# Led_Driver.net
KiCad netlist of a schematic drawn in EAGLE
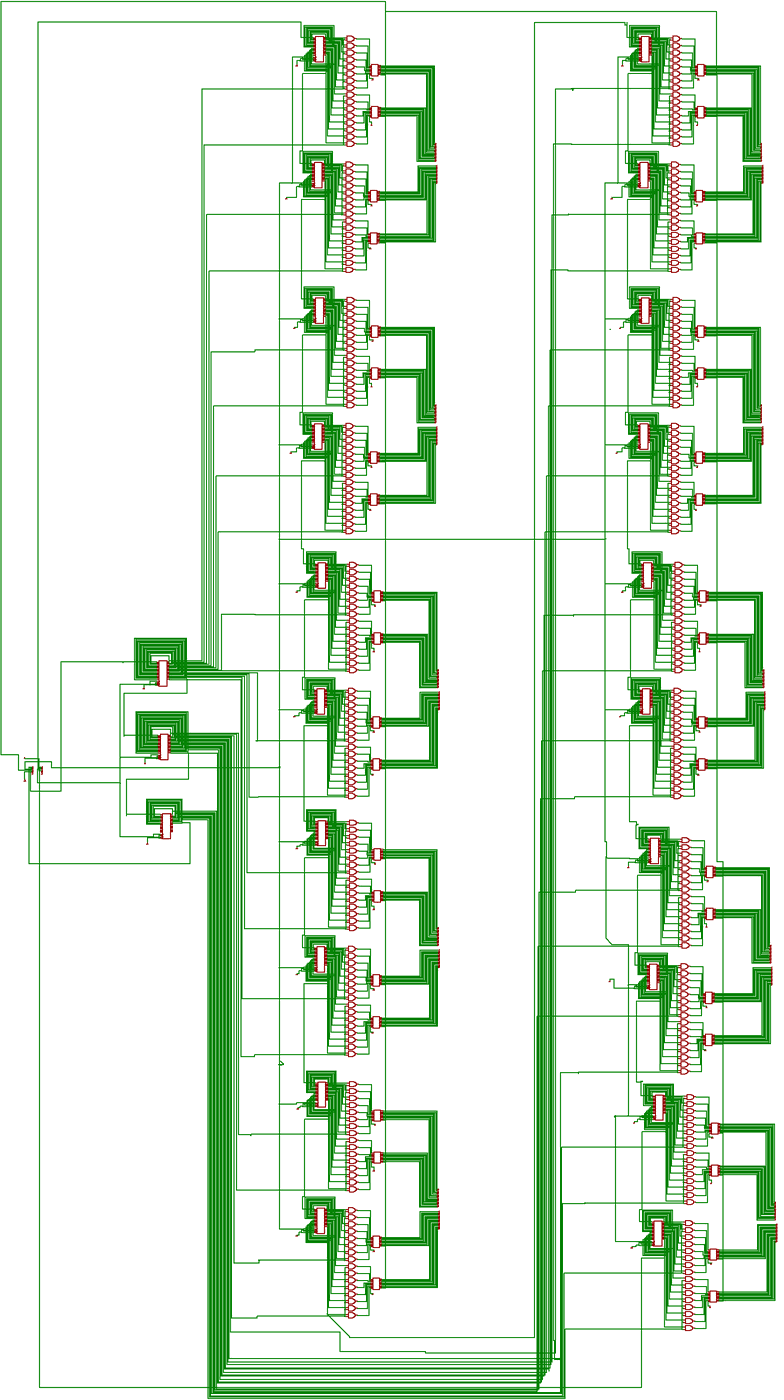
[diagram p0: schematic, sheet 1, overview]
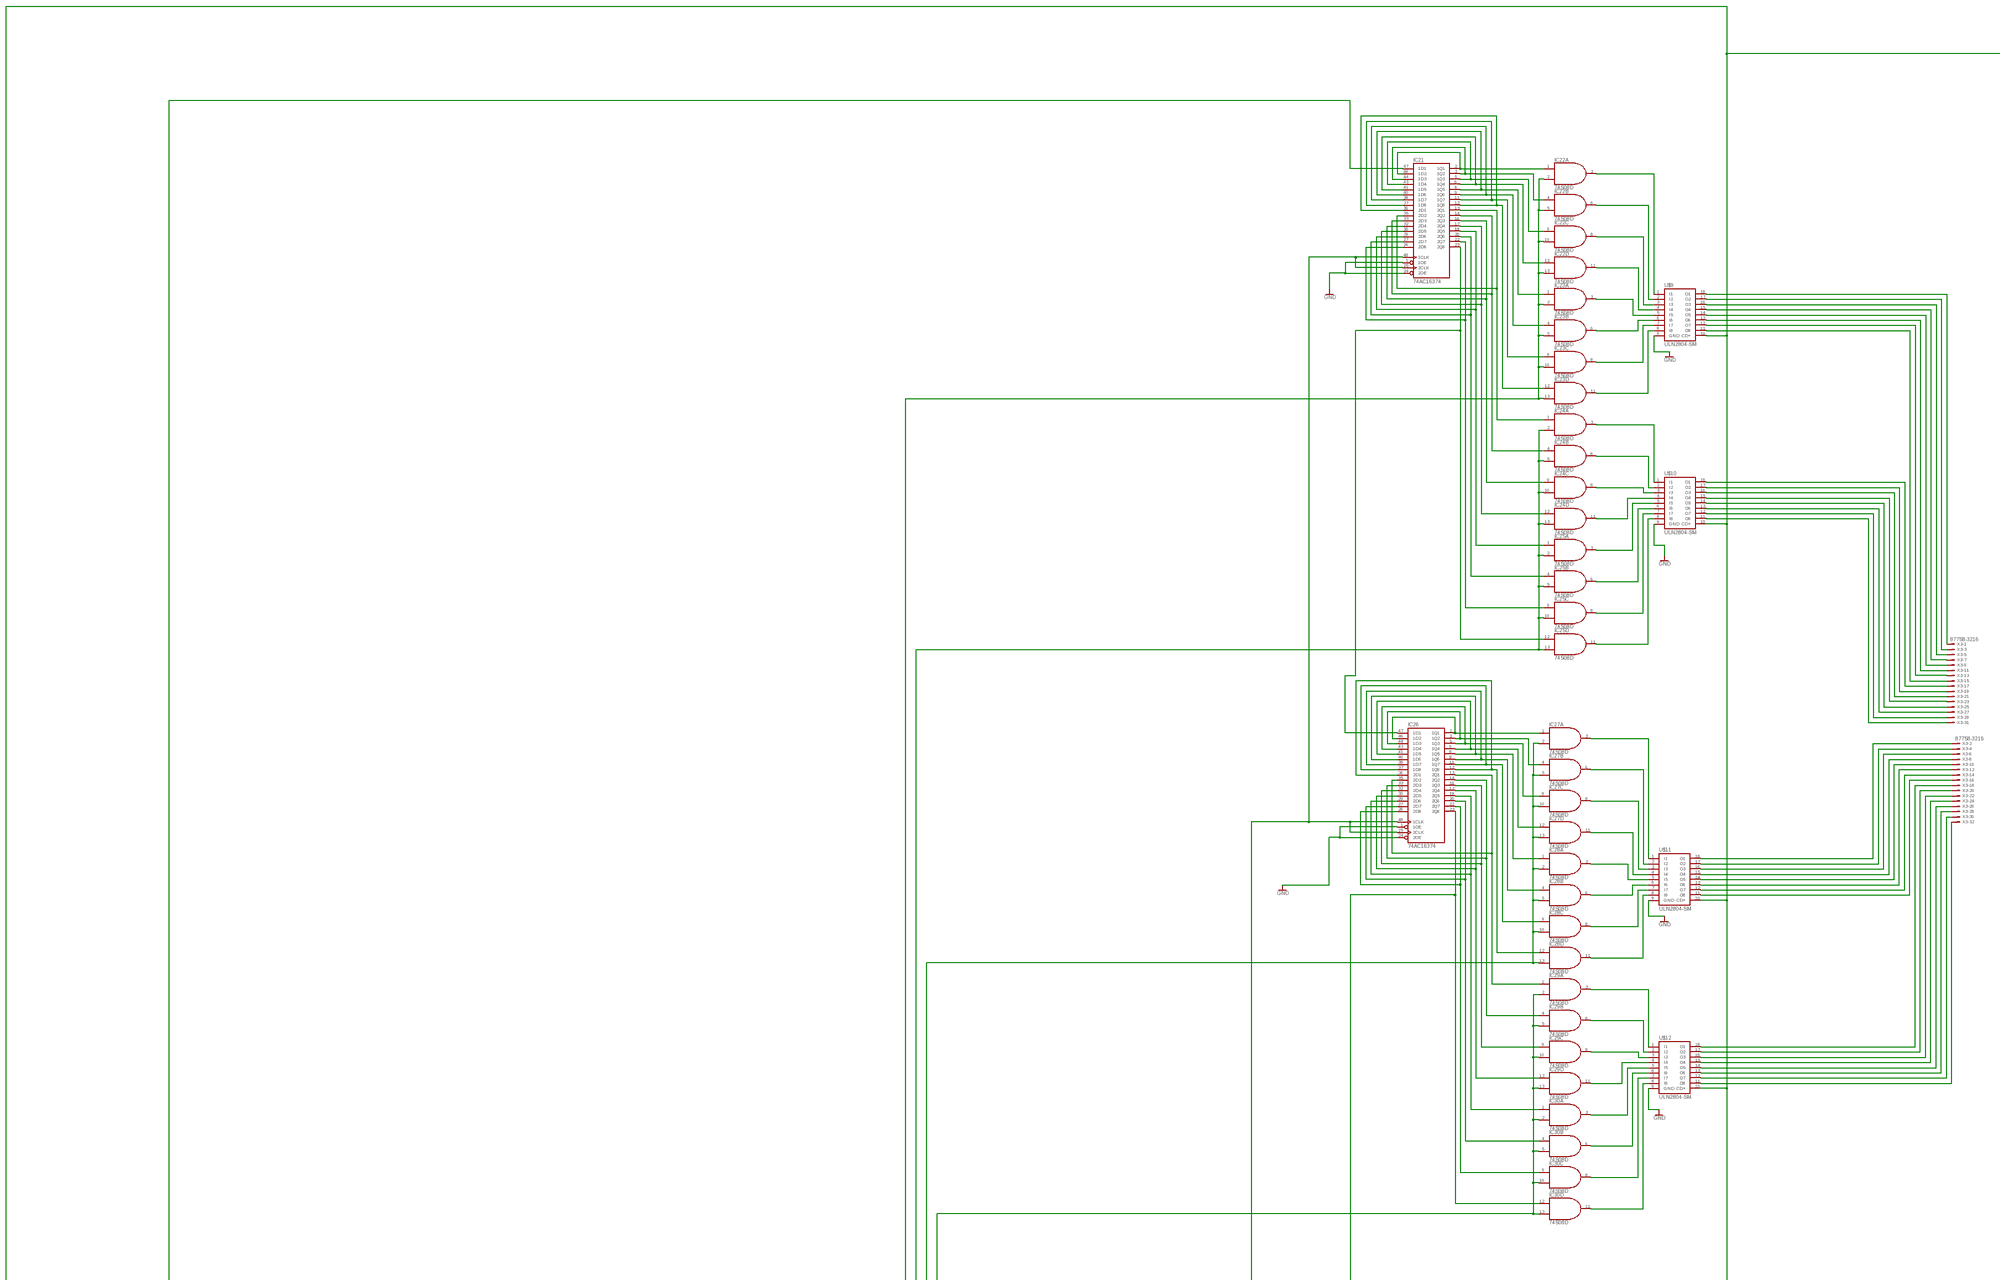
[diagram p1: schematic, sheet 1, part 1 of 8]
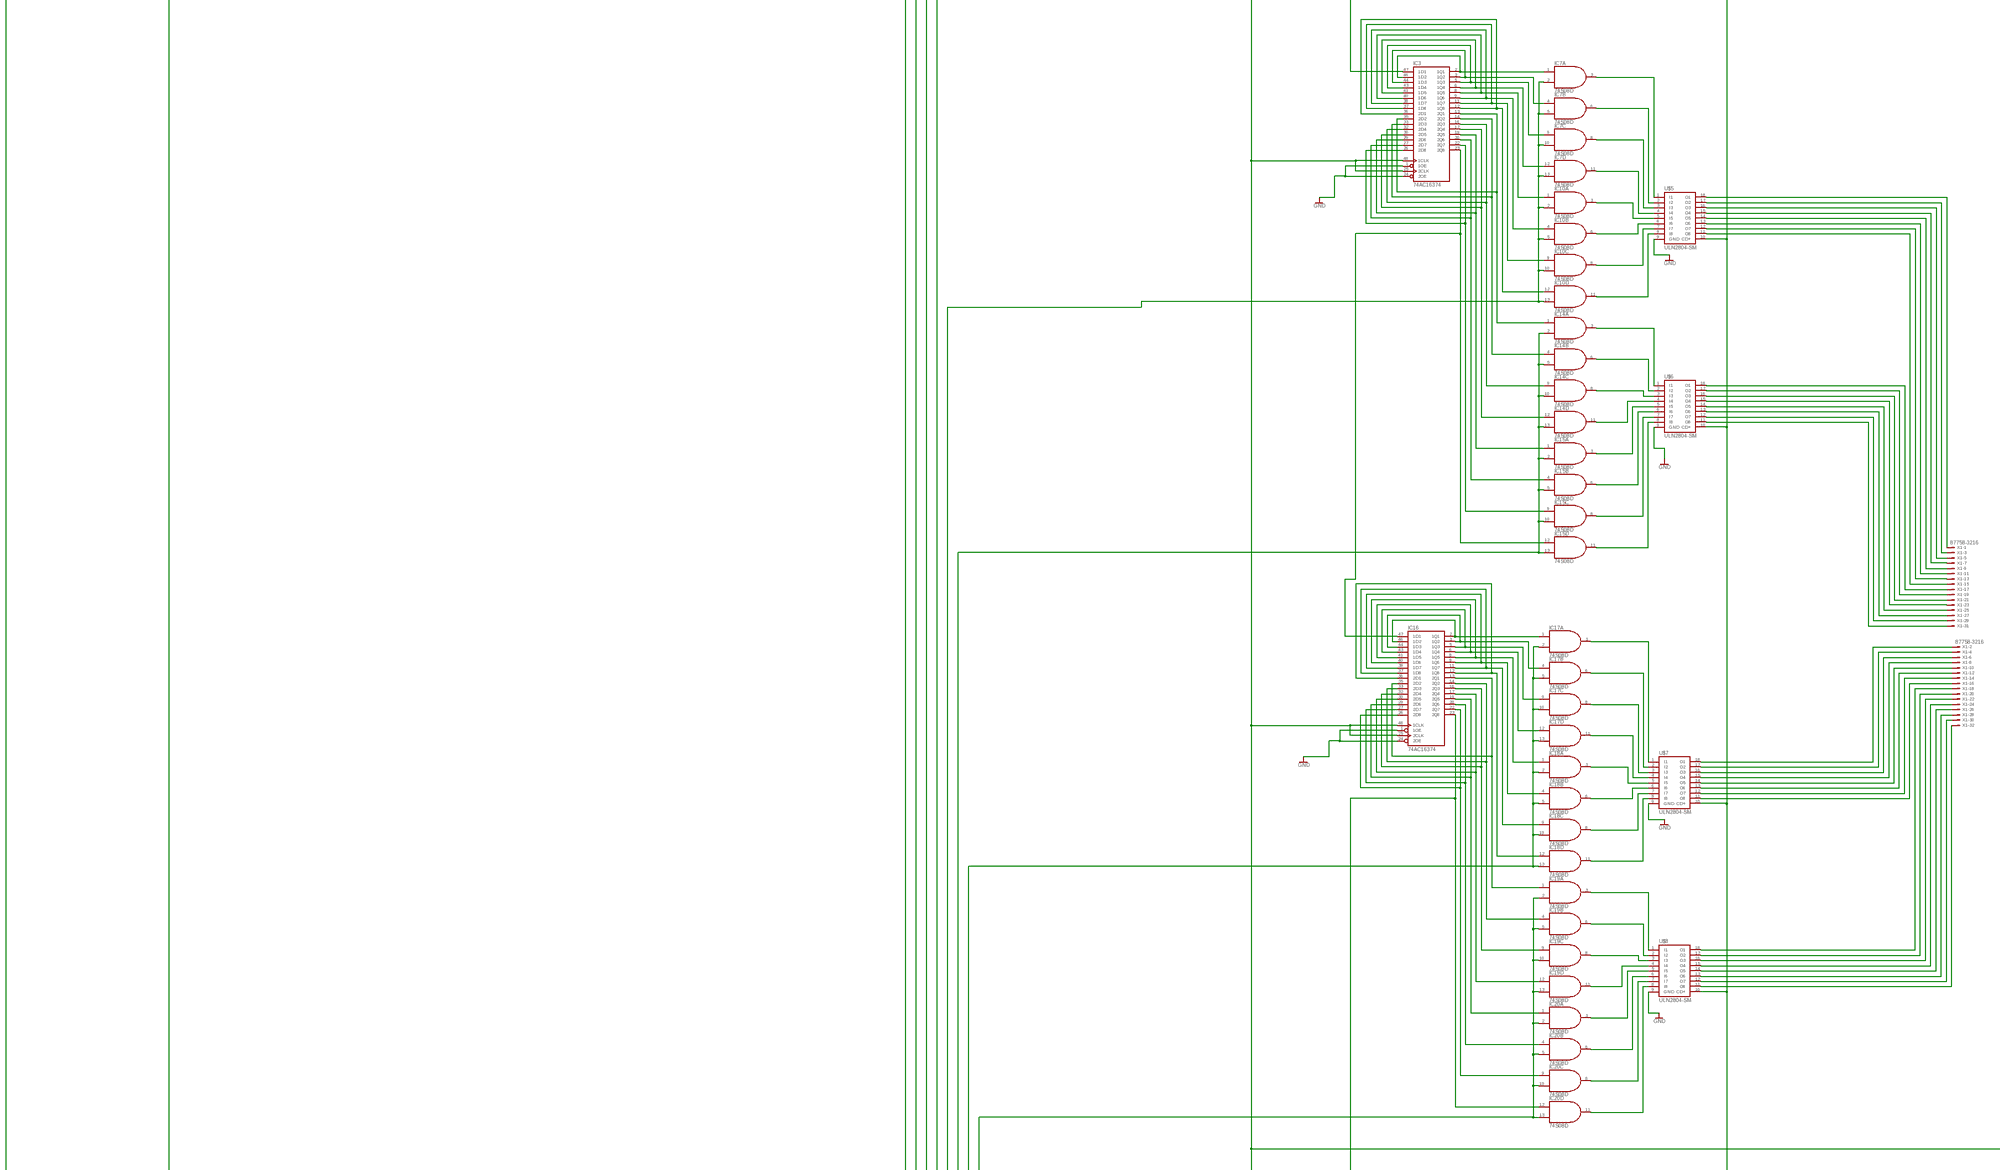
[diagram p2: schematic, sheet 1, part 2 of 8]
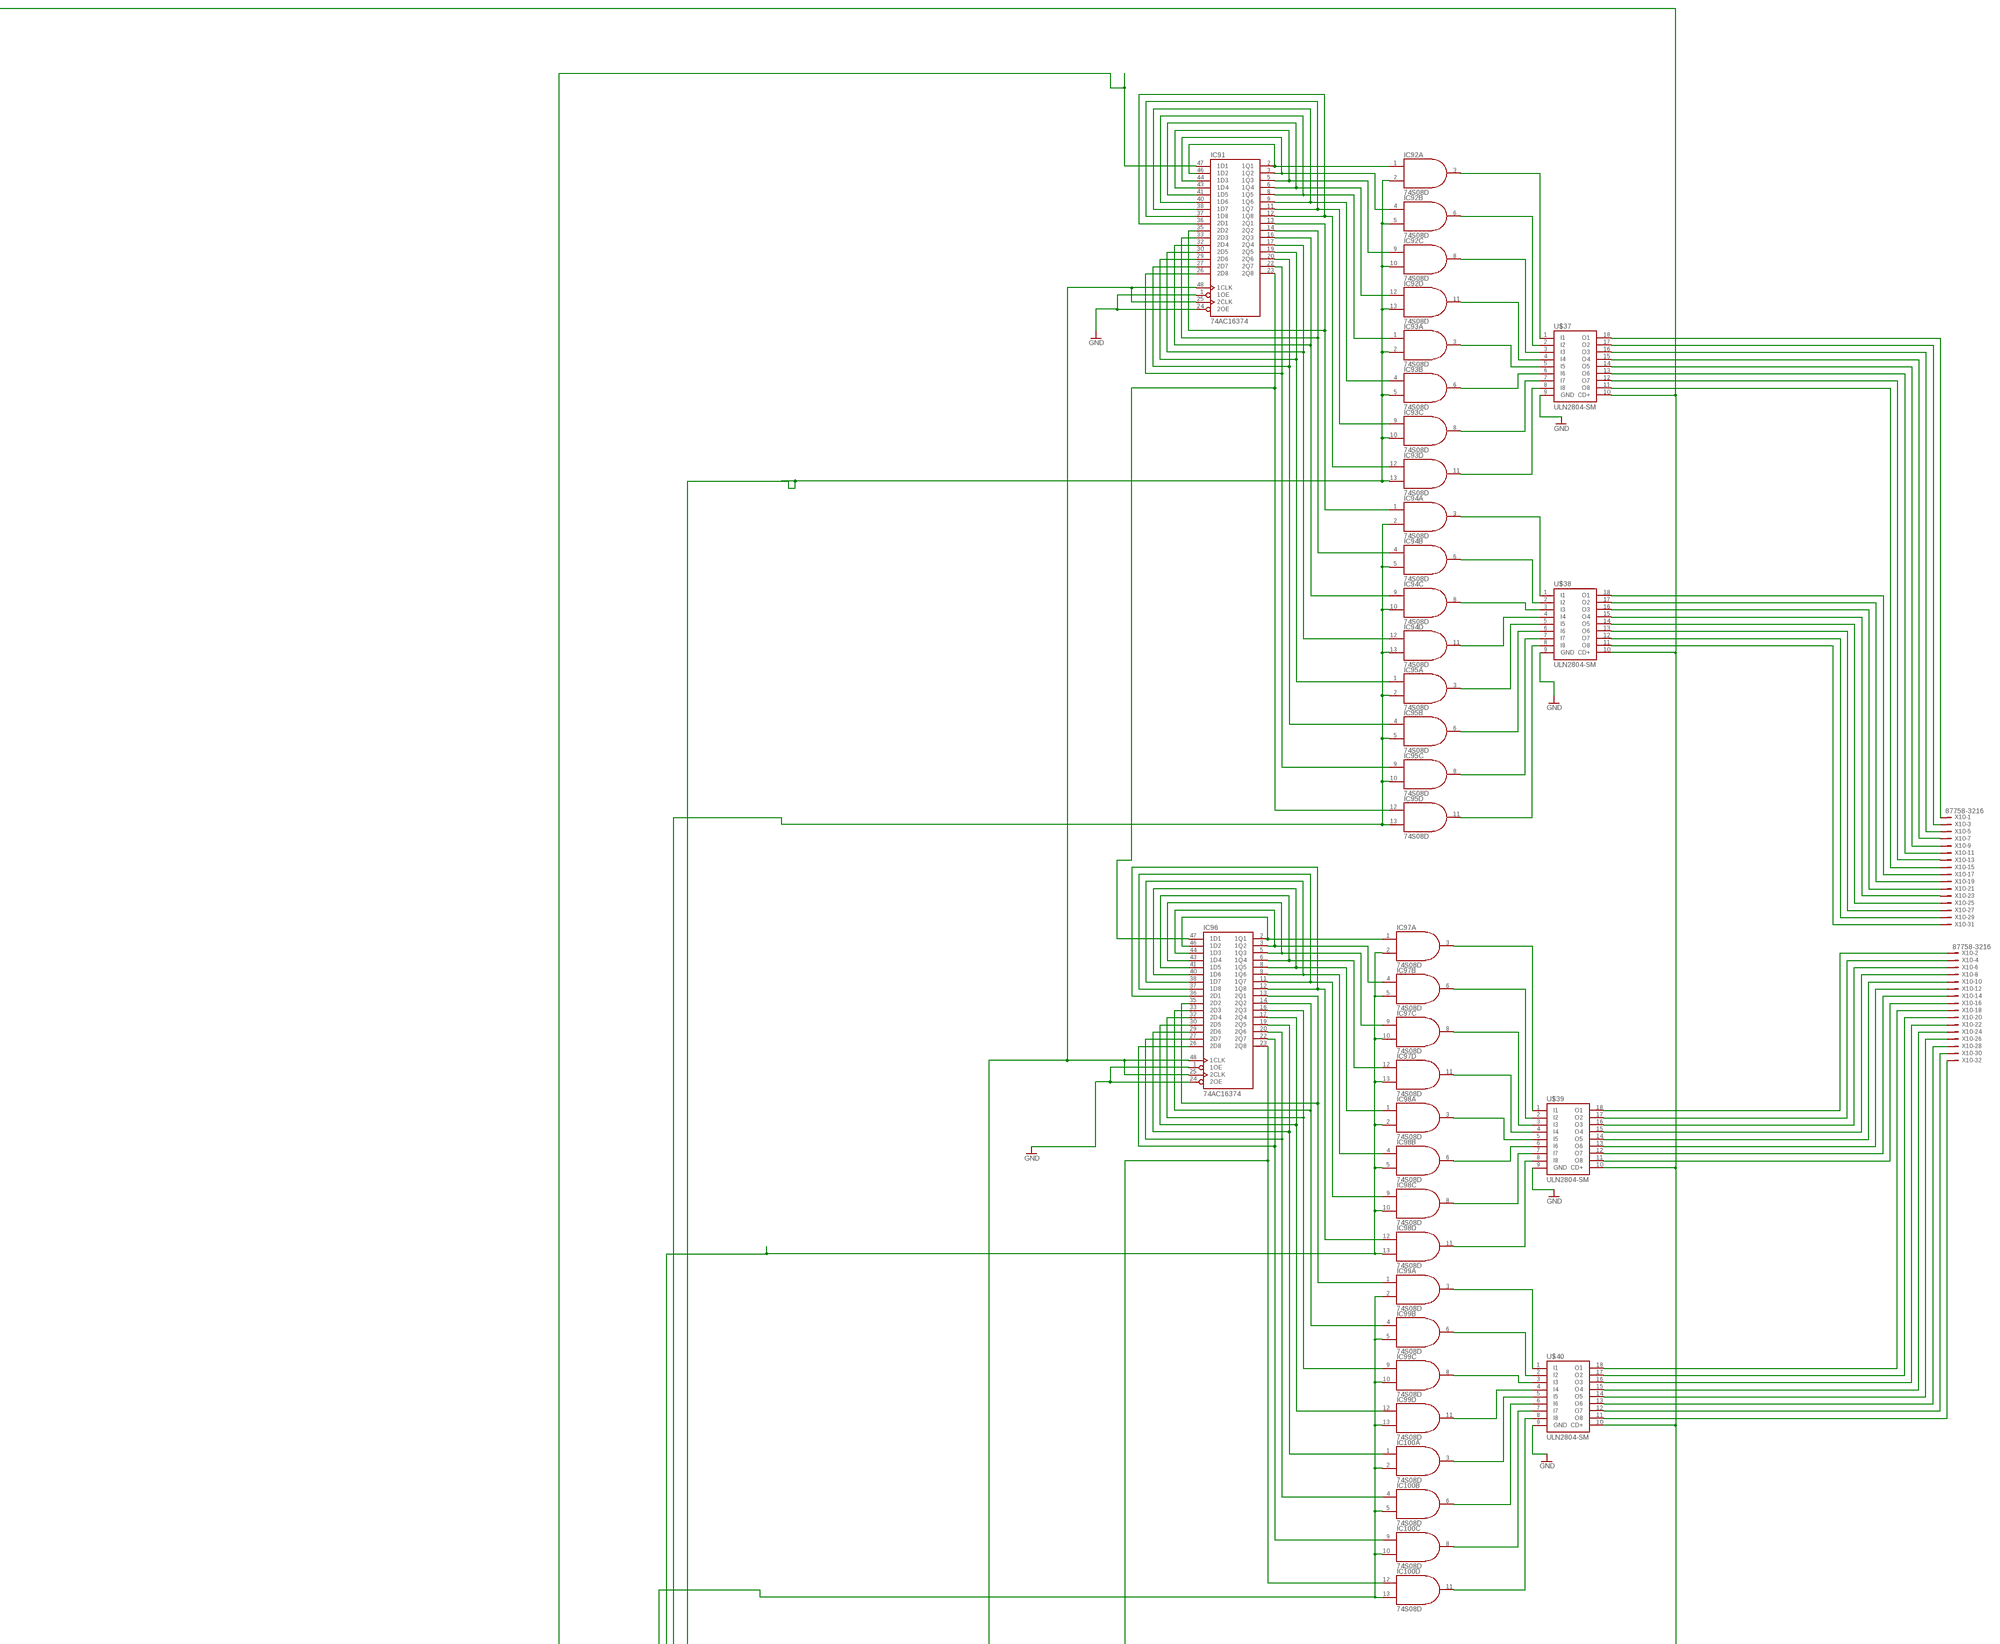
[diagram p3: schematic, sheet 1, part 3 of 8]
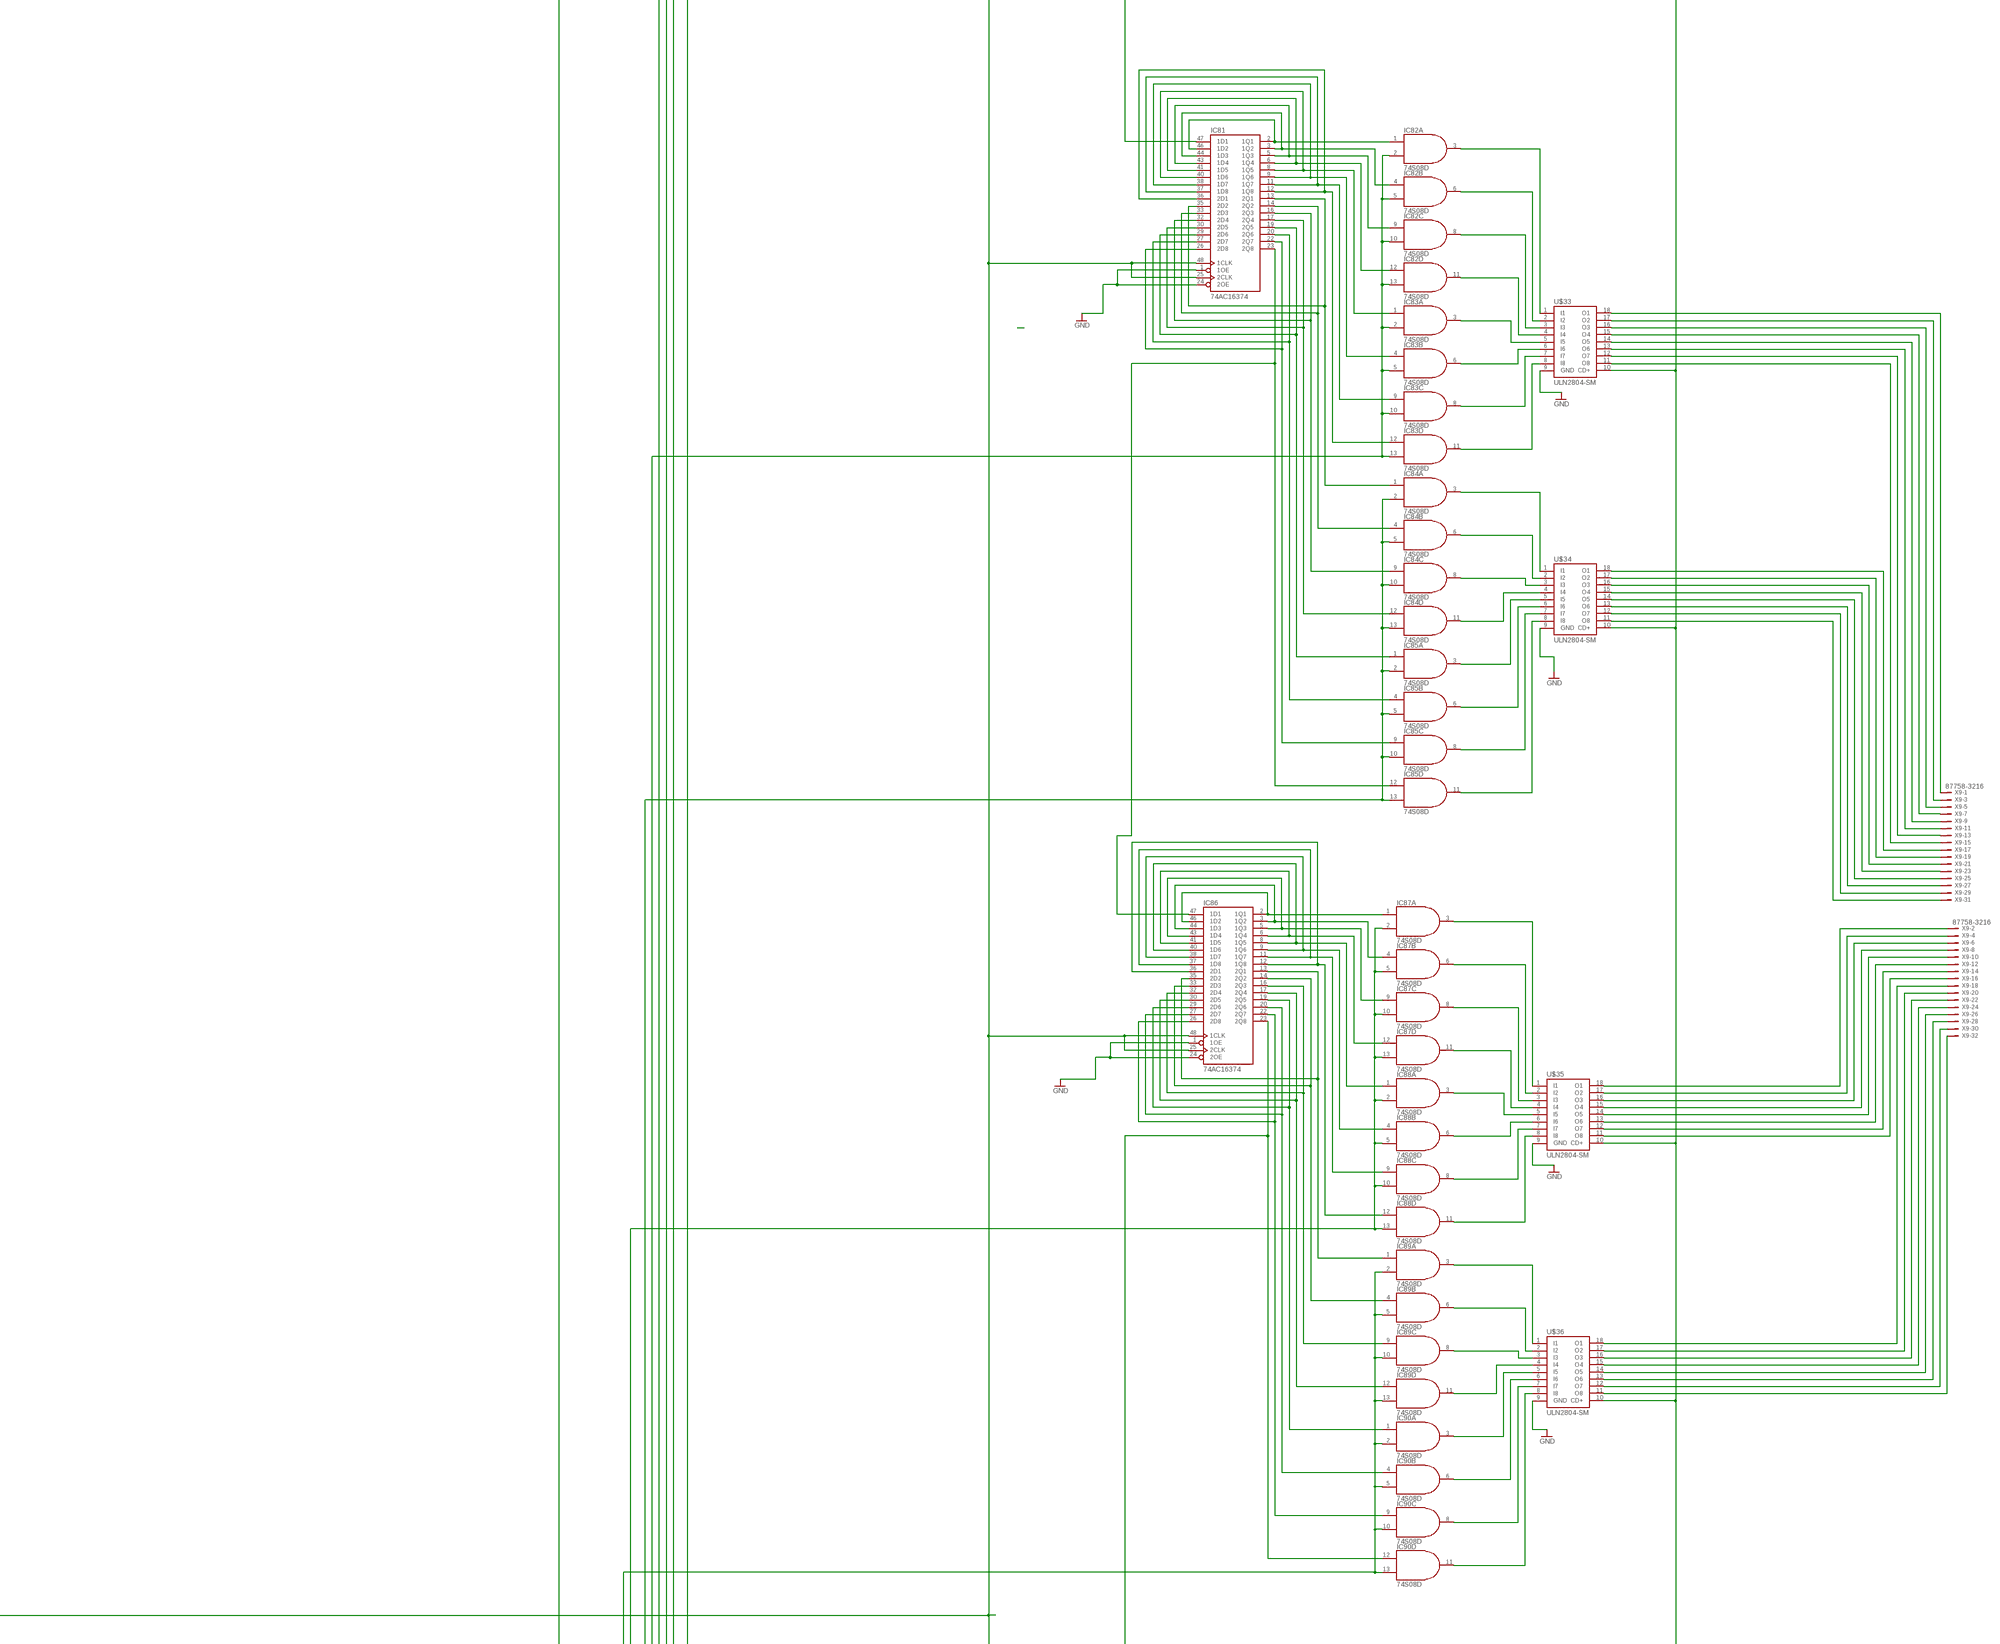
[diagram p4: schematic, sheet 1, part 4 of 8]
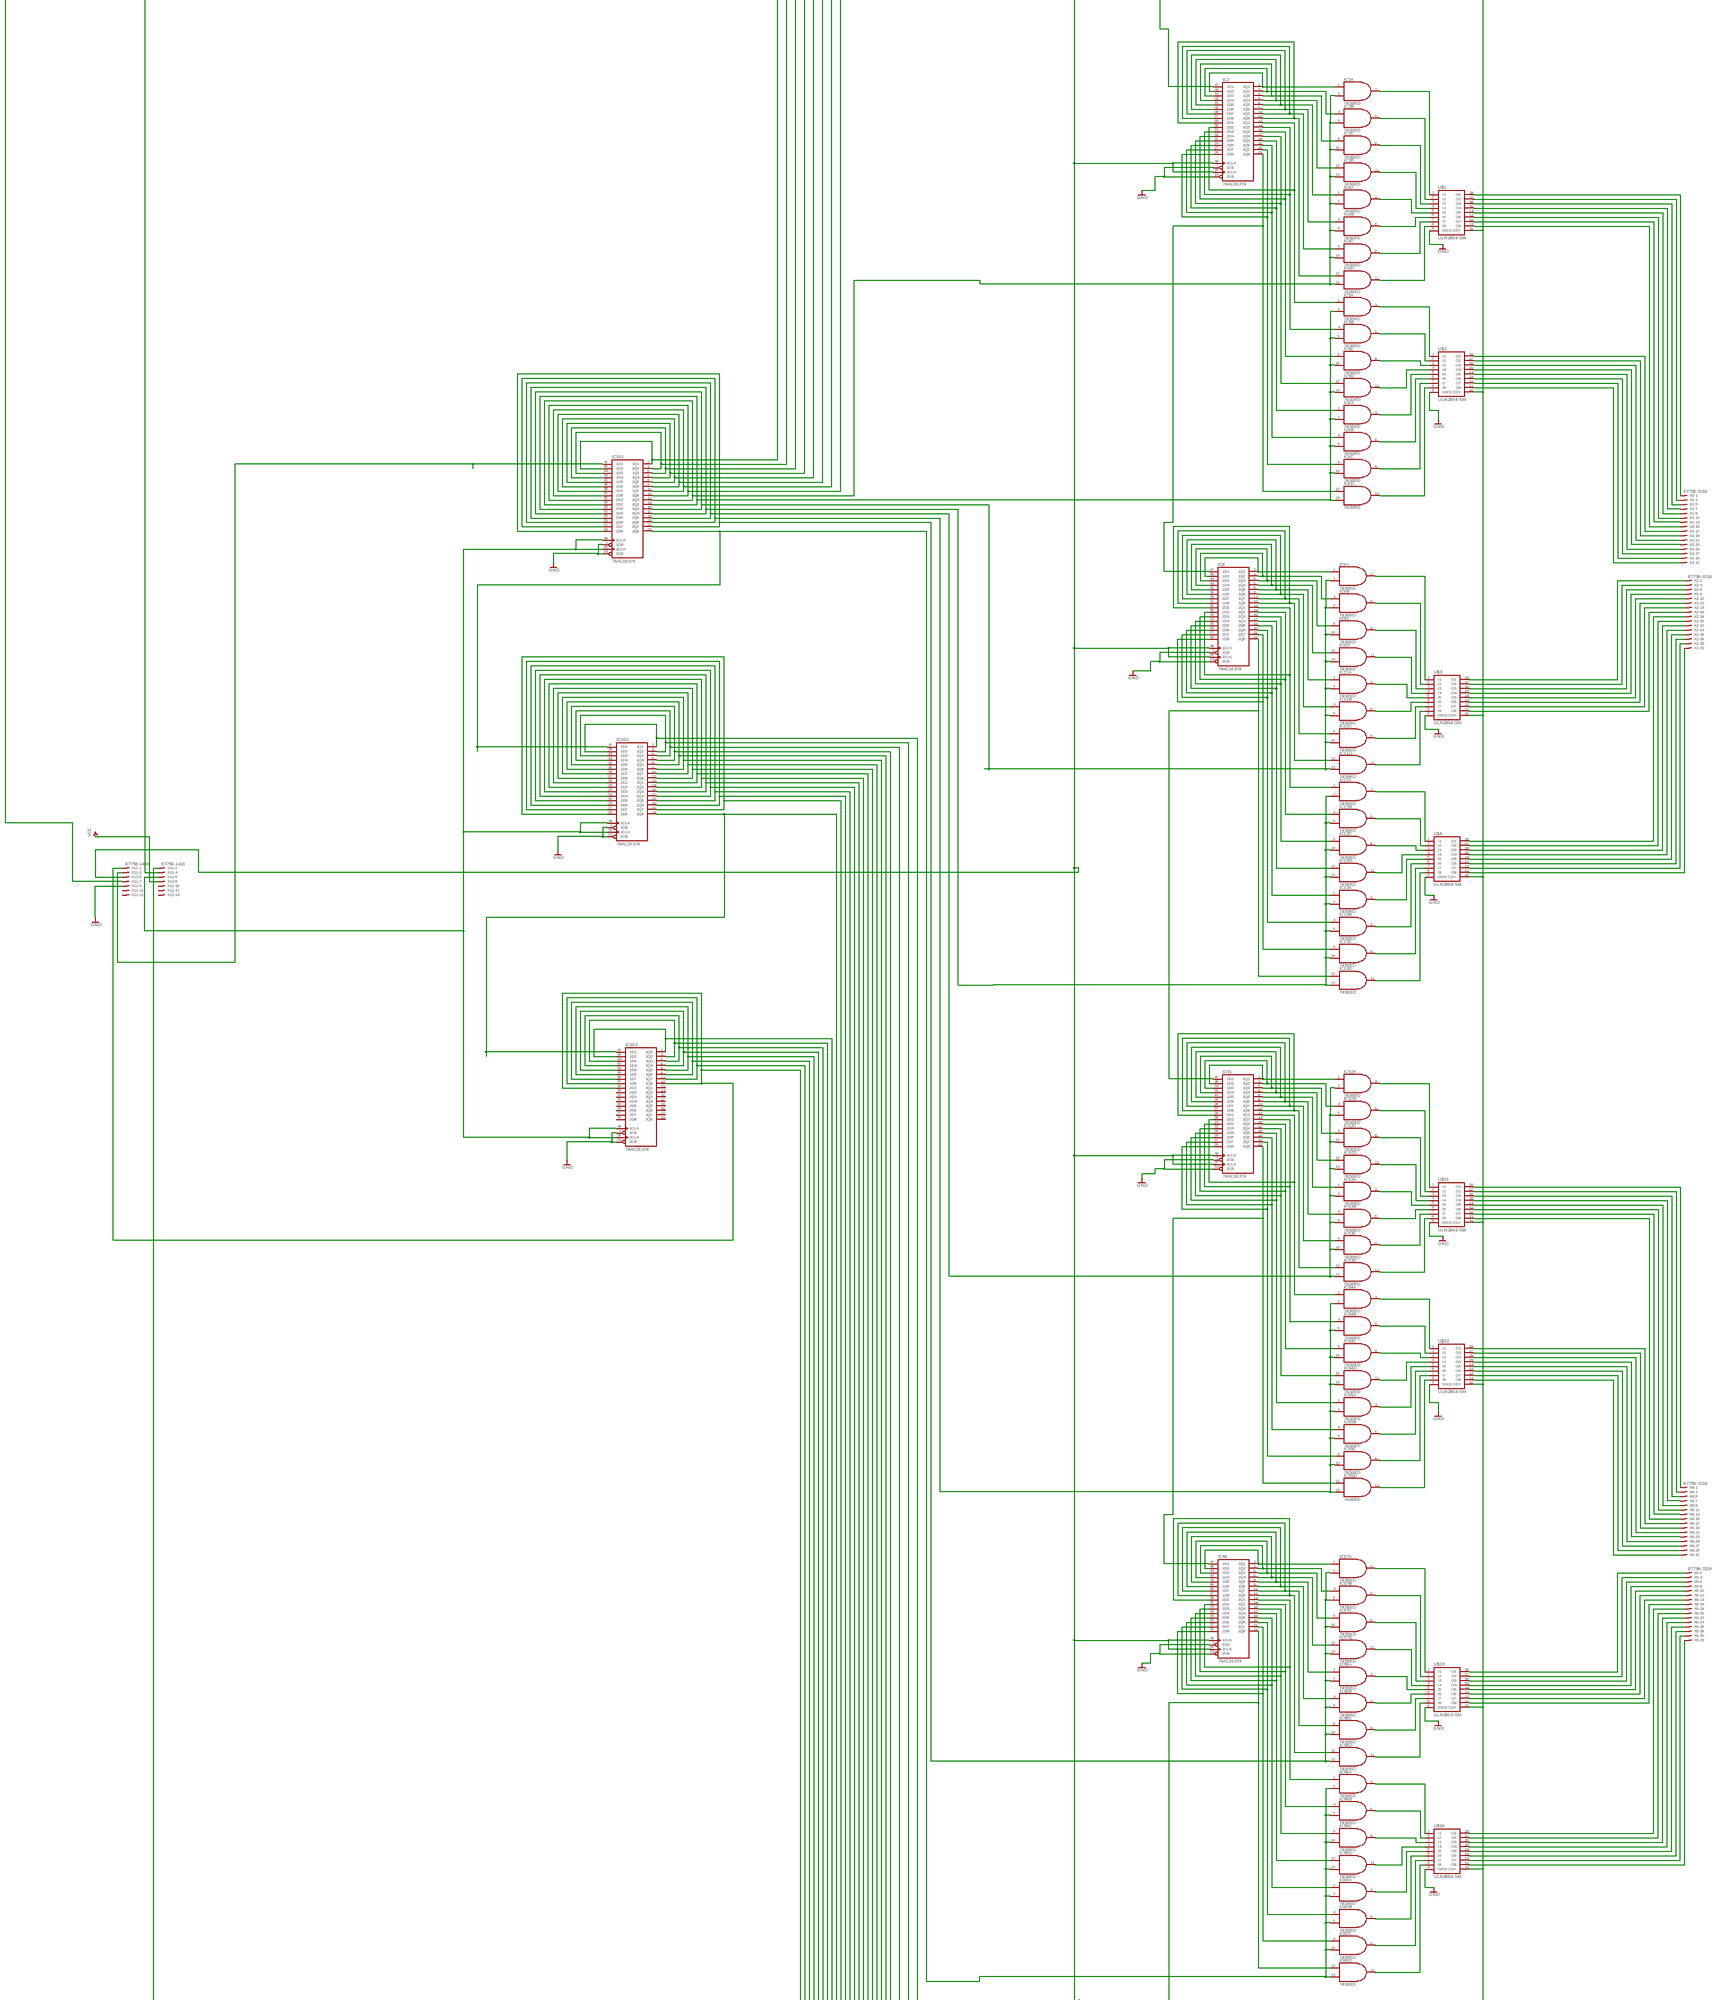
[diagram p5: schematic, sheet 1, part 5 of 8]
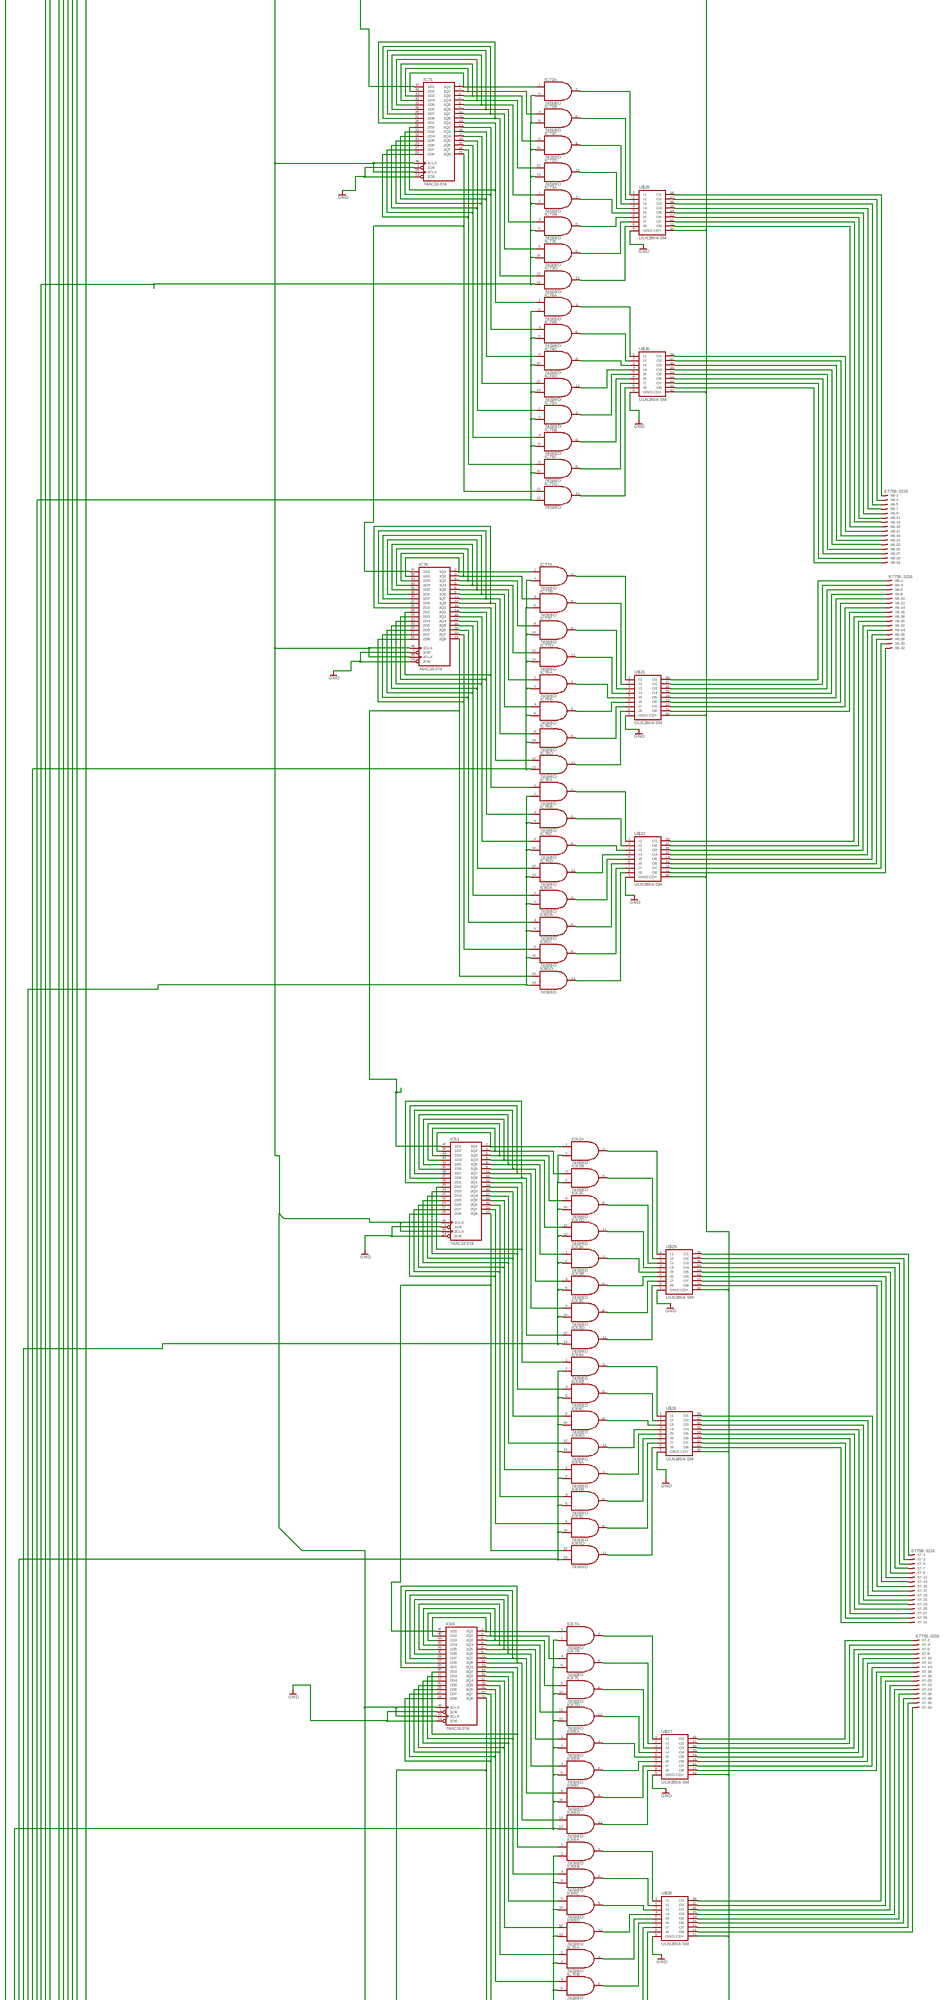
[diagram p6: schematic, sheet 1, part 6 of 8]
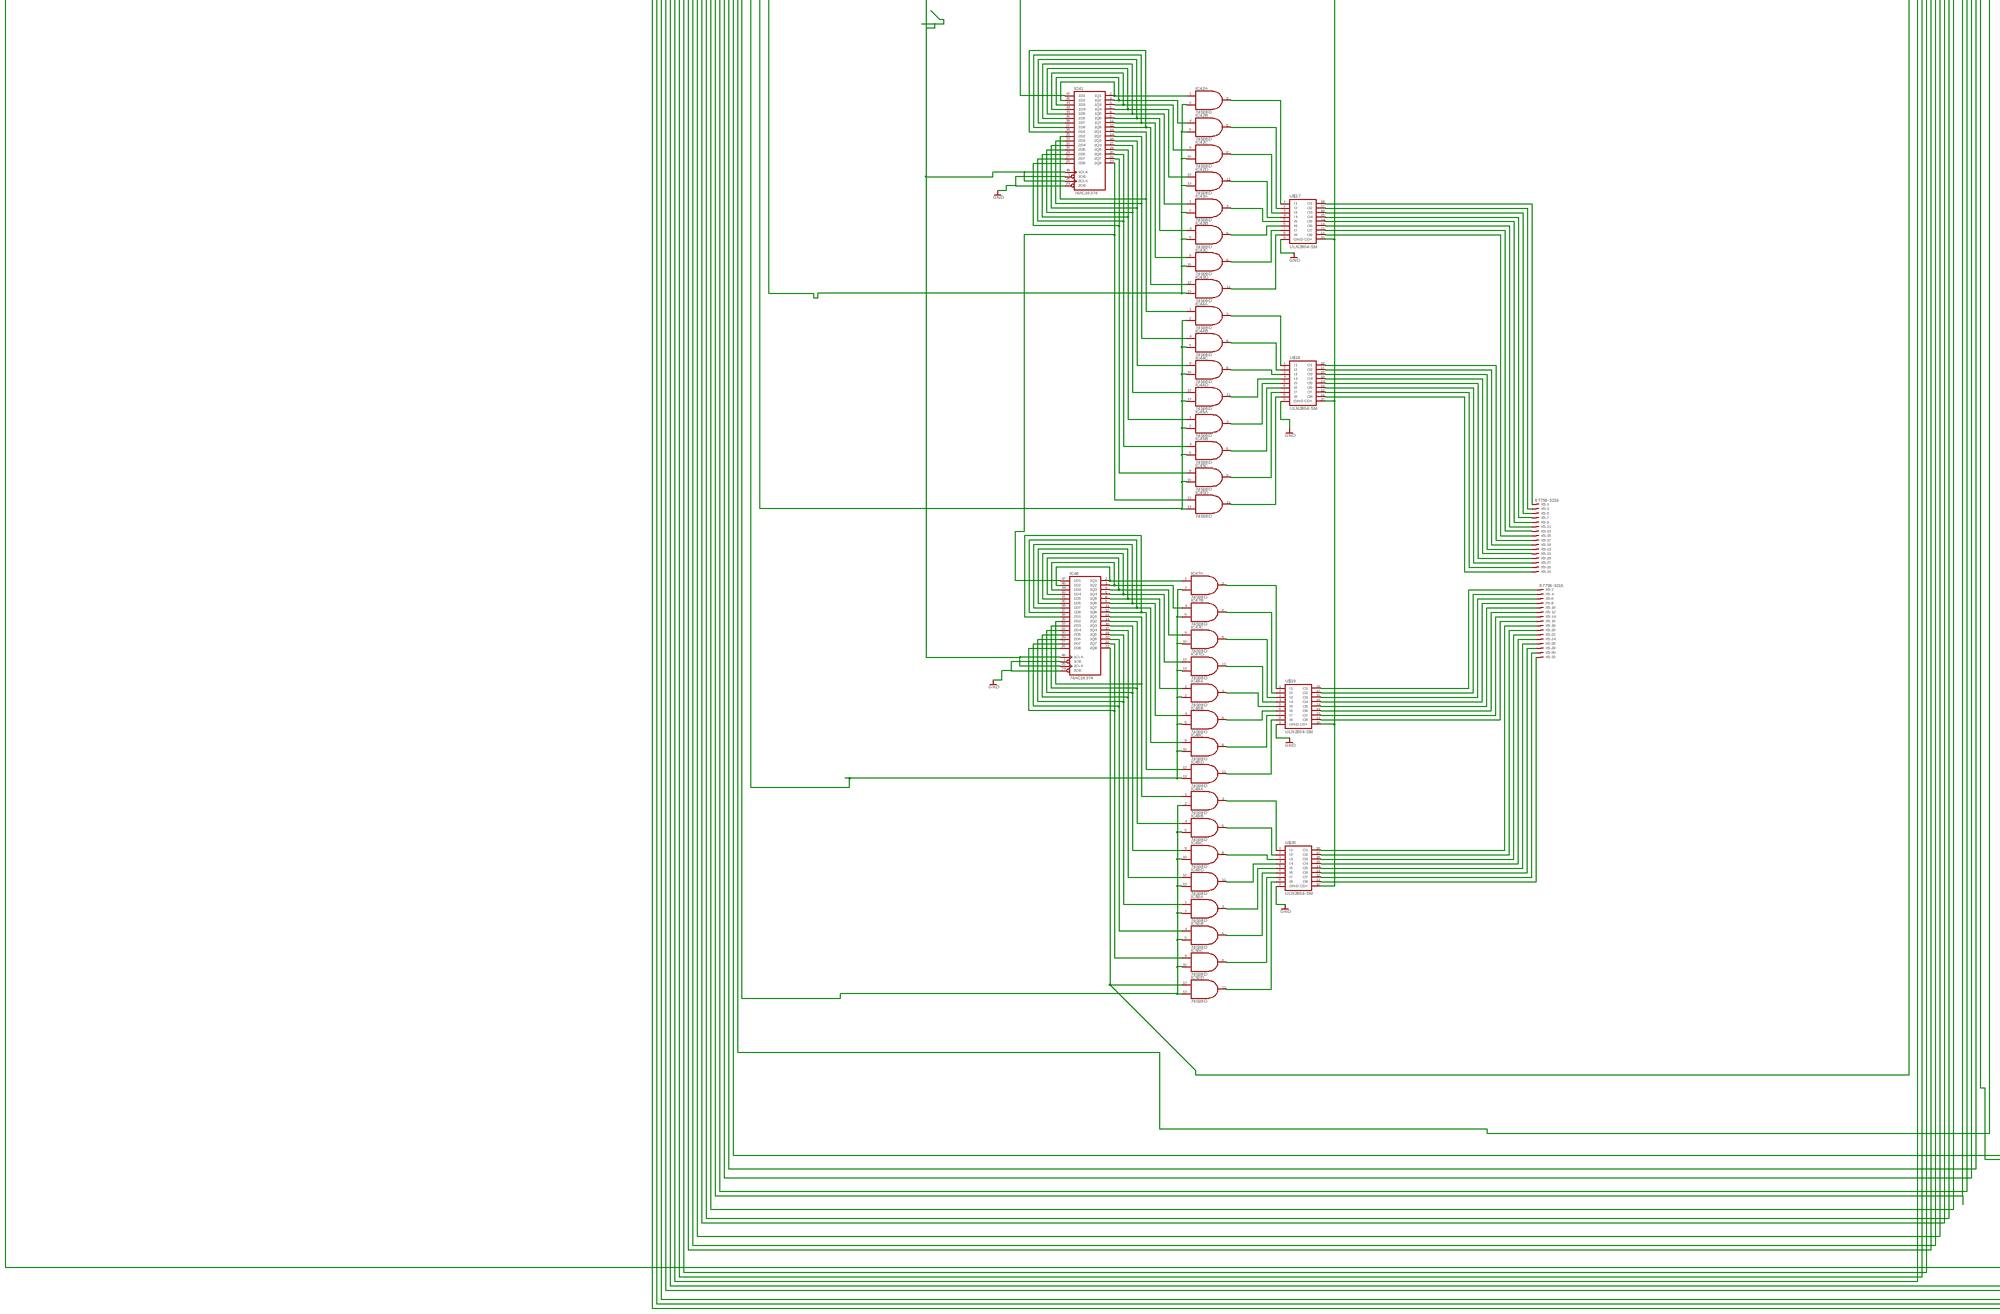
[diagram p7: schematic, sheet 1, part 7 of 8]
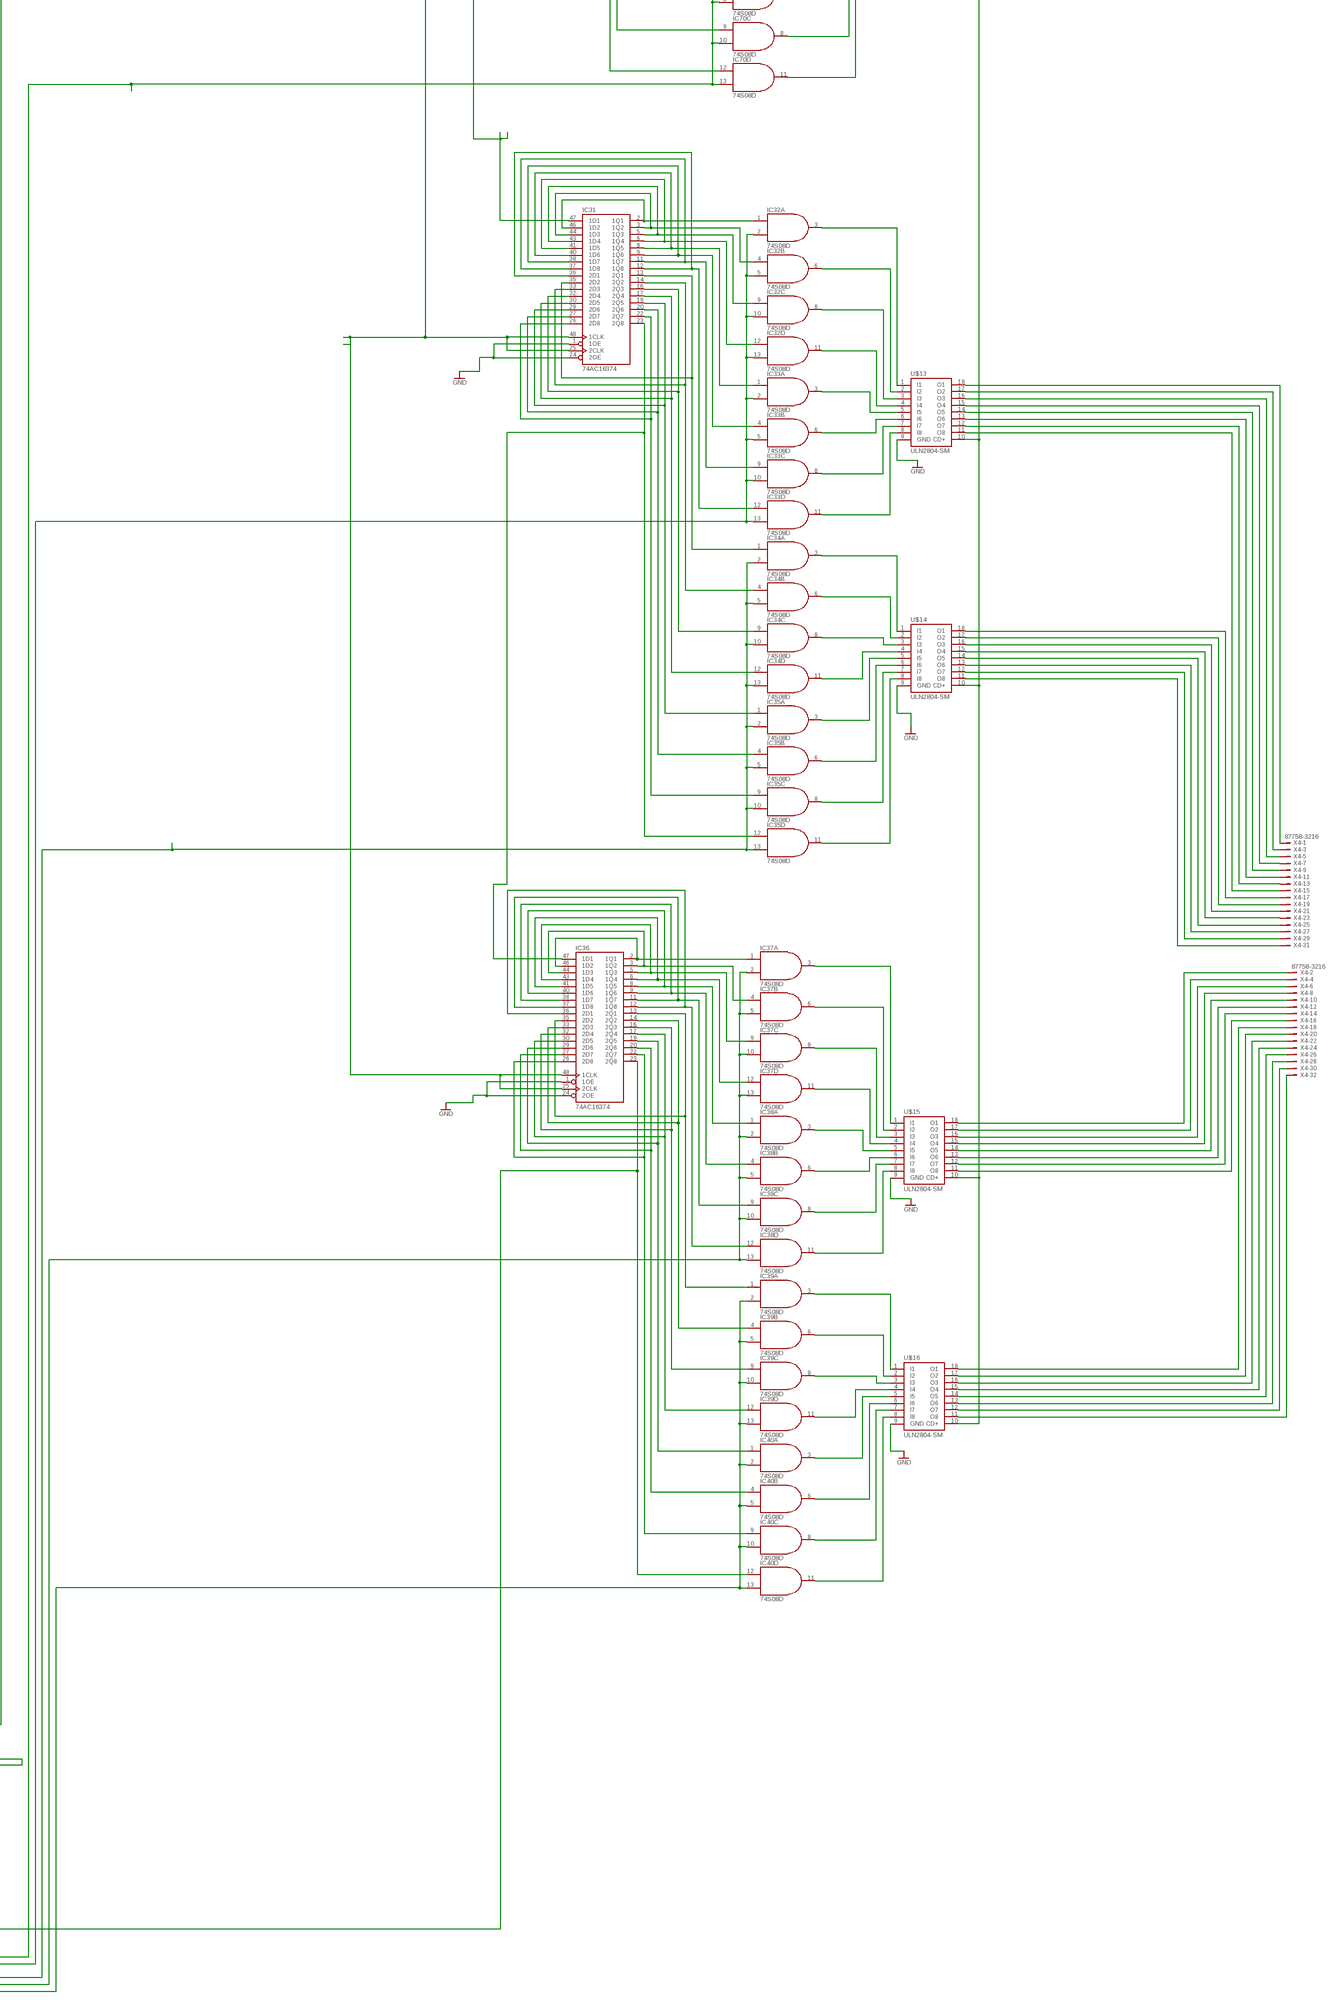
[diagram p8: schematic, sheet 1, part 8 of 8]

(export (version "E")
  (design (tool "Eeschema 10.0.6"))
  (components
    (comp (ref "IC1")
      (value "74AC16374")
      (footprint "eagle-import:SSOP48DL")
      (libsource (lib "eagle-import") (part "74AC16374"))
    )
    (comp (ref "IC2")
      (value "74S08D")
      (footprint "eagle-import:SO14")
      (libsource (lib "eagle-import") (part "7408DS"))
    )
    (comp (ref "IC3")
      (value "74AC16374")
      (footprint "eagle-import:SSOP48DL")
      (libsource (lib "eagle-import") (part "74AC16374"))
    )
    (comp (ref "IC4")
      (value "74S08D")
      (footprint "eagle-import:SO14")
      (libsource (lib "eagle-import") (part "7408DS"))
    )
    (comp (ref "IC5")
      (value "74S08D")
      (footprint "eagle-import:SO14")
      (libsource (lib "eagle-import") (part "7408DS"))
    )
    (comp (ref "IC6")
      (value "74S08D")
      (footprint "eagle-import:SO14")
      (libsource (lib "eagle-import") (part "7408DS"))
    )
    (comp (ref "IC7")
      (value "74S08D")
      (footprint "eagle-import:SO14")
      (libsource (lib "eagle-import") (part "7408DS"))
    )
    (comp (ref "IC8")
      (value "74AC16374")
      (footprint "eagle-import:SSOP48DL")
      (libsource (lib "eagle-import") (part "74AC16374"))
    )
    (comp (ref "IC9")
      (value "74S08D")
      (footprint "eagle-import:SO14")
      (libsource (lib "eagle-import") (part "7408DS"))
    )
    (comp (ref "IC10")
      (value "74S08D")
      (footprint "eagle-import:SO14")
      (libsource (lib "eagle-import") (part "7408DS"))
    )
    (comp (ref "IC11")
      (value "74S08D")
      (footprint "eagle-import:SO14")
      (libsource (lib "eagle-import") (part "7408DS"))
    )
    (comp (ref "IC12")
      (value "74S08D")
      (footprint "eagle-import:SO14")
      (libsource (lib "eagle-import") (part "7408DS"))
    )
    (comp (ref "IC13")
      (value "74S08D")
      (footprint "eagle-import:SO14")
      (libsource (lib "eagle-import") (part "7408DS"))
    )
    (comp (ref "IC14")
      (value "74S08D")
      (footprint "eagle-import:SO14")
      (libsource (lib "eagle-import") (part "7408DS"))
    )
    (comp (ref "IC15")
      (value "74S08D")
      (footprint "eagle-import:SO14")
      (libsource (lib "eagle-import") (part "7408DS"))
    )
    (comp (ref "IC16")
      (value "74AC16374")
      (footprint "eagle-import:SSOP48DL")
      (libsource (lib "eagle-import") (part "74AC16374"))
    )
    (comp (ref "IC17")
      (value "74S08D")
      (footprint "eagle-import:SO14")
      (libsource (lib "eagle-import") (part "7408DS"))
    )
    (comp (ref "IC18")
      (value "74S08D")
      (footprint "eagle-import:SO14")
      (libsource (lib "eagle-import") (part "7408DS"))
    )
    (comp (ref "IC19")
      (value "74S08D")
      (footprint "eagle-import:SO14")
      (libsource (lib "eagle-import") (part "7408DS"))
    )
    (comp (ref "IC20")
      (value "74S08D")
      (footprint "eagle-import:SO14")
      (libsource (lib "eagle-import") (part "7408DS"))
    )
    (comp (ref "IC21")
      (value "74AC16374")
      (footprint "eagle-import:SSOP48DL")
      (libsource (lib "eagle-import") (part "74AC16374"))
    )
    (comp (ref "IC22")
      (value "74S08D")
      (footprint "eagle-import:SO14")
      (libsource (lib "eagle-import") (part "7408DS"))
    )
    (comp (ref "IC23")
      (value "74S08D")
      (footprint "eagle-import:SO14")
      (libsource (lib "eagle-import") (part "7408DS"))
    )
    (comp (ref "IC24")
      (value "74S08D")
      (footprint "eagle-import:SO14")
      (libsource (lib "eagle-import") (part "7408DS"))
    )
    (comp (ref "IC25")
      (value "74S08D")
      (footprint "eagle-import:SO14")
      (libsource (lib "eagle-import") (part "7408DS"))
    )
    (comp (ref "IC26")
      (value "74AC16374")
      (footprint "eagle-import:SSOP48DL")
      (libsource (lib "eagle-import") (part "74AC16374"))
    )
    (comp (ref "IC27")
      (value "74S08D")
      (footprint "eagle-import:SO14")
      (libsource (lib "eagle-import") (part "7408DS"))
    )
    (comp (ref "IC28")
      (value "74S08D")
      (footprint "eagle-import:SO14")
      (libsource (lib "eagle-import") (part "7408DS"))
    )
    (comp (ref "IC29")
      (value "74S08D")
      (footprint "eagle-import:SO14")
      (libsource (lib "eagle-import") (part "7408DS"))
    )
    (comp (ref "IC30")
      (value "74S08D")
      (footprint "eagle-import:SO14")
      (libsource (lib "eagle-import") (part "7408DS"))
    )
    (comp (ref "IC31")
      (value "74AC16374")
      (footprint "eagle-import:SSOP48DL")
      (libsource (lib "eagle-import") (part "74AC16374"))
    )
    (comp (ref "IC32")
      (value "74S08D")
      (footprint "eagle-import:SO14")
      (libsource (lib "eagle-import") (part "7408DS"))
    )
    (comp (ref "IC33")
      (value "74S08D")
      (footprint "eagle-import:SO14")
      (libsource (lib "eagle-import") (part "7408DS"))
    )
    (comp (ref "IC34")
      (value "74S08D")
      (footprint "eagle-import:SO14")
      (libsource (lib "eagle-import") (part "7408DS"))
    )
    (comp (ref "IC35")
      (value "74S08D")
      (footprint "eagle-import:SO14")
      (libsource (lib "eagle-import") (part "7408DS"))
    )
    (comp (ref "IC36")
      (value "74AC16374")
      (footprint "eagle-import:SSOP48DL")
      (libsource (lib "eagle-import") (part "74AC16374"))
    )
    (comp (ref "IC37")
      (value "74S08D")
      (footprint "eagle-import:SO14")
      (libsource (lib "eagle-import") (part "7408DS"))
    )
    (comp (ref "IC38")
      (value "74S08D")
      (footprint "eagle-import:SO14")
      (libsource (lib "eagle-import") (part "7408DS"))
    )
    (comp (ref "IC39")
      (value "74S08D")
      (footprint "eagle-import:SO14")
      (libsource (lib "eagle-import") (part "7408DS"))
    )
    (comp (ref "IC40")
      (value "74S08D")
      (footprint "eagle-import:SO14")
      (libsource (lib "eagle-import") (part "7408DS"))
    )
    (comp (ref "IC41")
      (value "74AC16374")
      (footprint "eagle-import:SSOP48DL")
      (libsource (lib "eagle-import") (part "74AC16374"))
    )
    (comp (ref "IC42")
      (value "74S08D")
      (footprint "eagle-import:SO14")
      (libsource (lib "eagle-import") (part "7408DS"))
    )
    (comp (ref "IC43")
      (value "74S08D")
      (footprint "eagle-import:SO14")
      (libsource (lib "eagle-import") (part "7408DS"))
    )
    (comp (ref "IC44")
      (value "74S08D")
      (footprint "eagle-import:SO14")
      (libsource (lib "eagle-import") (part "7408DS"))
    )
    (comp (ref "IC45")
      (value "74S08D")
      (footprint "eagle-import:SO14")
      (libsource (lib "eagle-import") (part "7408DS"))
    )
    (comp (ref "IC46")
      (value "74AC16374")
      (footprint "eagle-import:SSOP48DL")
      (libsource (lib "eagle-import") (part "74AC16374"))
    )
    (comp (ref "IC47")
      (value "74S08D")
      (footprint "eagle-import:SO14")
      (libsource (lib "eagle-import") (part "7408DS"))
    )
    (comp (ref "IC48")
      (value "74S08D")
      (footprint "eagle-import:SO14")
      (libsource (lib "eagle-import") (part "7408DS"))
    )
    (comp (ref "IC49")
      (value "74S08D")
      (footprint "eagle-import:SO14")
      (libsource (lib "eagle-import") (part "7408DS"))
    )
    (comp (ref "IC50")
      (value "74S08D")
      (footprint "eagle-import:SO14")
      (libsource (lib "eagle-import") (part "7408DS"))
    )
    (comp (ref "IC51")
      (value "74AC16374")
      (footprint "eagle-import:SSOP48DL")
      (libsource (lib "eagle-import") (part "74AC16374"))
    )
    (comp (ref "IC52")
      (value "74S08D")
      (footprint "eagle-import:SO14")
      (libsource (lib "eagle-import") (part "7408DS"))
    )
    (comp (ref "IC53")
      (value "74S08D")
      (footprint "eagle-import:SO14")
      (libsource (lib "eagle-import") (part "7408DS"))
    )
    (comp (ref "IC54")
      (value "74S08D")
      (footprint "eagle-import:SO14")
      (libsource (lib "eagle-import") (part "7408DS"))
    )
    (comp (ref "IC55")
      (value "74S08D")
      (footprint "eagle-import:SO14")
      (libsource (lib "eagle-import") (part "7408DS"))
    )
    (comp (ref "IC56")
      (value "74AC16374")
      (footprint "eagle-import:SSOP48DL")
      (libsource (lib "eagle-import") (part "74AC16374"))
    )
    (comp (ref "IC57")
      (value "74S08D")
      (footprint "eagle-import:SO14")
      (libsource (lib "eagle-import") (part "7408DS"))
    )
    (comp (ref "IC58")
      (value "74S08D")
      (footprint "eagle-import:SO14")
      (libsource (lib "eagle-import") (part "7408DS"))
    )
    (comp (ref "IC59")
      (value "74S08D")
      (footprint "eagle-import:SO14")
      (libsource (lib "eagle-import") (part "7408DS"))
    )
    (comp (ref "IC60")
      (value "74S08D")
      (footprint "eagle-import:SO14")
      (libsource (lib "eagle-import") (part "7408DS"))
    )
    (comp (ref "IC61")
      (value "74AC16374")
      (footprint "eagle-import:SSOP48DL")
      (libsource (lib "eagle-import") (part "74AC16374"))
    )
    (comp (ref "IC62")
      (value "74S08D")
      (footprint "eagle-import:SO14")
      (libsource (lib "eagle-import") (part "7408DS"))
    )
    (comp (ref "IC63")
      (value "74S08D")
      (footprint "eagle-import:SO14")
      (libsource (lib "eagle-import") (part "7408DS"))
    )
    (comp (ref "IC64")
      (value "74S08D")
      (footprint "eagle-import:SO14")
      (libsource (lib "eagle-import") (part "7408DS"))
    )
    (comp (ref "IC65")
      (value "74S08D")
      (footprint "eagle-import:SO14")
      (libsource (lib "eagle-import") (part "7408DS"))
    )
    (comp (ref "IC66")
      (value "74AC16374")
      (footprint "eagle-import:SSOP48DL")
      (libsource (lib "eagle-import") (part "74AC16374"))
    )
    (comp (ref "IC67")
      (value "74S08D")
      (footprint "eagle-import:SO14")
      (libsource (lib "eagle-import") (part "7408DS"))
    )
    (comp (ref "IC68")
      (value "74S08D")
      (footprint "eagle-import:SO14")
      (libsource (lib "eagle-import") (part "7408DS"))
    )
    (comp (ref "IC69")
      (value "74S08D")
      (footprint "eagle-import:SO14")
      (libsource (lib "eagle-import") (part "7408DS"))
    )
    (comp (ref "IC70")
      (value "74S08D")
      (footprint "eagle-import:SO14")
      (libsource (lib "eagle-import") (part "7408DS"))
    )
    (comp (ref "IC71")
      (value "74AC16374")
      (footprint "eagle-import:SSOP48DL")
      (libsource (lib "eagle-import") (part "74AC16374"))
    )
    (comp (ref "IC72")
      (value "74S08D")
      (footprint "eagle-import:SO14")
      (libsource (lib "eagle-import") (part "7408DS"))
    )
    (comp (ref "IC73")
      (value "74S08D")
      (footprint "eagle-import:SO14")
      (libsource (lib "eagle-import") (part "7408DS"))
    )
    (comp (ref "IC74")
      (value "74S08D")
      (footprint "eagle-import:SO14")
      (libsource (lib "eagle-import") (part "7408DS"))
    )
    (comp (ref "IC75")
      (value "74S08D")
      (footprint "eagle-import:SO14")
      (libsource (lib "eagle-import") (part "7408DS"))
    )
    (comp (ref "IC76")
      (value "74AC16374")
      (footprint "eagle-import:SSOP48DL")
      (libsource (lib "eagle-import") (part "74AC16374"))
    )
    (comp (ref "IC77")
      (value "74S08D")
      (footprint "eagle-import:SO14")
      (libsource (lib "eagle-import") (part "7408DS"))
    )
    (comp (ref "IC78")
      (value "74S08D")
      (footprint "eagle-import:SO14")
      (libsource (lib "eagle-import") (part "7408DS"))
    )
    (comp (ref "IC79")
      (value "74S08D")
      (footprint "eagle-import:SO14")
      (libsource (lib "eagle-import") (part "7408DS"))
    )
    (comp (ref "IC80")
      (value "74S08D")
      (footprint "eagle-import:SO14")
      (libsource (lib "eagle-import") (part "7408DS"))
    )
    (comp (ref "IC81")
      (value "74AC16374")
      (footprint "eagle-import:SSOP48DL")
      (libsource (lib "eagle-import") (part "74AC16374"))
    )
    (comp (ref "IC82")
      (value "74S08D")
      (footprint "eagle-import:SO14")
      (libsource (lib "eagle-import") (part "7408DS"))
    )
    (comp (ref "IC83")
      (value "74S08D")
      (footprint "eagle-import:SO14")
      (libsource (lib "eagle-import") (part "7408DS"))
    )
    (comp (ref "IC84")
      (value "74S08D")
      (footprint "eagle-import:SO14")
      (libsource (lib "eagle-import") (part "7408DS"))
    )
    (comp (ref "IC85")
      (value "74S08D")
      (footprint "eagle-import:SO14")
      (libsource (lib "eagle-import") (part "7408DS"))
    )
    (comp (ref "IC86")
      (value "74AC16374")
      (footprint "eagle-import:SSOP48DL")
      (libsource (lib "eagle-import") (part "74AC16374"))
    )
    (comp (ref "IC87")
      (value "74S08D")
      (footprint "eagle-import:SO14")
      (libsource (lib "eagle-import") (part "7408DS"))
    )
    (comp (ref "IC88")
      (value "74S08D")
      (footprint "eagle-import:SO14")
      (libsource (lib "eagle-import") (part "7408DS"))
    )
    (comp (ref "IC89")
      (value "74S08D")
      (footprint "eagle-import:SO14")
      (libsource (lib "eagle-import") (part "7408DS"))
    )
    (comp (ref "IC90")
      (value "74S08D")
      (footprint "eagle-import:SO14")
      (libsource (lib "eagle-import") (part "7408DS"))
    )
    (comp (ref "IC91")
      (value "74AC16374")
      (footprint "eagle-import:SSOP48DL")
      (libsource (lib "eagle-import") (part "74AC16374"))
    )
    (comp (ref "IC92")
      (value "74S08D")
      (footprint "eagle-import:SO14")
      (libsource (lib "eagle-import") (part "7408DS"))
    )
    (comp (ref "IC93")
      (value "74S08D")
      (footprint "eagle-import:SO14")
      (libsource (lib "eagle-import") (part "7408DS"))
    )
    (comp (ref "IC94")
      (value "74S08D")
      (footprint "eagle-import:SO14")
      (libsource (lib "eagle-import") (part "7408DS"))
    )
    (comp (ref "IC95")
      (value "74S08D")
      (footprint "eagle-import:SO14")
      (libsource (lib "eagle-import") (part "7408DS"))
    )
    (comp (ref "IC96")
      (value "74AC16374")
      (footprint "eagle-import:SSOP48DL")
      (libsource (lib "eagle-import") (part "74AC16374"))
    )
    (comp (ref "IC97")
      (value "74S08D")
      (footprint "eagle-import:SO14")
      (libsource (lib "eagle-import") (part "7408DS"))
    )
    (comp (ref "IC98")
      (value "74S08D")
      (footprint "eagle-import:SO14")
      (libsource (lib "eagle-import") (part "7408DS"))
    )
    (comp (ref "IC99")
      (value "74S08D")
      (footprint "eagle-import:SO14")
      (libsource (lib "eagle-import") (part "7408DS"))
    )
    (comp (ref "IC100")
      (value "74S08D")
      (footprint "eagle-import:SO14")
      (libsource (lib "eagle-import") (part "7408DS"))
    )
    (comp (ref "IC101")
      (value "74AC16374")
      (footprint "eagle-import:SSOP48DL")
      (libsource (lib "eagle-import") (part "74AC16374"))
    )
    (comp (ref "IC102")
      (value "74AC16374")
      (footprint "eagle-import:SSOP48DL")
      (libsource (lib "eagle-import") (part "74AC16374"))
    )
    (comp (ref "IC103")
      (value "74AC16374")
      (footprint "eagle-import:SSOP48DL")
      (libsource (lib "eagle-import") (part "74AC16374"))
    )
    (comp (ref "U$1")
      (value "ULN2804-SM")
      (footprint "eagle-import:SOP-18")
      (libsource (lib "eagle-import") (part "ULN2804-SM"))
    )
    (comp (ref "U$2")
      (value "ULN2804-SM")
      (footprint "eagle-import:SOP-18")
      (libsource (lib "eagle-import") (part "ULN2804-SM"))
    )
    (comp (ref "U$3")
      (value "ULN2804-SM")
      (footprint "eagle-import:SOP-18")
      (libsource (lib "eagle-import") (part "ULN2804-SM"))
    )
    (comp (ref "U$4")
      (value "ULN2804-SM")
      (footprint "eagle-import:SOP-18")
      (libsource (lib "eagle-import") (part "ULN2804-SM"))
    )
    (comp (ref "U$5")
      (value "ULN2804-SM")
      (footprint "eagle-import:SOP-18")
      (libsource (lib "eagle-import") (part "ULN2804-SM"))
    )
    (comp (ref "U$6")
      (value "ULN2804-SM")
      (footprint "eagle-import:SOP-18")
      (libsource (lib "eagle-import") (part "ULN2804-SM"))
    )
    (comp (ref "U$7")
      (value "ULN2804-SM")
      (footprint "eagle-import:SOP-18")
      (libsource (lib "eagle-import") (part "ULN2804-SM"))
    )
    (comp (ref "U$8")
      (value "ULN2804-SM")
      (footprint "eagle-import:SOP-18")
      (libsource (lib "eagle-import") (part "ULN2804-SM"))
    )
    (comp (ref "U$9")
      (value "ULN2804-SM")
      (footprint "eagle-import:SOP-18")
      (libsource (lib "eagle-import") (part "ULN2804-SM"))
    )
    (comp (ref "U$10")
      (value "ULN2804-SM")
      (footprint "eagle-import:SOP-18")
      (libsource (lib "eagle-import") (part "ULN2804-SM"))
    )
    (comp (ref "U$11")
      (value "ULN2804-SM")
      (footprint "eagle-import:SOP-18")
      (libsource (lib "eagle-import") (part "ULN2804-SM"))
    )
    (comp (ref "U$12")
      (value "ULN2804-SM")
      (footprint "eagle-import:SOP-18")
      (libsource (lib "eagle-import") (part "ULN2804-SM"))
    )
    (comp (ref "U$13")
      (value "ULN2804-SM")
      (footprint "eagle-import:SOP-18")
      (libsource (lib "eagle-import") (part "ULN2804-SM"))
    )
    (comp (ref "U$14")
      (value "ULN2804-SM")
      (footprint "eagle-import:SOP-18")
      (libsource (lib "eagle-import") (part "ULN2804-SM"))
    )
    (comp (ref "U$15")
      (value "ULN2804-SM")
      (footprint "eagle-import:SOP-18")
      (libsource (lib "eagle-import") (part "ULN2804-SM"))
    )
    (comp (ref "U$16")
      (value "ULN2804-SM")
      (footprint "eagle-import:SOP-18")
      (libsource (lib "eagle-import") (part "ULN2804-SM"))
    )
    (comp (ref "U$17")
      (value "ULN2804-SM")
      (footprint "eagle-import:SOP-18")
      (libsource (lib "eagle-import") (part "ULN2804-SM"))
    )
    (comp (ref "U$18")
      (value "ULN2804-SM")
      (footprint "eagle-import:SOP-18")
      (libsource (lib "eagle-import") (part "ULN2804-SM"))
    )
    (comp (ref "U$19")
      (value "ULN2804-SM")
      (footprint "eagle-import:SOP-18")
      (libsource (lib "eagle-import") (part "ULN2804-SM"))
    )
    (comp (ref "U$20")
      (value "ULN2804-SM")
      (footprint "eagle-import:SOP-18")
      (libsource (lib "eagle-import") (part "ULN2804-SM"))
    )
    (comp (ref "U$21")
      (value "ULN2804-SM")
      (footprint "eagle-import:SOP-18")
      (libsource (lib "eagle-import") (part "ULN2804-SM"))
    )
    (comp (ref "U$22")
      (value "ULN2804-SM")
      (footprint "eagle-import:SOP-18")
      (libsource (lib "eagle-import") (part "ULN2804-SM"))
    )
    (comp (ref "U$23")
      (value "ULN2804-SM")
      (footprint "eagle-import:SOP-18")
      (libsource (lib "eagle-import") (part "ULN2804-SM"))
    )
    (comp (ref "U$24")
      (value "ULN2804-SM")
      (footprint "eagle-import:SOP-18")
      (libsource (lib "eagle-import") (part "ULN2804-SM"))
    )
    (comp (ref "U$25")
      (value "ULN2804-SM")
      (footprint "eagle-import:SOP-18")
      (libsource (lib "eagle-import") (part "ULN2804-SM"))
    )
    (comp (ref "U$26")
      (value "ULN2804-SM")
      (footprint "eagle-import:SOP-18")
      (libsource (lib "eagle-import") (part "ULN2804-SM"))
    )
    (comp (ref "U$27")
      (value "ULN2804-SM")
      (footprint "eagle-import:SOP-18")
      (libsource (lib "eagle-import") (part "ULN2804-SM"))
    )
    (comp (ref "U$28")
      (value "ULN2804-SM")
      (footprint "eagle-import:SOP-18")
      (libsource (lib "eagle-import") (part "ULN2804-SM"))
    )
    (comp (ref "U$29")
      (value "ULN2804-SM")
      (footprint "eagle-import:SOP-18")
      (libsource (lib "eagle-import") (part "ULN2804-SM"))
    )
    (comp (ref "U$30")
      (value "ULN2804-SM")
      (footprint "eagle-import:SOP-18")
      (libsource (lib "eagle-import") (part "ULN2804-SM"))
    )
    (comp (ref "U$31")
      (value "ULN2804-SM")
      (footprint "eagle-import:SOP-18")
      (libsource (lib "eagle-import") (part "ULN2804-SM"))
    )
    (comp (ref "U$32")
      (value "ULN2804-SM")
      (footprint "eagle-import:SOP-18")
      (libsource (lib "eagle-import") (part "ULN2804-SM"))
    )
    (comp (ref "U$33")
      (value "ULN2804-SM")
      (footprint "eagle-import:SOP-18")
      (libsource (lib "eagle-import") (part "ULN2804-SM"))
    )
    (comp (ref "U$34")
      (value "ULN2804-SM")
      (footprint "eagle-import:SOP-18")
      (libsource (lib "eagle-import") (part "ULN2804-SM"))
    )
    (comp (ref "U$35")
      (value "ULN2804-SM")
      (footprint "eagle-import:SOP-18")
      (libsource (lib "eagle-import") (part "ULN2804-SM"))
    )
    (comp (ref "U$36")
      (value "ULN2804-SM")
      (footprint "eagle-import:SOP-18")
      (libsource (lib "eagle-import") (part "ULN2804-SM"))
    )
    (comp (ref "U$37")
      (value "ULN2804-SM")
      (footprint "eagle-import:SOP-18")
      (libsource (lib "eagle-import") (part "ULN2804-SM"))
    )
    (comp (ref "U$38")
      (value "ULN2804-SM")
      (footprint "eagle-import:SOP-18")
      (libsource (lib "eagle-import") (part "ULN2804-SM"))
    )
    (comp (ref "U$39")
      (value "ULN2804-SM")
      (footprint "eagle-import:SOP-18")
      (libsource (lib "eagle-import") (part "ULN2804-SM"))
    )
    (comp (ref "U$40")
      (value "ULN2804-SM")
      (footprint "eagle-import:SOP-18")
      (libsource (lib "eagle-import") (part "ULN2804-SM"))
    )
    (comp (ref "X1")
      (value "87758-3216")
      (footprint "eagle-import:87758-3216")
      (libsource (lib "eagle-import") (part "87758-3216"))
    )
    (comp (ref "X2")
      (value "87758-3216")
      (footprint "eagle-import:87758-3216")
      (libsource (lib "eagle-import") (part "87758-3216"))
    )
    (comp (ref "X3")
      (value "87758-3216")
      (footprint "eagle-import:87758-3216")
      (libsource (lib "eagle-import") (part "87758-3216"))
    )
    (comp (ref "X4")
      (value "87758-3216")
      (footprint "eagle-import:87758-3216")
      (libsource (lib "eagle-import") (part "87758-3216"))
    )
    (comp (ref "X5")
      (value "87758-3216")
      (footprint "eagle-import:87758-3216")
      (libsource (lib "eagle-import") (part "87758-3216"))
    )
    (comp (ref "X6")
      (value "87758-3216")
      (footprint "eagle-import:87758-3216")
      (libsource (lib "eagle-import") (part "87758-3216"))
    )
    (comp (ref "X7")
      (value "87758-3216")
      (footprint "eagle-import:87758-3216")
      (libsource (lib "eagle-import") (part "87758-3216"))
    )
    (comp (ref "X8")
      (value "87758-3216")
      (footprint "eagle-import:87758-3216")
      (libsource (lib "eagle-import") (part "87758-3216"))
    )
    (comp (ref "X9")
      (value "87758-3216")
      (footprint "eagle-import:87758-3216")
      (libsource (lib "eagle-import") (part "87758-3216"))
    )
    (comp (ref "X10")
      (value "87758-3216")
      (footprint "eagle-import:87758-3216")
      (libsource (lib "eagle-import") (part "87758-3216"))
    )
    (comp (ref "X11")
      (value "87758-1416")
      (footprint "eagle-import:87758-1416")
      (fields (field (name "MF") "MOLEX"))
      (libsource (lib "eagle-import") (part "87758-1416"))
    )
  )
  (nets
    (net (code "1") (name "GND") (class "Default")
      (node (ref "IC1") (pin "1") (pinfunction "1OE_1") (pintype "input"))
      (node (ref "IC1") (pin "24") (pinfunction "2OE_24") (pintype "input"))
      (node (ref "IC101") (pin "1") (pinfunction "1OE_1") (pintype "input"))
      (node (ref "IC101") (pin "24") (pinfunction "2OE_24") (pintype "input"))
      (node (ref "IC102") (pin "1") (pinfunction "1OE_1") (pintype "input"))
      (node (ref "IC102") (pin "24") (pinfunction "2OE_24") (pintype "input"))
      (node (ref "IC103") (pin "1") (pinfunction "1OE_1") (pintype "input"))
      (node (ref "IC103") (pin "24") (pinfunction "2OE_24") (pintype "input"))
      (node (ref "IC16") (pin "1") (pinfunction "1OE_1") (pintype "input"))
      (node (ref "IC16") (pin "24") (pinfunction "2OE_24") (pintype "input"))
      (node (ref "IC21") (pin "1") (pinfunction "1OE_1") (pintype "input"))
      (node (ref "IC21") (pin "24") (pinfunction "2OE_24") (pintype "input"))
      (node (ref "IC26") (pin "1") (pinfunction "1OE_1") (pintype "input"))
      (node (ref "IC26") (pin "24") (pinfunction "2OE_24") (pintype "input"))
      (node (ref "IC3") (pin "1") (pinfunction "1OE_1") (pintype "input"))
      (node (ref "IC3") (pin "24") (pinfunction "2OE_24") (pintype "input"))
      (node (ref "IC31") (pin "1") (pinfunction "1OE_1") (pintype "input"))
      (node (ref "IC31") (pin "24") (pinfunction "2OE_24") (pintype "input"))
      (node (ref "IC36") (pin "1") (pinfunction "1OE_1") (pintype "input"))
      (node (ref "IC36") (pin "24") (pinfunction "2OE_24") (pintype "input"))
      (node (ref "IC41") (pin "1") (pinfunction "1OE_1") (pintype "input"))
      (node (ref "IC41") (pin "24") (pinfunction "2OE_24") (pintype "input"))
      (node (ref "IC46") (pin "1") (pinfunction "1OE_1") (pintype "input"))
      (node (ref "IC46") (pin "24") (pinfunction "2OE_24") (pintype "input"))
      (node (ref "IC51") (pin "1") (pinfunction "1OE_1") (pintype "input"))
      (node (ref "IC51") (pin "24") (pinfunction "2OE_24") (pintype "input"))
      (node (ref "IC56") (pin "1") (pinfunction "1OE_1") (pintype "input"))
      (node (ref "IC56") (pin "24") (pinfunction "2OE_24") (pintype "input"))
      (node (ref "IC61") (pin "1") (pinfunction "1OE_1") (pintype "input"))
      (node (ref "IC61") (pin "24") (pinfunction "2OE_24") (pintype "input"))
      (node (ref "IC66") (pin "1") (pinfunction "1OE_1") (pintype "input"))
      (node (ref "IC66") (pin "24") (pinfunction "2OE_24") (pintype "input"))
      (node (ref "IC71") (pin "1") (pinfunction "1OE_1") (pintype "input"))
      (node (ref "IC71") (pin "24") (pinfunction "2OE_24") (pintype "input"))
      (node (ref "IC76") (pin "1") (pinfunction "1OE_1") (pintype "input"))
      (node (ref "IC76") (pin "24") (pinfunction "2OE_24") (pintype "input"))
      (node (ref "IC8") (pin "1") (pinfunction "1OE_1") (pintype "input"))
      (node (ref "IC8") (pin "24") (pinfunction "2OE_24") (pintype "input"))
      (node (ref "IC81") (pin "1") (pinfunction "1OE_1") (pintype "input"))
      (node (ref "IC81") (pin "24") (pinfunction "2OE_24") (pintype "input"))
      (node (ref "IC86") (pin "1") (pinfunction "1OE_1") (pintype "input"))
      (node (ref "IC86") (pin "24") (pinfunction "2OE_24") (pintype "input"))
      (node (ref "IC91") (pin "1") (pinfunction "1OE_1") (pintype "input"))
      (node (ref "IC91") (pin "24") (pinfunction "2OE_24") (pintype "input"))
      (node (ref "IC96") (pin "1") (pinfunction "1OE_1") (pintype "input"))
      (node (ref "IC96") (pin "24") (pinfunction "2OE_24") (pintype "input"))
      (node (ref "U$1") (pin "9") (pinfunction "GND_9") (pintype "power_in"))
      (node (ref "U$10") (pin "9") (pinfunction "GND_9") (pintype "power_in"))
      (node (ref "U$11") (pin "9") (pinfunction "GND_9") (pintype "power_in"))
      (node (ref "U$12") (pin "9") (pinfunction "GND_9") (pintype "power_in"))
      (node (ref "U$13") (pin "9") (pinfunction "GND_9") (pintype "power_in"))
      (node (ref "U$14") (pin "9") (pinfunction "GND_9") (pintype "power_in"))
      (node (ref "U$15") (pin "9") (pinfunction "GND_9") (pintype "power_in"))
      (node (ref "U$16") (pin "9") (pinfunction "GND_9") (pintype "power_in"))
      (node (ref "U$17") (pin "9") (pinfunction "GND_9") (pintype "power_in"))
      (node (ref "U$18") (pin "9") (pinfunction "GND_9") (pintype "power_in"))
      (node (ref "U$19") (pin "9") (pinfunction "GND_9") (pintype "power_in"))
      (node (ref "U$2") (pin "9") (pinfunction "GND_9") (pintype "power_in"))
      (node (ref "U$20") (pin "9") (pinfunction "GND_9") (pintype "power_in"))
      (node (ref "U$21") (pin "9") (pinfunction "GND_9") (pintype "power_in"))
      (node (ref "U$22") (pin "9") (pinfunction "GND_9") (pintype "power_in"))
      (node (ref "U$23") (pin "9") (pinfunction "GND_9") (pintype "power_in"))
      (node (ref "U$24") (pin "9") (pinfunction "GND_9") (pintype "power_in"))
      (node (ref "U$25") (pin "9") (pinfunction "GND_9") (pintype "power_in"))
      (node (ref "U$26") (pin "9") (pinfunction "GND_9") (pintype "power_in"))
      (node (ref "U$27") (pin "9") (pinfunction "GND_9") (pintype "power_in"))
      (node (ref "U$28") (pin "9") (pinfunction "GND_9") (pintype "power_in"))
      (node (ref "U$29") (pin "9") (pinfunction "GND_9") (pintype "power_in"))
      (node (ref "U$3") (pin "9") (pinfunction "GND_9") (pintype "power_in"))
      (node (ref "U$30") (pin "9") (pinfunction "GND_9") (pintype "power_in"))
      (node (ref "U$31") (pin "9") (pinfunction "GND_9") (pintype "power_in"))
      (node (ref "U$32") (pin "9") (pinfunction "GND_9") (pintype "power_in"))
      (node (ref "U$33") (pin "9") (pinfunction "GND_9") (pintype "power_in"))
      (node (ref "U$34") (pin "9") (pinfunction "GND_9") (pintype "power_in"))
      (node (ref "U$35") (pin "9") (pinfunction "GND_9") (pintype "power_in"))
      (node (ref "U$36") (pin "9") (pinfunction "GND_9") (pintype "power_in"))
      (node (ref "U$37") (pin "9") (pinfunction "GND_9") (pintype "power_in"))
      (node (ref "U$38") (pin "9") (pinfunction "GND_9") (pintype "power_in"))
      (node (ref "U$39") (pin "9") (pinfunction "GND_9") (pintype "power_in"))
      (node (ref "U$4") (pin "9") (pinfunction "GND_9") (pintype "power_in"))
      (node (ref "U$40") (pin "9") (pinfunction "GND_9") (pintype "power_in"))
      (node (ref "U$5") (pin "9") (pinfunction "GND_9") (pintype "power_in"))
      (node (ref "U$6") (pin "9") (pinfunction "GND_9") (pintype "power_in"))
      (node (ref "U$7") (pin "9") (pinfunction "GND_9") (pintype "power_in"))
      (node (ref "U$8") (pin "9") (pinfunction "GND_9") (pintype "power_in"))
      (node (ref "U$9") (pin "9") (pinfunction "GND_9") (pintype "power_in"))
      (node (ref "X11") (pin "9") (pinfunction "S_9") (pintype "passive"))
    )
    (net (code "2") (name "Net-(IC1A-1D2)") (class "Default")
      (node (ref "IC1") (pin "2") (pinfunction "1Q1_2") (pintype "tri_state"))
      (node (ref "IC1") (pin "46") (pinfunction "1D2_46") (pintype "input"))
      (node (ref "IC2") (pin "1") (pinfunction "I0_1") (pintype "input"))
    )
    (net (code "3") (name "Net-(IC1A-1D3)") (class "Default")
      (node (ref "IC1") (pin "3") (pinfunction "1Q2_3") (pintype "tri_state"))
      (node (ref "IC1") (pin "44") (pinfunction "1D3_44") (pintype "input"))
      (node (ref "IC2") (pin "4") (pinfunction "I0_4") (pintype "input"))
    )
    (net (code "4") (name "Net-(IC1A-1D4)") (class "Default")
      (node (ref "IC1") (pin "43") (pinfunction "1D4_43") (pintype "input"))
      (node (ref "IC1") (pin "5") (pinfunction "1Q3_5") (pintype "tri_state"))
      (node (ref "IC2") (pin "9") (pinfunction "I0_9") (pintype "input"))
    )
    (net (code "5") (name "Net-(IC1A-1D5)") (class "Default")
      (node (ref "IC1") (pin "41") (pinfunction "1D5_41") (pintype "input"))
      (node (ref "IC1") (pin "6") (pinfunction "1Q4_6") (pintype "tri_state"))
      (node (ref "IC2") (pin "12") (pinfunction "I0_12") (pintype "input"))
    )
    (net (code "6") (name "Net-(IC1A-1D6)") (class "Default")
      (node (ref "IC1") (pin "40") (pinfunction "1D6_40") (pintype "input"))
      (node (ref "IC1") (pin "8") (pinfunction "1Q5_8") (pintype "tri_state"))
      (node (ref "IC4") (pin "1") (pinfunction "I0_1") (pintype "input"))
    )
    (net (code "7") (name "Net-(IC1A-1D7)") (class "Default")
      (node (ref "IC1") (pin "38") (pinfunction "1D7_38") (pintype "input"))
      (node (ref "IC1") (pin "9") (pinfunction "1Q6_9") (pintype "tri_state"))
      (node (ref "IC4") (pin "4") (pinfunction "I0_4") (pintype "input"))
    )
    (net (code "8") (name "Net-(IC1A-1D8)") (class "Default")
      (node (ref "IC1") (pin "11") (pinfunction "1Q7_11") (pintype "tri_state"))
      (node (ref "IC1") (pin "37") (pinfunction "1D8_37") (pintype "input"))
      (node (ref "IC4") (pin "9") (pinfunction "I0_9") (pintype "input"))
    )
    (net (code "9") (name "Net-(IC1A-1Q8)") (class "Default")
      (node (ref "IC1") (pin "12") (pinfunction "1Q8_12") (pintype "tri_state"))
      (node (ref "IC1") (pin "36") (pinfunction "2D1_36") (pintype "input"))
      (node (ref "IC4") (pin "12") (pinfunction "I0_12") (pintype "input"))
    )
    (net (code "10") (name "Net-(IC1A-2D2)") (class "Default")
      (node (ref "IC1") (pin "13") (pinfunction "2Q1_13") (pintype "tri_state"))
      (node (ref "IC1") (pin "35") (pinfunction "2D2_35") (pintype "input"))
      (node (ref "IC5") (pin "1") (pinfunction "I0_1") (pintype "input"))
    )
    (net (code "11") (name "Net-(IC1A-2D3)") (class "Default")
      (node (ref "IC1") (pin "14") (pinfunction "2Q2_14") (pintype "tri_state"))
      (node (ref "IC1") (pin "33") (pinfunction "2D3_33") (pintype "input"))
      (node (ref "IC5") (pin "4") (pinfunction "I0_4") (pintype "input"))
    )
    (net (code "12") (name "Net-(IC1A-2D4)") (class "Default")
      (node (ref "IC1") (pin "16") (pinfunction "2Q3_16") (pintype "tri_state"))
      (node (ref "IC1") (pin "32") (pinfunction "2D4_32") (pintype "input"))
      (node (ref "IC5") (pin "9") (pinfunction "I0_9") (pintype "input"))
    )
    (net (code "13") (name "Net-(IC1A-2D5)") (class "Default")
      (node (ref "IC1") (pin "17") (pinfunction "2Q4_17") (pintype "tri_state"))
      (node (ref "IC1") (pin "30") (pinfunction "2D5_30") (pintype "input"))
      (node (ref "IC5") (pin "12") (pinfunction "I0_12") (pintype "input"))
    )
    (net (code "14") (name "Net-(IC1A-2D6)") (class "Default")
      (node (ref "IC1") (pin "19") (pinfunction "2Q5_19") (pintype "tri_state"))
      (node (ref "IC1") (pin "29") (pinfunction "2D6_29") (pintype "input"))
      (node (ref "IC6") (pin "1") (pinfunction "I0_1") (pintype "input"))
    )
    (net (code "15") (name "Net-(IC1A-2D7)") (class "Default")
      (node (ref "IC1") (pin "20") (pinfunction "2Q6_20") (pintype "tri_state"))
      (node (ref "IC1") (pin "27") (pinfunction "2D7_27") (pintype "input"))
      (node (ref "IC6") (pin "4") (pinfunction "I0_4") (pintype "input"))
    )
    (net (code "16") (name "Net-(IC1A-2D8)") (class "Default")
      (node (ref "IC1") (pin "22") (pinfunction "2Q7_22") (pintype "tri_state"))
      (node (ref "IC1") (pin "26") (pinfunction "2D8_26") (pintype "input"))
      (node (ref "IC6") (pin "9") (pinfunction "I0_9") (pintype "input"))
    )
    (net (code "17") (name "Net-(IC1A-2Q8)") (class "Default")
      (node (ref "IC1") (pin "23") (pinfunction "2Q8_23") (pintype "tri_state"))
      (node (ref "IC6") (pin "12") (pinfunction "I0_12") (pintype "input"))
      (node (ref "IC8") (pin "47") (pinfunction "1D1_47") (pintype "input"))
    )
    (net (code "18") (name "Net-(IC2A-O)") (class "Default")
      (node (ref "IC2") (pin "3") (pinfunction "O_3") (pintype "output"))
      (node (ref "U$1") (pin "1") (pinfunction "I1_1") (pintype "input"))
    )
    (net (code "19") (name "Net-(IC2B-O)") (class "Default")
      (node (ref "IC2") (pin "6") (pinfunction "O_6") (pintype "output"))
      (node (ref "U$1") (pin "2") (pinfunction "I2_2") (pintype "input"))
    )
    (net (code "20") (name "Net-(IC2C-O)") (class "Default")
      (node (ref "IC2") (pin "8") (pinfunction "O_8") (pintype "output"))
      (node (ref "U$1") (pin "3") (pinfunction "I3_3") (pintype "input"))
    )
    (net (code "21") (name "Net-(IC2D-O)") (class "Default")
      (node (ref "IC2") (pin "11") (pinfunction "O_11") (pintype "output"))
      (node (ref "U$1") (pin "4") (pinfunction "I4_4") (pintype "input"))
    )
    (net (code "22") (name "Net-(IC3A-1D2)") (class "Default")
      (node (ref "IC3") (pin "2") (pinfunction "1Q1_2") (pintype "tri_state"))
      (node (ref "IC3") (pin "46") (pinfunction "1D2_46") (pintype "input"))
      (node (ref "IC7") (pin "1") (pinfunction "I0_1") (pintype "input"))
    )
    (net (code "23") (name "Net-(IC3A-1D3)") (class "Default")
      (node (ref "IC3") (pin "3") (pinfunction "1Q2_3") (pintype "tri_state"))
      (node (ref "IC3") (pin "44") (pinfunction "1D3_44") (pintype "input"))
      (node (ref "IC7") (pin "4") (pinfunction "I0_4") (pintype "input"))
    )
    (net (code "24") (name "Net-(IC3A-1D4)") (class "Default")
      (node (ref "IC3") (pin "43") (pinfunction "1D4_43") (pintype "input"))
      (node (ref "IC3") (pin "5") (pinfunction "1Q3_5") (pintype "tri_state"))
      (node (ref "IC7") (pin "9") (pinfunction "I0_9") (pintype "input"))
    )
    (net (code "25") (name "Net-(IC3A-1D5)") (class "Default")
      (node (ref "IC3") (pin "41") (pinfunction "1D5_41") (pintype "input"))
      (node (ref "IC3") (pin "6") (pinfunction "1Q4_6") (pintype "tri_state"))
      (node (ref "IC7") (pin "12") (pinfunction "I0_12") (pintype "input"))
    )
    (net (code "26") (name "Net-(IC4A-O)") (class "Default")
      (node (ref "IC4") (pin "3") (pinfunction "O_3") (pintype "output"))
      (node (ref "U$1") (pin "5") (pinfunction "I5_5") (pintype "input"))
    )
    (net (code "27") (name "Net-(IC4B-O)") (class "Default")
      (node (ref "IC4") (pin "6") (pinfunction "O_6") (pintype "output"))
      (node (ref "U$1") (pin "6") (pinfunction "I6_6") (pintype "input"))
    )
    (net (code "28") (name "Net-(IC4C-O)") (class "Default")
      (node (ref "IC4") (pin "8") (pinfunction "O_8") (pintype "output"))
      (node (ref "U$1") (pin "7") (pinfunction "I7_7") (pintype "input"))
    )
    (net (code "29") (name "Net-(IC4D-O)") (class "Default")
      (node (ref "IC4") (pin "11") (pinfunction "O_11") (pintype "output"))
      (node (ref "U$1") (pin "8") (pinfunction "I8_8") (pintype "input"))
    )
    (net (code "30") (name "Net-(IC5A-O)") (class "Default")
      (node (ref "IC5") (pin "3") (pinfunction "O_3") (pintype "output"))
      (node (ref "U$2") (pin "1") (pinfunction "I1_1") (pintype "input"))
    )
    (net (code "31") (name "Net-(IC5B-O)") (class "Default")
      (node (ref "IC5") (pin "6") (pinfunction "O_6") (pintype "output"))
      (node (ref "U$2") (pin "2") (pinfunction "I2_2") (pintype "input"))
    )
    (net (code "32") (name "Net-(IC5C-O)") (class "Default")
      (node (ref "IC5") (pin "8") (pinfunction "O_8") (pintype "output"))
      (node (ref "U$2") (pin "3") (pinfunction "I3_3") (pintype "input"))
    )
    (net (code "33") (name "Net-(IC5D-O)") (class "Default")
      (node (ref "IC5") (pin "11") (pinfunction "O_11") (pintype "output"))
      (node (ref "U$2") (pin "4") (pinfunction "I4_4") (pintype "input"))
    )
    (net (code "34") (name "Net-(IC6A-O)") (class "Default")
      (node (ref "IC6") (pin "3") (pinfunction "O_3") (pintype "output"))
      (node (ref "U$2") (pin "5") (pinfunction "I5_5") (pintype "input"))
    )
    (net (code "35") (name "Net-(IC6B-O)") (class "Default")
      (node (ref "IC6") (pin "6") (pinfunction "O_6") (pintype "output"))
      (node (ref "U$2") (pin "6") (pinfunction "I6_6") (pintype "input"))
    )
    (net (code "36") (name "Net-(IC6C-O)") (class "Default")
      (node (ref "IC6") (pin "8") (pinfunction "O_8") (pintype "output"))
      (node (ref "U$2") (pin "7") (pinfunction "I7_7") (pintype "input"))
    )
    (net (code "37") (name "Net-(IC6D-O)") (class "Default")
      (node (ref "IC6") (pin "11") (pinfunction "O_11") (pintype "output"))
      (node (ref "U$2") (pin "8") (pinfunction "I8_8") (pintype "input"))
    )
    (net (code "38") (name "Net-(IC7A-O)") (class "Default")
      (node (ref "IC7") (pin "3") (pinfunction "O_3") (pintype "output"))
      (node (ref "U$5") (pin "1") (pinfunction "I1_1") (pintype "input"))
    )
    (net (code "39") (name "Net-(IC7B-O)") (class "Default")
      (node (ref "IC7") (pin "6") (pinfunction "O_6") (pintype "output"))
      (node (ref "U$5") (pin "2") (pinfunction "I2_2") (pintype "input"))
    )
    (net (code "40") (name "Net-(IC7C-O)") (class "Default")
      (node (ref "IC7") (pin "8") (pinfunction "O_8") (pintype "output"))
      (node (ref "U$5") (pin "3") (pinfunction "I3_3") (pintype "input"))
    )
    (net (code "41") (name "Net-(IC7D-O)") (class "Default")
      (node (ref "IC7") (pin "11") (pinfunction "O_11") (pintype "output"))
      (node (ref "U$5") (pin "4") (pinfunction "I4_4") (pintype "input"))
    )
    (net (code "42") (name "Net-(IC8A-1D2)") (class "Default")
      (node (ref "IC8") (pin "2") (pinfunction "1Q1_2") (pintype "tri_state"))
      (node (ref "IC8") (pin "46") (pinfunction "1D2_46") (pintype "input"))
      (node (ref "IC9") (pin "1") (pinfunction "I0_1") (pintype "input"))
    )
    (net (code "43") (name "Net-(IC8A-1D3)") (class "Default")
      (node (ref "IC8") (pin "3") (pinfunction "1Q2_3") (pintype "tri_state"))
      (node (ref "IC8") (pin "44") (pinfunction "1D3_44") (pintype "input"))
      (node (ref "IC9") (pin "4") (pinfunction "I0_4") (pintype "input"))
    )
    (net (code "44") (name "Net-(IC8A-1D4)") (class "Default")
      (node (ref "IC8") (pin "43") (pinfunction "1D4_43") (pintype "input"))
      (node (ref "IC8") (pin "5") (pinfunction "1Q3_5") (pintype "tri_state"))
      (node (ref "IC9") (pin "9") (pinfunction "I0_9") (pintype "input"))
    )
    (net (code "45") (name "Net-(IC8A-1D5)") (class "Default")
      (node (ref "IC8") (pin "41") (pinfunction "1D5_41") (pintype "input"))
      (node (ref "IC8") (pin "6") (pinfunction "1Q4_6") (pintype "tri_state"))
      (node (ref "IC9") (pin "12") (pinfunction "I0_12") (pintype "input"))
    )
    (net (code "46") (name "Net-(IC9A-O)") (class "Default")
      (node (ref "IC9") (pin "3") (pinfunction "O_3") (pintype "output"))
      (node (ref "U$3") (pin "1") (pinfunction "I1_1") (pintype "input"))
    )
    (net (code "47") (name "Net-(IC9B-O)") (class "Default")
      (node (ref "IC9") (pin "6") (pinfunction "O_6") (pintype "output"))
      (node (ref "U$3") (pin "2") (pinfunction "I2_2") (pintype "input"))
    )
    (net (code "48") (name "Net-(IC9C-O)") (class "Default")
      (node (ref "IC9") (pin "8") (pinfunction "O_8") (pintype "output"))
      (node (ref "U$3") (pin "3") (pinfunction "I3_3") (pintype "input"))
    )
    (net (code "49") (name "Net-(IC9D-O)") (class "Default")
      (node (ref "IC9") (pin "11") (pinfunction "O_11") (pintype "output"))
      (node (ref "U$3") (pin "4") (pinfunction "I4_4") (pintype "input"))
    )
    (net (code "50") (name "Net-(IC10A-I0)") (class "Default")
      (node (ref "IC10") (pin "1") (pinfunction "I0_1") (pintype "input"))
      (node (ref "IC3") (pin "40") (pinfunction "1D6_40") (pintype "input"))
      (node (ref "IC3") (pin "8") (pinfunction "1Q5_8") (pintype "tri_state"))
    )
    (net (code "51") (name "Net-(IC10A-O)") (class "Default")
      (node (ref "IC10") (pin "3") (pinfunction "O_3") (pintype "output"))
      (node (ref "U$5") (pin "5") (pinfunction "I5_5") (pintype "input"))
    )
    (net (code "52") (name "Net-(IC10B-I0)") (class "Default")
      (node (ref "IC10") (pin "4") (pinfunction "I0_4") (pintype "input"))
      (node (ref "IC3") (pin "38") (pinfunction "1D7_38") (pintype "input"))
      (node (ref "IC3") (pin "9") (pinfunction "1Q6_9") (pintype "tri_state"))
    )
    (net (code "53") (name "Net-(IC10B-O)") (class "Default")
      (node (ref "IC10") (pin "6") (pinfunction "O_6") (pintype "output"))
      (node (ref "U$5") (pin "6") (pinfunction "I6_6") (pintype "input"))
    )
    (net (code "54") (name "Net-(IC10C-I0)") (class "Default")
      (node (ref "IC10") (pin "9") (pinfunction "I0_9") (pintype "input"))
      (node (ref "IC3") (pin "11") (pinfunction "1Q7_11") (pintype "tri_state"))
      (node (ref "IC3") (pin "37") (pinfunction "1D8_37") (pintype "input"))
    )
    (net (code "55") (name "Net-(IC10C-O)") (class "Default")
      (node (ref "IC10") (pin "8") (pinfunction "O_8") (pintype "output"))
      (node (ref "U$5") (pin "7") (pinfunction "I7_7") (pintype "input"))
    )
    (net (code "56") (name "Net-(IC10D-I0)") (class "Default")
      (node (ref "IC10") (pin "12") (pinfunction "I0_12") (pintype "input"))
      (node (ref "IC3") (pin "12") (pinfunction "1Q8_12") (pintype "tri_state"))
      (node (ref "IC3") (pin "36") (pinfunction "2D1_36") (pintype "input"))
    )
    (net (code "57") (name "Net-(IC10D-O)") (class "Default")
      (node (ref "IC10") (pin "11") (pinfunction "O_11") (pintype "output"))
      (node (ref "U$5") (pin "8") (pinfunction "I8_8") (pintype "input"))
    )
    (net (code "58") (name "Net-(IC11A-I0)") (class "Default")
      (node (ref "IC11") (pin "1") (pinfunction "I0_1") (pintype "input"))
      (node (ref "IC8") (pin "40") (pinfunction "1D6_40") (pintype "input"))
      (node (ref "IC8") (pin "8") (pinfunction "1Q5_8") (pintype "tri_state"))
    )
    (net (code "59") (name "Net-(IC11A-O)") (class "Default")
      (node (ref "IC11") (pin "3") (pinfunction "O_3") (pintype "output"))
      (node (ref "U$3") (pin "5") (pinfunction "I5_5") (pintype "input"))
    )
    (net (code "60") (name "Net-(IC11B-I0)") (class "Default")
      (node (ref "IC11") (pin "4") (pinfunction "I0_4") (pintype "input"))
      (node (ref "IC8") (pin "38") (pinfunction "1D7_38") (pintype "input"))
      (node (ref "IC8") (pin "9") (pinfunction "1Q6_9") (pintype "tri_state"))
    )
    (net (code "61") (name "Net-(IC11B-O)") (class "Default")
      (node (ref "IC11") (pin "6") (pinfunction "O_6") (pintype "output"))
      (node (ref "U$3") (pin "6") (pinfunction "I6_6") (pintype "input"))
    )
    (net (code "62") (name "Net-(IC11C-I0)") (class "Default")
      (node (ref "IC11") (pin "9") (pinfunction "I0_9") (pintype "input"))
      (node (ref "IC8") (pin "11") (pinfunction "1Q7_11") (pintype "tri_state"))
      (node (ref "IC8") (pin "37") (pinfunction "1D8_37") (pintype "input"))
    )
    (net (code "63") (name "Net-(IC11C-O)") (class "Default")
      (node (ref "IC11") (pin "8") (pinfunction "O_8") (pintype "output"))
      (node (ref "U$3") (pin "7") (pinfunction "I7_7") (pintype "input"))
    )
    (net (code "64") (name "Net-(IC11D-I0)") (class "Default")
      (node (ref "IC11") (pin "12") (pinfunction "I0_12") (pintype "input"))
      (node (ref "IC8") (pin "12") (pinfunction "1Q8_12") (pintype "tri_state"))
      (node (ref "IC8") (pin "36") (pinfunction "2D1_36") (pintype "input"))
    )
    (net (code "65") (name "Net-(IC11D-O)") (class "Default")
      (node (ref "IC11") (pin "11") (pinfunction "O_11") (pintype "output"))
      (node (ref "U$3") (pin "8") (pinfunction "I8_8") (pintype "input"))
    )
    (net (code "66") (name "Net-(IC12A-I0)") (class "Default")
      (node (ref "IC12") (pin "1") (pinfunction "I0_1") (pintype "input"))
      (node (ref "IC8") (pin "13") (pinfunction "2Q1_13") (pintype "tri_state"))
      (node (ref "IC8") (pin "35") (pinfunction "2D2_35") (pintype "input"))
    )
    (net (code "67") (name "Net-(IC12A-O)") (class "Default")
      (node (ref "IC12") (pin "3") (pinfunction "O_3") (pintype "output"))
      (node (ref "U$4") (pin "1") (pinfunction "I1_1") (pintype "input"))
    )
    (net (code "68") (name "Net-(IC12B-I0)") (class "Default")
      (node (ref "IC12") (pin "4") (pinfunction "I0_4") (pintype "input"))
      (node (ref "IC8") (pin "14") (pinfunction "2Q2_14") (pintype "tri_state"))
      (node (ref "IC8") (pin "33") (pinfunction "2D3_33") (pintype "input"))
    )
    (net (code "69") (name "Net-(IC12B-O)") (class "Default")
      (node (ref "IC12") (pin "6") (pinfunction "O_6") (pintype "output"))
      (node (ref "U$4") (pin "2") (pinfunction "I2_2") (pintype "input"))
    )
    (net (code "70") (name "Net-(IC12C-I0)") (class "Default")
      (node (ref "IC12") (pin "9") (pinfunction "I0_9") (pintype "input"))
      (node (ref "IC8") (pin "16") (pinfunction "2Q3_16") (pintype "tri_state"))
      (node (ref "IC8") (pin "32") (pinfunction "2D4_32") (pintype "input"))
    )
    (net (code "71") (name "Net-(IC12C-O)") (class "Default")
      (node (ref "IC12") (pin "8") (pinfunction "O_8") (pintype "output"))
      (node (ref "U$4") (pin "3") (pinfunction "I3_3") (pintype "input"))
    )
    (net (code "72") (name "Net-(IC12D-I0)") (class "Default")
      (node (ref "IC12") (pin "12") (pinfunction "I0_12") (pintype "input"))
      (node (ref "IC8") (pin "17") (pinfunction "2Q4_17") (pintype "tri_state"))
      (node (ref "IC8") (pin "30") (pinfunction "2D5_30") (pintype "input"))
    )
    (net (code "73") (name "Net-(IC12D-O)") (class "Default")
      (node (ref "IC12") (pin "11") (pinfunction "O_11") (pintype "output"))
      (node (ref "U$4") (pin "4") (pinfunction "I4_4") (pintype "input"))
    )
    (net (code "74") (name "Net-(IC13A-I0)") (class "Default")
      (node (ref "IC13") (pin "1") (pinfunction "I0_1") (pintype "input"))
      (node (ref "IC8") (pin "19") (pinfunction "2Q5_19") (pintype "tri_state"))
      (node (ref "IC8") (pin "29") (pinfunction "2D6_29") (pintype "input"))
    )
    (net (code "75") (name "Net-(IC13A-O)") (class "Default")
      (node (ref "IC13") (pin "3") (pinfunction "O_3") (pintype "output"))
      (node (ref "U$4") (pin "5") (pinfunction "I5_5") (pintype "input"))
    )
    (net (code "76") (name "Net-(IC13B-I0)") (class "Default")
      (node (ref "IC13") (pin "4") (pinfunction "I0_4") (pintype "input"))
      (node (ref "IC8") (pin "20") (pinfunction "2Q6_20") (pintype "tri_state"))
      (node (ref "IC8") (pin "27") (pinfunction "2D7_27") (pintype "input"))
    )
    (net (code "77") (name "Net-(IC13B-O)") (class "Default")
      (node (ref "IC13") (pin "6") (pinfunction "O_6") (pintype "output"))
      (node (ref "U$4") (pin "6") (pinfunction "I6_6") (pintype "input"))
    )
    (net (code "78") (name "Net-(IC13C-I0)") (class "Default")
      (node (ref "IC13") (pin "9") (pinfunction "I0_9") (pintype "input"))
      (node (ref "IC8") (pin "22") (pinfunction "2Q7_22") (pintype "tri_state"))
      (node (ref "IC8") (pin "26") (pinfunction "2D8_26") (pintype "input"))
    )
    (net (code "79") (name "Net-(IC13C-O)") (class "Default")
      (node (ref "IC13") (pin "8") (pinfunction "O_8") (pintype "output"))
      (node (ref "U$4") (pin "7") (pinfunction "I7_7") (pintype "input"))
    )
    (net (code "80") (name "Net-(IC13D-I0)") (class "Default")
      (node (ref "IC13") (pin "12") (pinfunction "I0_12") (pintype "input"))
      (node (ref "IC51") (pin "47") (pinfunction "1D1_47") (pintype "input"))
      (node (ref "IC8") (pin "23") (pinfunction "2Q8_23") (pintype "tri_state"))
    )
    (net (code "81") (name "Net-(IC13D-O)") (class "Default")
      (node (ref "IC13") (pin "11") (pinfunction "O_11") (pintype "output"))
      (node (ref "U$4") (pin "8") (pinfunction "I8_8") (pintype "input"))
    )
    (net (code "82") (name "Net-(IC14A-I0)") (class "Default")
      (node (ref "IC14") (pin "1") (pinfunction "I0_1") (pintype "input"))
      (node (ref "IC3") (pin "13") (pinfunction "2Q1_13") (pintype "tri_state"))
      (node (ref "IC3") (pin "35") (pinfunction "2D2_35") (pintype "input"))
    )
    (net (code "83") (name "Net-(IC14A-O)") (class "Default")
      (node (ref "IC14") (pin "3") (pinfunction "O_3") (pintype "output"))
      (node (ref "U$6") (pin "1") (pinfunction "I1_1") (pintype "input"))
    )
    (net (code "84") (name "Net-(IC14B-I0)") (class "Default")
      (node (ref "IC14") (pin "4") (pinfunction "I0_4") (pintype "input"))
      (node (ref "IC3") (pin "14") (pinfunction "2Q2_14") (pintype "tri_state"))
      (node (ref "IC3") (pin "33") (pinfunction "2D3_33") (pintype "input"))
    )
    (net (code "85") (name "Net-(IC14B-O)") (class "Default")
      (node (ref "IC14") (pin "6") (pinfunction "O_6") (pintype "output"))
      (node (ref "U$6") (pin "2") (pinfunction "I2_2") (pintype "input"))
    )
    (net (code "86") (name "Net-(IC14C-I0)") (class "Default")
      (node (ref "IC14") (pin "9") (pinfunction "I0_9") (pintype "input"))
      (node (ref "IC3") (pin "16") (pinfunction "2Q3_16") (pintype "tri_state"))
      (node (ref "IC3") (pin "32") (pinfunction "2D4_32") (pintype "input"))
    )
    (net (code "87") (name "Net-(IC14C-O)") (class "Default")
      (node (ref "IC14") (pin "8") (pinfunction "O_8") (pintype "output"))
      (node (ref "U$6") (pin "3") (pinfunction "I3_3") (pintype "input"))
    )
    (net (code "88") (name "Net-(IC14D-I0)") (class "Default")
      (node (ref "IC14") (pin "12") (pinfunction "I0_12") (pintype "input"))
      (node (ref "IC3") (pin "17") (pinfunction "2Q4_17") (pintype "tri_state"))
      (node (ref "IC3") (pin "30") (pinfunction "2D5_30") (pintype "input"))
    )
    (net (code "89") (name "Net-(IC14D-O)") (class "Default")
      (node (ref "IC14") (pin "11") (pinfunction "O_11") (pintype "output"))
      (node (ref "U$6") (pin "4") (pinfunction "I4_4") (pintype "input"))
    )
    (net (code "90") (name "Net-(IC15A-I0)") (class "Default")
      (node (ref "IC15") (pin "1") (pinfunction "I0_1") (pintype "input"))
      (node (ref "IC3") (pin "19") (pinfunction "2Q5_19") (pintype "tri_state"))
      (node (ref "IC3") (pin "29") (pinfunction "2D6_29") (pintype "input"))
    )
    (net (code "91") (name "Net-(IC15A-O)") (class "Default")
      (node (ref "IC15") (pin "3") (pinfunction "O_3") (pintype "output"))
      (node (ref "U$6") (pin "5") (pinfunction "I5_5") (pintype "input"))
    )
    (net (code "92") (name "Net-(IC15B-I0)") (class "Default")
      (node (ref "IC15") (pin "4") (pinfunction "I0_4") (pintype "input"))
      (node (ref "IC3") (pin "20") (pinfunction "2Q6_20") (pintype "tri_state"))
      (node (ref "IC3") (pin "27") (pinfunction "2D7_27") (pintype "input"))
    )
    (net (code "93") (name "Net-(IC15B-O)") (class "Default")
      (node (ref "IC15") (pin "6") (pinfunction "O_6") (pintype "output"))
      (node (ref "U$6") (pin "6") (pinfunction "I6_6") (pintype "input"))
    )
    (net (code "94") (name "Net-(IC15C-I0)") (class "Default")
      (node (ref "IC15") (pin "9") (pinfunction "I0_9") (pintype "input"))
      (node (ref "IC3") (pin "22") (pinfunction "2Q7_22") (pintype "tri_state"))
      (node (ref "IC3") (pin "26") (pinfunction "2D8_26") (pintype "input"))
    )
    (net (code "95") (name "Net-(IC15C-O)") (class "Default")
      (node (ref "IC15") (pin "8") (pinfunction "O_8") (pintype "output"))
      (node (ref "U$6") (pin "7") (pinfunction "I7_7") (pintype "input"))
    )
    (net (code "96") (name "Net-(IC15D-I0)") (class "Default")
      (node (ref "IC15") (pin "12") (pinfunction "I0_12") (pintype "input"))
      (node (ref "IC16") (pin "47") (pinfunction "1D1_47") (pintype "input"))
      (node (ref "IC3") (pin "23") (pinfunction "2Q8_23") (pintype "tri_state"))
    )
    (net (code "97") (name "Net-(IC15D-O)") (class "Default")
      (node (ref "IC15") (pin "11") (pinfunction "O_11") (pintype "output"))
      (node (ref "U$6") (pin "8") (pinfunction "I8_8") (pintype "input"))
    )
    (net (code "98") (name "Net-(IC16A-1CLK)") (class "Default")
      (node (ref "IC1") (pin "25") (pinfunction "2CLK_25") (pintype "input"))
      (node (ref "IC1") (pin "48") (pinfunction "1CLK_48") (pintype "input"))
      (node (ref "IC16") (pin "25") (pinfunction "2CLK_25") (pintype "input"))
      (node (ref "IC16") (pin "48") (pinfunction "1CLK_48") (pintype "input"))
      (node (ref "IC21") (pin "25") (pinfunction "2CLK_25") (pintype "input"))
      (node (ref "IC21") (pin "48") (pinfunction "1CLK_48") (pintype "input"))
      (node (ref "IC26") (pin "25") (pinfunction "2CLK_25") (pintype "input"))
      (node (ref "IC26") (pin "48") (pinfunction "1CLK_48") (pintype "input"))
      (node (ref "IC3") (pin "25") (pinfunction "2CLK_25") (pintype "input"))
      (node (ref "IC3") (pin "48") (pinfunction "1CLK_48") (pintype "input"))
      (node (ref "IC31") (pin "25") (pinfunction "2CLK_25") (pintype "input"))
      (node (ref "IC31") (pin "48") (pinfunction "1CLK_48") (pintype "input"))
      (node (ref "IC36") (pin "25") (pinfunction "2CLK_25") (pintype "input"))
      (node (ref "IC36") (pin "48") (pinfunction "1CLK_48") (pintype "input"))
      (node (ref "IC41") (pin "25") (pinfunction "2CLK_25") (pintype "input"))
      (node (ref "IC41") (pin "48") (pinfunction "1CLK_48") (pintype "input"))
      (node (ref "IC46") (pin "25") (pinfunction "2CLK_25") (pintype "input"))
      (node (ref "IC46") (pin "48") (pinfunction "1CLK_48") (pintype "input"))
      (node (ref "IC51") (pin "25") (pinfunction "2CLK_25") (pintype "input"))
      (node (ref "IC51") (pin "48") (pinfunction "1CLK_48") (pintype "input"))
      (node (ref "IC56") (pin "25") (pinfunction "2CLK_25") (pintype "input"))
      (node (ref "IC56") (pin "48") (pinfunction "1CLK_48") (pintype "input"))
      (node (ref "IC61") (pin "25") (pinfunction "2CLK_25") (pintype "input"))
      (node (ref "IC61") (pin "48") (pinfunction "1CLK_48") (pintype "input"))
      (node (ref "IC66") (pin "25") (pinfunction "2CLK_25") (pintype "input"))
      (node (ref "IC66") (pin "48") (pinfunction "1CLK_48") (pintype "input"))
      (node (ref "IC71") (pin "25") (pinfunction "2CLK_25") (pintype "input"))
      (node (ref "IC71") (pin "48") (pinfunction "1CLK_48") (pintype "input"))
      (node (ref "IC76") (pin "25") (pinfunction "2CLK_25") (pintype "input"))
      (node (ref "IC76") (pin "48") (pinfunction "1CLK_48") (pintype "input"))
      (node (ref "IC8") (pin "25") (pinfunction "2CLK_25") (pintype "input"))
      (node (ref "IC8") (pin "48") (pinfunction "1CLK_48") (pintype "input"))
      (node (ref "IC81") (pin "25") (pinfunction "2CLK_25") (pintype "input"))
      (node (ref "IC81") (pin "48") (pinfunction "1CLK_48") (pintype "input"))
      (node (ref "IC86") (pin "25") (pinfunction "2CLK_25") (pintype "input"))
      (node (ref "IC86") (pin "48") (pinfunction "1CLK_48") (pintype "input"))
      (node (ref "IC91") (pin "25") (pinfunction "2CLK_25") (pintype "input"))
      (node (ref "IC91") (pin "48") (pinfunction "1CLK_48") (pintype "input"))
      (node (ref "IC96") (pin "25") (pinfunction "2CLK_25") (pintype "input"))
      (node (ref "IC96") (pin "48") (pinfunction "1CLK_48") (pintype "input"))
      (node (ref "X11") (pin "5") (pinfunction "S_5") (pintype "passive"))
    )
    (net (code "99") (name "Net-(IC16A-1D2)") (class "Default")
      (node (ref "IC16") (pin "2") (pinfunction "1Q1_2") (pintype "tri_state"))
      (node (ref "IC16") (pin "46") (pinfunction "1D2_46") (pintype "input"))
      (node (ref "IC17") (pin "1") (pinfunction "I0_1") (pintype "input"))
    )
    (net (code "100") (name "Net-(IC16A-1D3)") (class "Default")
      (node (ref "IC16") (pin "3") (pinfunction "1Q2_3") (pintype "tri_state"))
      (node (ref "IC16") (pin "44") (pinfunction "1D3_44") (pintype "input"))
      (node (ref "IC17") (pin "4") (pinfunction "I0_4") (pintype "input"))
    )
    (net (code "101") (name "Net-(IC16A-1D4)") (class "Default")
      (node (ref "IC16") (pin "43") (pinfunction "1D4_43") (pintype "input"))
      (node (ref "IC16") (pin "5") (pinfunction "1Q3_5") (pintype "tri_state"))
      (node (ref "IC17") (pin "9") (pinfunction "I0_9") (pintype "input"))
    )
    (net (code "102") (name "Net-(IC16A-1D5)") (class "Default")
      (node (ref "IC16") (pin "41") (pinfunction "1D5_41") (pintype "input"))
      (node (ref "IC16") (pin "6") (pinfunction "1Q4_6") (pintype "tri_state"))
      (node (ref "IC17") (pin "12") (pinfunction "I0_12") (pintype "input"))
    )
    (net (code "103") (name "Net-(IC16A-1D6)") (class "Default")
      (node (ref "IC16") (pin "40") (pinfunction "1D6_40") (pintype "input"))
      (node (ref "IC16") (pin "8") (pinfunction "1Q5_8") (pintype "tri_state"))
      (node (ref "IC18") (pin "1") (pinfunction "I0_1") (pintype "input"))
    )
    (net (code "104") (name "Net-(IC16A-1D7)") (class "Default")
      (node (ref "IC16") (pin "38") (pinfunction "1D7_38") (pintype "input"))
      (node (ref "IC16") (pin "9") (pinfunction "1Q6_9") (pintype "tri_state"))
      (node (ref "IC18") (pin "4") (pinfunction "I0_4") (pintype "input"))
    )
    (net (code "105") (name "Net-(IC16A-1D8)") (class "Default")
      (node (ref "IC16") (pin "11") (pinfunction "1Q7_11") (pintype "tri_state"))
      (node (ref "IC16") (pin "37") (pinfunction "1D8_37") (pintype "input"))
      (node (ref "IC18") (pin "9") (pinfunction "I0_9") (pintype "input"))
    )
    (net (code "106") (name "Net-(IC16A-1Q8)") (class "Default")
      (node (ref "IC16") (pin "12") (pinfunction "1Q8_12") (pintype "tri_state"))
      (node (ref "IC16") (pin "36") (pinfunction "2D1_36") (pintype "input"))
      (node (ref "IC18") (pin "12") (pinfunction "I0_12") (pintype "input"))
    )
    (net (code "107") (name "Net-(IC16A-2D2)") (class "Default")
      (node (ref "IC16") (pin "13") (pinfunction "2Q1_13") (pintype "tri_state"))
      (node (ref "IC16") (pin "35") (pinfunction "2D2_35") (pintype "input"))
      (node (ref "IC19") (pin "1") (pinfunction "I0_1") (pintype "input"))
    )
    (net (code "108") (name "Net-(IC16A-2D3)") (class "Default")
      (node (ref "IC16") (pin "14") (pinfunction "2Q2_14") (pintype "tri_state"))
      (node (ref "IC16") (pin "33") (pinfunction "2D3_33") (pintype "input"))
      (node (ref "IC19") (pin "4") (pinfunction "I0_4") (pintype "input"))
    )
    (net (code "109") (name "Net-(IC16A-2D4)") (class "Default")
      (node (ref "IC16") (pin "16") (pinfunction "2Q3_16") (pintype "tri_state"))
      (node (ref "IC16") (pin "32") (pinfunction "2D4_32") (pintype "input"))
      (node (ref "IC19") (pin "9") (pinfunction "I0_9") (pintype "input"))
    )
    (net (code "110") (name "Net-(IC16A-2D5)") (class "Default")
      (node (ref "IC16") (pin "17") (pinfunction "2Q4_17") (pintype "tri_state"))
      (node (ref "IC16") (pin "30") (pinfunction "2D5_30") (pintype "input"))
      (node (ref "IC19") (pin "12") (pinfunction "I0_12") (pintype "input"))
    )
    (net (code "111") (name "Net-(IC16A-2D6)") (class "Default")
      (node (ref "IC16") (pin "19") (pinfunction "2Q5_19") (pintype "tri_state"))
      (node (ref "IC16") (pin "29") (pinfunction "2D6_29") (pintype "input"))
      (node (ref "IC20") (pin "1") (pinfunction "I0_1") (pintype "input"))
    )
    (net (code "112") (name "Net-(IC16A-2D7)") (class "Default")
      (node (ref "IC16") (pin "20") (pinfunction "2Q6_20") (pintype "tri_state"))
      (node (ref "IC16") (pin "27") (pinfunction "2D7_27") (pintype "input"))
      (node (ref "IC20") (pin "4") (pinfunction "I0_4") (pintype "input"))
    )
    (net (code "113") (name "Net-(IC16A-2D8)") (class "Default")
      (node (ref "IC16") (pin "22") (pinfunction "2Q7_22") (pintype "tri_state"))
      (node (ref "IC16") (pin "26") (pinfunction "2D8_26") (pintype "input"))
      (node (ref "IC20") (pin "9") (pinfunction "I0_9") (pintype "input"))
    )
    (net (code "114") (name "Net-(IC16A-2Q8)") (class "Default")
      (node (ref "IC1") (pin "47") (pinfunction "1D1_47") (pintype "input"))
      (node (ref "IC16") (pin "23") (pinfunction "2Q8_23") (pintype "tri_state"))
      (node (ref "IC20") (pin "12") (pinfunction "I0_12") (pintype "input"))
    )
    (net (code "115") (name "Net-(IC17A-O)") (class "Default")
      (node (ref "IC17") (pin "3") (pinfunction "O_3") (pintype "output"))
      (node (ref "U$7") (pin "1") (pinfunction "I1_1") (pintype "input"))
    )
    (net (code "116") (name "Net-(IC17B-O)") (class "Default")
      (node (ref "IC17") (pin "6") (pinfunction "O_6") (pintype "output"))
      (node (ref "U$7") (pin "2") (pinfunction "I2_2") (pintype "input"))
    )
    (net (code "117") (name "Net-(IC17C-O)") (class "Default")
      (node (ref "IC17") (pin "8") (pinfunction "O_8") (pintype "output"))
      (node (ref "U$7") (pin "3") (pinfunction "I3_3") (pintype "input"))
    )
    (net (code "118") (name "Net-(IC17D-O)") (class "Default")
      (node (ref "IC17") (pin "11") (pinfunction "O_11") (pintype "output"))
      (node (ref "U$7") (pin "4") (pinfunction "I4_4") (pintype "input"))
    )
    (net (code "119") (name "Net-(IC18A-O)") (class "Default")
      (node (ref "IC18") (pin "3") (pinfunction "O_3") (pintype "output"))
      (node (ref "U$7") (pin "5") (pinfunction "I5_5") (pintype "input"))
    )
    (net (code "120") (name "Net-(IC18B-O)") (class "Default")
      (node (ref "IC18") (pin "6") (pinfunction "O_6") (pintype "output"))
      (node (ref "U$7") (pin "6") (pinfunction "I6_6") (pintype "input"))
    )
    (net (code "121") (name "Net-(IC18C-O)") (class "Default")
      (node (ref "IC18") (pin "8") (pinfunction "O_8") (pintype "output"))
      (node (ref "U$7") (pin "7") (pinfunction "I7_7") (pintype "input"))
    )
    (net (code "122") (name "Net-(IC18D-O)") (class "Default")
      (node (ref "IC18") (pin "11") (pinfunction "O_11") (pintype "output"))
      (node (ref "U$7") (pin "8") (pinfunction "I8_8") (pintype "input"))
    )
    (net (code "123") (name "Net-(IC19A-O)") (class "Default")
      (node (ref "IC19") (pin "3") (pinfunction "O_3") (pintype "output"))
      (node (ref "U$8") (pin "1") (pinfunction "I1_1") (pintype "input"))
    )
    (net (code "124") (name "Net-(IC19B-O)") (class "Default")
      (node (ref "IC19") (pin "6") (pinfunction "O_6") (pintype "output"))
      (node (ref "U$8") (pin "2") (pinfunction "I2_2") (pintype "input"))
    )
    (net (code "125") (name "Net-(IC19C-O)") (class "Default")
      (node (ref "IC19") (pin "8") (pinfunction "O_8") (pintype "output"))
      (node (ref "U$8") (pin "3") (pinfunction "I3_3") (pintype "input"))
    )
    (net (code "126") (name "Net-(IC19D-O)") (class "Default")
      (node (ref "IC19") (pin "11") (pinfunction "O_11") (pintype "output"))
      (node (ref "U$8") (pin "4") (pinfunction "I4_4") (pintype "input"))
    )
    (net (code "127") (name "Net-(IC20A-O)") (class "Default")
      (node (ref "IC20") (pin "3") (pinfunction "O_3") (pintype "output"))
      (node (ref "U$8") (pin "5") (pinfunction "I5_5") (pintype "input"))
    )
    (net (code "128") (name "Net-(IC20B-O)") (class "Default")
      (node (ref "IC20") (pin "6") (pinfunction "O_6") (pintype "output"))
      (node (ref "U$8") (pin "6") (pinfunction "I6_6") (pintype "input"))
    )
    (net (code "129") (name "Net-(IC20C-O)") (class "Default")
      (node (ref "IC20") (pin "8") (pinfunction "O_8") (pintype "output"))
      (node (ref "U$8") (pin "7") (pinfunction "I7_7") (pintype "input"))
    )
    (net (code "130") (name "Net-(IC20D-O)") (class "Default")
      (node (ref "IC20") (pin "11") (pinfunction "O_11") (pintype "output"))
      (node (ref "U$8") (pin "8") (pinfunction "I8_8") (pintype "input"))
    )
    (net (code "131") (name "Net-(IC21A-1D1)") (class "Default")
      (node (ref "IC21") (pin "47") (pinfunction "1D1_47") (pintype "input"))
      (node (ref "X11") (pin "4") (pinfunction "S_4") (pintype "passive"))
    )
    (net (code "132") (name "Net-(IC21A-1D2)") (class "Default")
      (node (ref "IC21") (pin "2") (pinfunction "1Q1_2") (pintype "tri_state"))
      (node (ref "IC21") (pin "46") (pinfunction "1D2_46") (pintype "input"))
      (node (ref "IC22") (pin "1") (pinfunction "I0_1") (pintype "input"))
    )
    (net (code "133") (name "Net-(IC21A-1D3)") (class "Default")
      (node (ref "IC21") (pin "3") (pinfunction "1Q2_3") (pintype "tri_state"))
      (node (ref "IC21") (pin "44") (pinfunction "1D3_44") (pintype "input"))
      (node (ref "IC22") (pin "4") (pinfunction "I0_4") (pintype "input"))
    )
    (net (code "134") (name "Net-(IC21A-1D4)") (class "Default")
      (node (ref "IC21") (pin "43") (pinfunction "1D4_43") (pintype "input"))
      (node (ref "IC21") (pin "5") (pinfunction "1Q3_5") (pintype "tri_state"))
      (node (ref "IC22") (pin "9") (pinfunction "I0_9") (pintype "input"))
    )
    (net (code "135") (name "Net-(IC21A-1D5)") (class "Default")
      (node (ref "IC21") (pin "41") (pinfunction "1D5_41") (pintype "input"))
      (node (ref "IC21") (pin "6") (pinfunction "1Q4_6") (pintype "tri_state"))
      (node (ref "IC22") (pin "12") (pinfunction "I0_12") (pintype "input"))
    )
    (net (code "136") (name "Net-(IC21A-1D6)") (class "Default")
      (node (ref "IC21") (pin "40") (pinfunction "1D6_40") (pintype "input"))
      (node (ref "IC21") (pin "8") (pinfunction "1Q5_8") (pintype "tri_state"))
      (node (ref "IC23") (pin "1") (pinfunction "I0_1") (pintype "input"))
    )
    (net (code "137") (name "Net-(IC21A-1D7)") (class "Default")
      (node (ref "IC21") (pin "38") (pinfunction "1D7_38") (pintype "input"))
      (node (ref "IC21") (pin "9") (pinfunction "1Q6_9") (pintype "tri_state"))
      (node (ref "IC23") (pin "4") (pinfunction "I0_4") (pintype "input"))
    )
    (net (code "138") (name "Net-(IC21A-1D8)") (class "Default")
      (node (ref "IC21") (pin "11") (pinfunction "1Q7_11") (pintype "tri_state"))
      (node (ref "IC21") (pin "37") (pinfunction "1D8_37") (pintype "input"))
      (node (ref "IC23") (pin "9") (pinfunction "I0_9") (pintype "input"))
    )
    (net (code "139") (name "Net-(IC21A-1Q8)") (class "Default")
      (node (ref "IC21") (pin "12") (pinfunction "1Q8_12") (pintype "tri_state"))
      (node (ref "IC21") (pin "36") (pinfunction "2D1_36") (pintype "input"))
      (node (ref "IC23") (pin "12") (pinfunction "I0_12") (pintype "input"))
    )
    (net (code "140") (name "Net-(IC21A-2D2)") (class "Default")
      (node (ref "IC21") (pin "13") (pinfunction "2Q1_13") (pintype "tri_state"))
      (node (ref "IC21") (pin "35") (pinfunction "2D2_35") (pintype "input"))
      (node (ref "IC24") (pin "1") (pinfunction "I0_1") (pintype "input"))
    )
    (net (code "141") (name "Net-(IC21A-2D3)") (class "Default")
      (node (ref "IC21") (pin "14") (pinfunction "2Q2_14") (pintype "tri_state"))
      (node (ref "IC21") (pin "33") (pinfunction "2D3_33") (pintype "input"))
      (node (ref "IC24") (pin "4") (pinfunction "I0_4") (pintype "input"))
    )
    (net (code "142") (name "Net-(IC21A-2D4)") (class "Default")
      (node (ref "IC21") (pin "16") (pinfunction "2Q3_16") (pintype "tri_state"))
      (node (ref "IC21") (pin "32") (pinfunction "2D4_32") (pintype "input"))
      (node (ref "IC24") (pin "9") (pinfunction "I0_9") (pintype "input"))
    )
    (net (code "143") (name "Net-(IC21A-2D5)") (class "Default")
      (node (ref "IC21") (pin "17") (pinfunction "2Q4_17") (pintype "tri_state"))
      (node (ref "IC21") (pin "30") (pinfunction "2D5_30") (pintype "input"))
      (node (ref "IC24") (pin "12") (pinfunction "I0_12") (pintype "input"))
    )
    (net (code "144") (name "Net-(IC21A-2D6)") (class "Default")
      (node (ref "IC21") (pin "19") (pinfunction "2Q5_19") (pintype "tri_state"))
      (node (ref "IC21") (pin "29") (pinfunction "2D6_29") (pintype "input"))
      (node (ref "IC25") (pin "1") (pinfunction "I0_1") (pintype "input"))
    )
    (net (code "145") (name "Net-(IC21A-2D7)") (class "Default")
      (node (ref "IC21") (pin "20") (pinfunction "2Q6_20") (pintype "tri_state"))
      (node (ref "IC21") (pin "27") (pinfunction "2D7_27") (pintype "input"))
      (node (ref "IC25") (pin "4") (pinfunction "I0_4") (pintype "input"))
    )
    (net (code "146") (name "Net-(IC21A-2D8)") (class "Default")
      (node (ref "IC21") (pin "22") (pinfunction "2Q7_22") (pintype "tri_state"))
      (node (ref "IC21") (pin "26") (pinfunction "2D8_26") (pintype "input"))
      (node (ref "IC25") (pin "9") (pinfunction "I0_9") (pintype "input"))
    )
    (net (code "147") (name "Net-(IC21A-2Q8)") (class "Default")
      (node (ref "IC21") (pin "23") (pinfunction "2Q8_23") (pintype "tri_state"))
      (node (ref "IC25") (pin "12") (pinfunction "I0_12") (pintype "input"))
      (node (ref "IC26") (pin "47") (pinfunction "1D1_47") (pintype "input"))
    )
    (net (code "148") (name "Net-(IC22A-O)") (class "Default")
      (node (ref "IC22") (pin "3") (pinfunction "O_3") (pintype "output"))
      (node (ref "U$9") (pin "1") (pinfunction "I1_1") (pintype "input"))
    )
    (net (code "149") (name "Net-(IC22B-O)") (class "Default")
      (node (ref "IC22") (pin "6") (pinfunction "O_6") (pintype "output"))
      (node (ref "U$9") (pin "2") (pinfunction "I2_2") (pintype "input"))
    )
    (net (code "150") (name "Net-(IC22C-O)") (class "Default")
      (node (ref "IC22") (pin "8") (pinfunction "O_8") (pintype "output"))
      (node (ref "U$9") (pin "3") (pinfunction "I3_3") (pintype "input"))
    )
    (net (code "151") (name "Net-(IC22D-O)") (class "Default")
      (node (ref "IC22") (pin "11") (pinfunction "O_11") (pintype "output"))
      (node (ref "U$9") (pin "4") (pinfunction "I4_4") (pintype "input"))
    )
    (net (code "152") (name "Net-(IC23A-O)") (class "Default")
      (node (ref "IC23") (pin "3") (pinfunction "O_3") (pintype "output"))
      (node (ref "U$9") (pin "5") (pinfunction "I5_5") (pintype "input"))
    )
    (net (code "153") (name "Net-(IC23B-O)") (class "Default")
      (node (ref "IC23") (pin "6") (pinfunction "O_6") (pintype "output"))
      (node (ref "U$9") (pin "6") (pinfunction "I6_6") (pintype "input"))
    )
    (net (code "154") (name "Net-(IC23C-O)") (class "Default")
      (node (ref "IC23") (pin "8") (pinfunction "O_8") (pintype "output"))
      (node (ref "U$9") (pin "7") (pinfunction "I7_7") (pintype "input"))
    )
    (net (code "155") (name "Net-(IC23D-O)") (class "Default")
      (node (ref "IC23") (pin "11") (pinfunction "O_11") (pintype "output"))
      (node (ref "U$9") (pin "8") (pinfunction "I8_8") (pintype "input"))
    )
    (net (code "156") (name "Net-(IC24A-O)") (class "Default")
      (node (ref "IC24") (pin "3") (pinfunction "O_3") (pintype "output"))
      (node (ref "U$10") (pin "1") (pinfunction "I1_1") (pintype "input"))
    )
    (net (code "157") (name "Net-(IC24B-O)") (class "Default")
      (node (ref "IC24") (pin "6") (pinfunction "O_6") (pintype "output"))
      (node (ref "U$10") (pin "2") (pinfunction "I2_2") (pintype "input"))
    )
    (net (code "158") (name "Net-(IC24C-O)") (class "Default")
      (node (ref "IC24") (pin "8") (pinfunction "O_8") (pintype "output"))
      (node (ref "U$10") (pin "3") (pinfunction "I3_3") (pintype "input"))
    )
    (net (code "159") (name "Net-(IC24D-O)") (class "Default")
      (node (ref "IC24") (pin "11") (pinfunction "O_11") (pintype "output"))
      (node (ref "U$10") (pin "4") (pinfunction "I4_4") (pintype "input"))
    )
    (net (code "160") (name "Net-(IC25A-O)") (class "Default")
      (node (ref "IC25") (pin "3") (pinfunction "O_3") (pintype "output"))
      (node (ref "U$10") (pin "5") (pinfunction "I5_5") (pintype "input"))
    )
    (net (code "161") (name "Net-(IC25B-O)") (class "Default")
      (node (ref "IC25") (pin "6") (pinfunction "O_6") (pintype "output"))
      (node (ref "U$10") (pin "6") (pinfunction "I6_6") (pintype "input"))
    )
    (net (code "162") (name "Net-(IC25C-O)") (class "Default")
      (node (ref "IC25") (pin "8") (pinfunction "O_8") (pintype "output"))
      (node (ref "U$10") (pin "7") (pinfunction "I7_7") (pintype "input"))
    )
    (net (code "163") (name "Net-(IC25D-O)") (class "Default")
      (node (ref "IC25") (pin "11") (pinfunction "O_11") (pintype "output"))
      (node (ref "U$10") (pin "8") (pinfunction "I8_8") (pintype "input"))
    )
    (net (code "164") (name "Net-(IC26A-1D2)") (class "Default")
      (node (ref "IC26") (pin "2") (pinfunction "1Q1_2") (pintype "tri_state"))
      (node (ref "IC26") (pin "46") (pinfunction "1D2_46") (pintype "input"))
      (node (ref "IC27") (pin "1") (pinfunction "I0_1") (pintype "input"))
    )
    (net (code "165") (name "Net-(IC26A-1D3)") (class "Default")
      (node (ref "IC26") (pin "3") (pinfunction "1Q2_3") (pintype "tri_state"))
      (node (ref "IC26") (pin "44") (pinfunction "1D3_44") (pintype "input"))
      (node (ref "IC27") (pin "4") (pinfunction "I0_4") (pintype "input"))
    )
    (net (code "166") (name "Net-(IC26A-1D4)") (class "Default")
      (node (ref "IC26") (pin "43") (pinfunction "1D4_43") (pintype "input"))
      (node (ref "IC26") (pin "5") (pinfunction "1Q3_5") (pintype "tri_state"))
      (node (ref "IC27") (pin "9") (pinfunction "I0_9") (pintype "input"))
    )
    (net (code "167") (name "Net-(IC26A-1D5)") (class "Default")
      (node (ref "IC26") (pin "41") (pinfunction "1D5_41") (pintype "input"))
      (node (ref "IC26") (pin "6") (pinfunction "1Q4_6") (pintype "tri_state"))
      (node (ref "IC27") (pin "12") (pinfunction "I0_12") (pintype "input"))
    )
    (net (code "168") (name "Net-(IC26A-1D6)") (class "Default")
      (node (ref "IC26") (pin "40") (pinfunction "1D6_40") (pintype "input"))
      (node (ref "IC26") (pin "8") (pinfunction "1Q5_8") (pintype "tri_state"))
      (node (ref "IC28") (pin "1") (pinfunction "I0_1") (pintype "input"))
    )
    (net (code "169") (name "Net-(IC26A-1D7)") (class "Default")
      (node (ref "IC26") (pin "38") (pinfunction "1D7_38") (pintype "input"))
      (node (ref "IC26") (pin "9") (pinfunction "1Q6_9") (pintype "tri_state"))
      (node (ref "IC28") (pin "4") (pinfunction "I0_4") (pintype "input"))
    )
    (net (code "170") (name "Net-(IC26A-1D8)") (class "Default")
      (node (ref "IC26") (pin "11") (pinfunction "1Q7_11") (pintype "tri_state"))
      (node (ref "IC26") (pin "37") (pinfunction "1D8_37") (pintype "input"))
      (node (ref "IC28") (pin "9") (pinfunction "I0_9") (pintype "input"))
    )
    (net (code "171") (name "Net-(IC26A-1Q8)") (class "Default")
      (node (ref "IC26") (pin "12") (pinfunction "1Q8_12") (pintype "tri_state"))
      (node (ref "IC26") (pin "36") (pinfunction "2D1_36") (pintype "input"))
      (node (ref "IC28") (pin "12") (pinfunction "I0_12") (pintype "input"))
    )
    (net (code "172") (name "Net-(IC26A-2D2)") (class "Default")
      (node (ref "IC26") (pin "13") (pinfunction "2Q1_13") (pintype "tri_state"))
      (node (ref "IC26") (pin "35") (pinfunction "2D2_35") (pintype "input"))
      (node (ref "IC29") (pin "1") (pinfunction "I0_1") (pintype "input"))
    )
    (net (code "173") (name "Net-(IC26A-2D3)") (class "Default")
      (node (ref "IC26") (pin "14") (pinfunction "2Q2_14") (pintype "tri_state"))
      (node (ref "IC26") (pin "33") (pinfunction "2D3_33") (pintype "input"))
      (node (ref "IC29") (pin "4") (pinfunction "I0_4") (pintype "input"))
    )
    (net (code "174") (name "Net-(IC26A-2D4)") (class "Default")
      (node (ref "IC26") (pin "16") (pinfunction "2Q3_16") (pintype "tri_state"))
      (node (ref "IC26") (pin "32") (pinfunction "2D4_32") (pintype "input"))
      (node (ref "IC29") (pin "9") (pinfunction "I0_9") (pintype "input"))
    )
    (net (code "175") (name "Net-(IC26A-2D5)") (class "Default")
      (node (ref "IC26") (pin "17") (pinfunction "2Q4_17") (pintype "tri_state"))
      (node (ref "IC26") (pin "30") (pinfunction "2D5_30") (pintype "input"))
      (node (ref "IC29") (pin "12") (pinfunction "I0_12") (pintype "input"))
    )
    (net (code "176") (name "Net-(IC26A-2D6)") (class "Default")
      (node (ref "IC26") (pin "19") (pinfunction "2Q5_19") (pintype "tri_state"))
      (node (ref "IC26") (pin "29") (pinfunction "2D6_29") (pintype "input"))
      (node (ref "IC30") (pin "1") (pinfunction "I0_1") (pintype "input"))
    )
    (net (code "177") (name "Net-(IC26A-2D7)") (class "Default")
      (node (ref "IC26") (pin "20") (pinfunction "2Q6_20") (pintype "tri_state"))
      (node (ref "IC26") (pin "27") (pinfunction "2D7_27") (pintype "input"))
      (node (ref "IC30") (pin "4") (pinfunction "I0_4") (pintype "input"))
    )
    (net (code "178") (name "Net-(IC26A-2D8)") (class "Default")
      (node (ref "IC26") (pin "22") (pinfunction "2Q7_22") (pintype "tri_state"))
      (node (ref "IC26") (pin "26") (pinfunction "2D8_26") (pintype "input"))
      (node (ref "IC30") (pin "9") (pinfunction "I0_9") (pintype "input"))
    )
    (net (code "179") (name "Net-(IC26A-2Q8)") (class "Default")
      (node (ref "IC26") (pin "23") (pinfunction "2Q8_23") (pintype "tri_state"))
      (node (ref "IC3") (pin "47") (pinfunction "1D1_47") (pintype "input"))
      (node (ref "IC30") (pin "12") (pinfunction "I0_12") (pintype "input"))
    )
    (net (code "180") (name "Net-(IC27A-O)") (class "Default")
      (node (ref "IC27") (pin "3") (pinfunction "O_3") (pintype "output"))
      (node (ref "U$11") (pin "1") (pinfunction "I1_1") (pintype "input"))
    )
    (net (code "181") (name "Net-(IC27B-O)") (class "Default")
      (node (ref "IC27") (pin "6") (pinfunction "O_6") (pintype "output"))
      (node (ref "U$11") (pin "2") (pinfunction "I2_2") (pintype "input"))
    )
    (net (code "182") (name "Net-(IC27C-O)") (class "Default")
      (node (ref "IC27") (pin "8") (pinfunction "O_8") (pintype "output"))
      (node (ref "U$11") (pin "3") (pinfunction "I3_3") (pintype "input"))
    )
    (net (code "183") (name "Net-(IC27D-O)") (class "Default")
      (node (ref "IC27") (pin "11") (pinfunction "O_11") (pintype "output"))
      (node (ref "U$11") (pin "4") (pinfunction "I4_4") (pintype "input"))
    )
    (net (code "184") (name "Net-(IC28A-O)") (class "Default")
      (node (ref "IC28") (pin "3") (pinfunction "O_3") (pintype "output"))
      (node (ref "U$11") (pin "5") (pinfunction "I5_5") (pintype "input"))
    )
    (net (code "185") (name "Net-(IC28B-O)") (class "Default")
      (node (ref "IC28") (pin "6") (pinfunction "O_6") (pintype "output"))
      (node (ref "U$11") (pin "6") (pinfunction "I6_6") (pintype "input"))
    )
    (net (code "186") (name "Net-(IC28C-O)") (class "Default")
      (node (ref "IC28") (pin "8") (pinfunction "O_8") (pintype "output"))
      (node (ref "U$11") (pin "7") (pinfunction "I7_7") (pintype "input"))
    )
    (net (code "187") (name "Net-(IC28D-O)") (class "Default")
      (node (ref "IC28") (pin "11") (pinfunction "O_11") (pintype "output"))
      (node (ref "U$11") (pin "8") (pinfunction "I8_8") (pintype "input"))
    )
    (net (code "188") (name "Net-(IC29A-O)") (class "Default")
      (node (ref "IC29") (pin "3") (pinfunction "O_3") (pintype "output"))
      (node (ref "U$12") (pin "1") (pinfunction "I1_1") (pintype "input"))
    )
    (net (code "189") (name "Net-(IC29B-O)") (class "Default")
      (node (ref "IC29") (pin "6") (pinfunction "O_6") (pintype "output"))
      (node (ref "U$12") (pin "2") (pinfunction "I2_2") (pintype "input"))
    )
    (net (code "190") (name "Net-(IC29C-O)") (class "Default")
      (node (ref "IC29") (pin "8") (pinfunction "O_8") (pintype "output"))
      (node (ref "U$12") (pin "3") (pinfunction "I3_3") (pintype "input"))
    )
    (net (code "191") (name "Net-(IC29D-O)") (class "Default")
      (node (ref "IC29") (pin "11") (pinfunction "O_11") (pintype "output"))
      (node (ref "U$12") (pin "4") (pinfunction "I4_4") (pintype "input"))
    )
    (net (code "192") (name "Net-(IC30A-O)") (class "Default")
      (node (ref "IC30") (pin "3") (pinfunction "O_3") (pintype "output"))
      (node (ref "U$12") (pin "5") (pinfunction "I5_5") (pintype "input"))
    )
    (net (code "193") (name "Net-(IC30B-O)") (class "Default")
      (node (ref "IC30") (pin "6") (pinfunction "O_6") (pintype "output"))
      (node (ref "U$12") (pin "6") (pinfunction "I6_6") (pintype "input"))
    )
    (net (code "194") (name "Net-(IC30C-O)") (class "Default")
      (node (ref "IC30") (pin "8") (pinfunction "O_8") (pintype "output"))
      (node (ref "U$12") (pin "7") (pinfunction "I7_7") (pintype "input"))
    )
    (net (code "195") (name "Net-(IC30D-O)") (class "Default")
      (node (ref "IC30") (pin "11") (pinfunction "O_11") (pintype "output"))
      (node (ref "U$12") (pin "8") (pinfunction "I8_8") (pintype "input"))
    )
    (net (code "196") (name "Net-(IC31A-1D1)") (class "Default")
      (node (ref "IC31") (pin "47") (pinfunction "1D1_47") (pintype "input"))
      (node (ref "IC66") (pin "23") (pinfunction "2Q8_23") (pintype "tri_state"))
      (node (ref "IC70") (pin "12") (pinfunction "I0_12") (pintype "input"))
    )
    (net (code "197") (name "Net-(IC31A-1D2)") (class "Default")
      (node (ref "IC31") (pin "2") (pinfunction "1Q1_2") (pintype "tri_state"))
      (node (ref "IC31") (pin "46") (pinfunction "1D2_46") (pintype "input"))
      (node (ref "IC32") (pin "1") (pinfunction "I0_1") (pintype "input"))
    )
    (net (code "198") (name "Net-(IC31A-1D3)") (class "Default")
      (node (ref "IC31") (pin "3") (pinfunction "1Q2_3") (pintype "tri_state"))
      (node (ref "IC31") (pin "44") (pinfunction "1D3_44") (pintype "input"))
      (node (ref "IC32") (pin "4") (pinfunction "I0_4") (pintype "input"))
    )
    (net (code "199") (name "Net-(IC31A-1D4)") (class "Default")
      (node (ref "IC31") (pin "43") (pinfunction "1D4_43") (pintype "input"))
      (node (ref "IC31") (pin "5") (pinfunction "1Q3_5") (pintype "tri_state"))
      (node (ref "IC32") (pin "9") (pinfunction "I0_9") (pintype "input"))
    )
    (net (code "200") (name "Net-(IC31A-1D5)") (class "Default")
      (node (ref "IC31") (pin "41") (pinfunction "1D5_41") (pintype "input"))
      (node (ref "IC31") (pin "6") (pinfunction "1Q4_6") (pintype "tri_state"))
      (node (ref "IC32") (pin "12") (pinfunction "I0_12") (pintype "input"))
    )
    (net (code "201") (name "Net-(IC31A-1D6)") (class "Default")
      (node (ref "IC31") (pin "40") (pinfunction "1D6_40") (pintype "input"))
      (node (ref "IC31") (pin "8") (pinfunction "1Q5_8") (pintype "tri_state"))
      (node (ref "IC33") (pin "1") (pinfunction "I0_1") (pintype "input"))
    )
    (net (code "202") (name "Net-(IC31A-1D7)") (class "Default")
      (node (ref "IC31") (pin "38") (pinfunction "1D7_38") (pintype "input"))
      (node (ref "IC31") (pin "9") (pinfunction "1Q6_9") (pintype "tri_state"))
      (node (ref "IC33") (pin "4") (pinfunction "I0_4") (pintype "input"))
    )
    (net (code "203") (name "Net-(IC31A-1D8)") (class "Default")
      (node (ref "IC31") (pin "11") (pinfunction "1Q7_11") (pintype "tri_state"))
      (node (ref "IC31") (pin "37") (pinfunction "1D8_37") (pintype "input"))
      (node (ref "IC33") (pin "9") (pinfunction "I0_9") (pintype "input"))
    )
    (net (code "204") (name "Net-(IC31A-1Q8)") (class "Default")
      (node (ref "IC31") (pin "12") (pinfunction "1Q8_12") (pintype "tri_state"))
      (node (ref "IC31") (pin "36") (pinfunction "2D1_36") (pintype "input"))
      (node (ref "IC33") (pin "12") (pinfunction "I0_12") (pintype "input"))
    )
    (net (code "205") (name "Net-(IC31A-2D2)") (class "Default")
      (node (ref "IC31") (pin "13") (pinfunction "2Q1_13") (pintype "tri_state"))
      (node (ref "IC31") (pin "35") (pinfunction "2D2_35") (pintype "input"))
      (node (ref "IC34") (pin "1") (pinfunction "I0_1") (pintype "input"))
    )
    (net (code "206") (name "Net-(IC31A-2D3)") (class "Default")
      (node (ref "IC31") (pin "14") (pinfunction "2Q2_14") (pintype "tri_state"))
      (node (ref "IC31") (pin "33") (pinfunction "2D3_33") (pintype "input"))
      (node (ref "IC34") (pin "4") (pinfunction "I0_4") (pintype "input"))
    )
    (net (code "207") (name "Net-(IC31A-2D4)") (class "Default")
      (node (ref "IC31") (pin "16") (pinfunction "2Q3_16") (pintype "tri_state"))
      (node (ref "IC31") (pin "32") (pinfunction "2D4_32") (pintype "input"))
      (node (ref "IC34") (pin "9") (pinfunction "I0_9") (pintype "input"))
    )
    (net (code "208") (name "Net-(IC31A-2D5)") (class "Default")
      (node (ref "IC31") (pin "17") (pinfunction "2Q4_17") (pintype "tri_state"))
      (node (ref "IC31") (pin "30") (pinfunction "2D5_30") (pintype "input"))
      (node (ref "IC34") (pin "12") (pinfunction "I0_12") (pintype "input"))
    )
    (net (code "209") (name "Net-(IC31A-2D6)") (class "Default")
      (node (ref "IC31") (pin "19") (pinfunction "2Q5_19") (pintype "tri_state"))
      (node (ref "IC31") (pin "29") (pinfunction "2D6_29") (pintype "input"))
      (node (ref "IC35") (pin "1") (pinfunction "I0_1") (pintype "input"))
    )
    (net (code "210") (name "Net-(IC31A-2D7)") (class "Default")
      (node (ref "IC31") (pin "20") (pinfunction "2Q6_20") (pintype "tri_state"))
      (node (ref "IC31") (pin "27") (pinfunction "2D7_27") (pintype "input"))
      (node (ref "IC35") (pin "4") (pinfunction "I0_4") (pintype "input"))
    )
    (net (code "211") (name "Net-(IC31A-2D8)") (class "Default")
      (node (ref "IC31") (pin "22") (pinfunction "2Q7_22") (pintype "tri_state"))
      (node (ref "IC31") (pin "26") (pinfunction "2D8_26") (pintype "input"))
      (node (ref "IC35") (pin "9") (pinfunction "I0_9") (pintype "input"))
    )
    (net (code "212") (name "Net-(IC31A-2Q8)") (class "Default")
      (node (ref "IC31") (pin "23") (pinfunction "2Q8_23") (pintype "tri_state"))
      (node (ref "IC35") (pin "12") (pinfunction "I0_12") (pintype "input"))
      (node (ref "IC36") (pin "47") (pinfunction "1D1_47") (pintype "input"))
    )
    (net (code "213") (name "Net-(IC32A-O)") (class "Default")
      (node (ref "IC32") (pin "3") (pinfunction "O_3") (pintype "output"))
      (node (ref "U$13") (pin "1") (pinfunction "I1_1") (pintype "input"))
    )
    (net (code "214") (name "Net-(IC32B-O)") (class "Default")
      (node (ref "IC32") (pin "6") (pinfunction "O_6") (pintype "output"))
      (node (ref "U$13") (pin "2") (pinfunction "I2_2") (pintype "input"))
    )
    (net (code "215") (name "Net-(IC32C-O)") (class "Default")
      (node (ref "IC32") (pin "8") (pinfunction "O_8") (pintype "output"))
      (node (ref "U$13") (pin "3") (pinfunction "I3_3") (pintype "input"))
    )
    (net (code "216") (name "Net-(IC32D-O)") (class "Default")
      (node (ref "IC32") (pin "11") (pinfunction "O_11") (pintype "output"))
      (node (ref "U$13") (pin "4") (pinfunction "I4_4") (pintype "input"))
    )
    (net (code "217") (name "Net-(IC33A-O)") (class "Default")
      (node (ref "IC33") (pin "3") (pinfunction "O_3") (pintype "output"))
      (node (ref "U$13") (pin "5") (pinfunction "I5_5") (pintype "input"))
    )
    (net (code "218") (name "Net-(IC33B-O)") (class "Default")
      (node (ref "IC33") (pin "6") (pinfunction "O_6") (pintype "output"))
      (node (ref "U$13") (pin "6") (pinfunction "I6_6") (pintype "input"))
    )
    (net (code "219") (name "Net-(IC33C-O)") (class "Default")
      (node (ref "IC33") (pin "8") (pinfunction "O_8") (pintype "output"))
      (node (ref "U$13") (pin "7") (pinfunction "I7_7") (pintype "input"))
    )
    (net (code "220") (name "Net-(IC33D-O)") (class "Default")
      (node (ref "IC33") (pin "11") (pinfunction "O_11") (pintype "output"))
      (node (ref "U$13") (pin "8") (pinfunction "I8_8") (pintype "input"))
    )
    (net (code "221") (name "Net-(IC34A-O)") (class "Default")
      (node (ref "IC34") (pin "3") (pinfunction "O_3") (pintype "output"))
      (node (ref "U$14") (pin "1") (pinfunction "I1_1") (pintype "input"))
    )
    (net (code "222") (name "Net-(IC34B-O)") (class "Default")
      (node (ref "IC34") (pin "6") (pinfunction "O_6") (pintype "output"))
      (node (ref "U$14") (pin "2") (pinfunction "I2_2") (pintype "input"))
    )
    (net (code "223") (name "Net-(IC34C-O)") (class "Default")
      (node (ref "IC34") (pin "8") (pinfunction "O_8") (pintype "output"))
      (node (ref "U$14") (pin "3") (pinfunction "I3_3") (pintype "input"))
    )
    (net (code "224") (name "Net-(IC34D-O)") (class "Default")
      (node (ref "IC34") (pin "11") (pinfunction "O_11") (pintype "output"))
      (node (ref "U$14") (pin "4") (pinfunction "I4_4") (pintype "input"))
    )
    (net (code "225") (name "Net-(IC35A-O)") (class "Default")
      (node (ref "IC35") (pin "3") (pinfunction "O_3") (pintype "output"))
      (node (ref "U$14") (pin "5") (pinfunction "I5_5") (pintype "input"))
    )
    (net (code "226") (name "Net-(IC35B-O)") (class "Default")
      (node (ref "IC35") (pin "6") (pinfunction "O_6") (pintype "output"))
      (node (ref "U$14") (pin "6") (pinfunction "I6_6") (pintype "input"))
    )
    (net (code "227") (name "Net-(IC35C-O)") (class "Default")
      (node (ref "IC35") (pin "8") (pinfunction "O_8") (pintype "output"))
      (node (ref "U$14") (pin "7") (pinfunction "I7_7") (pintype "input"))
    )
    (net (code "228") (name "Net-(IC35D-O)") (class "Default")
      (node (ref "IC35") (pin "11") (pinfunction "O_11") (pintype "output"))
      (node (ref "U$14") (pin "8") (pinfunction "I8_8") (pintype "input"))
    )
    (net (code "229") (name "Net-(IC36A-1D2)") (class "Default")
      (node (ref "IC36") (pin "2") (pinfunction "1Q1_2") (pintype "tri_state"))
      (node (ref "IC36") (pin "46") (pinfunction "1D2_46") (pintype "input"))
      (node (ref "IC37") (pin "1") (pinfunction "I0_1") (pintype "input"))
    )
    (net (code "230") (name "Net-(IC36A-1D3)") (class "Default")
      (node (ref "IC36") (pin "3") (pinfunction "1Q2_3") (pintype "tri_state"))
      (node (ref "IC36") (pin "44") (pinfunction "1D3_44") (pintype "input"))
      (node (ref "IC37") (pin "4") (pinfunction "I0_4") (pintype "input"))
    )
    (net (code "231") (name "Net-(IC36A-1D4)") (class "Default")
      (node (ref "IC36") (pin "43") (pinfunction "1D4_43") (pintype "input"))
      (node (ref "IC36") (pin "5") (pinfunction "1Q3_5") (pintype "tri_state"))
      (node (ref "IC37") (pin "9") (pinfunction "I0_9") (pintype "input"))
    )
    (net (code "232") (name "Net-(IC36A-1D5)") (class "Default")
      (node (ref "IC36") (pin "41") (pinfunction "1D5_41") (pintype "input"))
      (node (ref "IC36") (pin "6") (pinfunction "1Q4_6") (pintype "tri_state"))
      (node (ref "IC37") (pin "12") (pinfunction "I0_12") (pintype "input"))
    )
    (net (code "233") (name "Net-(IC36A-1D6)") (class "Default")
      (node (ref "IC36") (pin "40") (pinfunction "1D6_40") (pintype "input"))
      (node (ref "IC36") (pin "8") (pinfunction "1Q5_8") (pintype "tri_state"))
      (node (ref "IC38") (pin "1") (pinfunction "I0_1") (pintype "input"))
    )
    (net (code "234") (name "Net-(IC36A-1D7)") (class "Default")
      (node (ref "IC36") (pin "38") (pinfunction "1D7_38") (pintype "input"))
      (node (ref "IC36") (pin "9") (pinfunction "1Q6_9") (pintype "tri_state"))
      (node (ref "IC38") (pin "4") (pinfunction "I0_4") (pintype "input"))
    )
    (net (code "235") (name "Net-(IC36A-1D8)") (class "Default")
      (node (ref "IC36") (pin "11") (pinfunction "1Q7_11") (pintype "tri_state"))
      (node (ref "IC36") (pin "37") (pinfunction "1D8_37") (pintype "input"))
      (node (ref "IC38") (pin "9") (pinfunction "I0_9") (pintype "input"))
    )
    (net (code "236") (name "Net-(IC36A-1Q8)") (class "Default")
      (node (ref "IC36") (pin "12") (pinfunction "1Q8_12") (pintype "tri_state"))
      (node (ref "IC36") (pin "36") (pinfunction "2D1_36") (pintype "input"))
      (node (ref "IC38") (pin "12") (pinfunction "I0_12") (pintype "input"))
    )
    (net (code "237") (name "Net-(IC36A-2D2)") (class "Default")
      (node (ref "IC36") (pin "13") (pinfunction "2Q1_13") (pintype "tri_state"))
      (node (ref "IC36") (pin "35") (pinfunction "2D2_35") (pintype "input"))
      (node (ref "IC39") (pin "1") (pinfunction "I0_1") (pintype "input"))
    )
    (net (code "238") (name "Net-(IC36A-2D3)") (class "Default")
      (node (ref "IC36") (pin "14") (pinfunction "2Q2_14") (pintype "tri_state"))
      (node (ref "IC36") (pin "33") (pinfunction "2D3_33") (pintype "input"))
      (node (ref "IC39") (pin "4") (pinfunction "I0_4") (pintype "input"))
    )
    (net (code "239") (name "Net-(IC36A-2D4)") (class "Default")
      (node (ref "IC36") (pin "16") (pinfunction "2Q3_16") (pintype "tri_state"))
      (node (ref "IC36") (pin "32") (pinfunction "2D4_32") (pintype "input"))
      (node (ref "IC39") (pin "9") (pinfunction "I0_9") (pintype "input"))
    )
    (net (code "240") (name "Net-(IC36A-2D5)") (class "Default")
      (node (ref "IC36") (pin "17") (pinfunction "2Q4_17") (pintype "tri_state"))
      (node (ref "IC36") (pin "30") (pinfunction "2D5_30") (pintype "input"))
      (node (ref "IC39") (pin "12") (pinfunction "I0_12") (pintype "input"))
    )
    (net (code "241") (name "Net-(IC36A-2D6)") (class "Default")
      (node (ref "IC36") (pin "19") (pinfunction "2Q5_19") (pintype "tri_state"))
      (node (ref "IC36") (pin "29") (pinfunction "2D6_29") (pintype "input"))
      (node (ref "IC40") (pin "1") (pinfunction "I0_1") (pintype "input"))
    )
    (net (code "242") (name "Net-(IC36A-2D7)") (class "Default")
      (node (ref "IC36") (pin "20") (pinfunction "2Q6_20") (pintype "tri_state"))
      (node (ref "IC36") (pin "27") (pinfunction "2D7_27") (pintype "input"))
      (node (ref "IC40") (pin "4") (pinfunction "I0_4") (pintype "input"))
    )
    (net (code "243") (name "Net-(IC36A-2D8)") (class "Default")
      (node (ref "IC36") (pin "22") (pinfunction "2Q7_22") (pintype "tri_state"))
      (node (ref "IC36") (pin "26") (pinfunction "2D8_26") (pintype "input"))
      (node (ref "IC40") (pin "9") (pinfunction "I0_9") (pintype "input"))
    )
    (net (code "244") (name "Net-(IC36A-2Q8)") (class "Default")
      (node (ref "IC36") (pin "23") (pinfunction "2Q8_23") (pintype "tri_state"))
      (node (ref "IC40") (pin "12") (pinfunction "I0_12") (pintype "input"))
      (node (ref "X11") (pin "2") (pinfunction "S_2") (pintype "passive"))
    )
    (net (code "245") (name "Net-(IC37A-O)") (class "Default")
      (node (ref "IC37") (pin "3") (pinfunction "O_3") (pintype "output"))
      (node (ref "U$15") (pin "1") (pinfunction "I1_1") (pintype "input"))
    )
    (net (code "246") (name "Net-(IC37B-O)") (class "Default")
      (node (ref "IC37") (pin "6") (pinfunction "O_6") (pintype "output"))
      (node (ref "U$15") (pin "2") (pinfunction "I2_2") (pintype "input"))
    )
    (net (code "247") (name "Net-(IC37C-O)") (class "Default")
      (node (ref "IC37") (pin "8") (pinfunction "O_8") (pintype "output"))
      (node (ref "U$15") (pin "3") (pinfunction "I3_3") (pintype "input"))
    )
    (net (code "248") (name "Net-(IC37D-O)") (class "Default")
      (node (ref "IC37") (pin "11") (pinfunction "O_11") (pintype "output"))
      (node (ref "U$15") (pin "4") (pinfunction "I4_4") (pintype "input"))
    )
    (net (code "249") (name "Net-(IC38A-O)") (class "Default")
      (node (ref "IC38") (pin "3") (pinfunction "O_3") (pintype "output"))
      (node (ref "U$15") (pin "5") (pinfunction "I5_5") (pintype "input"))
    )
    (net (code "250") (name "Net-(IC38B-O)") (class "Default")
      (node (ref "IC38") (pin "6") (pinfunction "O_6") (pintype "output"))
      (node (ref "U$15") (pin "6") (pinfunction "I6_6") (pintype "input"))
    )
    (net (code "251") (name "Net-(IC38C-O)") (class "Default")
      (node (ref "IC38") (pin "8") (pinfunction "O_8") (pintype "output"))
      (node (ref "U$15") (pin "7") (pinfunction "I7_7") (pintype "input"))
    )
    (net (code "252") (name "Net-(IC38D-O)") (class "Default")
      (node (ref "IC38") (pin "11") (pinfunction "O_11") (pintype "output"))
      (node (ref "U$15") (pin "8") (pinfunction "I8_8") (pintype "input"))
    )
    (net (code "253") (name "Net-(IC39A-O)") (class "Default")
      (node (ref "IC39") (pin "3") (pinfunction "O_3") (pintype "output"))
      (node (ref "U$16") (pin "1") (pinfunction "I1_1") (pintype "input"))
    )
    (net (code "254") (name "Net-(IC39B-O)") (class "Default")
      (node (ref "IC39") (pin "6") (pinfunction "O_6") (pintype "output"))
      (node (ref "U$16") (pin "2") (pinfunction "I2_2") (pintype "input"))
    )
    (net (code "255") (name "Net-(IC39C-O)") (class "Default")
      (node (ref "IC39") (pin "8") (pinfunction "O_8") (pintype "output"))
      (node (ref "U$16") (pin "3") (pinfunction "I3_3") (pintype "input"))
    )
    (net (code "256") (name "Net-(IC39D-O)") (class "Default")
      (node (ref "IC39") (pin "11") (pinfunction "O_11") (pintype "output"))
      (node (ref "U$16") (pin "4") (pinfunction "I4_4") (pintype "input"))
    )
    (net (code "257") (name "Net-(IC40A-O)") (class "Default")
      (node (ref "IC40") (pin "3") (pinfunction "O_3") (pintype "output"))
      (node (ref "U$16") (pin "5") (pinfunction "I5_5") (pintype "input"))
    )
    (net (code "258") (name "Net-(IC40B-O)") (class "Default")
      (node (ref "IC40") (pin "6") (pinfunction "O_6") (pintype "output"))
      (node (ref "U$16") (pin "6") (pinfunction "I6_6") (pintype "input"))
    )
    (net (code "259") (name "Net-(IC40C-O)") (class "Default")
      (node (ref "IC40") (pin "8") (pinfunction "O_8") (pintype "output"))
      (node (ref "U$16") (pin "7") (pinfunction "I7_7") (pintype "input"))
    )
    (net (code "260") (name "Net-(IC40D-O)") (class "Default")
      (node (ref "IC40") (pin "11") (pinfunction "O_11") (pintype "output"))
      (node (ref "U$16") (pin "8") (pinfunction "I8_8") (pintype "input"))
    )
    (net (code "261") (name "Net-(IC41A-1D1)") (class "Default")
      (node (ref "IC41") (pin "47") (pinfunction "1D1_47") (pintype "input"))
      (node (ref "IC56") (pin "23") (pinfunction "2Q8_23") (pintype "tri_state"))
      (node (ref "IC60") (pin "12") (pinfunction "I0_12") (pintype "input"))
    )
    (net (code "262") (name "Net-(IC41A-1D2)") (class "Default")
      (node (ref "IC41") (pin "2") (pinfunction "1Q1_2") (pintype "tri_state"))
      (node (ref "IC41") (pin "46") (pinfunction "1D2_46") (pintype "input"))
      (node (ref "IC42") (pin "1") (pinfunction "I0_1") (pintype "input"))
    )
    (net (code "263") (name "Net-(IC41A-1D3)") (class "Default")
      (node (ref "IC41") (pin "3") (pinfunction "1Q2_3") (pintype "tri_state"))
      (node (ref "IC41") (pin "44") (pinfunction "1D3_44") (pintype "input"))
      (node (ref "IC42") (pin "4") (pinfunction "I0_4") (pintype "input"))
    )
    (net (code "264") (name "Net-(IC41A-1D4)") (class "Default")
      (node (ref "IC41") (pin "43") (pinfunction "1D4_43") (pintype "input"))
      (node (ref "IC41") (pin "5") (pinfunction "1Q3_5") (pintype "tri_state"))
      (node (ref "IC42") (pin "9") (pinfunction "I0_9") (pintype "input"))
    )
    (net (code "265") (name "Net-(IC41A-1D5)") (class "Default")
      (node (ref "IC41") (pin "41") (pinfunction "1D5_41") (pintype "input"))
      (node (ref "IC41") (pin "6") (pinfunction "1Q4_6") (pintype "tri_state"))
      (node (ref "IC42") (pin "12") (pinfunction "I0_12") (pintype "input"))
    )
    (net (code "266") (name "Net-(IC41A-1D6)") (class "Default")
      (node (ref "IC41") (pin "40") (pinfunction "1D6_40") (pintype "input"))
      (node (ref "IC41") (pin "8") (pinfunction "1Q5_8") (pintype "tri_state"))
      (node (ref "IC43") (pin "1") (pinfunction "I0_1") (pintype "input"))
    )
    (net (code "267") (name "Net-(IC41A-1D7)") (class "Default")
      (node (ref "IC41") (pin "38") (pinfunction "1D7_38") (pintype "input"))
      (node (ref "IC41") (pin "9") (pinfunction "1Q6_9") (pintype "tri_state"))
      (node (ref "IC43") (pin "4") (pinfunction "I0_4") (pintype "input"))
    )
    (net (code "268") (name "Net-(IC41A-1D8)") (class "Default")
      (node (ref "IC41") (pin "11") (pinfunction "1Q7_11") (pintype "tri_state"))
      (node (ref "IC41") (pin "37") (pinfunction "1D8_37") (pintype "input"))
      (node (ref "IC43") (pin "9") (pinfunction "I0_9") (pintype "input"))
    )
    (net (code "269") (name "Net-(IC41A-1Q8)") (class "Default")
      (node (ref "IC41") (pin "12") (pinfunction "1Q8_12") (pintype "tri_state"))
      (node (ref "IC41") (pin "36") (pinfunction "2D1_36") (pintype "input"))
      (node (ref "IC43") (pin "12") (pinfunction "I0_12") (pintype "input"))
    )
    (net (code "270") (name "Net-(IC41A-2D2)") (class "Default")
      (node (ref "IC41") (pin "13") (pinfunction "2Q1_13") (pintype "tri_state"))
      (node (ref "IC41") (pin "35") (pinfunction "2D2_35") (pintype "input"))
      (node (ref "IC44") (pin "1") (pinfunction "I0_1") (pintype "input"))
    )
    (net (code "271") (name "Net-(IC41A-2D3)") (class "Default")
      (node (ref "IC41") (pin "14") (pinfunction "2Q2_14") (pintype "tri_state"))
      (node (ref "IC41") (pin "33") (pinfunction "2D3_33") (pintype "input"))
      (node (ref "IC44") (pin "4") (pinfunction "I0_4") (pintype "input"))
    )
    (net (code "272") (name "Net-(IC41A-2D4)") (class "Default")
      (node (ref "IC41") (pin "16") (pinfunction "2Q3_16") (pintype "tri_state"))
      (node (ref "IC41") (pin "32") (pinfunction "2D4_32") (pintype "input"))
      (node (ref "IC44") (pin "9") (pinfunction "I0_9") (pintype "input"))
    )
    (net (code "273") (name "Net-(IC41A-2D5)") (class "Default")
      (node (ref "IC41") (pin "17") (pinfunction "2Q4_17") (pintype "tri_state"))
      (node (ref "IC41") (pin "30") (pinfunction "2D5_30") (pintype "input"))
      (node (ref "IC44") (pin "12") (pinfunction "I0_12") (pintype "input"))
    )
    (net (code "274") (name "Net-(IC41A-2D6)") (class "Default")
      (node (ref "IC41") (pin "19") (pinfunction "2Q5_19") (pintype "tri_state"))
      (node (ref "IC41") (pin "29") (pinfunction "2D6_29") (pintype "input"))
      (node (ref "IC45") (pin "1") (pinfunction "I0_1") (pintype "input"))
    )
    (net (code "275") (name "Net-(IC41A-2D7)") (class "Default")
      (node (ref "IC41") (pin "20") (pinfunction "2Q6_20") (pintype "tri_state"))
      (node (ref "IC41") (pin "27") (pinfunction "2D7_27") (pintype "input"))
      (node (ref "IC45") (pin "4") (pinfunction "I0_4") (pintype "input"))
    )
    (net (code "276") (name "Net-(IC41A-2D8)") (class "Default")
      (node (ref "IC41") (pin "22") (pinfunction "2Q7_22") (pintype "tri_state"))
      (node (ref "IC41") (pin "26") (pinfunction "2D8_26") (pintype "input"))
      (node (ref "IC45") (pin "9") (pinfunction "I0_9") (pintype "input"))
    )
    (net (code "277") (name "Net-(IC41A-2Q8)") (class "Default")
      (node (ref "IC41") (pin "23") (pinfunction "2Q8_23") (pintype "tri_state"))
      (node (ref "IC45") (pin "12") (pinfunction "I0_12") (pintype "input"))
      (node (ref "IC46") (pin "47") (pinfunction "1D1_47") (pintype "input"))
    )
    (net (code "278") (name "Net-(IC42A-O)") (class "Default")
      (node (ref "IC42") (pin "3") (pinfunction "O_3") (pintype "output"))
      (node (ref "U$17") (pin "1") (pinfunction "I1_1") (pintype "input"))
    )
    (net (code "279") (name "Net-(IC42B-O)") (class "Default")
      (node (ref "IC42") (pin "6") (pinfunction "O_6") (pintype "output"))
      (node (ref "U$17") (pin "2") (pinfunction "I2_2") (pintype "input"))
    )
    (net (code "280") (name "Net-(IC42C-O)") (class "Default")
      (node (ref "IC42") (pin "8") (pinfunction "O_8") (pintype "output"))
      (node (ref "U$17") (pin "3") (pinfunction "I3_3") (pintype "input"))
    )
    (net (code "281") (name "Net-(IC42D-O)") (class "Default")
      (node (ref "IC42") (pin "11") (pinfunction "O_11") (pintype "output"))
      (node (ref "U$17") (pin "4") (pinfunction "I4_4") (pintype "input"))
    )
    (net (code "282") (name "Net-(IC43A-O)") (class "Default")
      (node (ref "IC43") (pin "3") (pinfunction "O_3") (pintype "output"))
      (node (ref "U$17") (pin "5") (pinfunction "I5_5") (pintype "input"))
    )
    (net (code "283") (name "Net-(IC43B-O)") (class "Default")
      (node (ref "IC43") (pin "6") (pinfunction "O_6") (pintype "output"))
      (node (ref "U$17") (pin "6") (pinfunction "I6_6") (pintype "input"))
    )
    (net (code "284") (name "Net-(IC43C-O)") (class "Default")
      (node (ref "IC43") (pin "8") (pinfunction "O_8") (pintype "output"))
      (node (ref "U$17") (pin "7") (pinfunction "I7_7") (pintype "input"))
    )
    (net (code "285") (name "Net-(IC43D-O)") (class "Default")
      (node (ref "IC43") (pin "11") (pinfunction "O_11") (pintype "output"))
      (node (ref "U$17") (pin "8") (pinfunction "I8_8") (pintype "input"))
    )
    (net (code "286") (name "Net-(IC44A-O)") (class "Default")
      (node (ref "IC44") (pin "3") (pinfunction "O_3") (pintype "output"))
      (node (ref "U$18") (pin "1") (pinfunction "I1_1") (pintype "input"))
    )
    (net (code "287") (name "Net-(IC44B-O)") (class "Default")
      (node (ref "IC44") (pin "6") (pinfunction "O_6") (pintype "output"))
      (node (ref "U$18") (pin "2") (pinfunction "I2_2") (pintype "input"))
    )
    (net (code "288") (name "Net-(IC44C-O)") (class "Default")
      (node (ref "IC44") (pin "8") (pinfunction "O_8") (pintype "output"))
      (node (ref "U$18") (pin "3") (pinfunction "I3_3") (pintype "input"))
    )
    (net (code "289") (name "Net-(IC44D-O)") (class "Default")
      (node (ref "IC44") (pin "11") (pinfunction "O_11") (pintype "output"))
      (node (ref "U$18") (pin "4") (pinfunction "I4_4") (pintype "input"))
    )
    (net (code "290") (name "Net-(IC45A-O)") (class "Default")
      (node (ref "IC45") (pin "3") (pinfunction "O_3") (pintype "output"))
      (node (ref "U$18") (pin "5") (pinfunction "I5_5") (pintype "input"))
    )
    (net (code "291") (name "Net-(IC45B-O)") (class "Default")
      (node (ref "IC45") (pin "6") (pinfunction "O_6") (pintype "output"))
      (node (ref "U$18") (pin "6") (pinfunction "I6_6") (pintype "input"))
    )
    (net (code "292") (name "Net-(IC45C-O)") (class "Default")
      (node (ref "IC45") (pin "8") (pinfunction "O_8") (pintype "output"))
      (node (ref "U$18") (pin "7") (pinfunction "I7_7") (pintype "input"))
    )
    (net (code "293") (name "Net-(IC45D-O)") (class "Default")
      (node (ref "IC45") (pin "11") (pinfunction "O_11") (pintype "output"))
      (node (ref "U$18") (pin "8") (pinfunction "I8_8") (pintype "input"))
    )
    (net (code "294") (name "Net-(IC46A-1D2)") (class "Default")
      (node (ref "IC46") (pin "2") (pinfunction "1Q1_2") (pintype "tri_state"))
      (node (ref "IC46") (pin "46") (pinfunction "1D2_46") (pintype "input"))
      (node (ref "IC47") (pin "1") (pinfunction "I0_1") (pintype "input"))
    )
    (net (code "295") (name "Net-(IC46A-1D3)") (class "Default")
      (node (ref "IC46") (pin "3") (pinfunction "1Q2_3") (pintype "tri_state"))
      (node (ref "IC46") (pin "44") (pinfunction "1D3_44") (pintype "input"))
      (node (ref "IC47") (pin "4") (pinfunction "I0_4") (pintype "input"))
    )
    (net (code "296") (name "Net-(IC46A-1D4)") (class "Default")
      (node (ref "IC46") (pin "43") (pinfunction "1D4_43") (pintype "input"))
      (node (ref "IC46") (pin "5") (pinfunction "1Q3_5") (pintype "tri_state"))
      (node (ref "IC47") (pin "9") (pinfunction "I0_9") (pintype "input"))
    )
    (net (code "297") (name "Net-(IC46A-1D5)") (class "Default")
      (node (ref "IC46") (pin "41") (pinfunction "1D5_41") (pintype "input"))
      (node (ref "IC46") (pin "6") (pinfunction "1Q4_6") (pintype "tri_state"))
      (node (ref "IC47") (pin "12") (pinfunction "I0_12") (pintype "input"))
    )
    (net (code "298") (name "Net-(IC46A-1D6)") (class "Default")
      (node (ref "IC46") (pin "40") (pinfunction "1D6_40") (pintype "input"))
      (node (ref "IC46") (pin "8") (pinfunction "1Q5_8") (pintype "tri_state"))
      (node (ref "IC48") (pin "1") (pinfunction "I0_1") (pintype "input"))
    )
    (net (code "299") (name "Net-(IC46A-1D7)") (class "Default")
      (node (ref "IC46") (pin "38") (pinfunction "1D7_38") (pintype "input"))
      (node (ref "IC46") (pin "9") (pinfunction "1Q6_9") (pintype "tri_state"))
      (node (ref "IC48") (pin "4") (pinfunction "I0_4") (pintype "input"))
    )
    (net (code "300") (name "Net-(IC46A-1D8)") (class "Default")
      (node (ref "IC46") (pin "11") (pinfunction "1Q7_11") (pintype "tri_state"))
      (node (ref "IC46") (pin "37") (pinfunction "1D8_37") (pintype "input"))
      (node (ref "IC48") (pin "9") (pinfunction "I0_9") (pintype "input"))
    )
    (net (code "301") (name "Net-(IC46A-1Q8)") (class "Default")
      (node (ref "IC46") (pin "12") (pinfunction "1Q8_12") (pintype "tri_state"))
      (node (ref "IC46") (pin "36") (pinfunction "2D1_36") (pintype "input"))
      (node (ref "IC48") (pin "12") (pinfunction "I0_12") (pintype "input"))
    )
    (net (code "302") (name "Net-(IC46A-2D2)") (class "Default")
      (node (ref "IC46") (pin "13") (pinfunction "2Q1_13") (pintype "tri_state"))
      (node (ref "IC46") (pin "35") (pinfunction "2D2_35") (pintype "input"))
      (node (ref "IC49") (pin "1") (pinfunction "I0_1") (pintype "input"))
    )
    (net (code "303") (name "Net-(IC46A-2D3)") (class "Default")
      (node (ref "IC46") (pin "14") (pinfunction "2Q2_14") (pintype "tri_state"))
      (node (ref "IC46") (pin "33") (pinfunction "2D3_33") (pintype "input"))
      (node (ref "IC49") (pin "4") (pinfunction "I0_4") (pintype "input"))
    )
    (net (code "304") (name "Net-(IC46A-2D4)") (class "Default")
      (node (ref "IC46") (pin "16") (pinfunction "2Q3_16") (pintype "tri_state"))
      (node (ref "IC46") (pin "32") (pinfunction "2D4_32") (pintype "input"))
      (node (ref "IC49") (pin "9") (pinfunction "I0_9") (pintype "input"))
    )
    (net (code "305") (name "Net-(IC46A-2D5)") (class "Default")
      (node (ref "IC46") (pin "17") (pinfunction "2Q4_17") (pintype "tri_state"))
      (node (ref "IC46") (pin "30") (pinfunction "2D5_30") (pintype "input"))
      (node (ref "IC49") (pin "12") (pinfunction "I0_12") (pintype "input"))
    )
    (net (code "306") (name "Net-(IC46A-2D6)") (class "Default")
      (node (ref "IC46") (pin "19") (pinfunction "2Q5_19") (pintype "tri_state"))
      (node (ref "IC46") (pin "29") (pinfunction "2D6_29") (pintype "input"))
      (node (ref "IC50") (pin "1") (pinfunction "I0_1") (pintype "input"))
    )
    (net (code "307") (name "Net-(IC46A-2D7)") (class "Default")
      (node (ref "IC46") (pin "20") (pinfunction "2Q6_20") (pintype "tri_state"))
      (node (ref "IC46") (pin "27") (pinfunction "2D7_27") (pintype "input"))
      (node (ref "IC50") (pin "4") (pinfunction "I0_4") (pintype "input"))
    )
    (net (code "308") (name "Net-(IC46A-2D8)") (class "Default")
      (node (ref "IC46") (pin "22") (pinfunction "2Q7_22") (pintype "tri_state"))
      (node (ref "IC46") (pin "26") (pinfunction "2D8_26") (pintype "input"))
      (node (ref "IC50") (pin "9") (pinfunction "I0_9") (pintype "input"))
    )
    (net (code "309") (name "Net-(IC46A-2Q8)") (class "Default")
      (node (ref "IC46") (pin "23") (pinfunction "2Q8_23") (pintype "tri_state"))
      (node (ref "IC50") (pin "12") (pinfunction "I0_12") (pintype "input"))
      (node (ref "IC91") (pin "47") (pinfunction "1D1_47") (pintype "input"))
    )
    (net (code "310") (name "Net-(IC47A-O)") (class "Default")
      (node (ref "IC47") (pin "3") (pinfunction "O_3") (pintype "output"))
      (node (ref "U$19") (pin "1") (pinfunction "I1_1") (pintype "input"))
    )
    (net (code "311") (name "Net-(IC47B-O)") (class "Default")
      (node (ref "IC47") (pin "6") (pinfunction "O_6") (pintype "output"))
      (node (ref "U$19") (pin "2") (pinfunction "I2_2") (pintype "input"))
    )
    (net (code "312") (name "Net-(IC47C-O)") (class "Default")
      (node (ref "IC47") (pin "8") (pinfunction "O_8") (pintype "output"))
      (node (ref "U$19") (pin "3") (pinfunction "I3_3") (pintype "input"))
    )
    (net (code "313") (name "Net-(IC47D-O)") (class "Default")
      (node (ref "IC47") (pin "11") (pinfunction "O_11") (pintype "output"))
      (node (ref "U$19") (pin "4") (pinfunction "I4_4") (pintype "input"))
    )
    (net (code "314") (name "Net-(IC48A-O)") (class "Default")
      (node (ref "IC48") (pin "3") (pinfunction "O_3") (pintype "output"))
      (node (ref "U$19") (pin "5") (pinfunction "I5_5") (pintype "input"))
    )
    (net (code "315") (name "Net-(IC48B-O)") (class "Default")
      (node (ref "IC48") (pin "6") (pinfunction "O_6") (pintype "output"))
      (node (ref "U$19") (pin "6") (pinfunction "I6_6") (pintype "input"))
    )
    (net (code "316") (name "Net-(IC48C-O)") (class "Default")
      (node (ref "IC48") (pin "8") (pinfunction "O_8") (pintype "output"))
      (node (ref "U$19") (pin "7") (pinfunction "I7_7") (pintype "input"))
    )
    (net (code "317") (name "Net-(IC48D-O)") (class "Default")
      (node (ref "IC48") (pin "11") (pinfunction "O_11") (pintype "output"))
      (node (ref "U$19") (pin "8") (pinfunction "I8_8") (pintype "input"))
    )
    (net (code "318") (name "Net-(IC49A-O)") (class "Default")
      (node (ref "IC49") (pin "3") (pinfunction "O_3") (pintype "output"))
      (node (ref "U$20") (pin "1") (pinfunction "I1_1") (pintype "input"))
    )
    (net (code "319") (name "Net-(IC49B-O)") (class "Default")
      (node (ref "IC49") (pin "6") (pinfunction "O_6") (pintype "output"))
      (node (ref "U$20") (pin "2") (pinfunction "I2_2") (pintype "input"))
    )
    (net (code "320") (name "Net-(IC49C-O)") (class "Default")
      (node (ref "IC49") (pin "8") (pinfunction "O_8") (pintype "output"))
      (node (ref "U$20") (pin "3") (pinfunction "I3_3") (pintype "input"))
    )
    (net (code "321") (name "Net-(IC49D-O)") (class "Default")
      (node (ref "IC49") (pin "11") (pinfunction "O_11") (pintype "output"))
      (node (ref "U$20") (pin "4") (pinfunction "I4_4") (pintype "input"))
    )
    (net (code "322") (name "Net-(IC50A-O)") (class "Default")
      (node (ref "IC50") (pin "3") (pinfunction "O_3") (pintype "output"))
      (node (ref "U$20") (pin "5") (pinfunction "I5_5") (pintype "input"))
    )
    (net (code "323") (name "Net-(IC50B-O)") (class "Default")
      (node (ref "IC50") (pin "6") (pinfunction "O_6") (pintype "output"))
      (node (ref "U$20") (pin "6") (pinfunction "I6_6") (pintype "input"))
    )
    (net (code "324") (name "Net-(IC50C-O)") (class "Default")
      (node (ref "IC50") (pin "8") (pinfunction "O_8") (pintype "output"))
      (node (ref "U$20") (pin "7") (pinfunction "I7_7") (pintype "input"))
    )
    (net (code "325") (name "Net-(IC50D-O)") (class "Default")
      (node (ref "IC50") (pin "11") (pinfunction "O_11") (pintype "output"))
      (node (ref "U$20") (pin "8") (pinfunction "I8_8") (pintype "input"))
    )
    (net (code "326") (name "Net-(IC51A-1D2)") (class "Default")
      (node (ref "IC51") (pin "2") (pinfunction "1Q1_2") (pintype "tri_state"))
      (node (ref "IC51") (pin "46") (pinfunction "1D2_46") (pintype "input"))
      (node (ref "IC52") (pin "1") (pinfunction "I0_1") (pintype "input"))
    )
    (net (code "327") (name "Net-(IC51A-1D3)") (class "Default")
      (node (ref "IC51") (pin "3") (pinfunction "1Q2_3") (pintype "tri_state"))
      (node (ref "IC51") (pin "44") (pinfunction "1D3_44") (pintype "input"))
      (node (ref "IC52") (pin "4") (pinfunction "I0_4") (pintype "input"))
    )
    (net (code "328") (name "Net-(IC51A-1D4)") (class "Default")
      (node (ref "IC51") (pin "43") (pinfunction "1D4_43") (pintype "input"))
      (node (ref "IC51") (pin "5") (pinfunction "1Q3_5") (pintype "tri_state"))
      (node (ref "IC52") (pin "9") (pinfunction "I0_9") (pintype "input"))
    )
    (net (code "329") (name "Net-(IC51A-1D5)") (class "Default")
      (node (ref "IC51") (pin "41") (pinfunction "1D5_41") (pintype "input"))
      (node (ref "IC51") (pin "6") (pinfunction "1Q4_6") (pintype "tri_state"))
      (node (ref "IC52") (pin "12") (pinfunction "I0_12") (pintype "input"))
    )
    (net (code "330") (name "Net-(IC51A-1D6)") (class "Default")
      (node (ref "IC51") (pin "40") (pinfunction "1D6_40") (pintype "input"))
      (node (ref "IC51") (pin "8") (pinfunction "1Q5_8") (pintype "tri_state"))
      (node (ref "IC53") (pin "1") (pinfunction "I0_1") (pintype "input"))
    )
    (net (code "331") (name "Net-(IC51A-1D7)") (class "Default")
      (node (ref "IC51") (pin "38") (pinfunction "1D7_38") (pintype "input"))
      (node (ref "IC51") (pin "9") (pinfunction "1Q6_9") (pintype "tri_state"))
      (node (ref "IC53") (pin "4") (pinfunction "I0_4") (pintype "input"))
    )
    (net (code "332") (name "Net-(IC51A-1D8)") (class "Default")
      (node (ref "IC51") (pin "11") (pinfunction "1Q7_11") (pintype "tri_state"))
      (node (ref "IC51") (pin "37") (pinfunction "1D8_37") (pintype "input"))
      (node (ref "IC53") (pin "9") (pinfunction "I0_9") (pintype "input"))
    )
    (net (code "333") (name "Net-(IC51A-1Q8)") (class "Default")
      (node (ref "IC51") (pin "12") (pinfunction "1Q8_12") (pintype "tri_state"))
      (node (ref "IC51") (pin "36") (pinfunction "2D1_36") (pintype "input"))
      (node (ref "IC53") (pin "12") (pinfunction "I0_12") (pintype "input"))
    )
    (net (code "334") (name "Net-(IC51A-2D2)") (class "Default")
      (node (ref "IC51") (pin "13") (pinfunction "2Q1_13") (pintype "tri_state"))
      (node (ref "IC51") (pin "35") (pinfunction "2D2_35") (pintype "input"))
      (node (ref "IC54") (pin "1") (pinfunction "I0_1") (pintype "input"))
    )
    (net (code "335") (name "Net-(IC51A-2D3)") (class "Default")
      (node (ref "IC51") (pin "14") (pinfunction "2Q2_14") (pintype "tri_state"))
      (node (ref "IC51") (pin "33") (pinfunction "2D3_33") (pintype "input"))
      (node (ref "IC54") (pin "4") (pinfunction "I0_4") (pintype "input"))
    )
    (net (code "336") (name "Net-(IC51A-2D4)") (class "Default")
      (node (ref "IC51") (pin "16") (pinfunction "2Q3_16") (pintype "tri_state"))
      (node (ref "IC51") (pin "32") (pinfunction "2D4_32") (pintype "input"))
      (node (ref "IC54") (pin "9") (pinfunction "I0_9") (pintype "input"))
    )
    (net (code "337") (name "Net-(IC51A-2D5)") (class "Default")
      (node (ref "IC51") (pin "17") (pinfunction "2Q4_17") (pintype "tri_state"))
      (node (ref "IC51") (pin "30") (pinfunction "2D5_30") (pintype "input"))
      (node (ref "IC54") (pin "12") (pinfunction "I0_12") (pintype "input"))
    )
    (net (code "338") (name "Net-(IC51A-2D6)") (class "Default")
      (node (ref "IC51") (pin "19") (pinfunction "2Q5_19") (pintype "tri_state"))
      (node (ref "IC51") (pin "29") (pinfunction "2D6_29") (pintype "input"))
      (node (ref "IC55") (pin "1") (pinfunction "I0_1") (pintype "input"))
    )
    (net (code "339") (name "Net-(IC51A-2D7)") (class "Default")
      (node (ref "IC51") (pin "20") (pinfunction "2Q6_20") (pintype "tri_state"))
      (node (ref "IC51") (pin "27") (pinfunction "2D7_27") (pintype "input"))
      (node (ref "IC55") (pin "4") (pinfunction "I0_4") (pintype "input"))
    )
    (net (code "340") (name "Net-(IC51A-2D8)") (class "Default")
      (node (ref "IC51") (pin "22") (pinfunction "2Q7_22") (pintype "tri_state"))
      (node (ref "IC51") (pin "26") (pinfunction "2D8_26") (pintype "input"))
      (node (ref "IC55") (pin "9") (pinfunction "I0_9") (pintype "input"))
    )
    (net (code "341") (name "Net-(IC51A-2Q8)") (class "Default")
      (node (ref "IC51") (pin "23") (pinfunction "2Q8_23") (pintype "tri_state"))
      (node (ref "IC55") (pin "12") (pinfunction "I0_12") (pintype "input"))
      (node (ref "IC56") (pin "47") (pinfunction "1D1_47") (pintype "input"))
    )
    (net (code "342") (name "Net-(IC52A-O)") (class "Default")
      (node (ref "IC52") (pin "3") (pinfunction "O_3") (pintype "output"))
      (node (ref "U$21") (pin "1") (pinfunction "I1_1") (pintype "input"))
    )
    (net (code "343") (name "Net-(IC52B-O)") (class "Default")
      (node (ref "IC52") (pin "6") (pinfunction "O_6") (pintype "output"))
      (node (ref "U$21") (pin "2") (pinfunction "I2_2") (pintype "input"))
    )
    (net (code "344") (name "Net-(IC52C-O)") (class "Default")
      (node (ref "IC52") (pin "8") (pinfunction "O_8") (pintype "output"))
      (node (ref "U$21") (pin "3") (pinfunction "I3_3") (pintype "input"))
    )
    (net (code "345") (name "Net-(IC52D-O)") (class "Default")
      (node (ref "IC52") (pin "11") (pinfunction "O_11") (pintype "output"))
      (node (ref "U$21") (pin "4") (pinfunction "I4_4") (pintype "input"))
    )
    (net (code "346") (name "Net-(IC53A-O)") (class "Default")
      (node (ref "IC53") (pin "3") (pinfunction "O_3") (pintype "output"))
      (node (ref "U$21") (pin "5") (pinfunction "I5_5") (pintype "input"))
    )
    (net (code "347") (name "Net-(IC53B-O)") (class "Default")
      (node (ref "IC53") (pin "6") (pinfunction "O_6") (pintype "output"))
      (node (ref "U$21") (pin "6") (pinfunction "I6_6") (pintype "input"))
    )
    (net (code "348") (name "Net-(IC53C-O)") (class "Default")
      (node (ref "IC53") (pin "8") (pinfunction "O_8") (pintype "output"))
      (node (ref "U$21") (pin "7") (pinfunction "I7_7") (pintype "input"))
    )
    (net (code "349") (name "Net-(IC53D-O)") (class "Default")
      (node (ref "IC53") (pin "11") (pinfunction "O_11") (pintype "output"))
      (node (ref "U$21") (pin "8") (pinfunction "I8_8") (pintype "input"))
    )
    (net (code "350") (name "Net-(IC54A-O)") (class "Default")
      (node (ref "IC54") (pin "3") (pinfunction "O_3") (pintype "output"))
      (node (ref "U$22") (pin "1") (pinfunction "I1_1") (pintype "input"))
    )
    (net (code "351") (name "Net-(IC54B-O)") (class "Default")
      (node (ref "IC54") (pin "6") (pinfunction "O_6") (pintype "output"))
      (node (ref "U$22") (pin "2") (pinfunction "I2_2") (pintype "input"))
    )
    (net (code "352") (name "Net-(IC54C-O)") (class "Default")
      (node (ref "IC54") (pin "8") (pinfunction "O_8") (pintype "output"))
      (node (ref "U$22") (pin "3") (pinfunction "I3_3") (pintype "input"))
    )
    (net (code "353") (name "Net-(IC54D-O)") (class "Default")
      (node (ref "IC54") (pin "11") (pinfunction "O_11") (pintype "output"))
      (node (ref "U$22") (pin "4") (pinfunction "I4_4") (pintype "input"))
    )
    (net (code "354") (name "Net-(IC55A-O)") (class "Default")
      (node (ref "IC55") (pin "3") (pinfunction "O_3") (pintype "output"))
      (node (ref "U$22") (pin "5") (pinfunction "I5_5") (pintype "input"))
    )
    (net (code "355") (name "Net-(IC55B-O)") (class "Default")
      (node (ref "IC55") (pin "6") (pinfunction "O_6") (pintype "output"))
      (node (ref "U$22") (pin "6") (pinfunction "I6_6") (pintype "input"))
    )
    (net (code "356") (name "Net-(IC55C-O)") (class "Default")
      (node (ref "IC55") (pin "8") (pinfunction "O_8") (pintype "output"))
      (node (ref "U$22") (pin "7") (pinfunction "I7_7") (pintype "input"))
    )
    (net (code "357") (name "Net-(IC55D-O)") (class "Default")
      (node (ref "IC55") (pin "11") (pinfunction "O_11") (pintype "output"))
      (node (ref "U$22") (pin "8") (pinfunction "I8_8") (pintype "input"))
    )
    (net (code "358") (name "Net-(IC56A-1D2)") (class "Default")
      (node (ref "IC56") (pin "2") (pinfunction "1Q1_2") (pintype "tri_state"))
      (node (ref "IC56") (pin "46") (pinfunction "1D2_46") (pintype "input"))
      (node (ref "IC57") (pin "1") (pinfunction "I0_1") (pintype "input"))
    )
    (net (code "359") (name "Net-(IC56A-1D3)") (class "Default")
      (node (ref "IC56") (pin "3") (pinfunction "1Q2_3") (pintype "tri_state"))
      (node (ref "IC56") (pin "44") (pinfunction "1D3_44") (pintype "input"))
      (node (ref "IC57") (pin "4") (pinfunction "I0_4") (pintype "input"))
    )
    (net (code "360") (name "Net-(IC56A-1D4)") (class "Default")
      (node (ref "IC56") (pin "43") (pinfunction "1D4_43") (pintype "input"))
      (node (ref "IC56") (pin "5") (pinfunction "1Q3_5") (pintype "tri_state"))
      (node (ref "IC57") (pin "9") (pinfunction "I0_9") (pintype "input"))
    )
    (net (code "361") (name "Net-(IC56A-1D5)") (class "Default")
      (node (ref "IC56") (pin "41") (pinfunction "1D5_41") (pintype "input"))
      (node (ref "IC56") (pin "6") (pinfunction "1Q4_6") (pintype "tri_state"))
      (node (ref "IC57") (pin "12") (pinfunction "I0_12") (pintype "input"))
    )
    (net (code "362") (name "Net-(IC56A-1D6)") (class "Default")
      (node (ref "IC56") (pin "40") (pinfunction "1D6_40") (pintype "input"))
      (node (ref "IC56") (pin "8") (pinfunction "1Q5_8") (pintype "tri_state"))
      (node (ref "IC58") (pin "1") (pinfunction "I0_1") (pintype "input"))
    )
    (net (code "363") (name "Net-(IC56A-1D7)") (class "Default")
      (node (ref "IC56") (pin "38") (pinfunction "1D7_38") (pintype "input"))
      (node (ref "IC56") (pin "9") (pinfunction "1Q6_9") (pintype "tri_state"))
      (node (ref "IC58") (pin "4") (pinfunction "I0_4") (pintype "input"))
    )
    (net (code "364") (name "Net-(IC56A-1D8)") (class "Default")
      (node (ref "IC56") (pin "11") (pinfunction "1Q7_11") (pintype "tri_state"))
      (node (ref "IC56") (pin "37") (pinfunction "1D8_37") (pintype "input"))
      (node (ref "IC58") (pin "9") (pinfunction "I0_9") (pintype "input"))
    )
    (net (code "365") (name "Net-(IC56A-1Q8)") (class "Default")
      (node (ref "IC56") (pin "12") (pinfunction "1Q8_12") (pintype "tri_state"))
      (node (ref "IC56") (pin "36") (pinfunction "2D1_36") (pintype "input"))
      (node (ref "IC58") (pin "12") (pinfunction "I0_12") (pintype "input"))
    )
    (net (code "366") (name "Net-(IC56A-2D2)") (class "Default")
      (node (ref "IC56") (pin "13") (pinfunction "2Q1_13") (pintype "tri_state"))
      (node (ref "IC56") (pin "35") (pinfunction "2D2_35") (pintype "input"))
      (node (ref "IC59") (pin "1") (pinfunction "I0_1") (pintype "input"))
    )
    (net (code "367") (name "Net-(IC56A-2D3)") (class "Default")
      (node (ref "IC56") (pin "14") (pinfunction "2Q2_14") (pintype "tri_state"))
      (node (ref "IC56") (pin "33") (pinfunction "2D3_33") (pintype "input"))
      (node (ref "IC59") (pin "4") (pinfunction "I0_4") (pintype "input"))
    )
    (net (code "368") (name "Net-(IC56A-2D4)") (class "Default")
      (node (ref "IC56") (pin "16") (pinfunction "2Q3_16") (pintype "tri_state"))
      (node (ref "IC56") (pin "32") (pinfunction "2D4_32") (pintype "input"))
      (node (ref "IC59") (pin "9") (pinfunction "I0_9") (pintype "input"))
    )
    (net (code "369") (name "Net-(IC56A-2D5)") (class "Default")
      (node (ref "IC56") (pin "17") (pinfunction "2Q4_17") (pintype "tri_state"))
      (node (ref "IC56") (pin "30") (pinfunction "2D5_30") (pintype "input"))
      (node (ref "IC59") (pin "12") (pinfunction "I0_12") (pintype "input"))
    )
    (net (code "370") (name "Net-(IC56A-2D6)") (class "Default")
      (node (ref "IC56") (pin "19") (pinfunction "2Q5_19") (pintype "tri_state"))
      (node (ref "IC56") (pin "29") (pinfunction "2D6_29") (pintype "input"))
      (node (ref "IC60") (pin "1") (pinfunction "I0_1") (pintype "input"))
    )
    (net (code "371") (name "Net-(IC56A-2D7)") (class "Default")
      (node (ref "IC56") (pin "20") (pinfunction "2Q6_20") (pintype "tri_state"))
      (node (ref "IC56") (pin "27") (pinfunction "2D7_27") (pintype "input"))
      (node (ref "IC60") (pin "4") (pinfunction "I0_4") (pintype "input"))
    )
    (net (code "372") (name "Net-(IC56A-2D8)") (class "Default")
      (node (ref "IC56") (pin "22") (pinfunction "2Q7_22") (pintype "tri_state"))
      (node (ref "IC56") (pin "26") (pinfunction "2D8_26") (pintype "input"))
      (node (ref "IC60") (pin "9") (pinfunction "I0_9") (pintype "input"))
    )
    (net (code "373") (name "Net-(IC57A-O)") (class "Default")
      (node (ref "IC57") (pin "3") (pinfunction "O_3") (pintype "output"))
      (node (ref "U$23") (pin "1") (pinfunction "I1_1") (pintype "input"))
    )
    (net (code "374") (name "Net-(IC57B-O)") (class "Default")
      (node (ref "IC57") (pin "6") (pinfunction "O_6") (pintype "output"))
      (node (ref "U$23") (pin "2") (pinfunction "I2_2") (pintype "input"))
    )
    (net (code "375") (name "Net-(IC57C-O)") (class "Default")
      (node (ref "IC57") (pin "8") (pinfunction "O_8") (pintype "output"))
      (node (ref "U$23") (pin "3") (pinfunction "I3_3") (pintype "input"))
    )
    (net (code "376") (name "Net-(IC57D-O)") (class "Default")
      (node (ref "IC57") (pin "11") (pinfunction "O_11") (pintype "output"))
      (node (ref "U$23") (pin "4") (pinfunction "I4_4") (pintype "input"))
    )
    (net (code "377") (name "Net-(IC58A-O)") (class "Default")
      (node (ref "IC58") (pin "3") (pinfunction "O_3") (pintype "output"))
      (node (ref "U$23") (pin "5") (pinfunction "I5_5") (pintype "input"))
    )
    (net (code "378") (name "Net-(IC58B-O)") (class "Default")
      (node (ref "IC58") (pin "6") (pinfunction "O_6") (pintype "output"))
      (node (ref "U$23") (pin "6") (pinfunction "I6_6") (pintype "input"))
    )
    (net (code "379") (name "Net-(IC58C-O)") (class "Default")
      (node (ref "IC58") (pin "8") (pinfunction "O_8") (pintype "output"))
      (node (ref "U$23") (pin "7") (pinfunction "I7_7") (pintype "input"))
    )
    (net (code "380") (name "Net-(IC58D-O)") (class "Default")
      (node (ref "IC58") (pin "11") (pinfunction "O_11") (pintype "output"))
      (node (ref "U$23") (pin "8") (pinfunction "I8_8") (pintype "input"))
    )
    (net (code "381") (name "Net-(IC59A-O)") (class "Default")
      (node (ref "IC59") (pin "3") (pinfunction "O_3") (pintype "output"))
      (node (ref "U$24") (pin "1") (pinfunction "I1_1") (pintype "input"))
    )
    (net (code "382") (name "Net-(IC59B-O)") (class "Default")
      (node (ref "IC59") (pin "6") (pinfunction "O_6") (pintype "output"))
      (node (ref "U$24") (pin "2") (pinfunction "I2_2") (pintype "input"))
    )
    (net (code "383") (name "Net-(IC59C-O)") (class "Default")
      (node (ref "IC59") (pin "8") (pinfunction "O_8") (pintype "output"))
      (node (ref "U$24") (pin "3") (pinfunction "I3_3") (pintype "input"))
    )
    (net (code "384") (name "Net-(IC59D-O)") (class "Default")
      (node (ref "IC59") (pin "11") (pinfunction "O_11") (pintype "output"))
      (node (ref "U$24") (pin "4") (pinfunction "I4_4") (pintype "input"))
    )
    (net (code "385") (name "Net-(IC60A-O)") (class "Default")
      (node (ref "IC60") (pin "3") (pinfunction "O_3") (pintype "output"))
      (node (ref "U$24") (pin "5") (pinfunction "I5_5") (pintype "input"))
    )
    (net (code "386") (name "Net-(IC60B-O)") (class "Default")
      (node (ref "IC60") (pin "6") (pinfunction "O_6") (pintype "output"))
      (node (ref "U$24") (pin "6") (pinfunction "I6_6") (pintype "input"))
    )
    (net (code "387") (name "Net-(IC60C-O)") (class "Default")
      (node (ref "IC60") (pin "8") (pinfunction "O_8") (pintype "output"))
      (node (ref "U$24") (pin "7") (pinfunction "I7_7") (pintype "input"))
    )
    (net (code "388") (name "Net-(IC60D-O)") (class "Default")
      (node (ref "IC60") (pin "11") (pinfunction "O_11") (pintype "output"))
      (node (ref "U$24") (pin "8") (pinfunction "I8_8") (pintype "input"))
    )
    (net (code "389") (name "Net-(IC61A-1D1)") (class "Default")
      (node (ref "IC61") (pin "47") (pinfunction "1D1_47") (pintype "input"))
      (node (ref "IC76") (pin "23") (pinfunction "2Q8_23") (pintype "tri_state"))
      (node (ref "IC80") (pin "12") (pinfunction "I0_12") (pintype "input"))
    )
    (net (code "390") (name "Net-(IC61A-1D2)") (class "Default")
      (node (ref "IC61") (pin "2") (pinfunction "1Q1_2") (pintype "tri_state"))
      (node (ref "IC61") (pin "46") (pinfunction "1D2_46") (pintype "input"))
      (node (ref "IC62") (pin "1") (pinfunction "I0_1") (pintype "input"))
    )
    (net (code "391") (name "Net-(IC61A-1D3)") (class "Default")
      (node (ref "IC61") (pin "3") (pinfunction "1Q2_3") (pintype "tri_state"))
      (node (ref "IC61") (pin "44") (pinfunction "1D3_44") (pintype "input"))
      (node (ref "IC62") (pin "4") (pinfunction "I0_4") (pintype "input"))
    )
    (net (code "392") (name "Net-(IC61A-1D4)") (class "Default")
      (node (ref "IC61") (pin "43") (pinfunction "1D4_43") (pintype "input"))
      (node (ref "IC61") (pin "5") (pinfunction "1Q3_5") (pintype "tri_state"))
      (node (ref "IC62") (pin "9") (pinfunction "I0_9") (pintype "input"))
    )
    (net (code "393") (name "Net-(IC61A-1D5)") (class "Default")
      (node (ref "IC61") (pin "41") (pinfunction "1D5_41") (pintype "input"))
      (node (ref "IC61") (pin "6") (pinfunction "1Q4_6") (pintype "tri_state"))
      (node (ref "IC62") (pin "12") (pinfunction "I0_12") (pintype "input"))
    )
    (net (code "394") (name "Net-(IC61A-1D6)") (class "Default")
      (node (ref "IC61") (pin "40") (pinfunction "1D6_40") (pintype "input"))
      (node (ref "IC61") (pin "8") (pinfunction "1Q5_8") (pintype "tri_state"))
      (node (ref "IC63") (pin "1") (pinfunction "I0_1") (pintype "input"))
    )
    (net (code "395") (name "Net-(IC61A-1D7)") (class "Default")
      (node (ref "IC61") (pin "38") (pinfunction "1D7_38") (pintype "input"))
      (node (ref "IC61") (pin "9") (pinfunction "1Q6_9") (pintype "tri_state"))
      (node (ref "IC63") (pin "4") (pinfunction "I0_4") (pintype "input"))
    )
    (net (code "396") (name "Net-(IC61A-1D8)") (class "Default")
      (node (ref "IC61") (pin "11") (pinfunction "1Q7_11") (pintype "tri_state"))
      (node (ref "IC61") (pin "37") (pinfunction "1D8_37") (pintype "input"))
      (node (ref "IC63") (pin "9") (pinfunction "I0_9") (pintype "input"))
    )
    (net (code "397") (name "Net-(IC61A-1Q8)") (class "Default")
      (node (ref "IC61") (pin "12") (pinfunction "1Q8_12") (pintype "tri_state"))
      (node (ref "IC61") (pin "36") (pinfunction "2D1_36") (pintype "input"))
      (node (ref "IC63") (pin "12") (pinfunction "I0_12") (pintype "input"))
    )
    (net (code "398") (name "Net-(IC61A-2D2)") (class "Default")
      (node (ref "IC61") (pin "13") (pinfunction "2Q1_13") (pintype "tri_state"))
      (node (ref "IC61") (pin "35") (pinfunction "2D2_35") (pintype "input"))
      (node (ref "IC64") (pin "1") (pinfunction "I0_1") (pintype "input"))
    )
    (net (code "399") (name "Net-(IC61A-2D3)") (class "Default")
      (node (ref "IC61") (pin "14") (pinfunction "2Q2_14") (pintype "tri_state"))
      (node (ref "IC61") (pin "33") (pinfunction "2D3_33") (pintype "input"))
      (node (ref "IC64") (pin "4") (pinfunction "I0_4") (pintype "input"))
    )
    (net (code "400") (name "Net-(IC61A-2D4)") (class "Default")
      (node (ref "IC61") (pin "16") (pinfunction "2Q3_16") (pintype "tri_state"))
      (node (ref "IC61") (pin "32") (pinfunction "2D4_32") (pintype "input"))
      (node (ref "IC64") (pin "9") (pinfunction "I0_9") (pintype "input"))
    )
    (net (code "401") (name "Net-(IC61A-2D5)") (class "Default")
      (node (ref "IC61") (pin "17") (pinfunction "2Q4_17") (pintype "tri_state"))
      (node (ref "IC61") (pin "30") (pinfunction "2D5_30") (pintype "input"))
      (node (ref "IC64") (pin "12") (pinfunction "I0_12") (pintype "input"))
    )
    (net (code "402") (name "Net-(IC61A-2D6)") (class "Default")
      (node (ref "IC61") (pin "19") (pinfunction "2Q5_19") (pintype "tri_state"))
      (node (ref "IC61") (pin "29") (pinfunction "2D6_29") (pintype "input"))
      (node (ref "IC65") (pin "1") (pinfunction "I0_1") (pintype "input"))
    )
    (net (code "403") (name "Net-(IC61A-2D7)") (class "Default")
      (node (ref "IC61") (pin "20") (pinfunction "2Q6_20") (pintype "tri_state"))
      (node (ref "IC61") (pin "27") (pinfunction "2D7_27") (pintype "input"))
      (node (ref "IC65") (pin "4") (pinfunction "I0_4") (pintype "input"))
    )
    (net (code "404") (name "Net-(IC61A-2D8)") (class "Default")
      (node (ref "IC61") (pin "22") (pinfunction "2Q7_22") (pintype "tri_state"))
      (node (ref "IC61") (pin "26") (pinfunction "2D8_26") (pintype "input"))
      (node (ref "IC65") (pin "9") (pinfunction "I0_9") (pintype "input"))
    )
    (net (code "405") (name "Net-(IC61A-2Q8)") (class "Default")
      (node (ref "IC61") (pin "23") (pinfunction "2Q8_23") (pintype "tri_state"))
      (node (ref "IC65") (pin "12") (pinfunction "I0_12") (pintype "input"))
      (node (ref "IC66") (pin "47") (pinfunction "1D1_47") (pintype "input"))
    )
    (net (code "406") (name "Net-(IC62A-O)") (class "Default")
      (node (ref "IC62") (pin "3") (pinfunction "O_3") (pintype "output"))
      (node (ref "U$25") (pin "1") (pinfunction "I1_1") (pintype "input"))
    )
    (net (code "407") (name "Net-(IC62B-O)") (class "Default")
      (node (ref "IC62") (pin "6") (pinfunction "O_6") (pintype "output"))
      (node (ref "U$25") (pin "2") (pinfunction "I2_2") (pintype "input"))
    )
    (net (code "408") (name "Net-(IC62C-O)") (class "Default")
      (node (ref "IC62") (pin "8") (pinfunction "O_8") (pintype "output"))
      (node (ref "U$25") (pin "3") (pinfunction "I3_3") (pintype "input"))
    )
    (net (code "409") (name "Net-(IC62D-O)") (class "Default")
      (node (ref "IC62") (pin "11") (pinfunction "O_11") (pintype "output"))
      (node (ref "U$25") (pin "4") (pinfunction "I4_4") (pintype "input"))
    )
    (net (code "410") (name "Net-(IC63A-O)") (class "Default")
      (node (ref "IC63") (pin "3") (pinfunction "O_3") (pintype "output"))
      (node (ref "U$25") (pin "5") (pinfunction "I5_5") (pintype "input"))
    )
    (net (code "411") (name "Net-(IC63B-O)") (class "Default")
      (node (ref "IC63") (pin "6") (pinfunction "O_6") (pintype "output"))
      (node (ref "U$25") (pin "6") (pinfunction "I6_6") (pintype "input"))
    )
    (net (code "412") (name "Net-(IC63C-O)") (class "Default")
      (node (ref "IC63") (pin "8") (pinfunction "O_8") (pintype "output"))
      (node (ref "U$25") (pin "7") (pinfunction "I7_7") (pintype "input"))
    )
    (net (code "413") (name "Net-(IC63D-O)") (class "Default")
      (node (ref "IC63") (pin "11") (pinfunction "O_11") (pintype "output"))
      (node (ref "U$25") (pin "8") (pinfunction "I8_8") (pintype "input"))
    )
    (net (code "414") (name "Net-(IC64A-O)") (class "Default")
      (node (ref "IC64") (pin "3") (pinfunction "O_3") (pintype "output"))
      (node (ref "U$26") (pin "1") (pinfunction "I1_1") (pintype "input"))
    )
    (net (code "415") (name "Net-(IC64B-O)") (class "Default")
      (node (ref "IC64") (pin "6") (pinfunction "O_6") (pintype "output"))
      (node (ref "U$26") (pin "2") (pinfunction "I2_2") (pintype "input"))
    )
    (net (code "416") (name "Net-(IC64C-O)") (class "Default")
      (node (ref "IC64") (pin "8") (pinfunction "O_8") (pintype "output"))
      (node (ref "U$26") (pin "3") (pinfunction "I3_3") (pintype "input"))
    )
    (net (code "417") (name "Net-(IC64D-O)") (class "Default")
      (node (ref "IC64") (pin "11") (pinfunction "O_11") (pintype "output"))
      (node (ref "U$26") (pin "4") (pinfunction "I4_4") (pintype "input"))
    )
    (net (code "418") (name "Net-(IC65A-O)") (class "Default")
      (node (ref "IC65") (pin "3") (pinfunction "O_3") (pintype "output"))
      (node (ref "U$26") (pin "5") (pinfunction "I5_5") (pintype "input"))
    )
    (net (code "419") (name "Net-(IC65B-O)") (class "Default")
      (node (ref "IC65") (pin "6") (pinfunction "O_6") (pintype "output"))
      (node (ref "U$26") (pin "6") (pinfunction "I6_6") (pintype "input"))
    )
    (net (code "420") (name "Net-(IC65C-O)") (class "Default")
      (node (ref "IC65") (pin "8") (pinfunction "O_8") (pintype "output"))
      (node (ref "U$26") (pin "7") (pinfunction "I7_7") (pintype "input"))
    )
    (net (code "421") (name "Net-(IC65D-O)") (class "Default")
      (node (ref "IC65") (pin "11") (pinfunction "O_11") (pintype "output"))
      (node (ref "U$26") (pin "8") (pinfunction "I8_8") (pintype "input"))
    )
    (net (code "422") (name "Net-(IC66A-1D2)") (class "Default")
      (node (ref "IC66") (pin "2") (pinfunction "1Q1_2") (pintype "tri_state"))
      (node (ref "IC66") (pin "46") (pinfunction "1D2_46") (pintype "input"))
      (node (ref "IC67") (pin "1") (pinfunction "I0_1") (pintype "input"))
    )
    (net (code "423") (name "Net-(IC66A-1D3)") (class "Default")
      (node (ref "IC66") (pin "3") (pinfunction "1Q2_3") (pintype "tri_state"))
      (node (ref "IC66") (pin "44") (pinfunction "1D3_44") (pintype "input"))
      (node (ref "IC67") (pin "4") (pinfunction "I0_4") (pintype "input"))
    )
    (net (code "424") (name "Net-(IC66A-1D4)") (class "Default")
      (node (ref "IC66") (pin "43") (pinfunction "1D4_43") (pintype "input"))
      (node (ref "IC66") (pin "5") (pinfunction "1Q3_5") (pintype "tri_state"))
      (node (ref "IC67") (pin "9") (pinfunction "I0_9") (pintype "input"))
    )
    (net (code "425") (name "Net-(IC66A-1D5)") (class "Default")
      (node (ref "IC66") (pin "41") (pinfunction "1D5_41") (pintype "input"))
      (node (ref "IC66") (pin "6") (pinfunction "1Q4_6") (pintype "tri_state"))
      (node (ref "IC67") (pin "12") (pinfunction "I0_12") (pintype "input"))
    )
    (net (code "426") (name "Net-(IC66A-1D6)") (class "Default")
      (node (ref "IC66") (pin "40") (pinfunction "1D6_40") (pintype "input"))
      (node (ref "IC66") (pin "8") (pinfunction "1Q5_8") (pintype "tri_state"))
      (node (ref "IC68") (pin "1") (pinfunction "I0_1") (pintype "input"))
    )
    (net (code "427") (name "Net-(IC66A-1D7)") (class "Default")
      (node (ref "IC66") (pin "38") (pinfunction "1D7_38") (pintype "input"))
      (node (ref "IC66") (pin "9") (pinfunction "1Q6_9") (pintype "tri_state"))
      (node (ref "IC68") (pin "4") (pinfunction "I0_4") (pintype "input"))
    )
    (net (code "428") (name "Net-(IC66A-1D8)") (class "Default")
      (node (ref "IC66") (pin "11") (pinfunction "1Q7_11") (pintype "tri_state"))
      (node (ref "IC66") (pin "37") (pinfunction "1D8_37") (pintype "input"))
      (node (ref "IC68") (pin "9") (pinfunction "I0_9") (pintype "input"))
    )
    (net (code "429") (name "Net-(IC66A-1Q8)") (class "Default")
      (node (ref "IC66") (pin "12") (pinfunction "1Q8_12") (pintype "tri_state"))
      (node (ref "IC66") (pin "36") (pinfunction "2D1_36") (pintype "input"))
      (node (ref "IC68") (pin "12") (pinfunction "I0_12") (pintype "input"))
    )
    (net (code "430") (name "Net-(IC66A-2D2)") (class "Default")
      (node (ref "IC66") (pin "13") (pinfunction "2Q1_13") (pintype "tri_state"))
      (node (ref "IC66") (pin "35") (pinfunction "2D2_35") (pintype "input"))
      (node (ref "IC69") (pin "1") (pinfunction "I0_1") (pintype "input"))
    )
    (net (code "431") (name "Net-(IC66A-2D3)") (class "Default")
      (node (ref "IC66") (pin "14") (pinfunction "2Q2_14") (pintype "tri_state"))
      (node (ref "IC66") (pin "33") (pinfunction "2D3_33") (pintype "input"))
      (node (ref "IC69") (pin "4") (pinfunction "I0_4") (pintype "input"))
    )
    (net (code "432") (name "Net-(IC66A-2D4)") (class "Default")
      (node (ref "IC66") (pin "16") (pinfunction "2Q3_16") (pintype "tri_state"))
      (node (ref "IC66") (pin "32") (pinfunction "2D4_32") (pintype "input"))
      (node (ref "IC69") (pin "9") (pinfunction "I0_9") (pintype "input"))
    )
    (net (code "433") (name "Net-(IC66A-2D5)") (class "Default")
      (node (ref "IC66") (pin "17") (pinfunction "2Q4_17") (pintype "tri_state"))
      (node (ref "IC66") (pin "30") (pinfunction "2D5_30") (pintype "input"))
      (node (ref "IC69") (pin "12") (pinfunction "I0_12") (pintype "input"))
    )
    (net (code "434") (name "Net-(IC66A-2D6)") (class "Default")
      (node (ref "IC66") (pin "19") (pinfunction "2Q5_19") (pintype "tri_state"))
      (node (ref "IC66") (pin "29") (pinfunction "2D6_29") (pintype "input"))
      (node (ref "IC70") (pin "1") (pinfunction "I0_1") (pintype "input"))
    )
    (net (code "435") (name "Net-(IC66A-2D7)") (class "Default")
      (node (ref "IC66") (pin "20") (pinfunction "2Q6_20") (pintype "tri_state"))
      (node (ref "IC66") (pin "27") (pinfunction "2D7_27") (pintype "input"))
      (node (ref "IC70") (pin "4") (pinfunction "I0_4") (pintype "input"))
    )
    (net (code "436") (name "Net-(IC66A-2D8)") (class "Default")
      (node (ref "IC66") (pin "22") (pinfunction "2Q7_22") (pintype "tri_state"))
      (node (ref "IC66") (pin "26") (pinfunction "2D8_26") (pintype "input"))
      (node (ref "IC70") (pin "9") (pinfunction "I0_9") (pintype "input"))
    )
    (net (code "437") (name "Net-(IC67A-O)") (class "Default")
      (node (ref "IC67") (pin "3") (pinfunction "O_3") (pintype "output"))
      (node (ref "U$27") (pin "1") (pinfunction "I1_1") (pintype "input"))
    )
    (net (code "438") (name "Net-(IC67B-O)") (class "Default")
      (node (ref "IC67") (pin "6") (pinfunction "O_6") (pintype "output"))
      (node (ref "U$27") (pin "2") (pinfunction "I2_2") (pintype "input"))
    )
    (net (code "439") (name "Net-(IC67C-O)") (class "Default")
      (node (ref "IC67") (pin "8") (pinfunction "O_8") (pintype "output"))
      (node (ref "U$27") (pin "3") (pinfunction "I3_3") (pintype "input"))
    )
    (net (code "440") (name "Net-(IC67D-O)") (class "Default")
      (node (ref "IC67") (pin "11") (pinfunction "O_11") (pintype "output"))
      (node (ref "U$27") (pin "4") (pinfunction "I4_4") (pintype "input"))
    )
    (net (code "441") (name "Net-(IC68A-O)") (class "Default")
      (node (ref "IC68") (pin "3") (pinfunction "O_3") (pintype "output"))
      (node (ref "U$27") (pin "5") (pinfunction "I5_5") (pintype "input"))
    )
    (net (code "442") (name "Net-(IC68B-O)") (class "Default")
      (node (ref "IC68") (pin "6") (pinfunction "O_6") (pintype "output"))
      (node (ref "U$27") (pin "6") (pinfunction "I6_6") (pintype "input"))
    )
    (net (code "443") (name "Net-(IC68C-O)") (class "Default")
      (node (ref "IC68") (pin "8") (pinfunction "O_8") (pintype "output"))
      (node (ref "U$27") (pin "7") (pinfunction "I7_7") (pintype "input"))
    )
    (net (code "444") (name "Net-(IC68D-O)") (class "Default")
      (node (ref "IC68") (pin "11") (pinfunction "O_11") (pintype "output"))
      (node (ref "U$27") (pin "8") (pinfunction "I8_8") (pintype "input"))
    )
    (net (code "445") (name "Net-(IC69A-O)") (class "Default")
      (node (ref "IC69") (pin "3") (pinfunction "O_3") (pintype "output"))
      (node (ref "U$28") (pin "1") (pinfunction "I1_1") (pintype "input"))
    )
    (net (code "446") (name "Net-(IC69B-O)") (class "Default")
      (node (ref "IC69") (pin "6") (pinfunction "O_6") (pintype "output"))
      (node (ref "U$28") (pin "2") (pinfunction "I2_2") (pintype "input"))
    )
    (net (code "447") (name "Net-(IC69C-O)") (class "Default")
      (node (ref "IC69") (pin "8") (pinfunction "O_8") (pintype "output"))
      (node (ref "U$28") (pin "3") (pinfunction "I3_3") (pintype "input"))
    )
    (net (code "448") (name "Net-(IC69D-O)") (class "Default")
      (node (ref "IC69") (pin "11") (pinfunction "O_11") (pintype "output"))
      (node (ref "U$28") (pin "4") (pinfunction "I4_4") (pintype "input"))
    )
    (net (code "449") (name "Net-(IC70A-O)") (class "Default")
      (node (ref "IC70") (pin "3") (pinfunction "O_3") (pintype "output"))
      (node (ref "U$28") (pin "5") (pinfunction "I5_5") (pintype "input"))
    )
    (net (code "450") (name "Net-(IC70B-O)") (class "Default")
      (node (ref "IC70") (pin "6") (pinfunction "O_6") (pintype "output"))
      (node (ref "U$28") (pin "6") (pinfunction "I6_6") (pintype "input"))
    )
    (net (code "451") (name "Net-(IC70C-O)") (class "Default")
      (node (ref "IC70") (pin "8") (pinfunction "O_8") (pintype "output"))
      (node (ref "U$28") (pin "7") (pinfunction "I7_7") (pintype "input"))
    )
    (net (code "452") (name "Net-(IC70D-O)") (class "Default")
      (node (ref "IC70") (pin "11") (pinfunction "O_11") (pintype "output"))
      (node (ref "U$28") (pin "8") (pinfunction "I8_8") (pintype "input"))
    )
    (net (code "453") (name "Net-(IC71A-1D1)") (class "Default")
      (node (ref "IC71") (pin "47") (pinfunction "1D1_47") (pintype "input"))
      (node (ref "IC86") (pin "23") (pinfunction "2Q8_23") (pintype "tri_state"))
      (node (ref "IC90") (pin "12") (pinfunction "I0_12") (pintype "input"))
    )
    (net (code "454") (name "Net-(IC71A-1D2)") (class "Default")
      (node (ref "IC71") (pin "2") (pinfunction "1Q1_2") (pintype "tri_state"))
      (node (ref "IC71") (pin "46") (pinfunction "1D2_46") (pintype "input"))
      (node (ref "IC72") (pin "1") (pinfunction "I0_1") (pintype "input"))
    )
    (net (code "455") (name "Net-(IC71A-1D3)") (class "Default")
      (node (ref "IC71") (pin "3") (pinfunction "1Q2_3") (pintype "tri_state"))
      (node (ref "IC71") (pin "44") (pinfunction "1D3_44") (pintype "input"))
      (node (ref "IC72") (pin "4") (pinfunction "I0_4") (pintype "input"))
    )
    (net (code "456") (name "Net-(IC71A-1D4)") (class "Default")
      (node (ref "IC71") (pin "43") (pinfunction "1D4_43") (pintype "input"))
      (node (ref "IC71") (pin "5") (pinfunction "1Q3_5") (pintype "tri_state"))
      (node (ref "IC72") (pin "9") (pinfunction "I0_9") (pintype "input"))
    )
    (net (code "457") (name "Net-(IC71A-1D5)") (class "Default")
      (node (ref "IC71") (pin "41") (pinfunction "1D5_41") (pintype "input"))
      (node (ref "IC71") (pin "6") (pinfunction "1Q4_6") (pintype "tri_state"))
      (node (ref "IC72") (pin "12") (pinfunction "I0_12") (pintype "input"))
    )
    (net (code "458") (name "Net-(IC71A-1D6)") (class "Default")
      (node (ref "IC71") (pin "40") (pinfunction "1D6_40") (pintype "input"))
      (node (ref "IC71") (pin "8") (pinfunction "1Q5_8") (pintype "tri_state"))
      (node (ref "IC73") (pin "1") (pinfunction "I0_1") (pintype "input"))
    )
    (net (code "459") (name "Net-(IC71A-1D7)") (class "Default")
      (node (ref "IC71") (pin "38") (pinfunction "1D7_38") (pintype "input"))
      (node (ref "IC71") (pin "9") (pinfunction "1Q6_9") (pintype "tri_state"))
      (node (ref "IC73") (pin "4") (pinfunction "I0_4") (pintype "input"))
    )
    (net (code "460") (name "Net-(IC71A-1D8)") (class "Default")
      (node (ref "IC71") (pin "11") (pinfunction "1Q7_11") (pintype "tri_state"))
      (node (ref "IC71") (pin "37") (pinfunction "1D8_37") (pintype "input"))
      (node (ref "IC73") (pin "9") (pinfunction "I0_9") (pintype "input"))
    )
    (net (code "461") (name "Net-(IC71A-1Q8)") (class "Default")
      (node (ref "IC71") (pin "12") (pinfunction "1Q8_12") (pintype "tri_state"))
      (node (ref "IC71") (pin "36") (pinfunction "2D1_36") (pintype "input"))
      (node (ref "IC73") (pin "12") (pinfunction "I0_12") (pintype "input"))
    )
    (net (code "462") (name "Net-(IC71A-2D2)") (class "Default")
      (node (ref "IC71") (pin "13") (pinfunction "2Q1_13") (pintype "tri_state"))
      (node (ref "IC71") (pin "35") (pinfunction "2D2_35") (pintype "input"))
      (node (ref "IC74") (pin "1") (pinfunction "I0_1") (pintype "input"))
    )
    (net (code "463") (name "Net-(IC71A-2D3)") (class "Default")
      (node (ref "IC71") (pin "14") (pinfunction "2Q2_14") (pintype "tri_state"))
      (node (ref "IC71") (pin "33") (pinfunction "2D3_33") (pintype "input"))
      (node (ref "IC74") (pin "4") (pinfunction "I0_4") (pintype "input"))
    )
    (net (code "464") (name "Net-(IC71A-2D4)") (class "Default")
      (node (ref "IC71") (pin "16") (pinfunction "2Q3_16") (pintype "tri_state"))
      (node (ref "IC71") (pin "32") (pinfunction "2D4_32") (pintype "input"))
      (node (ref "IC74") (pin "9") (pinfunction "I0_9") (pintype "input"))
    )
    (net (code "465") (name "Net-(IC71A-2D5)") (class "Default")
      (node (ref "IC71") (pin "17") (pinfunction "2Q4_17") (pintype "tri_state"))
      (node (ref "IC71") (pin "30") (pinfunction "2D5_30") (pintype "input"))
      (node (ref "IC74") (pin "12") (pinfunction "I0_12") (pintype "input"))
    )
    (net (code "466") (name "Net-(IC71A-2D6)") (class "Default")
      (node (ref "IC71") (pin "19") (pinfunction "2Q5_19") (pintype "tri_state"))
      (node (ref "IC71") (pin "29") (pinfunction "2D6_29") (pintype "input"))
      (node (ref "IC75") (pin "1") (pinfunction "I0_1") (pintype "input"))
    )
    (net (code "467") (name "Net-(IC71A-2D7)") (class "Default")
      (node (ref "IC71") (pin "20") (pinfunction "2Q6_20") (pintype "tri_state"))
      (node (ref "IC71") (pin "27") (pinfunction "2D7_27") (pintype "input"))
      (node (ref "IC75") (pin "4") (pinfunction "I0_4") (pintype "input"))
    )
    (net (code "468") (name "Net-(IC71A-2D8)") (class "Default")
      (node (ref "IC71") (pin "22") (pinfunction "2Q7_22") (pintype "tri_state"))
      (node (ref "IC71") (pin "26") (pinfunction "2D8_26") (pintype "input"))
      (node (ref "IC75") (pin "9") (pinfunction "I0_9") (pintype "input"))
    )
    (net (code "469") (name "Net-(IC71A-2Q8)") (class "Default")
      (node (ref "IC71") (pin "23") (pinfunction "2Q8_23") (pintype "tri_state"))
      (node (ref "IC75") (pin "12") (pinfunction "I0_12") (pintype "input"))
      (node (ref "IC76") (pin "47") (pinfunction "1D1_47") (pintype "input"))
    )
    (net (code "470") (name "Net-(IC72A-O)") (class "Default")
      (node (ref "IC72") (pin "3") (pinfunction "O_3") (pintype "output"))
      (node (ref "U$29") (pin "1") (pinfunction "I1_1") (pintype "input"))
    )
    (net (code "471") (name "Net-(IC72B-O)") (class "Default")
      (node (ref "IC72") (pin "6") (pinfunction "O_6") (pintype "output"))
      (node (ref "U$29") (pin "2") (pinfunction "I2_2") (pintype "input"))
    )
    (net (code "472") (name "Net-(IC72C-O)") (class "Default")
      (node (ref "IC72") (pin "8") (pinfunction "O_8") (pintype "output"))
      (node (ref "U$29") (pin "3") (pinfunction "I3_3") (pintype "input"))
    )
    (net (code "473") (name "Net-(IC72D-O)") (class "Default")
      (node (ref "IC72") (pin "11") (pinfunction "O_11") (pintype "output"))
      (node (ref "U$29") (pin "4") (pinfunction "I4_4") (pintype "input"))
    )
    (net (code "474") (name "Net-(IC73A-O)") (class "Default")
      (node (ref "IC73") (pin "3") (pinfunction "O_3") (pintype "output"))
      (node (ref "U$29") (pin "5") (pinfunction "I5_5") (pintype "input"))
    )
    (net (code "475") (name "Net-(IC73B-O)") (class "Default")
      (node (ref "IC73") (pin "6") (pinfunction "O_6") (pintype "output"))
      (node (ref "U$29") (pin "6") (pinfunction "I6_6") (pintype "input"))
    )
    (net (code "476") (name "Net-(IC73C-O)") (class "Default")
      (node (ref "IC73") (pin "8") (pinfunction "O_8") (pintype "output"))
      (node (ref "U$29") (pin "7") (pinfunction "I7_7") (pintype "input"))
    )
    (net (code "477") (name "Net-(IC73D-O)") (class "Default")
      (node (ref "IC73") (pin "11") (pinfunction "O_11") (pintype "output"))
      (node (ref "U$29") (pin "8") (pinfunction "I8_8") (pintype "input"))
    )
    (net (code "478") (name "Net-(IC74A-O)") (class "Default")
      (node (ref "IC74") (pin "3") (pinfunction "O_3") (pintype "output"))
      (node (ref "U$30") (pin "1") (pinfunction "I1_1") (pintype "input"))
    )
    (net (code "479") (name "Net-(IC74B-O)") (class "Default")
      (node (ref "IC74") (pin "6") (pinfunction "O_6") (pintype "output"))
      (node (ref "U$30") (pin "2") (pinfunction "I2_2") (pintype "input"))
    )
    (net (code "480") (name "Net-(IC74C-O)") (class "Default")
      (node (ref "IC74") (pin "8") (pinfunction "O_8") (pintype "output"))
      (node (ref "U$30") (pin "3") (pinfunction "I3_3") (pintype "input"))
    )
    (net (code "481") (name "Net-(IC74D-O)") (class "Default")
      (node (ref "IC74") (pin "11") (pinfunction "O_11") (pintype "output"))
      (node (ref "U$30") (pin "4") (pinfunction "I4_4") (pintype "input"))
    )
    (net (code "482") (name "Net-(IC75A-O)") (class "Default")
      (node (ref "IC75") (pin "3") (pinfunction "O_3") (pintype "output"))
      (node (ref "U$30") (pin "5") (pinfunction "I5_5") (pintype "input"))
    )
    (net (code "483") (name "Net-(IC75B-O)") (class "Default")
      (node (ref "IC75") (pin "6") (pinfunction "O_6") (pintype "output"))
      (node (ref "U$30") (pin "6") (pinfunction "I6_6") (pintype "input"))
    )
    (net (code "484") (name "Net-(IC75C-O)") (class "Default")
      (node (ref "IC75") (pin "8") (pinfunction "O_8") (pintype "output"))
      (node (ref "U$30") (pin "7") (pinfunction "I7_7") (pintype "input"))
    )
    (net (code "485") (name "Net-(IC75D-O)") (class "Default")
      (node (ref "IC75") (pin "11") (pinfunction "O_11") (pintype "output"))
      (node (ref "U$30") (pin "8") (pinfunction "I8_8") (pintype "input"))
    )
    (net (code "486") (name "Net-(IC76A-1D2)") (class "Default")
      (node (ref "IC76") (pin "2") (pinfunction "1Q1_2") (pintype "tri_state"))
      (node (ref "IC76") (pin "46") (pinfunction "1D2_46") (pintype "input"))
      (node (ref "IC77") (pin "1") (pinfunction "I0_1") (pintype "input"))
    )
    (net (code "487") (name "Net-(IC76A-1D3)") (class "Default")
      (node (ref "IC76") (pin "3") (pinfunction "1Q2_3") (pintype "tri_state"))
      (node (ref "IC76") (pin "44") (pinfunction "1D3_44") (pintype "input"))
      (node (ref "IC77") (pin "4") (pinfunction "I0_4") (pintype "input"))
    )
    (net (code "488") (name "Net-(IC76A-1D4)") (class "Default")
      (node (ref "IC76") (pin "43") (pinfunction "1D4_43") (pintype "input"))
      (node (ref "IC76") (pin "5") (pinfunction "1Q3_5") (pintype "tri_state"))
      (node (ref "IC77") (pin "9") (pinfunction "I0_9") (pintype "input"))
    )
    (net (code "489") (name "Net-(IC76A-1D5)") (class "Default")
      (node (ref "IC76") (pin "41") (pinfunction "1D5_41") (pintype "input"))
      (node (ref "IC76") (pin "6") (pinfunction "1Q4_6") (pintype "tri_state"))
      (node (ref "IC77") (pin "12") (pinfunction "I0_12") (pintype "input"))
    )
    (net (code "490") (name "Net-(IC76A-1D6)") (class "Default")
      (node (ref "IC76") (pin "40") (pinfunction "1D6_40") (pintype "input"))
      (node (ref "IC76") (pin "8") (pinfunction "1Q5_8") (pintype "tri_state"))
      (node (ref "IC78") (pin "1") (pinfunction "I0_1") (pintype "input"))
    )
    (net (code "491") (name "Net-(IC76A-1D7)") (class "Default")
      (node (ref "IC76") (pin "38") (pinfunction "1D7_38") (pintype "input"))
      (node (ref "IC76") (pin "9") (pinfunction "1Q6_9") (pintype "tri_state"))
      (node (ref "IC78") (pin "4") (pinfunction "I0_4") (pintype "input"))
    )
    (net (code "492") (name "Net-(IC76A-1D8)") (class "Default")
      (node (ref "IC76") (pin "11") (pinfunction "1Q7_11") (pintype "tri_state"))
      (node (ref "IC76") (pin "37") (pinfunction "1D8_37") (pintype "input"))
      (node (ref "IC78") (pin "9") (pinfunction "I0_9") (pintype "input"))
    )
    (net (code "493") (name "Net-(IC76A-1Q8)") (class "Default")
      (node (ref "IC76") (pin "12") (pinfunction "1Q8_12") (pintype "tri_state"))
      (node (ref "IC76") (pin "36") (pinfunction "2D1_36") (pintype "input"))
      (node (ref "IC78") (pin "12") (pinfunction "I0_12") (pintype "input"))
    )
    (net (code "494") (name "Net-(IC76A-2D2)") (class "Default")
      (node (ref "IC76") (pin "13") (pinfunction "2Q1_13") (pintype "tri_state"))
      (node (ref "IC76") (pin "35") (pinfunction "2D2_35") (pintype "input"))
      (node (ref "IC79") (pin "1") (pinfunction "I0_1") (pintype "input"))
    )
    (net (code "495") (name "Net-(IC76A-2D3)") (class "Default")
      (node (ref "IC76") (pin "14") (pinfunction "2Q2_14") (pintype "tri_state"))
      (node (ref "IC76") (pin "33") (pinfunction "2D3_33") (pintype "input"))
      (node (ref "IC79") (pin "4") (pinfunction "I0_4") (pintype "input"))
    )
    (net (code "496") (name "Net-(IC76A-2D4)") (class "Default")
      (node (ref "IC76") (pin "16") (pinfunction "2Q3_16") (pintype "tri_state"))
      (node (ref "IC76") (pin "32") (pinfunction "2D4_32") (pintype "input"))
      (node (ref "IC79") (pin "9") (pinfunction "I0_9") (pintype "input"))
    )
    (net (code "497") (name "Net-(IC76A-2D5)") (class "Default")
      (node (ref "IC76") (pin "17") (pinfunction "2Q4_17") (pintype "tri_state"))
      (node (ref "IC76") (pin "30") (pinfunction "2D5_30") (pintype "input"))
      (node (ref "IC79") (pin "12") (pinfunction "I0_12") (pintype "input"))
    )
    (net (code "498") (name "Net-(IC76A-2D6)") (class "Default")
      (node (ref "IC76") (pin "19") (pinfunction "2Q5_19") (pintype "tri_state"))
      (node (ref "IC76") (pin "29") (pinfunction "2D6_29") (pintype "input"))
      (node (ref "IC80") (pin "1") (pinfunction "I0_1") (pintype "input"))
    )
    (net (code "499") (name "Net-(IC76A-2D7)") (class "Default")
      (node (ref "IC76") (pin "20") (pinfunction "2Q6_20") (pintype "tri_state"))
      (node (ref "IC76") (pin "27") (pinfunction "2D7_27") (pintype "input"))
      (node (ref "IC80") (pin "4") (pinfunction "I0_4") (pintype "input"))
    )
    (net (code "500") (name "Net-(IC76A-2D8)") (class "Default")
      (node (ref "IC76") (pin "22") (pinfunction "2Q7_22") (pintype "tri_state"))
      (node (ref "IC76") (pin "26") (pinfunction "2D8_26") (pintype "input"))
      (node (ref "IC80") (pin "9") (pinfunction "I0_9") (pintype "input"))
    )
    (net (code "501") (name "Net-(IC77A-O)") (class "Default")
      (node (ref "IC77") (pin "3") (pinfunction "O_3") (pintype "output"))
      (node (ref "U$31") (pin "1") (pinfunction "I1_1") (pintype "input"))
    )
    (net (code "502") (name "Net-(IC77B-O)") (class "Default")
      (node (ref "IC77") (pin "6") (pinfunction "O_6") (pintype "output"))
      (node (ref "U$31") (pin "2") (pinfunction "I2_2") (pintype "input"))
    )
    (net (code "503") (name "Net-(IC77C-O)") (class "Default")
      (node (ref "IC77") (pin "8") (pinfunction "O_8") (pintype "output"))
      (node (ref "U$31") (pin "3") (pinfunction "I3_3") (pintype "input"))
    )
    (net (code "504") (name "Net-(IC77D-O)") (class "Default")
      (node (ref "IC77") (pin "11") (pinfunction "O_11") (pintype "output"))
      (node (ref "U$31") (pin "4") (pinfunction "I4_4") (pintype "input"))
    )
    (net (code "505") (name "Net-(IC78A-O)") (class "Default")
      (node (ref "IC78") (pin "3") (pinfunction "O_3") (pintype "output"))
      (node (ref "U$31") (pin "5") (pinfunction "I5_5") (pintype "input"))
    )
    (net (code "506") (name "Net-(IC78B-O)") (class "Default")
      (node (ref "IC78") (pin "6") (pinfunction "O_6") (pintype "output"))
      (node (ref "U$31") (pin "6") (pinfunction "I6_6") (pintype "input"))
    )
    (net (code "507") (name "Net-(IC78C-O)") (class "Default")
      (node (ref "IC78") (pin "8") (pinfunction "O_8") (pintype "output"))
      (node (ref "U$31") (pin "7") (pinfunction "I7_7") (pintype "input"))
    )
    (net (code "508") (name "Net-(IC78D-O)") (class "Default")
      (node (ref "IC78") (pin "11") (pinfunction "O_11") (pintype "output"))
      (node (ref "U$31") (pin "8") (pinfunction "I8_8") (pintype "input"))
    )
    (net (code "509") (name "Net-(IC79A-O)") (class "Default")
      (node (ref "IC79") (pin "3") (pinfunction "O_3") (pintype "output"))
      (node (ref "U$32") (pin "1") (pinfunction "I1_1") (pintype "input"))
    )
    (net (code "510") (name "Net-(IC79B-O)") (class "Default")
      (node (ref "IC79") (pin "6") (pinfunction "O_6") (pintype "output"))
      (node (ref "U$32") (pin "2") (pinfunction "I2_2") (pintype "input"))
    )
    (net (code "511") (name "Net-(IC79C-O)") (class "Default")
      (node (ref "IC79") (pin "8") (pinfunction "O_8") (pintype "output"))
      (node (ref "U$32") (pin "3") (pinfunction "I3_3") (pintype "input"))
    )
    (net (code "512") (name "Net-(IC79D-O)") (class "Default")
      (node (ref "IC79") (pin "11") (pinfunction "O_11") (pintype "output"))
      (node (ref "U$32") (pin "4") (pinfunction "I4_4") (pintype "input"))
    )
    (net (code "513") (name "Net-(IC80A-O)") (class "Default")
      (node (ref "IC80") (pin "3") (pinfunction "O_3") (pintype "output"))
      (node (ref "U$32") (pin "5") (pinfunction "I5_5") (pintype "input"))
    )
    (net (code "514") (name "Net-(IC80B-O)") (class "Default")
      (node (ref "IC80") (pin "6") (pinfunction "O_6") (pintype "output"))
      (node (ref "U$32") (pin "6") (pinfunction "I6_6") (pintype "input"))
    )
    (net (code "515") (name "Net-(IC80C-O)") (class "Default")
      (node (ref "IC80") (pin "8") (pinfunction "O_8") (pintype "output"))
      (node (ref "U$32") (pin "7") (pinfunction "I7_7") (pintype "input"))
    )
    (net (code "516") (name "Net-(IC80D-O)") (class "Default")
      (node (ref "IC80") (pin "11") (pinfunction "O_11") (pintype "output"))
      (node (ref "U$32") (pin "8") (pinfunction "I8_8") (pintype "input"))
    )
    (net (code "517") (name "Net-(IC81A-1D2)") (class "Default")
      (node (ref "IC81") (pin "2") (pinfunction "1Q1_2") (pintype "tri_state"))
      (node (ref "IC81") (pin "46") (pinfunction "1D2_46") (pintype "input"))
      (node (ref "IC82") (pin "1") (pinfunction "I0_1") (pintype "input"))
    )
    (net (code "518") (name "Net-(IC81A-1D3)") (class "Default")
      (node (ref "IC81") (pin "3") (pinfunction "1Q2_3") (pintype "tri_state"))
      (node (ref "IC81") (pin "44") (pinfunction "1D3_44") (pintype "input"))
      (node (ref "IC82") (pin "4") (pinfunction "I0_4") (pintype "input"))
    )
    (net (code "519") (name "Net-(IC81A-1D4)") (class "Default")
      (node (ref "IC81") (pin "43") (pinfunction "1D4_43") (pintype "input"))
      (node (ref "IC81") (pin "5") (pinfunction "1Q3_5") (pintype "tri_state"))
      (node (ref "IC82") (pin "9") (pinfunction "I0_9") (pintype "input"))
    )
    (net (code "520") (name "Net-(IC81A-1D5)") (class "Default")
      (node (ref "IC81") (pin "41") (pinfunction "1D5_41") (pintype "input"))
      (node (ref "IC81") (pin "6") (pinfunction "1Q4_6") (pintype "tri_state"))
      (node (ref "IC82") (pin "12") (pinfunction "I0_12") (pintype "input"))
    )
    (net (code "521") (name "Net-(IC81A-1D6)") (class "Default")
      (node (ref "IC81") (pin "40") (pinfunction "1D6_40") (pintype "input"))
      (node (ref "IC81") (pin "8") (pinfunction "1Q5_8") (pintype "tri_state"))
      (node (ref "IC83") (pin "1") (pinfunction "I0_1") (pintype "input"))
    )
    (net (code "522") (name "Net-(IC81A-1D7)") (class "Default")
      (node (ref "IC81") (pin "38") (pinfunction "1D7_38") (pintype "input"))
      (node (ref "IC81") (pin "9") (pinfunction "1Q6_9") (pintype "tri_state"))
      (node (ref "IC83") (pin "4") (pinfunction "I0_4") (pintype "input"))
    )
    (net (code "523") (name "Net-(IC81A-1D8)") (class "Default")
      (node (ref "IC81") (pin "11") (pinfunction "1Q7_11") (pintype "tri_state"))
      (node (ref "IC81") (pin "37") (pinfunction "1D8_37") (pintype "input"))
      (node (ref "IC83") (pin "9") (pinfunction "I0_9") (pintype "input"))
    )
    (net (code "524") (name "Net-(IC81A-1Q8)") (class "Default")
      (node (ref "IC81") (pin "12") (pinfunction "1Q8_12") (pintype "tri_state"))
      (node (ref "IC81") (pin "36") (pinfunction "2D1_36") (pintype "input"))
      (node (ref "IC83") (pin "12") (pinfunction "I0_12") (pintype "input"))
    )
    (net (code "525") (name "Net-(IC81A-2D2)") (class "Default")
      (node (ref "IC81") (pin "13") (pinfunction "2Q1_13") (pintype "tri_state"))
      (node (ref "IC81") (pin "35") (pinfunction "2D2_35") (pintype "input"))
      (node (ref "IC84") (pin "1") (pinfunction "I0_1") (pintype "input"))
    )
    (net (code "526") (name "Net-(IC81A-2D3)") (class "Default")
      (node (ref "IC81") (pin "14") (pinfunction "2Q2_14") (pintype "tri_state"))
      (node (ref "IC81") (pin "33") (pinfunction "2D3_33") (pintype "input"))
      (node (ref "IC84") (pin "4") (pinfunction "I0_4") (pintype "input"))
    )
    (net (code "527") (name "Net-(IC81A-2D4)") (class "Default")
      (node (ref "IC81") (pin "16") (pinfunction "2Q3_16") (pintype "tri_state"))
      (node (ref "IC81") (pin "32") (pinfunction "2D4_32") (pintype "input"))
      (node (ref "IC84") (pin "9") (pinfunction "I0_9") (pintype "input"))
    )
    (net (code "528") (name "Net-(IC81A-2D5)") (class "Default")
      (node (ref "IC81") (pin "17") (pinfunction "2Q4_17") (pintype "tri_state"))
      (node (ref "IC81") (pin "30") (pinfunction "2D5_30") (pintype "input"))
      (node (ref "IC84") (pin "12") (pinfunction "I0_12") (pintype "input"))
    )
    (net (code "529") (name "Net-(IC81A-2D6)") (class "Default")
      (node (ref "IC81") (pin "19") (pinfunction "2Q5_19") (pintype "tri_state"))
      (node (ref "IC81") (pin "29") (pinfunction "2D6_29") (pintype "input"))
      (node (ref "IC85") (pin "1") (pinfunction "I0_1") (pintype "input"))
    )
    (net (code "530") (name "Net-(IC81A-2D7)") (class "Default")
      (node (ref "IC81") (pin "20") (pinfunction "2Q6_20") (pintype "tri_state"))
      (node (ref "IC81") (pin "27") (pinfunction "2D7_27") (pintype "input"))
      (node (ref "IC85") (pin "4") (pinfunction "I0_4") (pintype "input"))
    )
    (net (code "531") (name "Net-(IC81A-2D8)") (class "Default")
      (node (ref "IC81") (pin "22") (pinfunction "2Q7_22") (pintype "tri_state"))
      (node (ref "IC81") (pin "26") (pinfunction "2D8_26") (pintype "input"))
      (node (ref "IC85") (pin "9") (pinfunction "I0_9") (pintype "input"))
    )
    (net (code "532") (name "Net-(IC81A-2Q8)") (class "Default")
      (node (ref "IC81") (pin "23") (pinfunction "2Q8_23") (pintype "tri_state"))
      (node (ref "IC85") (pin "12") (pinfunction "I0_12") (pintype "input"))
      (node (ref "IC86") (pin "47") (pinfunction "1D1_47") (pintype "input"))
    )
    (net (code "533") (name "Net-(IC82A-O)") (class "Default")
      (node (ref "IC82") (pin "3") (pinfunction "O_3") (pintype "output"))
      (node (ref "U$33") (pin "1") (pinfunction "I1_1") (pintype "input"))
    )
    (net (code "534") (name "Net-(IC82B-O)") (class "Default")
      (node (ref "IC82") (pin "6") (pinfunction "O_6") (pintype "output"))
      (node (ref "U$33") (pin "2") (pinfunction "I2_2") (pintype "input"))
    )
    (net (code "535") (name "Net-(IC82C-O)") (class "Default")
      (node (ref "IC82") (pin "8") (pinfunction "O_8") (pintype "output"))
      (node (ref "U$33") (pin "3") (pinfunction "I3_3") (pintype "input"))
    )
    (net (code "536") (name "Net-(IC82D-O)") (class "Default")
      (node (ref "IC82") (pin "11") (pinfunction "O_11") (pintype "output"))
      (node (ref "U$33") (pin "4") (pinfunction "I4_4") (pintype "input"))
    )
    (net (code "537") (name "Net-(IC83A-O)") (class "Default")
      (node (ref "IC83") (pin "3") (pinfunction "O_3") (pintype "output"))
      (node (ref "U$33") (pin "5") (pinfunction "I5_5") (pintype "input"))
    )
    (net (code "538") (name "Net-(IC83B-O)") (class "Default")
      (node (ref "IC83") (pin "6") (pinfunction "O_6") (pintype "output"))
      (node (ref "U$33") (pin "6") (pinfunction "I6_6") (pintype "input"))
    )
    (net (code "539") (name "Net-(IC83C-O)") (class "Default")
      (node (ref "IC83") (pin "8") (pinfunction "O_8") (pintype "output"))
      (node (ref "U$33") (pin "7") (pinfunction "I7_7") (pintype "input"))
    )
    (net (code "540") (name "Net-(IC83D-O)") (class "Default")
      (node (ref "IC83") (pin "11") (pinfunction "O_11") (pintype "output"))
      (node (ref "U$33") (pin "8") (pinfunction "I8_8") (pintype "input"))
    )
    (net (code "541") (name "Net-(IC84A-O)") (class "Default")
      (node (ref "IC84") (pin "3") (pinfunction "O_3") (pintype "output"))
      (node (ref "U$34") (pin "1") (pinfunction "I1_1") (pintype "input"))
    )
    (net (code "542") (name "Net-(IC84B-O)") (class "Default")
      (node (ref "IC84") (pin "6") (pinfunction "O_6") (pintype "output"))
      (node (ref "U$34") (pin "2") (pinfunction "I2_2") (pintype "input"))
    )
    (net (code "543") (name "Net-(IC84C-O)") (class "Default")
      (node (ref "IC84") (pin "8") (pinfunction "O_8") (pintype "output"))
      (node (ref "U$34") (pin "3") (pinfunction "I3_3") (pintype "input"))
    )
    (net (code "544") (name "Net-(IC84D-O)") (class "Default")
      (node (ref "IC84") (pin "11") (pinfunction "O_11") (pintype "output"))
      (node (ref "U$34") (pin "4") (pinfunction "I4_4") (pintype "input"))
    )
    (net (code "545") (name "Net-(IC85A-O)") (class "Default")
      (node (ref "IC85") (pin "3") (pinfunction "O_3") (pintype "output"))
      (node (ref "U$34") (pin "5") (pinfunction "I5_5") (pintype "input"))
    )
    (net (code "546") (name "Net-(IC85B-O)") (class "Default")
      (node (ref "IC85") (pin "6") (pinfunction "O_6") (pintype "output"))
      (node (ref "U$34") (pin "6") (pinfunction "I6_6") (pintype "input"))
    )
    (net (code "547") (name "Net-(IC85C-O)") (class "Default")
      (node (ref "IC85") (pin "8") (pinfunction "O_8") (pintype "output"))
      (node (ref "U$34") (pin "7") (pinfunction "I7_7") (pintype "input"))
    )
    (net (code "548") (name "Net-(IC85D-O)") (class "Default")
      (node (ref "IC85") (pin "11") (pinfunction "O_11") (pintype "output"))
      (node (ref "U$34") (pin "8") (pinfunction "I8_8") (pintype "input"))
    )
    (net (code "549") (name "Net-(IC86A-1D2)") (class "Default")
      (node (ref "IC86") (pin "2") (pinfunction "1Q1_2") (pintype "tri_state"))
      (node (ref "IC86") (pin "46") (pinfunction "1D2_46") (pintype "input"))
      (node (ref "IC87") (pin "1") (pinfunction "I0_1") (pintype "input"))
    )
    (net (code "550") (name "Net-(IC86A-1D3)") (class "Default")
      (node (ref "IC86") (pin "3") (pinfunction "1Q2_3") (pintype "tri_state"))
      (node (ref "IC86") (pin "44") (pinfunction "1D3_44") (pintype "input"))
      (node (ref "IC87") (pin "4") (pinfunction "I0_4") (pintype "input"))
    )
    (net (code "551") (name "Net-(IC86A-1D4)") (class "Default")
      (node (ref "IC86") (pin "43") (pinfunction "1D4_43") (pintype "input"))
      (node (ref "IC86") (pin "5") (pinfunction "1Q3_5") (pintype "tri_state"))
      (node (ref "IC87") (pin "9") (pinfunction "I0_9") (pintype "input"))
    )
    (net (code "552") (name "Net-(IC86A-1D5)") (class "Default")
      (node (ref "IC86") (pin "41") (pinfunction "1D5_41") (pintype "input"))
      (node (ref "IC86") (pin "6") (pinfunction "1Q4_6") (pintype "tri_state"))
      (node (ref "IC87") (pin "12") (pinfunction "I0_12") (pintype "input"))
    )
    (net (code "553") (name "Net-(IC86A-1D6)") (class "Default")
      (node (ref "IC86") (pin "40") (pinfunction "1D6_40") (pintype "input"))
      (node (ref "IC86") (pin "8") (pinfunction "1Q5_8") (pintype "tri_state"))
      (node (ref "IC88") (pin "1") (pinfunction "I0_1") (pintype "input"))
    )
    (net (code "554") (name "Net-(IC86A-1D7)") (class "Default")
      (node (ref "IC86") (pin "38") (pinfunction "1D7_38") (pintype "input"))
      (node (ref "IC86") (pin "9") (pinfunction "1Q6_9") (pintype "tri_state"))
      (node (ref "IC88") (pin "4") (pinfunction "I0_4") (pintype "input"))
    )
    (net (code "555") (name "Net-(IC86A-1D8)") (class "Default")
      (node (ref "IC86") (pin "11") (pinfunction "1Q7_11") (pintype "tri_state"))
      (node (ref "IC86") (pin "37") (pinfunction "1D8_37") (pintype "input"))
      (node (ref "IC88") (pin "9") (pinfunction "I0_9") (pintype "input"))
    )
    (net (code "556") (name "Net-(IC86A-1Q8)") (class "Default")
      (node (ref "IC86") (pin "12") (pinfunction "1Q8_12") (pintype "tri_state"))
      (node (ref "IC86") (pin "36") (pinfunction "2D1_36") (pintype "input"))
      (node (ref "IC88") (pin "12") (pinfunction "I0_12") (pintype "input"))
    )
    (net (code "557") (name "Net-(IC86A-2D2)") (class "Default")
      (node (ref "IC86") (pin "13") (pinfunction "2Q1_13") (pintype "tri_state"))
      (node (ref "IC86") (pin "35") (pinfunction "2D2_35") (pintype "input"))
      (node (ref "IC89") (pin "1") (pinfunction "I0_1") (pintype "input"))
    )
    (net (code "558") (name "Net-(IC86A-2D3)") (class "Default")
      (node (ref "IC86") (pin "14") (pinfunction "2Q2_14") (pintype "tri_state"))
      (node (ref "IC86") (pin "33") (pinfunction "2D3_33") (pintype "input"))
      (node (ref "IC89") (pin "4") (pinfunction "I0_4") (pintype "input"))
    )
    (net (code "559") (name "Net-(IC86A-2D4)") (class "Default")
      (node (ref "IC86") (pin "16") (pinfunction "2Q3_16") (pintype "tri_state"))
      (node (ref "IC86") (pin "32") (pinfunction "2D4_32") (pintype "input"))
      (node (ref "IC89") (pin "9") (pinfunction "I0_9") (pintype "input"))
    )
    (net (code "560") (name "Net-(IC86A-2D5)") (class "Default")
      (node (ref "IC86") (pin "17") (pinfunction "2Q4_17") (pintype "tri_state"))
      (node (ref "IC86") (pin "30") (pinfunction "2D5_30") (pintype "input"))
      (node (ref "IC89") (pin "12") (pinfunction "I0_12") (pintype "input"))
    )
    (net (code "561") (name "Net-(IC86A-2D6)") (class "Default")
      (node (ref "IC86") (pin "19") (pinfunction "2Q5_19") (pintype "tri_state"))
      (node (ref "IC86") (pin "29") (pinfunction "2D6_29") (pintype "input"))
      (node (ref "IC90") (pin "1") (pinfunction "I0_1") (pintype "input"))
    )
    (net (code "562") (name "Net-(IC86A-2D7)") (class "Default")
      (node (ref "IC86") (pin "20") (pinfunction "2Q6_20") (pintype "tri_state"))
      (node (ref "IC86") (pin "27") (pinfunction "2D7_27") (pintype "input"))
      (node (ref "IC90") (pin "4") (pinfunction "I0_4") (pintype "input"))
    )
    (net (code "563") (name "Net-(IC86A-2D8)") (class "Default")
      (node (ref "IC86") (pin "22") (pinfunction "2Q7_22") (pintype "tri_state"))
      (node (ref "IC86") (pin "26") (pinfunction "2D8_26") (pintype "input"))
      (node (ref "IC90") (pin "9") (pinfunction "I0_9") (pintype "input"))
    )
    (net (code "564") (name "Net-(IC87A-O)") (class "Default")
      (node (ref "IC87") (pin "3") (pinfunction "O_3") (pintype "output"))
      (node (ref "U$35") (pin "1") (pinfunction "I1_1") (pintype "input"))
    )
    (net (code "565") (name "Net-(IC87B-O)") (class "Default")
      (node (ref "IC87") (pin "6") (pinfunction "O_6") (pintype "output"))
      (node (ref "U$35") (pin "2") (pinfunction "I2_2") (pintype "input"))
    )
    (net (code "566") (name "Net-(IC87C-O)") (class "Default")
      (node (ref "IC87") (pin "8") (pinfunction "O_8") (pintype "output"))
      (node (ref "U$35") (pin "3") (pinfunction "I3_3") (pintype "input"))
    )
    (net (code "567") (name "Net-(IC87D-O)") (class "Default")
      (node (ref "IC87") (pin "11") (pinfunction "O_11") (pintype "output"))
      (node (ref "U$35") (pin "4") (pinfunction "I4_4") (pintype "input"))
    )
    (net (code "568") (name "Net-(IC88A-O)") (class "Default")
      (node (ref "IC88") (pin "3") (pinfunction "O_3") (pintype "output"))
      (node (ref "U$35") (pin "5") (pinfunction "I5_5") (pintype "input"))
    )
    (net (code "569") (name "Net-(IC88B-O)") (class "Default")
      (node (ref "IC88") (pin "6") (pinfunction "O_6") (pintype "output"))
      (node (ref "U$35") (pin "6") (pinfunction "I6_6") (pintype "input"))
    )
    (net (code "570") (name "Net-(IC88C-O)") (class "Default")
      (node (ref "IC88") (pin "8") (pinfunction "O_8") (pintype "output"))
      (node (ref "U$35") (pin "7") (pinfunction "I7_7") (pintype "input"))
    )
    (net (code "571") (name "Net-(IC88D-O)") (class "Default")
      (node (ref "IC88") (pin "11") (pinfunction "O_11") (pintype "output"))
      (node (ref "U$35") (pin "8") (pinfunction "I8_8") (pintype "input"))
    )
    (net (code "572") (name "Net-(IC89A-O)") (class "Default")
      (node (ref "IC89") (pin "3") (pinfunction "O_3") (pintype "output"))
      (node (ref "U$36") (pin "1") (pinfunction "I1_1") (pintype "input"))
    )
    (net (code "573") (name "Net-(IC89B-O)") (class "Default")
      (node (ref "IC89") (pin "6") (pinfunction "O_6") (pintype "output"))
      (node (ref "U$36") (pin "2") (pinfunction "I2_2") (pintype "input"))
    )
    (net (code "574") (name "Net-(IC89C-O)") (class "Default")
      (node (ref "IC89") (pin "8") (pinfunction "O_8") (pintype "output"))
      (node (ref "U$36") (pin "3") (pinfunction "I3_3") (pintype "input"))
    )
    (net (code "575") (name "Net-(IC89D-O)") (class "Default")
      (node (ref "IC89") (pin "11") (pinfunction "O_11") (pintype "output"))
      (node (ref "U$36") (pin "4") (pinfunction "I4_4") (pintype "input"))
    )
    (net (code "576") (name "Net-(IC90A-O)") (class "Default")
      (node (ref "IC90") (pin "3") (pinfunction "O_3") (pintype "output"))
      (node (ref "U$36") (pin "5") (pinfunction "I5_5") (pintype "input"))
    )
    (net (code "577") (name "Net-(IC90B-O)") (class "Default")
      (node (ref "IC90") (pin "6") (pinfunction "O_6") (pintype "output"))
      (node (ref "U$36") (pin "6") (pinfunction "I6_6") (pintype "input"))
    )
    (net (code "578") (name "Net-(IC90C-O)") (class "Default")
      (node (ref "IC90") (pin "8") (pinfunction "O_8") (pintype "output"))
      (node (ref "U$36") (pin "7") (pinfunction "I7_7") (pintype "input"))
    )
    (net (code "579") (name "Net-(IC90D-O)") (class "Default")
      (node (ref "IC90") (pin "11") (pinfunction "O_11") (pintype "output"))
      (node (ref "U$36") (pin "8") (pinfunction "I8_8") (pintype "input"))
    )
    (net (code "580") (name "Net-(IC91A-1D2)") (class "Default")
      (node (ref "IC91") (pin "2") (pinfunction "1Q1_2") (pintype "tri_state"))
      (node (ref "IC91") (pin "46") (pinfunction "1D2_46") (pintype "input"))
      (node (ref "IC92") (pin "1") (pinfunction "I0_1") (pintype "input"))
    )
    (net (code "581") (name "Net-(IC91A-1D3)") (class "Default")
      (node (ref "IC91") (pin "3") (pinfunction "1Q2_3") (pintype "tri_state"))
      (node (ref "IC91") (pin "44") (pinfunction "1D3_44") (pintype "input"))
      (node (ref "IC92") (pin "4") (pinfunction "I0_4") (pintype "input"))
    )
    (net (code "582") (name "Net-(IC91A-1D4)") (class "Default")
      (node (ref "IC91") (pin "43") (pinfunction "1D4_43") (pintype "input"))
      (node (ref "IC91") (pin "5") (pinfunction "1Q3_5") (pintype "tri_state"))
      (node (ref "IC92") (pin "9") (pinfunction "I0_9") (pintype "input"))
    )
    (net (code "583") (name "Net-(IC91A-1D5)") (class "Default")
      (node (ref "IC91") (pin "41") (pinfunction "1D5_41") (pintype "input"))
      (node (ref "IC91") (pin "6") (pinfunction "1Q4_6") (pintype "tri_state"))
      (node (ref "IC92") (pin "12") (pinfunction "I0_12") (pintype "input"))
    )
    (net (code "584") (name "Net-(IC91A-1D6)") (class "Default")
      (node (ref "IC91") (pin "40") (pinfunction "1D6_40") (pintype "input"))
      (node (ref "IC91") (pin "8") (pinfunction "1Q5_8") (pintype "tri_state"))
      (node (ref "IC93") (pin "1") (pinfunction "I0_1") (pintype "input"))
    )
    (net (code "585") (name "Net-(IC91A-1D7)") (class "Default")
      (node (ref "IC91") (pin "38") (pinfunction "1D7_38") (pintype "input"))
      (node (ref "IC91") (pin "9") (pinfunction "1Q6_9") (pintype "tri_state"))
      (node (ref "IC93") (pin "4") (pinfunction "I0_4") (pintype "input"))
    )
    (net (code "586") (name "Net-(IC91A-1D8)") (class "Default")
      (node (ref "IC91") (pin "11") (pinfunction "1Q7_11") (pintype "tri_state"))
      (node (ref "IC91") (pin "37") (pinfunction "1D8_37") (pintype "input"))
      (node (ref "IC93") (pin "9") (pinfunction "I0_9") (pintype "input"))
    )
    (net (code "587") (name "Net-(IC91A-1Q8)") (class "Default")
      (node (ref "IC91") (pin "12") (pinfunction "1Q8_12") (pintype "tri_state"))
      (node (ref "IC91") (pin "36") (pinfunction "2D1_36") (pintype "input"))
      (node (ref "IC93") (pin "12") (pinfunction "I0_12") (pintype "input"))
    )
    (net (code "588") (name "Net-(IC91A-2D2)") (class "Default")
      (node (ref "IC91") (pin "13") (pinfunction "2Q1_13") (pintype "tri_state"))
      (node (ref "IC91") (pin "35") (pinfunction "2D2_35") (pintype "input"))
      (node (ref "IC94") (pin "1") (pinfunction "I0_1") (pintype "input"))
    )
    (net (code "589") (name "Net-(IC91A-2D3)") (class "Default")
      (node (ref "IC91") (pin "14") (pinfunction "2Q2_14") (pintype "tri_state"))
      (node (ref "IC91") (pin "33") (pinfunction "2D3_33") (pintype "input"))
      (node (ref "IC94") (pin "4") (pinfunction "I0_4") (pintype "input"))
    )
    (net (code "590") (name "Net-(IC91A-2D4)") (class "Default")
      (node (ref "IC91") (pin "16") (pinfunction "2Q3_16") (pintype "tri_state"))
      (node (ref "IC91") (pin "32") (pinfunction "2D4_32") (pintype "input"))
      (node (ref "IC94") (pin "9") (pinfunction "I0_9") (pintype "input"))
    )
    (net (code "591") (name "Net-(IC91A-2D5)") (class "Default")
      (node (ref "IC91") (pin "17") (pinfunction "2Q4_17") (pintype "tri_state"))
      (node (ref "IC91") (pin "30") (pinfunction "2D5_30") (pintype "input"))
      (node (ref "IC94") (pin "12") (pinfunction "I0_12") (pintype "input"))
    )
    (net (code "592") (name "Net-(IC91A-2D6)") (class "Default")
      (node (ref "IC91") (pin "19") (pinfunction "2Q5_19") (pintype "tri_state"))
      (node (ref "IC91") (pin "29") (pinfunction "2D6_29") (pintype "input"))
      (node (ref "IC95") (pin "1") (pinfunction "I0_1") (pintype "input"))
    )
    (net (code "593") (name "Net-(IC91A-2D7)") (class "Default")
      (node (ref "IC91") (pin "20") (pinfunction "2Q6_20") (pintype "tri_state"))
      (node (ref "IC91") (pin "27") (pinfunction "2D7_27") (pintype "input"))
      (node (ref "IC95") (pin "4") (pinfunction "I0_4") (pintype "input"))
    )
    (net (code "594") (name "Net-(IC91A-2D8)") (class "Default")
      (node (ref "IC91") (pin "22") (pinfunction "2Q7_22") (pintype "tri_state"))
      (node (ref "IC91") (pin "26") (pinfunction "2D8_26") (pintype "input"))
      (node (ref "IC95") (pin "9") (pinfunction "I0_9") (pintype "input"))
    )
    (net (code "595") (name "Net-(IC91A-2Q8)") (class "Default")
      (node (ref "IC91") (pin "23") (pinfunction "2Q8_23") (pintype "tri_state"))
      (node (ref "IC95") (pin "12") (pinfunction "I0_12") (pintype "input"))
      (node (ref "IC96") (pin "47") (pinfunction "1D1_47") (pintype "input"))
    )
    (net (code "596") (name "Net-(IC92A-O)") (class "Default")
      (node (ref "IC92") (pin "3") (pinfunction "O_3") (pintype "output"))
      (node (ref "U$37") (pin "1") (pinfunction "I1_1") (pintype "input"))
    )
    (net (code "597") (name "Net-(IC92B-O)") (class "Default")
      (node (ref "IC92") (pin "6") (pinfunction "O_6") (pintype "output"))
      (node (ref "U$37") (pin "2") (pinfunction "I2_2") (pintype "input"))
    )
    (net (code "598") (name "Net-(IC92C-O)") (class "Default")
      (node (ref "IC92") (pin "8") (pinfunction "O_8") (pintype "output"))
      (node (ref "U$37") (pin "3") (pinfunction "I3_3") (pintype "input"))
    )
    (net (code "599") (name "Net-(IC92D-O)") (class "Default")
      (node (ref "IC92") (pin "11") (pinfunction "O_11") (pintype "output"))
      (node (ref "U$37") (pin "4") (pinfunction "I4_4") (pintype "input"))
    )
    (net (code "600") (name "Net-(IC93A-O)") (class "Default")
      (node (ref "IC93") (pin "3") (pinfunction "O_3") (pintype "output"))
      (node (ref "U$37") (pin "5") (pinfunction "I5_5") (pintype "input"))
    )
    (net (code "601") (name "Net-(IC93B-O)") (class "Default")
      (node (ref "IC93") (pin "6") (pinfunction "O_6") (pintype "output"))
      (node (ref "U$37") (pin "6") (pinfunction "I6_6") (pintype "input"))
    )
    (net (code "602") (name "Net-(IC93C-O)") (class "Default")
      (node (ref "IC93") (pin "8") (pinfunction "O_8") (pintype "output"))
      (node (ref "U$37") (pin "7") (pinfunction "I7_7") (pintype "input"))
    )
    (net (code "603") (name "Net-(IC93D-O)") (class "Default")
      (node (ref "IC93") (pin "11") (pinfunction "O_11") (pintype "output"))
      (node (ref "U$37") (pin "8") (pinfunction "I8_8") (pintype "input"))
    )
    (net (code "604") (name "Net-(IC94A-O)") (class "Default")
      (node (ref "IC94") (pin "3") (pinfunction "O_3") (pintype "output"))
      (node (ref "U$38") (pin "1") (pinfunction "I1_1") (pintype "input"))
    )
    (net (code "605") (name "Net-(IC94B-O)") (class "Default")
      (node (ref "IC94") (pin "6") (pinfunction "O_6") (pintype "output"))
      (node (ref "U$38") (pin "2") (pinfunction "I2_2") (pintype "input"))
    )
    (net (code "606") (name "Net-(IC94C-O)") (class "Default")
      (node (ref "IC94") (pin "8") (pinfunction "O_8") (pintype "output"))
      (node (ref "U$38") (pin "3") (pinfunction "I3_3") (pintype "input"))
    )
    (net (code "607") (name "Net-(IC94D-O)") (class "Default")
      (node (ref "IC94") (pin "11") (pinfunction "O_11") (pintype "output"))
      (node (ref "U$38") (pin "4") (pinfunction "I4_4") (pintype "input"))
    )
    (net (code "608") (name "Net-(IC95A-O)") (class "Default")
      (node (ref "IC95") (pin "3") (pinfunction "O_3") (pintype "output"))
      (node (ref "U$38") (pin "5") (pinfunction "I5_5") (pintype "input"))
    )
    (net (code "609") (name "Net-(IC95B-O)") (class "Default")
      (node (ref "IC95") (pin "6") (pinfunction "O_6") (pintype "output"))
      (node (ref "U$38") (pin "6") (pinfunction "I6_6") (pintype "input"))
    )
    (net (code "610") (name "Net-(IC95C-O)") (class "Default")
      (node (ref "IC95") (pin "8") (pinfunction "O_8") (pintype "output"))
      (node (ref "U$38") (pin "7") (pinfunction "I7_7") (pintype "input"))
    )
    (net (code "611") (name "Net-(IC95D-O)") (class "Default")
      (node (ref "IC95") (pin "11") (pinfunction "O_11") (pintype "output"))
      (node (ref "U$38") (pin "8") (pinfunction "I8_8") (pintype "input"))
    )
    (net (code "612") (name "Net-(IC96A-1D2)") (class "Default")
      (node (ref "IC96") (pin "2") (pinfunction "1Q1_2") (pintype "tri_state"))
      (node (ref "IC96") (pin "46") (pinfunction "1D2_46") (pintype "input"))
      (node (ref "IC97") (pin "1") (pinfunction "I0_1") (pintype "input"))
    )
    (net (code "613") (name "Net-(IC96A-1D3)") (class "Default")
      (node (ref "IC96") (pin "3") (pinfunction "1Q2_3") (pintype "tri_state"))
      (node (ref "IC96") (pin "44") (pinfunction "1D3_44") (pintype "input"))
      (node (ref "IC97") (pin "4") (pinfunction "I0_4") (pintype "input"))
    )
    (net (code "614") (name "Net-(IC96A-1D4)") (class "Default")
      (node (ref "IC96") (pin "43") (pinfunction "1D4_43") (pintype "input"))
      (node (ref "IC96") (pin "5") (pinfunction "1Q3_5") (pintype "tri_state"))
      (node (ref "IC97") (pin "9") (pinfunction "I0_9") (pintype "input"))
    )
    (net (code "615") (name "Net-(IC96A-1D5)") (class "Default")
      (node (ref "IC96") (pin "41") (pinfunction "1D5_41") (pintype "input"))
      (node (ref "IC96") (pin "6") (pinfunction "1Q4_6") (pintype "tri_state"))
      (node (ref "IC97") (pin "12") (pinfunction "I0_12") (pintype "input"))
    )
    (net (code "616") (name "Net-(IC96A-1D6)") (class "Default")
      (node (ref "IC96") (pin "40") (pinfunction "1D6_40") (pintype "input"))
      (node (ref "IC96") (pin "8") (pinfunction "1Q5_8") (pintype "tri_state"))
      (node (ref "IC98") (pin "1") (pinfunction "I0_1") (pintype "input"))
    )
    (net (code "617") (name "Net-(IC96A-1D7)") (class "Default")
      (node (ref "IC96") (pin "38") (pinfunction "1D7_38") (pintype "input"))
      (node (ref "IC96") (pin "9") (pinfunction "1Q6_9") (pintype "tri_state"))
      (node (ref "IC98") (pin "4") (pinfunction "I0_4") (pintype "input"))
    )
    (net (code "618") (name "Net-(IC96A-1D8)") (class "Default")
      (node (ref "IC96") (pin "11") (pinfunction "1Q7_11") (pintype "tri_state"))
      (node (ref "IC96") (pin "37") (pinfunction "1D8_37") (pintype "input"))
      (node (ref "IC98") (pin "9") (pinfunction "I0_9") (pintype "input"))
    )
    (net (code "619") (name "Net-(IC96A-1Q8)") (class "Default")
      (node (ref "IC96") (pin "12") (pinfunction "1Q8_12") (pintype "tri_state"))
      (node (ref "IC96") (pin "36") (pinfunction "2D1_36") (pintype "input"))
      (node (ref "IC98") (pin "12") (pinfunction "I0_12") (pintype "input"))
    )
    (net (code "620") (name "Net-(IC96A-2D2)") (class "Default")
      (node (ref "IC96") (pin "13") (pinfunction "2Q1_13") (pintype "tri_state"))
      (node (ref "IC96") (pin "35") (pinfunction "2D2_35") (pintype "input"))
      (node (ref "IC99") (pin "1") (pinfunction "I0_1") (pintype "input"))
    )
    (net (code "621") (name "Net-(IC96A-2D3)") (class "Default")
      (node (ref "IC96") (pin "14") (pinfunction "2Q2_14") (pintype "tri_state"))
      (node (ref "IC96") (pin "33") (pinfunction "2D3_33") (pintype "input"))
      (node (ref "IC99") (pin "4") (pinfunction "I0_4") (pintype "input"))
    )
    (net (code "622") (name "Net-(IC96A-2D4)") (class "Default")
      (node (ref "IC96") (pin "16") (pinfunction "2Q3_16") (pintype "tri_state"))
      (node (ref "IC96") (pin "32") (pinfunction "2D4_32") (pintype "input"))
      (node (ref "IC99") (pin "9") (pinfunction "I0_9") (pintype "input"))
    )
    (net (code "623") (name "Net-(IC96A-2D5)") (class "Default")
      (node (ref "IC96") (pin "17") (pinfunction "2Q4_17") (pintype "tri_state"))
      (node (ref "IC96") (pin "30") (pinfunction "2D5_30") (pintype "input"))
      (node (ref "IC99") (pin "12") (pinfunction "I0_12") (pintype "input"))
    )
    (net (code "624") (name "Net-(IC97A-O)") (class "Default")
      (node (ref "IC97") (pin "3") (pinfunction "O_3") (pintype "output"))
      (node (ref "U$39") (pin "1") (pinfunction "I1_1") (pintype "input"))
    )
    (net (code "625") (name "Net-(IC97B-O)") (class "Default")
      (node (ref "IC97") (pin "6") (pinfunction "O_6") (pintype "output"))
      (node (ref "U$39") (pin "2") (pinfunction "I2_2") (pintype "input"))
    )
    (net (code "626") (name "Net-(IC97C-O)") (class "Default")
      (node (ref "IC97") (pin "8") (pinfunction "O_8") (pintype "output"))
      (node (ref "U$39") (pin "3") (pinfunction "I3_3") (pintype "input"))
    )
    (net (code "627") (name "Net-(IC97D-O)") (class "Default")
      (node (ref "IC97") (pin "11") (pinfunction "O_11") (pintype "output"))
      (node (ref "U$39") (pin "4") (pinfunction "I4_4") (pintype "input"))
    )
    (net (code "628") (name "Net-(IC98A-O)") (class "Default")
      (node (ref "IC98") (pin "3") (pinfunction "O_3") (pintype "output"))
      (node (ref "U$39") (pin "5") (pinfunction "I5_5") (pintype "input"))
    )
    (net (code "629") (name "Net-(IC98B-O)") (class "Default")
      (node (ref "IC98") (pin "6") (pinfunction "O_6") (pintype "output"))
      (node (ref "U$39") (pin "6") (pinfunction "I6_6") (pintype "input"))
    )
    (net (code "630") (name "Net-(IC98C-O)") (class "Default")
      (node (ref "IC98") (pin "8") (pinfunction "O_8") (pintype "output"))
      (node (ref "U$39") (pin "7") (pinfunction "I7_7") (pintype "input"))
    )
    (net (code "631") (name "Net-(IC98D-O)") (class "Default")
      (node (ref "IC98") (pin "11") (pinfunction "O_11") (pintype "output"))
      (node (ref "U$39") (pin "8") (pinfunction "I8_8") (pintype "input"))
    )
    (net (code "632") (name "Net-(IC99A-O)") (class "Default")
      (node (ref "IC99") (pin "3") (pinfunction "O_3") (pintype "output"))
      (node (ref "U$40") (pin "1") (pinfunction "I1_1") (pintype "input"))
    )
    (net (code "633") (name "Net-(IC99B-O)") (class "Default")
      (node (ref "IC99") (pin "6") (pinfunction "O_6") (pintype "output"))
      (node (ref "U$40") (pin "2") (pinfunction "I2_2") (pintype "input"))
    )
    (net (code "634") (name "Net-(IC99C-O)") (class "Default")
      (node (ref "IC99") (pin "8") (pinfunction "O_8") (pintype "output"))
      (node (ref "U$40") (pin "3") (pinfunction "I3_3") (pintype "input"))
    )
    (net (code "635") (name "Net-(IC99D-O)") (class "Default")
      (node (ref "IC99") (pin "11") (pinfunction "O_11") (pintype "output"))
      (node (ref "U$40") (pin "4") (pinfunction "I4_4") (pintype "input"))
    )
    (net (code "636") (name "Net-(IC100A-I0)") (class "Default")
      (node (ref "IC100") (pin "1") (pinfunction "I0_1") (pintype "input"))
      (node (ref "IC96") (pin "19") (pinfunction "2Q5_19") (pintype "tri_state"))
      (node (ref "IC96") (pin "29") (pinfunction "2D6_29") (pintype "input"))
    )
    (net (code "637") (name "Net-(IC100A-I1)") (class "Default")
      (node (ref "IC100") (pin "10") (pinfunction "I1_10") (pintype "input"))
      (node (ref "IC100") (pin "13") (pinfunction "I1_13") (pintype "input"))
      (node (ref "IC100") (pin "2") (pinfunction "I1_2") (pintype "input"))
      (node (ref "IC100") (pin "5") (pinfunction "I1_5") (pintype "input"))
      (node (ref "IC102") (pin "12") (pinfunction "1Q8_12") (pintype "tri_state"))
      (node (ref "IC102") (pin "36") (pinfunction "2D1_36") (pintype "input"))
      (node (ref "IC99") (pin "10") (pinfunction "I1_10") (pintype "input"))
      (node (ref "IC99") (pin "13") (pinfunction "I1_13") (pintype "input"))
      (node (ref "IC99") (pin "2") (pinfunction "I1_2") (pintype "input"))
      (node (ref "IC99") (pin "5") (pinfunction "I1_5") (pintype "input"))
    )
    (net (code "638") (name "Net-(IC100A-O)") (class "Default")
      (node (ref "IC100") (pin "3") (pinfunction "O_3") (pintype "output"))
      (node (ref "U$40") (pin "5") (pinfunction "I5_5") (pintype "input"))
    )
    (net (code "639") (name "Net-(IC100B-I0)") (class "Default")
      (node (ref "IC100") (pin "4") (pinfunction "I0_4") (pintype "input"))
      (node (ref "IC96") (pin "20") (pinfunction "2Q6_20") (pintype "tri_state"))
      (node (ref "IC96") (pin "27") (pinfunction "2D7_27") (pintype "input"))
    )
    (net (code "640") (name "Net-(IC100B-O)") (class "Default")
      (node (ref "IC100") (pin "6") (pinfunction "O_6") (pintype "output"))
      (node (ref "U$40") (pin "6") (pinfunction "I6_6") (pintype "input"))
    )
    (net (code "641") (name "Net-(IC100C-I0)") (class "Default")
      (node (ref "IC100") (pin "9") (pinfunction "I0_9") (pintype "input"))
      (node (ref "IC96") (pin "22") (pinfunction "2Q7_22") (pintype "tri_state"))
      (node (ref "IC96") (pin "26") (pinfunction "2D8_26") (pintype "input"))
    )
    (net (code "642") (name "Net-(IC100C-O)") (class "Default")
      (node (ref "IC100") (pin "8") (pinfunction "O_8") (pintype "output"))
      (node (ref "U$40") (pin "7") (pinfunction "I7_7") (pintype "input"))
    )
    (net (code "643") (name "Net-(IC100D-I0)") (class "Default")
      (node (ref "IC100") (pin "12") (pinfunction "I0_12") (pintype "input"))
      (node (ref "IC81") (pin "47") (pinfunction "1D1_47") (pintype "input"))
      (node (ref "IC96") (pin "23") (pinfunction "2Q8_23") (pintype "tri_state"))
    )
    (net (code "644") (name "Net-(IC100D-O)") (class "Default")
      (node (ref "IC100") (pin "11") (pinfunction "O_11") (pintype "output"))
      (node (ref "U$40") (pin "8") (pinfunction "I8_8") (pintype "input"))
    )
    (net (code "645") (name "Net-(IC101A-1CLK)") (class "Default")
      (node (ref "IC101") (pin "25") (pinfunction "2CLK_25") (pintype "input"))
      (node (ref "IC101") (pin "48") (pinfunction "1CLK_48") (pintype "input"))
      (node (ref "IC102") (pin "25") (pinfunction "2CLK_25") (pintype "input"))
      (node (ref "IC102") (pin "48") (pinfunction "1CLK_48") (pintype "input"))
      (node (ref "IC103") (pin "25") (pinfunction "2CLK_25") (pintype "input"))
      (node (ref "IC103") (pin "48") (pinfunction "1CLK_48") (pintype "input"))
      (node (ref "X11") (pin "6") (pinfunction "S_6") (pintype "passive"))
    )
    (net (code "646") (name "Net-(IC101A-1D1)") (class "Default")
      (node (ref "IC101") (pin "47") (pinfunction "1D1_47") (pintype "input"))
      (node (ref "X11") (pin "3") (pinfunction "S_3") (pintype "passive"))
    )
    (net (code "647") (name "Net-(IC101A-1D2)") (class "Default")
      (node (ref "IC101") (pin "2") (pinfunction "1Q1_2") (pintype "tri_state"))
      (node (ref "IC101") (pin "46") (pinfunction "1D2_46") (pintype "input"))
      (node (ref "IC22") (pin "10") (pinfunction "I1_10") (pintype "input"))
      (node (ref "IC22") (pin "13") (pinfunction "I1_13") (pintype "input"))
      (node (ref "IC22") (pin "2") (pinfunction "I1_2") (pintype "input"))
      (node (ref "IC22") (pin "5") (pinfunction "I1_5") (pintype "input"))
      (node (ref "IC23") (pin "10") (pinfunction "I1_10") (pintype "input"))
      (node (ref "IC23") (pin "13") (pinfunction "I1_13") (pintype "input"))
      (node (ref "IC23") (pin "2") (pinfunction "I1_2") (pintype "input"))
      (node (ref "IC23") (pin "5") (pinfunction "I1_5") (pintype "input"))
    )
    (net (code "648") (name "Net-(IC101A-1D3)") (class "Default")
      (node (ref "IC101") (pin "3") (pinfunction "1Q2_3") (pintype "tri_state"))
      (node (ref "IC101") (pin "44") (pinfunction "1D3_44") (pintype "input"))
      (node (ref "IC24") (pin "10") (pinfunction "I1_10") (pintype "input"))
      (node (ref "IC24") (pin "13") (pinfunction "I1_13") (pintype "input"))
      (node (ref "IC24") (pin "2") (pinfunction "I1_2") (pintype "input"))
      (node (ref "IC24") (pin "5") (pinfunction "I1_5") (pintype "input"))
      (node (ref "IC25") (pin "10") (pinfunction "I1_10") (pintype "input"))
      (node (ref "IC25") (pin "13") (pinfunction "I1_13") (pintype "input"))
      (node (ref "IC25") (pin "2") (pinfunction "I1_2") (pintype "input"))
      (node (ref "IC25") (pin "5") (pinfunction "I1_5") (pintype "input"))
    )
    (net (code "649") (name "Net-(IC101A-1D4)") (class "Default")
      (node (ref "IC101") (pin "43") (pinfunction "1D4_43") (pintype "input"))
      (node (ref "IC101") (pin "5") (pinfunction "1Q3_5") (pintype "tri_state"))
      (node (ref "IC27") (pin "10") (pinfunction "I1_10") (pintype "input"))
      (node (ref "IC27") (pin "13") (pinfunction "I1_13") (pintype "input"))
      (node (ref "IC27") (pin "2") (pinfunction "I1_2") (pintype "input"))
      (node (ref "IC27") (pin "5") (pinfunction "I1_5") (pintype "input"))
      (node (ref "IC28") (pin "10") (pinfunction "I1_10") (pintype "input"))
      (node (ref "IC28") (pin "13") (pinfunction "I1_13") (pintype "input"))
      (node (ref "IC28") (pin "2") (pinfunction "I1_2") (pintype "input"))
      (node (ref "IC28") (pin "5") (pinfunction "I1_5") (pintype "input"))
    )
    (net (code "650") (name "Net-(IC101A-1D5)") (class "Default")
      (node (ref "IC101") (pin "41") (pinfunction "1D5_41") (pintype "input"))
      (node (ref "IC101") (pin "6") (pinfunction "1Q4_6") (pintype "tri_state"))
      (node (ref "IC29") (pin "10") (pinfunction "I1_10") (pintype "input"))
      (node (ref "IC29") (pin "13") (pinfunction "I1_13") (pintype "input"))
      (node (ref "IC29") (pin "2") (pinfunction "I1_2") (pintype "input"))
      (node (ref "IC29") (pin "5") (pinfunction "I1_5") (pintype "input"))
      (node (ref "IC30") (pin "10") (pinfunction "I1_10") (pintype "input"))
      (node (ref "IC30") (pin "13") (pinfunction "I1_13") (pintype "input"))
      (node (ref "IC30") (pin "2") (pinfunction "I1_2") (pintype "input"))
      (node (ref "IC30") (pin "5") (pinfunction "I1_5") (pintype "input"))
    )
    (net (code "651") (name "Net-(IC101A-1D6)") (class "Default")
      (node (ref "IC10") (pin "10") (pinfunction "I1_10") (pintype "input"))
      (node (ref "IC10") (pin "13") (pinfunction "I1_13") (pintype "input"))
      (node (ref "IC10") (pin "2") (pinfunction "I1_2") (pintype "input"))
      (node (ref "IC10") (pin "5") (pinfunction "I1_5") (pintype "input"))
      (node (ref "IC101") (pin "40") (pinfunction "1D6_40") (pintype "input"))
      (node (ref "IC101") (pin "8") (pinfunction "1Q5_8") (pintype "tri_state"))
      (node (ref "IC7") (pin "10") (pinfunction "I1_10") (pintype "input"))
      (node (ref "IC7") (pin "13") (pinfunction "I1_13") (pintype "input"))
      (node (ref "IC7") (pin "2") (pinfunction "I1_2") (pintype "input"))
      (node (ref "IC7") (pin "5") (pinfunction "I1_5") (pintype "input"))
    )
    (net (code "652") (name "Net-(IC101A-1D7)") (class "Default")
      (node (ref "IC101") (pin "38") (pinfunction "1D7_38") (pintype "input"))
      (node (ref "IC101") (pin "9") (pinfunction "1Q6_9") (pintype "tri_state"))
      (node (ref "IC14") (pin "10") (pinfunction "I1_10") (pintype "input"))
      (node (ref "IC14") (pin "13") (pinfunction "I1_13") (pintype "input"))
      (node (ref "IC14") (pin "2") (pinfunction "I1_2") (pintype "input"))
      (node (ref "IC14") (pin "5") (pinfunction "I1_5") (pintype "input"))
      (node (ref "IC15") (pin "10") (pinfunction "I1_10") (pintype "input"))
      (node (ref "IC15") (pin "13") (pinfunction "I1_13") (pintype "input"))
      (node (ref "IC15") (pin "2") (pinfunction "I1_2") (pintype "input"))
      (node (ref "IC15") (pin "5") (pinfunction "I1_5") (pintype "input"))
    )
    (net (code "653") (name "Net-(IC101A-1D8)") (class "Default")
      (node (ref "IC101") (pin "11") (pinfunction "1Q7_11") (pintype "tri_state"))
      (node (ref "IC101") (pin "37") (pinfunction "1D8_37") (pintype "input"))
      (node (ref "IC17") (pin "10") (pinfunction "I1_10") (pintype "input"))
      (node (ref "IC17") (pin "13") (pinfunction "I1_13") (pintype "input"))
      (node (ref "IC17") (pin "2") (pinfunction "I1_2") (pintype "input"))
      (node (ref "IC17") (pin "5") (pinfunction "I1_5") (pintype "input"))
      (node (ref "IC18") (pin "10") (pinfunction "I1_10") (pintype "input"))
      (node (ref "IC18") (pin "13") (pinfunction "I1_13") (pintype "input"))
      (node (ref "IC18") (pin "2") (pinfunction "I1_2") (pintype "input"))
      (node (ref "IC18") (pin "5") (pinfunction "I1_5") (pintype "input"))
    )
    (net (code "654") (name "Net-(IC101A-1Q8)") (class "Default")
      (node (ref "IC101") (pin "12") (pinfunction "1Q8_12") (pintype "tri_state"))
      (node (ref "IC101") (pin "36") (pinfunction "2D1_36") (pintype "input"))
      (node (ref "IC19") (pin "10") (pinfunction "I1_10") (pintype "input"))
      (node (ref "IC19") (pin "13") (pinfunction "I1_13") (pintype "input"))
      (node (ref "IC19") (pin "2") (pinfunction "I1_2") (pintype "input"))
      (node (ref "IC19") (pin "5") (pinfunction "I1_5") (pintype "input"))
      (node (ref "IC20") (pin "10") (pinfunction "I1_10") (pintype "input"))
      (node (ref "IC20") (pin "13") (pinfunction "I1_13") (pintype "input"))
      (node (ref "IC20") (pin "2") (pinfunction "I1_2") (pintype "input"))
      (node (ref "IC20") (pin "5") (pinfunction "I1_5") (pintype "input"))
    )
    (net (code "655") (name "Net-(IC101A-2D2)") (class "Default")
      (node (ref "IC101") (pin "13") (pinfunction "2Q1_13") (pintype "tri_state"))
      (node (ref "IC101") (pin "35") (pinfunction "2D2_35") (pintype "input"))
      (node (ref "IC2") (pin "10") (pinfunction "I1_10") (pintype "input"))
      (node (ref "IC2") (pin "13") (pinfunction "I1_13") (pintype "input"))
      (node (ref "IC2") (pin "2") (pinfunction "I1_2") (pintype "input"))
      (node (ref "IC2") (pin "5") (pinfunction "I1_5") (pintype "input"))
      (node (ref "IC4") (pin "10") (pinfunction "I1_10") (pintype "input"))
      (node (ref "IC4") (pin "13") (pinfunction "I1_13") (pintype "input"))
      (node (ref "IC4") (pin "2") (pinfunction "I1_2") (pintype "input"))
      (node (ref "IC4") (pin "5") (pinfunction "I1_5") (pintype "input"))
    )
    (net (code "656") (name "Net-(IC101A-2D3)") (class "Default")
      (node (ref "IC101") (pin "14") (pinfunction "2Q2_14") (pintype "tri_state"))
      (node (ref "IC101") (pin "33") (pinfunction "2D3_33") (pintype "input"))
      (node (ref "IC5") (pin "10") (pinfunction "I1_10") (pintype "input"))
      (node (ref "IC5") (pin "13") (pinfunction "I1_13") (pintype "input"))
      (node (ref "IC5") (pin "2") (pinfunction "I1_2") (pintype "input"))
      (node (ref "IC5") (pin "5") (pinfunction "I1_5") (pintype "input"))
      (node (ref "IC6") (pin "10") (pinfunction "I1_10") (pintype "input"))
      (node (ref "IC6") (pin "13") (pinfunction "I1_13") (pintype "input"))
      (node (ref "IC6") (pin "2") (pinfunction "I1_2") (pintype "input"))
      (node (ref "IC6") (pin "5") (pinfunction "I1_5") (pintype "input"))
    )
    (net (code "657") (name "Net-(IC101A-2D4)") (class "Default")
      (node (ref "IC101") (pin "16") (pinfunction "2Q3_16") (pintype "tri_state"))
      (node (ref "IC101") (pin "32") (pinfunction "2D4_32") (pintype "input"))
      (node (ref "IC11") (pin "10") (pinfunction "I1_10") (pintype "input"))
      (node (ref "IC11") (pin "13") (pinfunction "I1_13") (pintype "input"))
      (node (ref "IC11") (pin "2") (pinfunction "I1_2") (pintype "input"))
      (node (ref "IC11") (pin "5") (pinfunction "I1_5") (pintype "input"))
      (node (ref "IC9") (pin "10") (pinfunction "I1_10") (pintype "input"))
      (node (ref "IC9") (pin "13") (pinfunction "I1_13") (pintype "input"))
      (node (ref "IC9") (pin "2") (pinfunction "I1_2") (pintype "input"))
      (node (ref "IC9") (pin "5") (pinfunction "I1_5") (pintype "input"))
    )
    (net (code "658") (name "Net-(IC101A-2D5)") (class "Default")
      (node (ref "IC101") (pin "17") (pinfunction "2Q4_17") (pintype "tri_state"))
      (node (ref "IC101") (pin "30") (pinfunction "2D5_30") (pintype "input"))
      (node (ref "IC12") (pin "10") (pinfunction "I1_10") (pintype "input"))
      (node (ref "IC12") (pin "13") (pinfunction "I1_13") (pintype "input"))
      (node (ref "IC12") (pin "2") (pinfunction "I1_2") (pintype "input"))
      (node (ref "IC12") (pin "5") (pinfunction "I1_5") (pintype "input"))
      (node (ref "IC13") (pin "10") (pinfunction "I1_10") (pintype "input"))
      (node (ref "IC13") (pin "13") (pinfunction "I1_13") (pintype "input"))
      (node (ref "IC13") (pin "2") (pinfunction "I1_2") (pintype "input"))
      (node (ref "IC13") (pin "5") (pinfunction "I1_5") (pintype "input"))
    )
    (net (code "659") (name "Net-(IC101A-2D6)") (class "Default")
      (node (ref "IC101") (pin "19") (pinfunction "2Q5_19") (pintype "tri_state"))
      (node (ref "IC101") (pin "29") (pinfunction "2D6_29") (pintype "input"))
      (node (ref "IC52") (pin "10") (pinfunction "I1_10") (pintype "input"))
      (node (ref "IC52") (pin "13") (pinfunction "I1_13") (pintype "input"))
      (node (ref "IC52") (pin "2") (pinfunction "I1_2") (pintype "input"))
      (node (ref "IC52") (pin "5") (pinfunction "I1_5") (pintype "input"))
      (node (ref "IC53") (pin "10") (pinfunction "I1_10") (pintype "input"))
      (node (ref "IC53") (pin "13") (pinfunction "I1_13") (pintype "input"))
      (node (ref "IC53") (pin "2") (pinfunction "I1_2") (pintype "input"))
      (node (ref "IC53") (pin "5") (pinfunction "I1_5") (pintype "input"))
    )
    (net (code "660") (name "Net-(IC101A-2D7)") (class "Default")
      (node (ref "IC101") (pin "20") (pinfunction "2Q6_20") (pintype "tri_state"))
      (node (ref "IC101") (pin "27") (pinfunction "2D7_27") (pintype "input"))
      (node (ref "IC54") (pin "10") (pinfunction "I1_10") (pintype "input"))
      (node (ref "IC54") (pin "13") (pinfunction "I1_13") (pintype "input"))
      (node (ref "IC54") (pin "2") (pinfunction "I1_2") (pintype "input"))
      (node (ref "IC54") (pin "5") (pinfunction "I1_5") (pintype "input"))
      (node (ref "IC55") (pin "10") (pinfunction "I1_10") (pintype "input"))
      (node (ref "IC55") (pin "13") (pinfunction "I1_13") (pintype "input"))
      (node (ref "IC55") (pin "2") (pinfunction "I1_2") (pintype "input"))
      (node (ref "IC55") (pin "5") (pinfunction "I1_5") (pintype "input"))
    )
    (net (code "661") (name "Net-(IC101A-2D8)") (class "Default")
      (node (ref "IC101") (pin "22") (pinfunction "2Q7_22") (pintype "tri_state"))
      (node (ref "IC101") (pin "26") (pinfunction "2D8_26") (pintype "input"))
      (node (ref "IC57") (pin "10") (pinfunction "I1_10") (pintype "input"))
      (node (ref "IC57") (pin "13") (pinfunction "I1_13") (pintype "input"))
      (node (ref "IC57") (pin "2") (pinfunction "I1_2") (pintype "input"))
      (node (ref "IC57") (pin "5") (pinfunction "I1_5") (pintype "input"))
      (node (ref "IC58") (pin "10") (pinfunction "I1_10") (pintype "input"))
      (node (ref "IC58") (pin "13") (pinfunction "I1_13") (pintype "input"))
      (node (ref "IC58") (pin "2") (pinfunction "I1_2") (pintype "input"))
      (node (ref "IC58") (pin "5") (pinfunction "I1_5") (pintype "input"))
    )
    (net (code "662") (name "Net-(IC101A-2Q8)") (class "Default")
      (node (ref "IC101") (pin "23") (pinfunction "2Q8_23") (pintype "tri_state"))
      (node (ref "IC102") (pin "47") (pinfunction "1D1_47") (pintype "input"))
      (node (ref "IC59") (pin "10") (pinfunction "I1_10") (pintype "input"))
      (node (ref "IC59") (pin "13") (pinfunction "I1_13") (pintype "input"))
      (node (ref "IC59") (pin "2") (pinfunction "I1_2") (pintype "input"))
      (node (ref "IC59") (pin "5") (pinfunction "I1_5") (pintype "input"))
      (node (ref "IC60") (pin "10") (pinfunction "I1_10") (pintype "input"))
      (node (ref "IC60") (pin "13") (pinfunction "I1_13") (pintype "input"))
      (node (ref "IC60") (pin "2") (pinfunction "I1_2") (pintype "input"))
      (node (ref "IC60") (pin "5") (pinfunction "I1_5") (pintype "input"))
    )
    (net (code "663") (name "Net-(IC102A-1D2)") (class "Default")
      (node (ref "IC102") (pin "2") (pinfunction "1Q1_2") (pintype "tri_state"))
      (node (ref "IC102") (pin "46") (pinfunction "1D2_46") (pintype "input"))
      (node (ref "IC42") (pin "10") (pinfunction "I1_10") (pintype "input"))
      (node (ref "IC42") (pin "13") (pinfunction "I1_13") (pintype "input"))
      (node (ref "IC42") (pin "2") (pinfunction "I1_2") (pintype "input"))
      (node (ref "IC42") (pin "5") (pinfunction "I1_5") (pintype "input"))
      (node (ref "IC43") (pin "10") (pinfunction "I1_10") (pintype "input"))
      (node (ref "IC43") (pin "13") (pinfunction "I1_13") (pintype "input"))
      (node (ref "IC43") (pin "2") (pinfunction "I1_2") (pintype "input"))
      (node (ref "IC43") (pin "5") (pinfunction "I1_5") (pintype "input"))
    )
    (net (code "664") (name "Net-(IC102A-1D3)") (class "Default")
      (node (ref "IC102") (pin "3") (pinfunction "1Q2_3") (pintype "tri_state"))
      (node (ref "IC102") (pin "44") (pinfunction "1D3_44") (pintype "input"))
      (node (ref "IC44") (pin "10") (pinfunction "I1_10") (pintype "input"))
      (node (ref "IC44") (pin "13") (pinfunction "I1_13") (pintype "input"))
      (node (ref "IC44") (pin "2") (pinfunction "I1_2") (pintype "input"))
      (node (ref "IC44") (pin "5") (pinfunction "I1_5") (pintype "input"))
      (node (ref "IC45") (pin "10") (pinfunction "I1_10") (pintype "input"))
      (node (ref "IC45") (pin "13") (pinfunction "I1_13") (pintype "input"))
      (node (ref "IC45") (pin "2") (pinfunction "I1_2") (pintype "input"))
      (node (ref "IC45") (pin "5") (pinfunction "I1_5") (pintype "input"))
    )
    (net (code "665") (name "Net-(IC102A-1D4)") (class "Default")
      (node (ref "IC102") (pin "43") (pinfunction "1D4_43") (pintype "input"))
      (node (ref "IC102") (pin "5") (pinfunction "1Q3_5") (pintype "tri_state"))
      (node (ref "IC47") (pin "10") (pinfunction "I1_10") (pintype "input"))
      (node (ref "IC47") (pin "13") (pinfunction "I1_13") (pintype "input"))
      (node (ref "IC47") (pin "2") (pinfunction "I1_2") (pintype "input"))
      (node (ref "IC47") (pin "5") (pinfunction "I1_5") (pintype "input"))
      (node (ref "IC48") (pin "10") (pinfunction "I1_10") (pintype "input"))
      (node (ref "IC48") (pin "13") (pinfunction "I1_13") (pintype "input"))
      (node (ref "IC48") (pin "2") (pinfunction "I1_2") (pintype "input"))
      (node (ref "IC48") (pin "5") (pinfunction "I1_5") (pintype "input"))
    )
    (net (code "666") (name "Net-(IC102A-1D5)") (class "Default")
      (node (ref "IC102") (pin "41") (pinfunction "1D5_41") (pintype "input"))
      (node (ref "IC102") (pin "6") (pinfunction "1Q4_6") (pintype "tri_state"))
      (node (ref "IC49") (pin "10") (pinfunction "I1_10") (pintype "input"))
      (node (ref "IC49") (pin "13") (pinfunction "I1_13") (pintype "input"))
      (node (ref "IC49") (pin "2") (pinfunction "I1_2") (pintype "input"))
      (node (ref "IC49") (pin "5") (pinfunction "I1_5") (pintype "input"))
      (node (ref "IC50") (pin "10") (pinfunction "I1_10") (pintype "input"))
      (node (ref "IC50") (pin "13") (pinfunction "I1_13") (pintype "input"))
      (node (ref "IC50") (pin "2") (pinfunction "I1_2") (pintype "input"))
      (node (ref "IC50") (pin "5") (pinfunction "I1_5") (pintype "input"))
    )
    (net (code "667") (name "Net-(IC102A-1D6)") (class "Default")
      (node (ref "IC102") (pin "40") (pinfunction "1D6_40") (pintype "input"))
      (node (ref "IC102") (pin "8") (pinfunction "1Q5_8") (pintype "tri_state"))
      (node (ref "IC92") (pin "10") (pinfunction "I1_10") (pintype "input"))
      (node (ref "IC92") (pin "13") (pinfunction "I1_13") (pintype "input"))
      (node (ref "IC92") (pin "2") (pinfunction "I1_2") (pintype "input"))
      (node (ref "IC92") (pin "5") (pinfunction "I1_5") (pintype "input"))
      (node (ref "IC93") (pin "10") (pinfunction "I1_10") (pintype "input"))
      (node (ref "IC93") (pin "13") (pinfunction "I1_13") (pintype "input"))
      (node (ref "IC93") (pin "2") (pinfunction "I1_2") (pintype "input"))
      (node (ref "IC93") (pin "5") (pinfunction "I1_5") (pintype "input"))
    )
    (net (code "668") (name "Net-(IC102A-1D7)") (class "Default")
      (node (ref "IC102") (pin "38") (pinfunction "1D7_38") (pintype "input"))
      (node (ref "IC102") (pin "9") (pinfunction "1Q6_9") (pintype "tri_state"))
      (node (ref "IC94") (pin "10") (pinfunction "I1_10") (pintype "input"))
      (node (ref "IC94") (pin "13") (pinfunction "I1_13") (pintype "input"))
      (node (ref "IC94") (pin "2") (pinfunction "I1_2") (pintype "input"))
      (node (ref "IC94") (pin "5") (pinfunction "I1_5") (pintype "input"))
      (node (ref "IC95") (pin "10") (pinfunction "I1_10") (pintype "input"))
      (node (ref "IC95") (pin "13") (pinfunction "I1_13") (pintype "input"))
      (node (ref "IC95") (pin "2") (pinfunction "I1_2") (pintype "input"))
      (node (ref "IC95") (pin "5") (pinfunction "I1_5") (pintype "input"))
    )
    (net (code "669") (name "Net-(IC102A-1D8)") (class "Default")
      (node (ref "IC102") (pin "11") (pinfunction "1Q7_11") (pintype "tri_state"))
      (node (ref "IC102") (pin "37") (pinfunction "1D8_37") (pintype "input"))
      (node (ref "IC97") (pin "10") (pinfunction "I1_10") (pintype "input"))
      (node (ref "IC97") (pin "13") (pinfunction "I1_13") (pintype "input"))
      (node (ref "IC97") (pin "2") (pinfunction "I1_2") (pintype "input"))
      (node (ref "IC97") (pin "5") (pinfunction "I1_5") (pintype "input"))
      (node (ref "IC98") (pin "10") (pinfunction "I1_10") (pintype "input"))
      (node (ref "IC98") (pin "13") (pinfunction "I1_13") (pintype "input"))
      (node (ref "IC98") (pin "2") (pinfunction "I1_2") (pintype "input"))
      (node (ref "IC98") (pin "5") (pinfunction "I1_5") (pintype "input"))
    )
    (net (code "670") (name "Net-(IC102A-2D2)") (class "Default")
      (node (ref "IC102") (pin "13") (pinfunction "2Q1_13") (pintype "tri_state"))
      (node (ref "IC102") (pin "35") (pinfunction "2D2_35") (pintype "input"))
      (node (ref "IC82") (pin "10") (pinfunction "I1_10") (pintype "input"))
      (node (ref "IC82") (pin "13") (pinfunction "I1_13") (pintype "input"))
      (node (ref "IC82") (pin "2") (pinfunction "I1_2") (pintype "input"))
      (node (ref "IC82") (pin "5") (pinfunction "I1_5") (pintype "input"))
      (node (ref "IC83") (pin "10") (pinfunction "I1_10") (pintype "input"))
      (node (ref "IC83") (pin "13") (pinfunction "I1_13") (pintype "input"))
      (node (ref "IC83") (pin "2") (pinfunction "I1_2") (pintype "input"))
      (node (ref "IC83") (pin "5") (pinfunction "I1_5") (pintype "input"))
    )
    (net (code "671") (name "Net-(IC102A-2D3)") (class "Default")
      (node (ref "IC102") (pin "14") (pinfunction "2Q2_14") (pintype "tri_state"))
      (node (ref "IC102") (pin "33") (pinfunction "2D3_33") (pintype "input"))
      (node (ref "IC84") (pin "10") (pinfunction "I1_10") (pintype "input"))
      (node (ref "IC84") (pin "13") (pinfunction "I1_13") (pintype "input"))
      (node (ref "IC84") (pin "2") (pinfunction "I1_2") (pintype "input"))
      (node (ref "IC84") (pin "5") (pinfunction "I1_5") (pintype "input"))
      (node (ref "IC85") (pin "10") (pinfunction "I1_10") (pintype "input"))
      (node (ref "IC85") (pin "13") (pinfunction "I1_13") (pintype "input"))
      (node (ref "IC85") (pin "2") (pinfunction "I1_2") (pintype "input"))
      (node (ref "IC85") (pin "5") (pinfunction "I1_5") (pintype "input"))
    )
    (net (code "672") (name "Net-(IC102A-2D4)") (class "Default")
      (node (ref "IC102") (pin "16") (pinfunction "2Q3_16") (pintype "tri_state"))
      (node (ref "IC102") (pin "32") (pinfunction "2D4_32") (pintype "input"))
      (node (ref "IC87") (pin "10") (pinfunction "I1_10") (pintype "input"))
      (node (ref "IC87") (pin "13") (pinfunction "I1_13") (pintype "input"))
      (node (ref "IC87") (pin "2") (pinfunction "I1_2") (pintype "input"))
      (node (ref "IC87") (pin "5") (pinfunction "I1_5") (pintype "input"))
      (node (ref "IC88") (pin "10") (pinfunction "I1_10") (pintype "input"))
      (node (ref "IC88") (pin "13") (pinfunction "I1_13") (pintype "input"))
      (node (ref "IC88") (pin "2") (pinfunction "I1_2") (pintype "input"))
      (node (ref "IC88") (pin "5") (pinfunction "I1_5") (pintype "input"))
    )
    (net (code "673") (name "Net-(IC102A-2D5)") (class "Default")
      (node (ref "IC102") (pin "17") (pinfunction "2Q4_17") (pintype "tri_state"))
      (node (ref "IC102") (pin "30") (pinfunction "2D5_30") (pintype "input"))
      (node (ref "IC89") (pin "10") (pinfunction "I1_10") (pintype "input"))
      (node (ref "IC89") (pin "13") (pinfunction "I1_13") (pintype "input"))
      (node (ref "IC89") (pin "2") (pinfunction "I1_2") (pintype "input"))
      (node (ref "IC89") (pin "5") (pinfunction "I1_5") (pintype "input"))
      (node (ref "IC90") (pin "10") (pinfunction "I1_10") (pintype "input"))
      (node (ref "IC90") (pin "13") (pinfunction "I1_13") (pintype "input"))
      (node (ref "IC90") (pin "2") (pinfunction "I1_2") (pintype "input"))
      (node (ref "IC90") (pin "5") (pinfunction "I1_5") (pintype "input"))
    )
    (net (code "674") (name "Net-(IC102A-2D6)") (class "Default")
      (node (ref "IC102") (pin "19") (pinfunction "2Q5_19") (pintype "tri_state"))
      (node (ref "IC102") (pin "29") (pinfunction "2D6_29") (pintype "input"))
      (node (ref "IC72") (pin "10") (pinfunction "I1_10") (pintype "input"))
      (node (ref "IC72") (pin "13") (pinfunction "I1_13") (pintype "input"))
      (node (ref "IC72") (pin "2") (pinfunction "I1_2") (pintype "input"))
      (node (ref "IC72") (pin "5") (pinfunction "I1_5") (pintype "input"))
      (node (ref "IC73") (pin "10") (pinfunction "I1_10") (pintype "input"))
      (node (ref "IC73") (pin "13") (pinfunction "I1_13") (pintype "input"))
      (node (ref "IC73") (pin "2") (pinfunction "I1_2") (pintype "input"))
      (node (ref "IC73") (pin "5") (pinfunction "I1_5") (pintype "input"))
    )
    (net (code "675") (name "Net-(IC102A-2D7)") (class "Default")
      (node (ref "IC102") (pin "20") (pinfunction "2Q6_20") (pintype "tri_state"))
      (node (ref "IC102") (pin "27") (pinfunction "2D7_27") (pintype "input"))
      (node (ref "IC74") (pin "10") (pinfunction "I1_10") (pintype "input"))
      (node (ref "IC74") (pin "13") (pinfunction "I1_13") (pintype "input"))
      (node (ref "IC74") (pin "2") (pinfunction "I1_2") (pintype "input"))
      (node (ref "IC74") (pin "5") (pinfunction "I1_5") (pintype "input"))
      (node (ref "IC75") (pin "10") (pinfunction "I1_10") (pintype "input"))
      (node (ref "IC75") (pin "13") (pinfunction "I1_13") (pintype "input"))
      (node (ref "IC75") (pin "2") (pinfunction "I1_2") (pintype "input"))
      (node (ref "IC75") (pin "5") (pinfunction "I1_5") (pintype "input"))
    )
    (net (code "676") (name "Net-(IC102A-2D8)") (class "Default")
      (node (ref "IC102") (pin "22") (pinfunction "2Q7_22") (pintype "tri_state"))
      (node (ref "IC102") (pin "26") (pinfunction "2D8_26") (pintype "input"))
      (node (ref "IC77") (pin "10") (pinfunction "I1_10") (pintype "input"))
      (node (ref "IC77") (pin "13") (pinfunction "I1_13") (pintype "input"))
      (node (ref "IC77") (pin "2") (pinfunction "I1_2") (pintype "input"))
      (node (ref "IC77") (pin "5") (pinfunction "I1_5") (pintype "input"))
      (node (ref "IC78") (pin "10") (pinfunction "I1_10") (pintype "input"))
      (node (ref "IC78") (pin "13") (pinfunction "I1_13") (pintype "input"))
      (node (ref "IC78") (pin "2") (pinfunction "I1_2") (pintype "input"))
      (node (ref "IC78") (pin "5") (pinfunction "I1_5") (pintype "input"))
    )
    (net (code "677") (name "Net-(IC102A-2Q8)") (class "Default")
      (node (ref "IC102") (pin "23") (pinfunction "2Q8_23") (pintype "tri_state"))
      (node (ref "IC103") (pin "47") (pinfunction "1D1_47") (pintype "input"))
      (node (ref "IC79") (pin "10") (pinfunction "I1_10") (pintype "input"))
      (node (ref "IC79") (pin "13") (pinfunction "I1_13") (pintype "input"))
      (node (ref "IC79") (pin "2") (pinfunction "I1_2") (pintype "input"))
      (node (ref "IC79") (pin "5") (pinfunction "I1_5") (pintype "input"))
      (node (ref "IC80") (pin "10") (pinfunction "I1_10") (pintype "input"))
      (node (ref "IC80") (pin "13") (pinfunction "I1_13") (pintype "input"))
      (node (ref "IC80") (pin "2") (pinfunction "I1_2") (pintype "input"))
      (node (ref "IC80") (pin "5") (pinfunction "I1_5") (pintype "input"))
    )
    (net (code "678") (name "Net-(IC103A-1D2)") (class "Default")
      (node (ref "IC103") (pin "2") (pinfunction "1Q1_2") (pintype "tri_state"))
      (node (ref "IC103") (pin "46") (pinfunction "1D2_46") (pintype "input"))
      (node (ref "IC62") (pin "10") (pinfunction "I1_10") (pintype "input"))
      (node (ref "IC62") (pin "13") (pinfunction "I1_13") (pintype "input"))
      (node (ref "IC62") (pin "2") (pinfunction "I1_2") (pintype "input"))
      (node (ref "IC62") (pin "5") (pinfunction "I1_5") (pintype "input"))
      (node (ref "IC63") (pin "10") (pinfunction "I1_10") (pintype "input"))
      (node (ref "IC63") (pin "13") (pinfunction "I1_13") (pintype "input"))
      (node (ref "IC63") (pin "2") (pinfunction "I1_2") (pintype "input"))
      (node (ref "IC63") (pin "5") (pinfunction "I1_5") (pintype "input"))
    )
    (net (code "679") (name "Net-(IC103A-1D3)") (class "Default")
      (node (ref "IC103") (pin "3") (pinfunction "1Q2_3") (pintype "tri_state"))
      (node (ref "IC103") (pin "44") (pinfunction "1D3_44") (pintype "input"))
      (node (ref "IC64") (pin "10") (pinfunction "I1_10") (pintype "input"))
      (node (ref "IC64") (pin "13") (pinfunction "I1_13") (pintype "input"))
      (node (ref "IC64") (pin "2") (pinfunction "I1_2") (pintype "input"))
      (node (ref "IC64") (pin "5") (pinfunction "I1_5") (pintype "input"))
      (node (ref "IC65") (pin "10") (pinfunction "I1_10") (pintype "input"))
      (node (ref "IC65") (pin "13") (pinfunction "I1_13") (pintype "input"))
      (node (ref "IC65") (pin "2") (pinfunction "I1_2") (pintype "input"))
      (node (ref "IC65") (pin "5") (pinfunction "I1_5") (pintype "input"))
    )
    (net (code "680") (name "Net-(IC103A-1D4)") (class "Default")
      (node (ref "IC103") (pin "43") (pinfunction "1D4_43") (pintype "input"))
      (node (ref "IC103") (pin "5") (pinfunction "1Q3_5") (pintype "tri_state"))
      (node (ref "IC67") (pin "10") (pinfunction "I1_10") (pintype "input"))
      (node (ref "IC67") (pin "13") (pinfunction "I1_13") (pintype "input"))
      (node (ref "IC67") (pin "2") (pinfunction "I1_2") (pintype "input"))
      (node (ref "IC67") (pin "5") (pinfunction "I1_5") (pintype "input"))
      (node (ref "IC68") (pin "10") (pinfunction "I1_10") (pintype "input"))
      (node (ref "IC68") (pin "13") (pinfunction "I1_13") (pintype "input"))
      (node (ref "IC68") (pin "2") (pinfunction "I1_2") (pintype "input"))
      (node (ref "IC68") (pin "5") (pinfunction "I1_5") (pintype "input"))
    )
    (net (code "681") (name "Net-(IC103A-1D5)") (class "Default")
      (node (ref "IC103") (pin "41") (pinfunction "1D5_41") (pintype "input"))
      (node (ref "IC103") (pin "6") (pinfunction "1Q4_6") (pintype "tri_state"))
      (node (ref "IC69") (pin "10") (pinfunction "I1_10") (pintype "input"))
      (node (ref "IC69") (pin "13") (pinfunction "I1_13") (pintype "input"))
      (node (ref "IC69") (pin "2") (pinfunction "I1_2") (pintype "input"))
      (node (ref "IC69") (pin "5") (pinfunction "I1_5") (pintype "input"))
      (node (ref "IC70") (pin "10") (pinfunction "I1_10") (pintype "input"))
      (node (ref "IC70") (pin "13") (pinfunction "I1_13") (pintype "input"))
      (node (ref "IC70") (pin "2") (pinfunction "I1_2") (pintype "input"))
      (node (ref "IC70") (pin "5") (pinfunction "I1_5") (pintype "input"))
    )
    (net (code "682") (name "Net-(IC103A-1D6)") (class "Default")
      (node (ref "IC103") (pin "40") (pinfunction "1D6_40") (pintype "input"))
      (node (ref "IC103") (pin "8") (pinfunction "1Q5_8") (pintype "tri_state"))
      (node (ref "IC32") (pin "10") (pinfunction "I1_10") (pintype "input"))
      (node (ref "IC32") (pin "13") (pinfunction "I1_13") (pintype "input"))
      (node (ref "IC32") (pin "2") (pinfunction "I1_2") (pintype "input"))
      (node (ref "IC32") (pin "5") (pinfunction "I1_5") (pintype "input"))
      (node (ref "IC33") (pin "10") (pinfunction "I1_10") (pintype "input"))
      (node (ref "IC33") (pin "13") (pinfunction "I1_13") (pintype "input"))
      (node (ref "IC33") (pin "2") (pinfunction "I1_2") (pintype "input"))
      (node (ref "IC33") (pin "5") (pinfunction "I1_5") (pintype "input"))
    )
    (net (code "683") (name "Net-(IC103A-1D7)") (class "Default")
      (node (ref "IC103") (pin "38") (pinfunction "1D7_38") (pintype "input"))
      (node (ref "IC103") (pin "9") (pinfunction "1Q6_9") (pintype "tri_state"))
      (node (ref "IC34") (pin "10") (pinfunction "I1_10") (pintype "input"))
      (node (ref "IC34") (pin "13") (pinfunction "I1_13") (pintype "input"))
      (node (ref "IC34") (pin "2") (pinfunction "I1_2") (pintype "input"))
      (node (ref "IC34") (pin "5") (pinfunction "I1_5") (pintype "input"))
      (node (ref "IC35") (pin "10") (pinfunction "I1_10") (pintype "input"))
      (node (ref "IC35") (pin "13") (pinfunction "I1_13") (pintype "input"))
      (node (ref "IC35") (pin "2") (pinfunction "I1_2") (pintype "input"))
      (node (ref "IC35") (pin "5") (pinfunction "I1_5") (pintype "input"))
    )
    (net (code "684") (name "Net-(IC103A-1D8)") (class "Default")
      (node (ref "IC103") (pin "11") (pinfunction "1Q7_11") (pintype "tri_state"))
      (node (ref "IC103") (pin "37") (pinfunction "1D8_37") (pintype "input"))
      (node (ref "IC37") (pin "10") (pinfunction "I1_10") (pintype "input"))
      (node (ref "IC37") (pin "13") (pinfunction "I1_13") (pintype "input"))
      (node (ref "IC37") (pin "2") (pinfunction "I1_2") (pintype "input"))
      (node (ref "IC37") (pin "5") (pinfunction "I1_5") (pintype "input"))
      (node (ref "IC38") (pin "10") (pinfunction "I1_10") (pintype "input"))
      (node (ref "IC38") (pin "13") (pinfunction "I1_13") (pintype "input"))
      (node (ref "IC38") (pin "2") (pinfunction "I1_2") (pintype "input"))
      (node (ref "IC38") (pin "5") (pinfunction "I1_5") (pintype "input"))
    )
    (net (code "685") (name "Net-(IC103A-1Q8)") (class "Default")
      (node (ref "IC103") (pin "12") (pinfunction "1Q8_12") (pintype "tri_state"))
      (node (ref "IC103") (pin "36") (pinfunction "2D1_36") (pintype "input"))
      (node (ref "IC39") (pin "10") (pinfunction "I1_10") (pintype "input"))
      (node (ref "IC39") (pin "13") (pinfunction "I1_13") (pintype "input"))
      (node (ref "IC39") (pin "2") (pinfunction "I1_2") (pintype "input"))
      (node (ref "IC39") (pin "5") (pinfunction "I1_5") (pintype "input"))
      (node (ref "IC40") (pin "10") (pinfunction "I1_10") (pintype "input"))
      (node (ref "IC40") (pin "13") (pinfunction "I1_13") (pintype "input"))
      (node (ref "IC40") (pin "2") (pinfunction "I1_2") (pintype "input"))
      (node (ref "IC40") (pin "5") (pinfunction "I1_5") (pintype "input"))
      (node (ref "X11") (pin "1") (pinfunction "S_1") (pintype "passive"))
    )
    (net (code "686") (name "Net-(U$1-CD+)") (class "Default")
      (node (ref "U$1") (pin "10") (pinfunction "CD+_10") (pintype "passive"))
      (node (ref "U$10") (pin "10") (pinfunction "CD+_10") (pintype "passive"))
      (node (ref "U$11") (pin "10") (pinfunction "CD+_10") (pintype "passive"))
      (node (ref "U$12") (pin "10") (pinfunction "CD+_10") (pintype "passive"))
      (node (ref "U$13") (pin "10") (pinfunction "CD+_10") (pintype "passive"))
      (node (ref "U$14") (pin "10") (pinfunction "CD+_10") (pintype "passive"))
      (node (ref "U$15") (pin "10") (pinfunction "CD+_10") (pintype "passive"))
      (node (ref "U$16") (pin "10") (pinfunction "CD+_10") (pintype "passive"))
      (node (ref "U$17") (pin "10") (pinfunction "CD+_10") (pintype "passive"))
      (node (ref "U$18") (pin "10") (pinfunction "CD+_10") (pintype "passive"))
      (node (ref "U$19") (pin "10") (pinfunction "CD+_10") (pintype "passive"))
      (node (ref "U$2") (pin "10") (pinfunction "CD+_10") (pintype "passive"))
      (node (ref "U$20") (pin "10") (pinfunction "CD+_10") (pintype "passive"))
      (node (ref "U$21") (pin "10") (pinfunction "CD+_10") (pintype "passive"))
      (node (ref "U$22") (pin "10") (pinfunction "CD+_10") (pintype "passive"))
      (node (ref "U$23") (pin "10") (pinfunction "CD+_10") (pintype "passive"))
      (node (ref "U$24") (pin "10") (pinfunction "CD+_10") (pintype "passive"))
      (node (ref "U$25") (pin "10") (pinfunction "CD+_10") (pintype "passive"))
      (node (ref "U$26") (pin "10") (pinfunction "CD+_10") (pintype "passive"))
      (node (ref "U$27") (pin "10") (pinfunction "CD+_10") (pintype "passive"))
      (node (ref "U$28") (pin "10") (pinfunction "CD+_10") (pintype "passive"))
      (node (ref "U$29") (pin "10") (pinfunction "CD+_10") (pintype "passive"))
      (node (ref "U$3") (pin "10") (pinfunction "CD+_10") (pintype "passive"))
      (node (ref "U$30") (pin "10") (pinfunction "CD+_10") (pintype "passive"))
      (node (ref "U$31") (pin "10") (pinfunction "CD+_10") (pintype "passive"))
      (node (ref "U$32") (pin "10") (pinfunction "CD+_10") (pintype "passive"))
      (node (ref "U$33") (pin "10") (pinfunction "CD+_10") (pintype "passive"))
      (node (ref "U$34") (pin "10") (pinfunction "CD+_10") (pintype "passive"))
      (node (ref "U$35") (pin "10") (pinfunction "CD+_10") (pintype "passive"))
      (node (ref "U$36") (pin "10") (pinfunction "CD+_10") (pintype "passive"))
      (node (ref "U$37") (pin "10") (pinfunction "CD+_10") (pintype "passive"))
      (node (ref "U$38") (pin "10") (pinfunction "CD+_10") (pintype "passive"))
      (node (ref "U$39") (pin "10") (pinfunction "CD+_10") (pintype "passive"))
      (node (ref "U$4") (pin "10") (pinfunction "CD+_10") (pintype "passive"))
      (node (ref "U$40") (pin "10") (pinfunction "CD+_10") (pintype "passive"))
      (node (ref "U$5") (pin "10") (pinfunction "CD+_10") (pintype "passive"))
      (node (ref "U$6") (pin "10") (pinfunction "CD+_10") (pintype "passive"))
      (node (ref "U$7") (pin "10") (pinfunction "CD+_10") (pintype "passive"))
      (node (ref "U$8") (pin "10") (pinfunction "CD+_10") (pintype "passive"))
      (node (ref "U$9") (pin "10") (pinfunction "CD+_10") (pintype "passive"))
      (node (ref "X11") (pin "7") (pinfunction "S_7") (pintype "passive"))
    )
    (net (code "687") (name "Net-(U$1-O1)") (class "Default")
      (node (ref "U$1") (pin "18") (pinfunction "O1_18") (pintype "open_collector"))
      (node (ref "X2") (pin "1") (pinfunction "S_1") (pintype "passive"))
    )
    (net (code "688") (name "Net-(U$1-O2)") (class "Default")
      (node (ref "U$1") (pin "17") (pinfunction "O2_17") (pintype "open_collector"))
      (node (ref "X2") (pin "3") (pinfunction "S_3") (pintype "passive"))
    )
    (net (code "689") (name "Net-(U$1-O3)") (class "Default")
      (node (ref "U$1") (pin "16") (pinfunction "O3_16") (pintype "open_collector"))
      (node (ref "X2") (pin "5") (pinfunction "S_5") (pintype "passive"))
    )
    (net (code "690") (name "Net-(U$1-O4)") (class "Default")
      (node (ref "U$1") (pin "15") (pinfunction "O4_15") (pintype "open_collector"))
      (node (ref "X2") (pin "7") (pinfunction "S_7") (pintype "passive"))
    )
    (net (code "691") (name "Net-(U$1-O5)") (class "Default")
      (node (ref "U$1") (pin "14") (pinfunction "O5_14") (pintype "open_collector"))
      (node (ref "X2") (pin "9") (pinfunction "S_9") (pintype "passive"))
    )
    (net (code "692") (name "Net-(U$1-O6)") (class "Default")
      (node (ref "U$1") (pin "13") (pinfunction "O6_13") (pintype "open_collector"))
      (node (ref "X2") (pin "11") (pinfunction "S_11") (pintype "passive"))
    )
    (net (code "693") (name "Net-(U$1-O7)") (class "Default")
      (node (ref "U$1") (pin "12") (pinfunction "O7_12") (pintype "open_collector"))
      (node (ref "X2") (pin "13") (pinfunction "S_13") (pintype "passive"))
    )
    (net (code "694") (name "Net-(U$1-O8)") (class "Default")
      (node (ref "U$1") (pin "11") (pinfunction "O8_11") (pintype "open_collector"))
      (node (ref "X2") (pin "15") (pinfunction "S_15") (pintype "passive"))
    )
    (net (code "695") (name "Net-(U$2-O1)") (class "Default")
      (node (ref "U$2") (pin "18") (pinfunction "O1_18") (pintype "open_collector"))
      (node (ref "X2") (pin "17") (pinfunction "S_17") (pintype "passive"))
    )
    (net (code "696") (name "Net-(U$2-O2)") (class "Default")
      (node (ref "U$2") (pin "17") (pinfunction "O2_17") (pintype "open_collector"))
      (node (ref "X2") (pin "19") (pinfunction "S_19") (pintype "passive"))
    )
    (net (code "697") (name "Net-(U$2-O3)") (class "Default")
      (node (ref "U$2") (pin "16") (pinfunction "O3_16") (pintype "open_collector"))
      (node (ref "X2") (pin "21") (pinfunction "S_21") (pintype "passive"))
    )
    (net (code "698") (name "Net-(U$2-O4)") (class "Default")
      (node (ref "U$2") (pin "15") (pinfunction "O4_15") (pintype "open_collector"))
      (node (ref "X2") (pin "23") (pinfunction "S_23") (pintype "passive"))
    )
    (net (code "699") (name "Net-(U$2-O5)") (class "Default")
      (node (ref "U$2") (pin "14") (pinfunction "O5_14") (pintype "open_collector"))
      (node (ref "X2") (pin "25") (pinfunction "S_25") (pintype "passive"))
    )
    (net (code "700") (name "Net-(U$2-O6)") (class "Default")
      (node (ref "U$2") (pin "13") (pinfunction "O6_13") (pintype "open_collector"))
      (node (ref "X2") (pin "27") (pinfunction "S_27") (pintype "passive"))
    )
    (net (code "701") (name "Net-(U$2-O7)") (class "Default")
      (node (ref "U$2") (pin "12") (pinfunction "O7_12") (pintype "open_collector"))
      (node (ref "X2") (pin "29") (pinfunction "S_29") (pintype "passive"))
    )
    (net (code "702") (name "Net-(U$2-O8)") (class "Default")
      (node (ref "U$2") (pin "11") (pinfunction "O8_11") (pintype "open_collector"))
      (node (ref "X2") (pin "31") (pinfunction "S_31") (pintype "passive"))
    )
    (net (code "703") (name "Net-(U$3-O1)") (class "Default")
      (node (ref "U$3") (pin "18") (pinfunction "O1_18") (pintype "open_collector"))
      (node (ref "X2") (pin "2") (pinfunction "S_2") (pintype "passive"))
    )
    (net (code "704") (name "Net-(U$3-O2)") (class "Default")
      (node (ref "U$3") (pin "17") (pinfunction "O2_17") (pintype "open_collector"))
      (node (ref "X2") (pin "4") (pinfunction "S_4") (pintype "passive"))
    )
    (net (code "705") (name "Net-(U$3-O3)") (class "Default")
      (node (ref "U$3") (pin "16") (pinfunction "O3_16") (pintype "open_collector"))
      (node (ref "X2") (pin "6") (pinfunction "S_6") (pintype "passive"))
    )
    (net (code "706") (name "Net-(U$3-O4)") (class "Default")
      (node (ref "U$3") (pin "15") (pinfunction "O4_15") (pintype "open_collector"))
      (node (ref "X2") (pin "8") (pinfunction "S_8") (pintype "passive"))
    )
    (net (code "707") (name "Net-(U$3-O5)") (class "Default")
      (node (ref "U$3") (pin "14") (pinfunction "O5_14") (pintype "open_collector"))
      (node (ref "X2") (pin "10") (pinfunction "S_10") (pintype "passive"))
    )
    (net (code "708") (name "Net-(U$3-O6)") (class "Default")
      (node (ref "U$3") (pin "13") (pinfunction "O6_13") (pintype "open_collector"))
      (node (ref "X2") (pin "12") (pinfunction "S_12") (pintype "passive"))
    )
    (net (code "709") (name "Net-(U$3-O7)") (class "Default")
      (node (ref "U$3") (pin "12") (pinfunction "O7_12") (pintype "open_collector"))
      (node (ref "X2") (pin "14") (pinfunction "S_14") (pintype "passive"))
    )
    (net (code "710") (name "Net-(U$3-O8)") (class "Default")
      (node (ref "U$3") (pin "11") (pinfunction "O8_11") (pintype "open_collector"))
      (node (ref "X2") (pin "16") (pinfunction "S_16") (pintype "passive"))
    )
    (net (code "711") (name "Net-(U$4-O1)") (class "Default")
      (node (ref "U$4") (pin "18") (pinfunction "O1_18") (pintype "open_collector"))
      (node (ref "X2") (pin "18") (pinfunction "S_18") (pintype "passive"))
    )
    (net (code "712") (name "Net-(U$4-O2)") (class "Default")
      (node (ref "U$4") (pin "17") (pinfunction "O2_17") (pintype "open_collector"))
      (node (ref "X2") (pin "20") (pinfunction "S_20") (pintype "passive"))
    )
    (net (code "713") (name "Net-(U$4-O3)") (class "Default")
      (node (ref "U$4") (pin "16") (pinfunction "O3_16") (pintype "open_collector"))
      (node (ref "X2") (pin "22") (pinfunction "S_22") (pintype "passive"))
    )
    (net (code "714") (name "Net-(U$4-O4)") (class "Default")
      (node (ref "U$4") (pin "15") (pinfunction "O4_15") (pintype "open_collector"))
      (node (ref "X2") (pin "24") (pinfunction "S_24") (pintype "passive"))
    )
    (net (code "715") (name "Net-(U$4-O5)") (class "Default")
      (node (ref "U$4") (pin "14") (pinfunction "O5_14") (pintype "open_collector"))
      (node (ref "X2") (pin "26") (pinfunction "S_26") (pintype "passive"))
    )
    (net (code "716") (name "Net-(U$4-O6)") (class "Default")
      (node (ref "U$4") (pin "13") (pinfunction "O6_13") (pintype "open_collector"))
      (node (ref "X2") (pin "28") (pinfunction "S_28") (pintype "passive"))
    )
    (net (code "717") (name "Net-(U$4-O7)") (class "Default")
      (node (ref "U$4") (pin "12") (pinfunction "O7_12") (pintype "open_collector"))
      (node (ref "X2") (pin "30") (pinfunction "S_30") (pintype "passive"))
    )
    (net (code "718") (name "Net-(U$4-O8)") (class "Default")
      (node (ref "U$4") (pin "11") (pinfunction "O8_11") (pintype "open_collector"))
      (node (ref "X2") (pin "32") (pinfunction "S_32") (pintype "passive"))
    )
    (net (code "719") (name "Net-(U$5-O1)") (class "Default")
      (node (ref "U$5") (pin "18") (pinfunction "O1_18") (pintype "open_collector"))
      (node (ref "X1") (pin "1") (pinfunction "S_1") (pintype "passive"))
    )
    (net (code "720") (name "Net-(U$5-O2)") (class "Default")
      (node (ref "U$5") (pin "17") (pinfunction "O2_17") (pintype "open_collector"))
      (node (ref "X1") (pin "3") (pinfunction "S_3") (pintype "passive"))
    )
    (net (code "721") (name "Net-(U$5-O3)") (class "Default")
      (node (ref "U$5") (pin "16") (pinfunction "O3_16") (pintype "open_collector"))
      (node (ref "X1") (pin "5") (pinfunction "S_5") (pintype "passive"))
    )
    (net (code "722") (name "Net-(U$5-O4)") (class "Default")
      (node (ref "U$5") (pin "15") (pinfunction "O4_15") (pintype "open_collector"))
      (node (ref "X1") (pin "7") (pinfunction "S_7") (pintype "passive"))
    )
    (net (code "723") (name "Net-(U$5-O5)") (class "Default")
      (node (ref "U$5") (pin "14") (pinfunction "O5_14") (pintype "open_collector"))
      (node (ref "X1") (pin "9") (pinfunction "S_9") (pintype "passive"))
    )
    (net (code "724") (name "Net-(U$5-O6)") (class "Default")
      (node (ref "U$5") (pin "13") (pinfunction "O6_13") (pintype "open_collector"))
      (node (ref "X1") (pin "11") (pinfunction "S_11") (pintype "passive"))
    )
    (net (code "725") (name "Net-(U$5-O7)") (class "Default")
      (node (ref "U$5") (pin "12") (pinfunction "O7_12") (pintype "open_collector"))
      (node (ref "X1") (pin "13") (pinfunction "S_13") (pintype "passive"))
    )
    (net (code "726") (name "Net-(U$5-O8)") (class "Default")
      (node (ref "U$5") (pin "11") (pinfunction "O8_11") (pintype "open_collector"))
      (node (ref "X1") (pin "15") (pinfunction "S_15") (pintype "passive"))
    )
    (net (code "727") (name "Net-(U$6-O1)") (class "Default")
      (node (ref "U$6") (pin "18") (pinfunction "O1_18") (pintype "open_collector"))
      (node (ref "X1") (pin "17") (pinfunction "S_17") (pintype "passive"))
    )
    (net (code "728") (name "Net-(U$6-O2)") (class "Default")
      (node (ref "U$6") (pin "17") (pinfunction "O2_17") (pintype "open_collector"))
      (node (ref "X1") (pin "19") (pinfunction "S_19") (pintype "passive"))
    )
    (net (code "729") (name "Net-(U$6-O3)") (class "Default")
      (node (ref "U$6") (pin "16") (pinfunction "O3_16") (pintype "open_collector"))
      (node (ref "X1") (pin "21") (pinfunction "S_21") (pintype "passive"))
    )
    (net (code "730") (name "Net-(U$6-O4)") (class "Default")
      (node (ref "U$6") (pin "15") (pinfunction "O4_15") (pintype "open_collector"))
      (node (ref "X1") (pin "23") (pinfunction "S_23") (pintype "passive"))
    )
    (net (code "731") (name "Net-(U$6-O5)") (class "Default")
      (node (ref "U$6") (pin "14") (pinfunction "O5_14") (pintype "open_collector"))
      (node (ref "X1") (pin "25") (pinfunction "S_25") (pintype "passive"))
    )
    (net (code "732") (name "Net-(U$6-O6)") (class "Default")
      (node (ref "U$6") (pin "13") (pinfunction "O6_13") (pintype "open_collector"))
      (node (ref "X1") (pin "27") (pinfunction "S_27") (pintype "passive"))
    )
    (net (code "733") (name "Net-(U$6-O7)") (class "Default")
      (node (ref "U$6") (pin "12") (pinfunction "O7_12") (pintype "open_collector"))
      (node (ref "X1") (pin "29") (pinfunction "S_29") (pintype "passive"))
    )
    (net (code "734") (name "Net-(U$6-O8)") (class "Default")
      (node (ref "U$6") (pin "11") (pinfunction "O8_11") (pintype "open_collector"))
      (node (ref "X1") (pin "31") (pinfunction "S_31") (pintype "passive"))
    )
    (net (code "735") (name "Net-(U$7-O1)") (class "Default")
      (node (ref "U$7") (pin "18") (pinfunction "O1_18") (pintype "open_collector"))
      (node (ref "X1") (pin "2") (pinfunction "S_2") (pintype "passive"))
    )
    (net (code "736") (name "Net-(U$7-O2)") (class "Default")
      (node (ref "U$7") (pin "17") (pinfunction "O2_17") (pintype "open_collector"))
      (node (ref "X1") (pin "4") (pinfunction "S_4") (pintype "passive"))
    )
    (net (code "737") (name "Net-(U$7-O3)") (class "Default")
      (node (ref "U$7") (pin "16") (pinfunction "O3_16") (pintype "open_collector"))
      (node (ref "X1") (pin "6") (pinfunction "S_6") (pintype "passive"))
    )
    (net (code "738") (name "Net-(U$7-O4)") (class "Default")
      (node (ref "U$7") (pin "15") (pinfunction "O4_15") (pintype "open_collector"))
      (node (ref "X1") (pin "8") (pinfunction "S_8") (pintype "passive"))
    )
    (net (code "739") (name "Net-(U$7-O5)") (class "Default")
      (node (ref "U$7") (pin "14") (pinfunction "O5_14") (pintype "open_collector"))
      (node (ref "X1") (pin "10") (pinfunction "S_10") (pintype "passive"))
    )
    (net (code "740") (name "Net-(U$7-O6)") (class "Default")
      (node (ref "U$7") (pin "13") (pinfunction "O6_13") (pintype "open_collector"))
      (node (ref "X1") (pin "12") (pinfunction "S_12") (pintype "passive"))
    )
    (net (code "741") (name "Net-(U$7-O7)") (class "Default")
      (node (ref "U$7") (pin "12") (pinfunction "O7_12") (pintype "open_collector"))
      (node (ref "X1") (pin "14") (pinfunction "S_14") (pintype "passive"))
    )
    (net (code "742") (name "Net-(U$7-O8)") (class "Default")
      (node (ref "U$7") (pin "11") (pinfunction "O8_11") (pintype "open_collector"))
      (node (ref "X1") (pin "16") (pinfunction "S_16") (pintype "passive"))
    )
    (net (code "743") (name "Net-(U$8-O1)") (class "Default")
      (node (ref "U$8") (pin "18") (pinfunction "O1_18") (pintype "open_collector"))
      (node (ref "X1") (pin "18") (pinfunction "S_18") (pintype "passive"))
    )
    (net (code "744") (name "Net-(U$8-O2)") (class "Default")
      (node (ref "U$8") (pin "17") (pinfunction "O2_17") (pintype "open_collector"))
      (node (ref "X1") (pin "20") (pinfunction "S_20") (pintype "passive"))
    )
    (net (code "745") (name "Net-(U$8-O3)") (class "Default")
      (node (ref "U$8") (pin "16") (pinfunction "O3_16") (pintype "open_collector"))
      (node (ref "X1") (pin "22") (pinfunction "S_22") (pintype "passive"))
    )
    (net (code "746") (name "Net-(U$8-O4)") (class "Default")
      (node (ref "U$8") (pin "15") (pinfunction "O4_15") (pintype "open_collector"))
      (node (ref "X1") (pin "24") (pinfunction "S_24") (pintype "passive"))
    )
    (net (code "747") (name "Net-(U$8-O5)") (class "Default")
      (node (ref "U$8") (pin "14") (pinfunction "O5_14") (pintype "open_collector"))
      (node (ref "X1") (pin "26") (pinfunction "S_26") (pintype "passive"))
    )
    (net (code "748") (name "Net-(U$8-O6)") (class "Default")
      (node (ref "U$8") (pin "13") (pinfunction "O6_13") (pintype "open_collector"))
      (node (ref "X1") (pin "28") (pinfunction "S_28") (pintype "passive"))
    )
    (net (code "749") (name "Net-(U$8-O7)") (class "Default")
      (node (ref "U$8") (pin "12") (pinfunction "O7_12") (pintype "open_collector"))
      (node (ref "X1") (pin "30") (pinfunction "S_30") (pintype "passive"))
    )
    (net (code "750") (name "Net-(U$8-O8)") (class "Default")
      (node (ref "U$8") (pin "11") (pinfunction "O8_11") (pintype "open_collector"))
      (node (ref "X1") (pin "32") (pinfunction "S_32") (pintype "passive"))
    )
    (net (code "751") (name "Net-(U$9-O1)") (class "Default")
      (node (ref "U$9") (pin "18") (pinfunction "O1_18") (pintype "open_collector"))
      (node (ref "X3") (pin "1") (pinfunction "S_1") (pintype "passive"))
    )
    (net (code "752") (name "Net-(U$9-O2)") (class "Default")
      (node (ref "U$9") (pin "17") (pinfunction "O2_17") (pintype "open_collector"))
      (node (ref "X3") (pin "3") (pinfunction "S_3") (pintype "passive"))
    )
    (net (code "753") (name "Net-(U$9-O3)") (class "Default")
      (node (ref "U$9") (pin "16") (pinfunction "O3_16") (pintype "open_collector"))
      (node (ref "X3") (pin "5") (pinfunction "S_5") (pintype "passive"))
    )
    (net (code "754") (name "Net-(U$9-O4)") (class "Default")
      (node (ref "U$9") (pin "15") (pinfunction "O4_15") (pintype "open_collector"))
      (node (ref "X3") (pin "7") (pinfunction "S_7") (pintype "passive"))
    )
    (net (code "755") (name "Net-(U$9-O5)") (class "Default")
      (node (ref "U$9") (pin "14") (pinfunction "O5_14") (pintype "open_collector"))
      (node (ref "X3") (pin "9") (pinfunction "S_9") (pintype "passive"))
    )
    (net (code "756") (name "Net-(U$9-O6)") (class "Default")
      (node (ref "U$9") (pin "13") (pinfunction "O6_13") (pintype "open_collector"))
      (node (ref "X3") (pin "11") (pinfunction "S_11") (pintype "passive"))
    )
    (net (code "757") (name "Net-(U$9-O7)") (class "Default")
      (node (ref "U$9") (pin "12") (pinfunction "O7_12") (pintype "open_collector"))
      (node (ref "X3") (pin "13") (pinfunction "S_13") (pintype "passive"))
    )
    (net (code "758") (name "Net-(U$9-O8)") (class "Default")
      (node (ref "U$9") (pin "11") (pinfunction "O8_11") (pintype "open_collector"))
      (node (ref "X3") (pin "15") (pinfunction "S_15") (pintype "passive"))
    )
    (net (code "759") (name "Net-(U$10-O1)") (class "Default")
      (node (ref "U$10") (pin "18") (pinfunction "O1_18") (pintype "open_collector"))
      (node (ref "X3") (pin "17") (pinfunction "S_17") (pintype "passive"))
    )
    (net (code "760") (name "Net-(U$10-O2)") (class "Default")
      (node (ref "U$10") (pin "17") (pinfunction "O2_17") (pintype "open_collector"))
      (node (ref "X3") (pin "19") (pinfunction "S_19") (pintype "passive"))
    )
    (net (code "761") (name "Net-(U$10-O3)") (class "Default")
      (node (ref "U$10") (pin "16") (pinfunction "O3_16") (pintype "open_collector"))
      (node (ref "X3") (pin "21") (pinfunction "S_21") (pintype "passive"))
    )
    (net (code "762") (name "Net-(U$10-O4)") (class "Default")
      (node (ref "U$10") (pin "15") (pinfunction "O4_15") (pintype "open_collector"))
      (node (ref "X3") (pin "23") (pinfunction "S_23") (pintype "passive"))
    )
    (net (code "763") (name "Net-(U$10-O5)") (class "Default")
      (node (ref "U$10") (pin "14") (pinfunction "O5_14") (pintype "open_collector"))
      (node (ref "X3") (pin "25") (pinfunction "S_25") (pintype "passive"))
    )
    (net (code "764") (name "Net-(U$10-O6)") (class "Default")
      (node (ref "U$10") (pin "13") (pinfunction "O6_13") (pintype "open_collector"))
      (node (ref "X3") (pin "27") (pinfunction "S_27") (pintype "passive"))
    )
    (net (code "765") (name "Net-(U$10-O7)") (class "Default")
      (node (ref "U$10") (pin "12") (pinfunction "O7_12") (pintype "open_collector"))
      (node (ref "X3") (pin "29") (pinfunction "S_29") (pintype "passive"))
    )
    (net (code "766") (name "Net-(U$10-O8)") (class "Default")
      (node (ref "U$10") (pin "11") (pinfunction "O8_11") (pintype "open_collector"))
      (node (ref "X3") (pin "31") (pinfunction "S_31") (pintype "passive"))
    )
    (net (code "767") (name "Net-(U$11-O1)") (class "Default")
      (node (ref "U$11") (pin "18") (pinfunction "O1_18") (pintype "open_collector"))
      (node (ref "X3") (pin "2") (pinfunction "S_2") (pintype "passive"))
    )
    (net (code "768") (name "Net-(U$11-O2)") (class "Default")
      (node (ref "U$11") (pin "17") (pinfunction "O2_17") (pintype "open_collector"))
      (node (ref "X3") (pin "4") (pinfunction "S_4") (pintype "passive"))
    )
    (net (code "769") (name "Net-(U$11-O3)") (class "Default")
      (node (ref "U$11") (pin "16") (pinfunction "O3_16") (pintype "open_collector"))
      (node (ref "X3") (pin "6") (pinfunction "S_6") (pintype "passive"))
    )
    (net (code "770") (name "Net-(U$11-O4)") (class "Default")
      (node (ref "U$11") (pin "15") (pinfunction "O4_15") (pintype "open_collector"))
      (node (ref "X3") (pin "8") (pinfunction "S_8") (pintype "passive"))
    )
    (net (code "771") (name "Net-(U$11-O5)") (class "Default")
      (node (ref "U$11") (pin "14") (pinfunction "O5_14") (pintype "open_collector"))
      (node (ref "X3") (pin "10") (pinfunction "S_10") (pintype "passive"))
    )
    (net (code "772") (name "Net-(U$11-O6)") (class "Default")
      (node (ref "U$11") (pin "13") (pinfunction "O6_13") (pintype "open_collector"))
      (node (ref "X3") (pin "12") (pinfunction "S_12") (pintype "passive"))
    )
    (net (code "773") (name "Net-(U$11-O7)") (class "Default")
      (node (ref "U$11") (pin "12") (pinfunction "O7_12") (pintype "open_collector"))
      (node (ref "X3") (pin "14") (pinfunction "S_14") (pintype "passive"))
    )
    (net (code "774") (name "Net-(U$11-O8)") (class "Default")
      (node (ref "U$11") (pin "11") (pinfunction "O8_11") (pintype "open_collector"))
      (node (ref "X3") (pin "16") (pinfunction "S_16") (pintype "passive"))
    )
    (net (code "775") (name "Net-(U$12-O1)") (class "Default")
      (node (ref "U$12") (pin "18") (pinfunction "O1_18") (pintype "open_collector"))
      (node (ref "X3") (pin "18") (pinfunction "S_18") (pintype "passive"))
    )
    (net (code "776") (name "Net-(U$12-O2)") (class "Default")
      (node (ref "U$12") (pin "17") (pinfunction "O2_17") (pintype "open_collector"))
      (node (ref "X3") (pin "20") (pinfunction "S_20") (pintype "passive"))
    )
    (net (code "777") (name "Net-(U$12-O3)") (class "Default")
      (node (ref "U$12") (pin "16") (pinfunction "O3_16") (pintype "open_collector"))
      (node (ref "X3") (pin "22") (pinfunction "S_22") (pintype "passive"))
    )
    (net (code "778") (name "Net-(U$12-O4)") (class "Default")
      (node (ref "U$12") (pin "15") (pinfunction "O4_15") (pintype "open_collector"))
      (node (ref "X3") (pin "24") (pinfunction "S_24") (pintype "passive"))
    )
    (net (code "779") (name "Net-(U$12-O5)") (class "Default")
      (node (ref "U$12") (pin "14") (pinfunction "O5_14") (pintype "open_collector"))
      (node (ref "X3") (pin "26") (pinfunction "S_26") (pintype "passive"))
    )
    (net (code "780") (name "Net-(U$12-O6)") (class "Default")
      (node (ref "U$12") (pin "13") (pinfunction "O6_13") (pintype "open_collector"))
      (node (ref "X3") (pin "28") (pinfunction "S_28") (pintype "passive"))
    )
    (net (code "781") (name "Net-(U$12-O7)") (class "Default")
      (node (ref "U$12") (pin "12") (pinfunction "O7_12") (pintype "open_collector"))
      (node (ref "X3") (pin "30") (pinfunction "S_30") (pintype "passive"))
    )
    (net (code "782") (name "Net-(U$12-O8)") (class "Default")
      (node (ref "U$12") (pin "11") (pinfunction "O8_11") (pintype "open_collector"))
      (node (ref "X3") (pin "32") (pinfunction "S_32") (pintype "passive"))
    )
    (net (code "783") (name "Net-(U$13-O1)") (class "Default")
      (node (ref "U$13") (pin "18") (pinfunction "O1_18") (pintype "open_collector"))
      (node (ref "X4") (pin "1") (pinfunction "S_1") (pintype "passive"))
    )
    (net (code "784") (name "Net-(U$13-O2)") (class "Default")
      (node (ref "U$13") (pin "17") (pinfunction "O2_17") (pintype "open_collector"))
      (node (ref "X4") (pin "3") (pinfunction "S_3") (pintype "passive"))
    )
    (net (code "785") (name "Net-(U$13-O3)") (class "Default")
      (node (ref "U$13") (pin "16") (pinfunction "O3_16") (pintype "open_collector"))
      (node (ref "X4") (pin "5") (pinfunction "S_5") (pintype "passive"))
    )
    (net (code "786") (name "Net-(U$13-O4)") (class "Default")
      (node (ref "U$13") (pin "15") (pinfunction "O4_15") (pintype "open_collector"))
      (node (ref "X4") (pin "7") (pinfunction "S_7") (pintype "passive"))
    )
    (net (code "787") (name "Net-(U$13-O5)") (class "Default")
      (node (ref "U$13") (pin "14") (pinfunction "O5_14") (pintype "open_collector"))
      (node (ref "X4") (pin "9") (pinfunction "S_9") (pintype "passive"))
    )
    (net (code "788") (name "Net-(U$13-O6)") (class "Default")
      (node (ref "U$13") (pin "13") (pinfunction "O6_13") (pintype "open_collector"))
      (node (ref "X4") (pin "11") (pinfunction "S_11") (pintype "passive"))
    )
    (net (code "789") (name "Net-(U$13-O7)") (class "Default")
      (node (ref "U$13") (pin "12") (pinfunction "O7_12") (pintype "open_collector"))
      (node (ref "X4") (pin "13") (pinfunction "S_13") (pintype "passive"))
    )
    (net (code "790") (name "Net-(U$13-O8)") (class "Default")
      (node (ref "U$13") (pin "11") (pinfunction "O8_11") (pintype "open_collector"))
      (node (ref "X4") (pin "15") (pinfunction "S_15") (pintype "passive"))
    )
    (net (code "791") (name "Net-(U$14-O1)") (class "Default")
      (node (ref "U$14") (pin "18") (pinfunction "O1_18") (pintype "open_collector"))
      (node (ref "X4") (pin "17") (pinfunction "S_17") (pintype "passive"))
    )
    (net (code "792") (name "Net-(U$14-O2)") (class "Default")
      (node (ref "U$14") (pin "17") (pinfunction "O2_17") (pintype "open_collector"))
      (node (ref "X4") (pin "19") (pinfunction "S_19") (pintype "passive"))
    )
    (net (code "793") (name "Net-(U$14-O3)") (class "Default")
      (node (ref "U$14") (pin "16") (pinfunction "O3_16") (pintype "open_collector"))
      (node (ref "X4") (pin "21") (pinfunction "S_21") (pintype "passive"))
    )
    (net (code "794") (name "Net-(U$14-O4)") (class "Default")
      (node (ref "U$14") (pin "15") (pinfunction "O4_15") (pintype "open_collector"))
      (node (ref "X4") (pin "23") (pinfunction "S_23") (pintype "passive"))
    )
    (net (code "795") (name "Net-(U$14-O5)") (class "Default")
      (node (ref "U$14") (pin "14") (pinfunction "O5_14") (pintype "open_collector"))
      (node (ref "X4") (pin "25") (pinfunction "S_25") (pintype "passive"))
    )
    (net (code "796") (name "Net-(U$14-O6)") (class "Default")
      (node (ref "U$14") (pin "13") (pinfunction "O6_13") (pintype "open_collector"))
      (node (ref "X4") (pin "27") (pinfunction "S_27") (pintype "passive"))
    )
    (net (code "797") (name "Net-(U$14-O7)") (class "Default")
      (node (ref "U$14") (pin "12") (pinfunction "O7_12") (pintype "open_collector"))
      (node (ref "X4") (pin "29") (pinfunction "S_29") (pintype "passive"))
    )
    (net (code "798") (name "Net-(U$14-O8)") (class "Default")
      (node (ref "U$14") (pin "11") (pinfunction "O8_11") (pintype "open_collector"))
      (node (ref "X4") (pin "31") (pinfunction "S_31") (pintype "passive"))
    )
    (net (code "799") (name "Net-(U$15-O1)") (class "Default")
      (node (ref "U$15") (pin "18") (pinfunction "O1_18") (pintype "open_collector"))
      (node (ref "X4") (pin "2") (pinfunction "S_2") (pintype "passive"))
    )
    (net (code "800") (name "Net-(U$15-O2)") (class "Default")
      (node (ref "U$15") (pin "17") (pinfunction "O2_17") (pintype "open_collector"))
      (node (ref "X4") (pin "4") (pinfunction "S_4") (pintype "passive"))
    )
    (net (code "801") (name "Net-(U$15-O3)") (class "Default")
      (node (ref "U$15") (pin "16") (pinfunction "O3_16") (pintype "open_collector"))
      (node (ref "X4") (pin "6") (pinfunction "S_6") (pintype "passive"))
    )
    (net (code "802") (name "Net-(U$15-O4)") (class "Default")
      (node (ref "U$15") (pin "15") (pinfunction "O4_15") (pintype "open_collector"))
      (node (ref "X4") (pin "8") (pinfunction "S_8") (pintype "passive"))
    )
    (net (code "803") (name "Net-(U$15-O5)") (class "Default")
      (node (ref "U$15") (pin "14") (pinfunction "O5_14") (pintype "open_collector"))
      (node (ref "X4") (pin "10") (pinfunction "S_10") (pintype "passive"))
    )
    (net (code "804") (name "Net-(U$15-O6)") (class "Default")
      (node (ref "U$15") (pin "13") (pinfunction "O6_13") (pintype "open_collector"))
      (node (ref "X4") (pin "12") (pinfunction "S_12") (pintype "passive"))
    )
    (net (code "805") (name "Net-(U$15-O7)") (class "Default")
      (node (ref "U$15") (pin "12") (pinfunction "O7_12") (pintype "open_collector"))
      (node (ref "X4") (pin "14") (pinfunction "S_14") (pintype "passive"))
    )
    (net (code "806") (name "Net-(U$15-O8)") (class "Default")
      (node (ref "U$15") (pin "11") (pinfunction "O8_11") (pintype "open_collector"))
      (node (ref "X4") (pin "16") (pinfunction "S_16") (pintype "passive"))
    )
    (net (code "807") (name "Net-(U$16-O1)") (class "Default")
      (node (ref "U$16") (pin "18") (pinfunction "O1_18") (pintype "open_collector"))
      (node (ref "X4") (pin "18") (pinfunction "S_18") (pintype "passive"))
    )
    (net (code "808") (name "Net-(U$16-O2)") (class "Default")
      (node (ref "U$16") (pin "17") (pinfunction "O2_17") (pintype "open_collector"))
      (node (ref "X4") (pin "20") (pinfunction "S_20") (pintype "passive"))
    )
    (net (code "809") (name "Net-(U$16-O3)") (class "Default")
      (node (ref "U$16") (pin "16") (pinfunction "O3_16") (pintype "open_collector"))
      (node (ref "X4") (pin "22") (pinfunction "S_22") (pintype "passive"))
    )
    (net (code "810") (name "Net-(U$16-O4)") (class "Default")
      (node (ref "U$16") (pin "15") (pinfunction "O4_15") (pintype "open_collector"))
      (node (ref "X4") (pin "24") (pinfunction "S_24") (pintype "passive"))
    )
    (net (code "811") (name "Net-(U$16-O5)") (class "Default")
      (node (ref "U$16") (pin "14") (pinfunction "O5_14") (pintype "open_collector"))
      (node (ref "X4") (pin "26") (pinfunction "S_26") (pintype "passive"))
    )
    (net (code "812") (name "Net-(U$16-O6)") (class "Default")
      (node (ref "U$16") (pin "13") (pinfunction "O6_13") (pintype "open_collector"))
      (node (ref "X4") (pin "28") (pinfunction "S_28") (pintype "passive"))
    )
    (net (code "813") (name "Net-(U$16-O7)") (class "Default")
      (node (ref "U$16") (pin "12") (pinfunction "O7_12") (pintype "open_collector"))
      (node (ref "X4") (pin "30") (pinfunction "S_30") (pintype "passive"))
    )
    (net (code "814") (name "Net-(U$16-O8)") (class "Default")
      (node (ref "U$16") (pin "11") (pinfunction "O8_11") (pintype "open_collector"))
      (node (ref "X4") (pin "32") (pinfunction "S_32") (pintype "passive"))
    )
    (net (code "815") (name "Net-(U$17-O1)") (class "Default")
      (node (ref "U$17") (pin "18") (pinfunction "O1_18") (pintype "open_collector"))
      (node (ref "X5") (pin "1") (pinfunction "S_1") (pintype "passive"))
    )
    (net (code "816") (name "Net-(U$17-O2)") (class "Default")
      (node (ref "U$17") (pin "17") (pinfunction "O2_17") (pintype "open_collector"))
      (node (ref "X5") (pin "3") (pinfunction "S_3") (pintype "passive"))
    )
    (net (code "817") (name "Net-(U$17-O3)") (class "Default")
      (node (ref "U$17") (pin "16") (pinfunction "O3_16") (pintype "open_collector"))
      (node (ref "X5") (pin "5") (pinfunction "S_5") (pintype "passive"))
    )
    (net (code "818") (name "Net-(U$17-O4)") (class "Default")
      (node (ref "U$17") (pin "15") (pinfunction "O4_15") (pintype "open_collector"))
      (node (ref "X5") (pin "7") (pinfunction "S_7") (pintype "passive"))
    )
    (net (code "819") (name "Net-(U$17-O5)") (class "Default")
      (node (ref "U$17") (pin "14") (pinfunction "O5_14") (pintype "open_collector"))
      (node (ref "X5") (pin "9") (pinfunction "S_9") (pintype "passive"))
    )
    (net (code "820") (name "Net-(U$17-O6)") (class "Default")
      (node (ref "U$17") (pin "13") (pinfunction "O6_13") (pintype "open_collector"))
      (node (ref "X5") (pin "11") (pinfunction "S_11") (pintype "passive"))
    )
    (net (code "821") (name "Net-(U$17-O7)") (class "Default")
      (node (ref "U$17") (pin "12") (pinfunction "O7_12") (pintype "open_collector"))
      (node (ref "X5") (pin "13") (pinfunction "S_13") (pintype "passive"))
    )
    (net (code "822") (name "Net-(U$17-O8)") (class "Default")
      (node (ref "U$17") (pin "11") (pinfunction "O8_11") (pintype "open_collector"))
      (node (ref "X5") (pin "15") (pinfunction "S_15") (pintype "passive"))
    )
    (net (code "823") (name "Net-(U$18-O1)") (class "Default")
      (node (ref "U$18") (pin "18") (pinfunction "O1_18") (pintype "open_collector"))
      (node (ref "X5") (pin "17") (pinfunction "S_17") (pintype "passive"))
    )
    (net (code "824") (name "Net-(U$18-O2)") (class "Default")
      (node (ref "U$18") (pin "17") (pinfunction "O2_17") (pintype "open_collector"))
      (node (ref "X5") (pin "19") (pinfunction "S_19") (pintype "passive"))
    )
    (net (code "825") (name "Net-(U$18-O3)") (class "Default")
      (node (ref "U$18") (pin "16") (pinfunction "O3_16") (pintype "open_collector"))
      (node (ref "X5") (pin "21") (pinfunction "S_21") (pintype "passive"))
    )
    (net (code "826") (name "Net-(U$18-O4)") (class "Default")
      (node (ref "U$18") (pin "15") (pinfunction "O4_15") (pintype "open_collector"))
      (node (ref "X5") (pin "23") (pinfunction "S_23") (pintype "passive"))
    )
    (net (code "827") (name "Net-(U$18-O5)") (class "Default")
      (node (ref "U$18") (pin "14") (pinfunction "O5_14") (pintype "open_collector"))
      (node (ref "X5") (pin "25") (pinfunction "S_25") (pintype "passive"))
    )
    (net (code "828") (name "Net-(U$18-O6)") (class "Default")
      (node (ref "U$18") (pin "13") (pinfunction "O6_13") (pintype "open_collector"))
      (node (ref "X5") (pin "27") (pinfunction "S_27") (pintype "passive"))
    )
    (net (code "829") (name "Net-(U$18-O7)") (class "Default")
      (node (ref "U$18") (pin "12") (pinfunction "O7_12") (pintype "open_collector"))
      (node (ref "X5") (pin "29") (pinfunction "S_29") (pintype "passive"))
    )
    (net (code "830") (name "Net-(U$18-O8)") (class "Default")
      (node (ref "U$18") (pin "11") (pinfunction "O8_11") (pintype "open_collector"))
      (node (ref "X5") (pin "31") (pinfunction "S_31") (pintype "passive"))
    )
    (net (code "831") (name "Net-(U$19-O1)") (class "Default")
      (node (ref "U$19") (pin "18") (pinfunction "O1_18") (pintype "open_collector"))
      (node (ref "X5") (pin "2") (pinfunction "S_2") (pintype "passive"))
    )
    (net (code "832") (name "Net-(U$19-O2)") (class "Default")
      (node (ref "U$19") (pin "17") (pinfunction "O2_17") (pintype "open_collector"))
      (node (ref "X5") (pin "4") (pinfunction "S_4") (pintype "passive"))
    )
    (net (code "833") (name "Net-(U$19-O3)") (class "Default")
      (node (ref "U$19") (pin "16") (pinfunction "O3_16") (pintype "open_collector"))
      (node (ref "X5") (pin "6") (pinfunction "S_6") (pintype "passive"))
    )
    (net (code "834") (name "Net-(U$19-O4)") (class "Default")
      (node (ref "U$19") (pin "15") (pinfunction "O4_15") (pintype "open_collector"))
      (node (ref "X5") (pin "8") (pinfunction "S_8") (pintype "passive"))
    )
    (net (code "835") (name "Net-(U$19-O5)") (class "Default")
      (node (ref "U$19") (pin "14") (pinfunction "O5_14") (pintype "open_collector"))
      (node (ref "X5") (pin "10") (pinfunction "S_10") (pintype "passive"))
    )
    (net (code "836") (name "Net-(U$19-O6)") (class "Default")
      (node (ref "U$19") (pin "13") (pinfunction "O6_13") (pintype "open_collector"))
      (node (ref "X5") (pin "12") (pinfunction "S_12") (pintype "passive"))
    )
    (net (code "837") (name "Net-(U$19-O7)") (class "Default")
      (node (ref "U$19") (pin "12") (pinfunction "O7_12") (pintype "open_collector"))
      (node (ref "X5") (pin "14") (pinfunction "S_14") (pintype "passive"))
    )
    (net (code "838") (name "Net-(U$19-O8)") (class "Default")
      (node (ref "U$19") (pin "11") (pinfunction "O8_11") (pintype "open_collector"))
      (node (ref "X5") (pin "16") (pinfunction "S_16") (pintype "passive"))
    )
    (net (code "839") (name "Net-(U$20-O1)") (class "Default")
      (node (ref "U$20") (pin "18") (pinfunction "O1_18") (pintype "open_collector"))
      (node (ref "X5") (pin "18") (pinfunction "S_18") (pintype "passive"))
    )
    (net (code "840") (name "Net-(U$20-O2)") (class "Default")
      (node (ref "U$20") (pin "17") (pinfunction "O2_17") (pintype "open_collector"))
      (node (ref "X5") (pin "20") (pinfunction "S_20") (pintype "passive"))
    )
    (net (code "841") (name "Net-(U$20-O3)") (class "Default")
      (node (ref "U$20") (pin "16") (pinfunction "O3_16") (pintype "open_collector"))
      (node (ref "X5") (pin "22") (pinfunction "S_22") (pintype "passive"))
    )
    (net (code "842") (name "Net-(U$20-O4)") (class "Default")
      (node (ref "U$20") (pin "15") (pinfunction "O4_15") (pintype "open_collector"))
      (node (ref "X5") (pin "24") (pinfunction "S_24") (pintype "passive"))
    )
    (net (code "843") (name "Net-(U$20-O5)") (class "Default")
      (node (ref "U$20") (pin "14") (pinfunction "O5_14") (pintype "open_collector"))
      (node (ref "X5") (pin "26") (pinfunction "S_26") (pintype "passive"))
    )
    (net (code "844") (name "Net-(U$20-O6)") (class "Default")
      (node (ref "U$20") (pin "13") (pinfunction "O6_13") (pintype "open_collector"))
      (node (ref "X5") (pin "28") (pinfunction "S_28") (pintype "passive"))
    )
    (net (code "845") (name "Net-(U$20-O7)") (class "Default")
      (node (ref "U$20") (pin "12") (pinfunction "O7_12") (pintype "open_collector"))
      (node (ref "X5") (pin "30") (pinfunction "S_30") (pintype "passive"))
    )
    (net (code "846") (name "Net-(U$20-O8)") (class "Default")
      (node (ref "U$20") (pin "11") (pinfunction "O8_11") (pintype "open_collector"))
      (node (ref "X5") (pin "32") (pinfunction "S_32") (pintype "passive"))
    )
    (net (code "847") (name "Net-(U$21-O1)") (class "Default")
      (node (ref "U$21") (pin "18") (pinfunction "O1_18") (pintype "open_collector"))
      (node (ref "X6") (pin "1") (pinfunction "S_1") (pintype "passive"))
    )
    (net (code "848") (name "Net-(U$21-O2)") (class "Default")
      (node (ref "U$21") (pin "17") (pinfunction "O2_17") (pintype "open_collector"))
      (node (ref "X6") (pin "3") (pinfunction "S_3") (pintype "passive"))
    )
    (net (code "849") (name "Net-(U$21-O3)") (class "Default")
      (node (ref "U$21") (pin "16") (pinfunction "O3_16") (pintype "open_collector"))
      (node (ref "X6") (pin "5") (pinfunction "S_5") (pintype "passive"))
    )
    (net (code "850") (name "Net-(U$21-O4)") (class "Default")
      (node (ref "U$21") (pin "15") (pinfunction "O4_15") (pintype "open_collector"))
      (node (ref "X6") (pin "7") (pinfunction "S_7") (pintype "passive"))
    )
    (net (code "851") (name "Net-(U$21-O5)") (class "Default")
      (node (ref "U$21") (pin "14") (pinfunction "O5_14") (pintype "open_collector"))
      (node (ref "X6") (pin "9") (pinfunction "S_9") (pintype "passive"))
    )
    (net (code "852") (name "Net-(U$21-O6)") (class "Default")
      (node (ref "U$21") (pin "13") (pinfunction "O6_13") (pintype "open_collector"))
      (node (ref "X6") (pin "11") (pinfunction "S_11") (pintype "passive"))
    )
    (net (code "853") (name "Net-(U$21-O7)") (class "Default")
      (node (ref "U$21") (pin "12") (pinfunction "O7_12") (pintype "open_collector"))
      (node (ref "X6") (pin "13") (pinfunction "S_13") (pintype "passive"))
    )
    (net (code "854") (name "Net-(U$21-O8)") (class "Default")
      (node (ref "U$21") (pin "11") (pinfunction "O8_11") (pintype "open_collector"))
      (node (ref "X6") (pin "15") (pinfunction "S_15") (pintype "passive"))
    )
    (net (code "855") (name "Net-(U$22-O1)") (class "Default")
      (node (ref "U$22") (pin "18") (pinfunction "O1_18") (pintype "open_collector"))
      (node (ref "X6") (pin "17") (pinfunction "S_17") (pintype "passive"))
    )
    (net (code "856") (name "Net-(U$22-O2)") (class "Default")
      (node (ref "U$22") (pin "17") (pinfunction "O2_17") (pintype "open_collector"))
      (node (ref "X6") (pin "19") (pinfunction "S_19") (pintype "passive"))
    )
    (net (code "857") (name "Net-(U$22-O3)") (class "Default")
      (node (ref "U$22") (pin "16") (pinfunction "O3_16") (pintype "open_collector"))
      (node (ref "X6") (pin "21") (pinfunction "S_21") (pintype "passive"))
    )
    (net (code "858") (name "Net-(U$22-O4)") (class "Default")
      (node (ref "U$22") (pin "15") (pinfunction "O4_15") (pintype "open_collector"))
      (node (ref "X6") (pin "23") (pinfunction "S_23") (pintype "passive"))
    )
    (net (code "859") (name "Net-(U$22-O5)") (class "Default")
      (node (ref "U$22") (pin "14") (pinfunction "O5_14") (pintype "open_collector"))
      (node (ref "X6") (pin "25") (pinfunction "S_25") (pintype "passive"))
    )
    (net (code "860") (name "Net-(U$22-O6)") (class "Default")
      (node (ref "U$22") (pin "13") (pinfunction "O6_13") (pintype "open_collector"))
      (node (ref "X6") (pin "27") (pinfunction "S_27") (pintype "passive"))
    )
    (net (code "861") (name "Net-(U$22-O7)") (class "Default")
      (node (ref "U$22") (pin "12") (pinfunction "O7_12") (pintype "open_collector"))
      (node (ref "X6") (pin "29") (pinfunction "S_29") (pintype "passive"))
    )
    (net (code "862") (name "Net-(U$22-O8)") (class "Default")
      (node (ref "U$22") (pin "11") (pinfunction "O8_11") (pintype "open_collector"))
      (node (ref "X6") (pin "31") (pinfunction "S_31") (pintype "passive"))
    )
    (net (code "863") (name "Net-(U$23-O1)") (class "Default")
      (node (ref "U$23") (pin "18") (pinfunction "O1_18") (pintype "open_collector"))
      (node (ref "X6") (pin "2") (pinfunction "S_2") (pintype "passive"))
    )
    (net (code "864") (name "Net-(U$23-O2)") (class "Default")
      (node (ref "U$23") (pin "17") (pinfunction "O2_17") (pintype "open_collector"))
      (node (ref "X6") (pin "4") (pinfunction "S_4") (pintype "passive"))
    )
    (net (code "865") (name "Net-(U$23-O3)") (class "Default")
      (node (ref "U$23") (pin "16") (pinfunction "O3_16") (pintype "open_collector"))
      (node (ref "X6") (pin "6") (pinfunction "S_6") (pintype "passive"))
    )
    (net (code "866") (name "Net-(U$23-O4)") (class "Default")
      (node (ref "U$23") (pin "15") (pinfunction "O4_15") (pintype "open_collector"))
      (node (ref "X6") (pin "8") (pinfunction "S_8") (pintype "passive"))
    )
    (net (code "867") (name "Net-(U$23-O5)") (class "Default")
      (node (ref "U$23") (pin "14") (pinfunction "O5_14") (pintype "open_collector"))
      (node (ref "X6") (pin "10") (pinfunction "S_10") (pintype "passive"))
    )
    (net (code "868") (name "Net-(U$23-O6)") (class "Default")
      (node (ref "U$23") (pin "13") (pinfunction "O6_13") (pintype "open_collector"))
      (node (ref "X6") (pin "12") (pinfunction "S_12") (pintype "passive"))
    )
    (net (code "869") (name "Net-(U$23-O7)") (class "Default")
      (node (ref "U$23") (pin "12") (pinfunction "O7_12") (pintype "open_collector"))
      (node (ref "X6") (pin "14") (pinfunction "S_14") (pintype "passive"))
    )
    (net (code "870") (name "Net-(U$23-O8)") (class "Default")
      (node (ref "U$23") (pin "11") (pinfunction "O8_11") (pintype "open_collector"))
      (node (ref "X6") (pin "16") (pinfunction "S_16") (pintype "passive"))
    )
    (net (code "871") (name "Net-(U$24-O1)") (class "Default")
      (node (ref "U$24") (pin "18") (pinfunction "O1_18") (pintype "open_collector"))
      (node (ref "X6") (pin "18") (pinfunction "S_18") (pintype "passive"))
    )
    (net (code "872") (name "Net-(U$24-O2)") (class "Default")
      (node (ref "U$24") (pin "17") (pinfunction "O2_17") (pintype "open_collector"))
      (node (ref "X6") (pin "20") (pinfunction "S_20") (pintype "passive"))
    )
    (net (code "873") (name "Net-(U$24-O3)") (class "Default")
      (node (ref "U$24") (pin "16") (pinfunction "O3_16") (pintype "open_collector"))
      (node (ref "X6") (pin "22") (pinfunction "S_22") (pintype "passive"))
    )
    (net (code "874") (name "Net-(U$24-O4)") (class "Default")
      (node (ref "U$24") (pin "15") (pinfunction "O4_15") (pintype "open_collector"))
      (node (ref "X6") (pin "24") (pinfunction "S_24") (pintype "passive"))
    )
    (net (code "875") (name "Net-(U$24-O5)") (class "Default")
      (node (ref "U$24") (pin "14") (pinfunction "O5_14") (pintype "open_collector"))
      (node (ref "X6") (pin "26") (pinfunction "S_26") (pintype "passive"))
    )
    (net (code "876") (name "Net-(U$24-O6)") (class "Default")
      (node (ref "U$24") (pin "13") (pinfunction "O6_13") (pintype "open_collector"))
      (node (ref "X6") (pin "28") (pinfunction "S_28") (pintype "passive"))
    )
    (net (code "877") (name "Net-(U$24-O7)") (class "Default")
      (node (ref "U$24") (pin "12") (pinfunction "O7_12") (pintype "open_collector"))
      (node (ref "X6") (pin "30") (pinfunction "S_30") (pintype "passive"))
    )
    (net (code "878") (name "Net-(U$24-O8)") (class "Default")
      (node (ref "U$24") (pin "11") (pinfunction "O8_11") (pintype "open_collector"))
      (node (ref "X6") (pin "32") (pinfunction "S_32") (pintype "passive"))
    )
    (net (code "879") (name "Net-(U$25-O1)") (class "Default")
      (node (ref "U$25") (pin "18") (pinfunction "O1_18") (pintype "open_collector"))
      (node (ref "X7") (pin "1") (pinfunction "S_1") (pintype "passive"))
    )
    (net (code "880") (name "Net-(U$25-O2)") (class "Default")
      (node (ref "U$25") (pin "17") (pinfunction "O2_17") (pintype "open_collector"))
      (node (ref "X7") (pin "3") (pinfunction "S_3") (pintype "passive"))
    )
    (net (code "881") (name "Net-(U$25-O3)") (class "Default")
      (node (ref "U$25") (pin "16") (pinfunction "O3_16") (pintype "open_collector"))
      (node (ref "X7") (pin "5") (pinfunction "S_5") (pintype "passive"))
    )
    (net (code "882") (name "Net-(U$25-O4)") (class "Default")
      (node (ref "U$25") (pin "15") (pinfunction "O4_15") (pintype "open_collector"))
      (node (ref "X7") (pin "7") (pinfunction "S_7") (pintype "passive"))
    )
    (net (code "883") (name "Net-(U$25-O5)") (class "Default")
      (node (ref "U$25") (pin "14") (pinfunction "O5_14") (pintype "open_collector"))
      (node (ref "X7") (pin "9") (pinfunction "S_9") (pintype "passive"))
    )
    (net (code "884") (name "Net-(U$25-O6)") (class "Default")
      (node (ref "U$25") (pin "13") (pinfunction "O6_13") (pintype "open_collector"))
      (node (ref "X7") (pin "11") (pinfunction "S_11") (pintype "passive"))
    )
    (net (code "885") (name "Net-(U$25-O7)") (class "Default")
      (node (ref "U$25") (pin "12") (pinfunction "O7_12") (pintype "open_collector"))
      (node (ref "X7") (pin "13") (pinfunction "S_13") (pintype "passive"))
    )
    (net (code "886") (name "Net-(U$25-O8)") (class "Default")
      (node (ref "U$25") (pin "11") (pinfunction "O8_11") (pintype "open_collector"))
      (node (ref "X7") (pin "15") (pinfunction "S_15") (pintype "passive"))
    )
    (net (code "887") (name "Net-(U$26-O1)") (class "Default")
      (node (ref "U$26") (pin "18") (pinfunction "O1_18") (pintype "open_collector"))
      (node (ref "X7") (pin "17") (pinfunction "S_17") (pintype "passive"))
    )
    (net (code "888") (name "Net-(U$26-O2)") (class "Default")
      (node (ref "U$26") (pin "17") (pinfunction "O2_17") (pintype "open_collector"))
      (node (ref "X7") (pin "19") (pinfunction "S_19") (pintype "passive"))
    )
    (net (code "889") (name "Net-(U$26-O3)") (class "Default")
      (node (ref "U$26") (pin "16") (pinfunction "O3_16") (pintype "open_collector"))
      (node (ref "X7") (pin "21") (pinfunction "S_21") (pintype "passive"))
    )
    (net (code "890") (name "Net-(U$26-O4)") (class "Default")
      (node (ref "U$26") (pin "15") (pinfunction "O4_15") (pintype "open_collector"))
      (node (ref "X7") (pin "23") (pinfunction "S_23") (pintype "passive"))
    )
    (net (code "891") (name "Net-(U$26-O5)") (class "Default")
      (node (ref "U$26") (pin "14") (pinfunction "O5_14") (pintype "open_collector"))
      (node (ref "X7") (pin "25") (pinfunction "S_25") (pintype "passive"))
    )
    (net (code "892") (name "Net-(U$26-O6)") (class "Default")
      (node (ref "U$26") (pin "13") (pinfunction "O6_13") (pintype "open_collector"))
      (node (ref "X7") (pin "27") (pinfunction "S_27") (pintype "passive"))
    )
    (net (code "893") (name "Net-(U$26-O7)") (class "Default")
      (node (ref "U$26") (pin "12") (pinfunction "O7_12") (pintype "open_collector"))
      (node (ref "X7") (pin "29") (pinfunction "S_29") (pintype "passive"))
    )
    (net (code "894") (name "Net-(U$26-O8)") (class "Default")
      (node (ref "U$26") (pin "11") (pinfunction "O8_11") (pintype "open_collector"))
      (node (ref "X7") (pin "31") (pinfunction "S_31") (pintype "passive"))
    )
    (net (code "895") (name "Net-(U$27-O1)") (class "Default")
      (node (ref "U$27") (pin "18") (pinfunction "O1_18") (pintype "open_collector"))
      (node (ref "X7") (pin "2") (pinfunction "S_2") (pintype "passive"))
    )
    (net (code "896") (name "Net-(U$27-O2)") (class "Default")
      (node (ref "U$27") (pin "17") (pinfunction "O2_17") (pintype "open_collector"))
      (node (ref "X7") (pin "4") (pinfunction "S_4") (pintype "passive"))
    )
    (net (code "897") (name "Net-(U$27-O3)") (class "Default")
      (node (ref "U$27") (pin "16") (pinfunction "O3_16") (pintype "open_collector"))
      (node (ref "X7") (pin "6") (pinfunction "S_6") (pintype "passive"))
    )
    (net (code "898") (name "Net-(U$27-O4)") (class "Default")
      (node (ref "U$27") (pin "15") (pinfunction "O4_15") (pintype "open_collector"))
      (node (ref "X7") (pin "8") (pinfunction "S_8") (pintype "passive"))
    )
    (net (code "899") (name "Net-(U$27-O5)") (class "Default")
      (node (ref "U$27") (pin "14") (pinfunction "O5_14") (pintype "open_collector"))
      (node (ref "X7") (pin "10") (pinfunction "S_10") (pintype "passive"))
    )
    (net (code "900") (name "Net-(U$27-O6)") (class "Default")
      (node (ref "U$27") (pin "13") (pinfunction "O6_13") (pintype "open_collector"))
      (node (ref "X7") (pin "12") (pinfunction "S_12") (pintype "passive"))
    )
    (net (code "901") (name "Net-(U$27-O7)") (class "Default")
      (node (ref "U$27") (pin "12") (pinfunction "O7_12") (pintype "open_collector"))
      (node (ref "X7") (pin "14") (pinfunction "S_14") (pintype "passive"))
    )
    (net (code "902") (name "Net-(U$27-O8)") (class "Default")
      (node (ref "U$27") (pin "11") (pinfunction "O8_11") (pintype "open_collector"))
      (node (ref "X7") (pin "16") (pinfunction "S_16") (pintype "passive"))
    )
    (net (code "903") (name "Net-(U$28-O1)") (class "Default")
      (node (ref "U$28") (pin "18") (pinfunction "O1_18") (pintype "open_collector"))
      (node (ref "X7") (pin "18") (pinfunction "S_18") (pintype "passive"))
    )
    (net (code "904") (name "Net-(U$28-O2)") (class "Default")
      (node (ref "U$28") (pin "17") (pinfunction "O2_17") (pintype "open_collector"))
      (node (ref "X7") (pin "20") (pinfunction "S_20") (pintype "passive"))
    )
    (net (code "905") (name "Net-(U$28-O3)") (class "Default")
      (node (ref "U$28") (pin "16") (pinfunction "O3_16") (pintype "open_collector"))
      (node (ref "X7") (pin "22") (pinfunction "S_22") (pintype "passive"))
    )
    (net (code "906") (name "Net-(U$28-O4)") (class "Default")
      (node (ref "U$28") (pin "15") (pinfunction "O4_15") (pintype "open_collector"))
      (node (ref "X7") (pin "24") (pinfunction "S_24") (pintype "passive"))
    )
    (net (code "907") (name "Net-(U$28-O5)") (class "Default")
      (node (ref "U$28") (pin "14") (pinfunction "O5_14") (pintype "open_collector"))
      (node (ref "X7") (pin "26") (pinfunction "S_26") (pintype "passive"))
    )
    (net (code "908") (name "Net-(U$28-O6)") (class "Default")
      (node (ref "U$28") (pin "13") (pinfunction "O6_13") (pintype "open_collector"))
      (node (ref "X7") (pin "28") (pinfunction "S_28") (pintype "passive"))
    )
    (net (code "909") (name "Net-(U$28-O7)") (class "Default")
      (node (ref "U$28") (pin "12") (pinfunction "O7_12") (pintype "open_collector"))
      (node (ref "X7") (pin "30") (pinfunction "S_30") (pintype "passive"))
    )
    (net (code "910") (name "Net-(U$28-O8)") (class "Default")
      (node (ref "U$28") (pin "11") (pinfunction "O8_11") (pintype "open_collector"))
      (node (ref "X7") (pin "32") (pinfunction "S_32") (pintype "passive"))
    )
    (net (code "911") (name "Net-(U$29-O1)") (class "Default")
      (node (ref "U$29") (pin "18") (pinfunction "O1_18") (pintype "open_collector"))
      (node (ref "X8") (pin "1") (pinfunction "S_1") (pintype "passive"))
    )
    (net (code "912") (name "Net-(U$29-O2)") (class "Default")
      (node (ref "U$29") (pin "17") (pinfunction "O2_17") (pintype "open_collector"))
      (node (ref "X8") (pin "3") (pinfunction "S_3") (pintype "passive"))
    )
    (net (code "913") (name "Net-(U$29-O3)") (class "Default")
      (node (ref "U$29") (pin "16") (pinfunction "O3_16") (pintype "open_collector"))
      (node (ref "X8") (pin "5") (pinfunction "S_5") (pintype "passive"))
    )
    (net (code "914") (name "Net-(U$29-O4)") (class "Default")
      (node (ref "U$29") (pin "15") (pinfunction "O4_15") (pintype "open_collector"))
      (node (ref "X8") (pin "7") (pinfunction "S_7") (pintype "passive"))
    )
    (net (code "915") (name "Net-(U$29-O5)") (class "Default")
      (node (ref "U$29") (pin "14") (pinfunction "O5_14") (pintype "open_collector"))
      (node (ref "X8") (pin "9") (pinfunction "S_9") (pintype "passive"))
    )
    (net (code "916") (name "Net-(U$29-O6)") (class "Default")
      (node (ref "U$29") (pin "13") (pinfunction "O6_13") (pintype "open_collector"))
      (node (ref "X8") (pin "11") (pinfunction "S_11") (pintype "passive"))
    )
    (net (code "917") (name "Net-(U$29-O7)") (class "Default")
      (node (ref "U$29") (pin "12") (pinfunction "O7_12") (pintype "open_collector"))
      (node (ref "X8") (pin "13") (pinfunction "S_13") (pintype "passive"))
    )
    (net (code "918") (name "Net-(U$29-O8)") (class "Default")
      (node (ref "U$29") (pin "11") (pinfunction "O8_11") (pintype "open_collector"))
      (node (ref "X8") (pin "15") (pinfunction "S_15") (pintype "passive"))
    )
    (net (code "919") (name "Net-(U$30-O1)") (class "Default")
      (node (ref "U$30") (pin "18") (pinfunction "O1_18") (pintype "open_collector"))
      (node (ref "X8") (pin "17") (pinfunction "S_17") (pintype "passive"))
    )
    (net (code "920") (name "Net-(U$30-O2)") (class "Default")
      (node (ref "U$30") (pin "17") (pinfunction "O2_17") (pintype "open_collector"))
      (node (ref "X8") (pin "19") (pinfunction "S_19") (pintype "passive"))
    )
    (net (code "921") (name "Net-(U$30-O3)") (class "Default")
      (node (ref "U$30") (pin "16") (pinfunction "O3_16") (pintype "open_collector"))
      (node (ref "X8") (pin "21") (pinfunction "S_21") (pintype "passive"))
    )
    (net (code "922") (name "Net-(U$30-O4)") (class "Default")
      (node (ref "U$30") (pin "15") (pinfunction "O4_15") (pintype "open_collector"))
      (node (ref "X8") (pin "23") (pinfunction "S_23") (pintype "passive"))
    )
    (net (code "923") (name "Net-(U$30-O5)") (class "Default")
      (node (ref "U$30") (pin "14") (pinfunction "O5_14") (pintype "open_collector"))
      (node (ref "X8") (pin "25") (pinfunction "S_25") (pintype "passive"))
    )
    (net (code "924") (name "Net-(U$30-O6)") (class "Default")
      (node (ref "U$30") (pin "13") (pinfunction "O6_13") (pintype "open_collector"))
      (node (ref "X8") (pin "27") (pinfunction "S_27") (pintype "passive"))
    )
    (net (code "925") (name "Net-(U$30-O7)") (class "Default")
      (node (ref "U$30") (pin "12") (pinfunction "O7_12") (pintype "open_collector"))
      (node (ref "X8") (pin "29") (pinfunction "S_29") (pintype "passive"))
    )
    (net (code "926") (name "Net-(U$30-O8)") (class "Default")
      (node (ref "U$30") (pin "11") (pinfunction "O8_11") (pintype "open_collector"))
      (node (ref "X8") (pin "31") (pinfunction "S_31") (pintype "passive"))
    )
    (net (code "927") (name "Net-(U$31-O1)") (class "Default")
      (node (ref "U$31") (pin "18") (pinfunction "O1_18") (pintype "open_collector"))
      (node (ref "X8") (pin "2") (pinfunction "S_2") (pintype "passive"))
    )
    (net (code "928") (name "Net-(U$31-O2)") (class "Default")
      (node (ref "U$31") (pin "17") (pinfunction "O2_17") (pintype "open_collector"))
      (node (ref "X8") (pin "4") (pinfunction "S_4") (pintype "passive"))
    )
    (net (code "929") (name "Net-(U$31-O3)") (class "Default")
      (node (ref "U$31") (pin "16") (pinfunction "O3_16") (pintype "open_collector"))
      (node (ref "X8") (pin "6") (pinfunction "S_6") (pintype "passive"))
    )
    (net (code "930") (name "Net-(U$31-O4)") (class "Default")
      (node (ref "U$31") (pin "15") (pinfunction "O4_15") (pintype "open_collector"))
      (node (ref "X8") (pin "8") (pinfunction "S_8") (pintype "passive"))
    )
    (net (code "931") (name "Net-(U$31-O5)") (class "Default")
      (node (ref "U$31") (pin "14") (pinfunction "O5_14") (pintype "open_collector"))
      (node (ref "X8") (pin "10") (pinfunction "S_10") (pintype "passive"))
    )
    (net (code "932") (name "Net-(U$31-O6)") (class "Default")
      (node (ref "U$31") (pin "13") (pinfunction "O6_13") (pintype "open_collector"))
      (node (ref "X8") (pin "12") (pinfunction "S_12") (pintype "passive"))
    )
    (net (code "933") (name "Net-(U$31-O7)") (class "Default")
      (node (ref "U$31") (pin "12") (pinfunction "O7_12") (pintype "open_collector"))
      (node (ref "X8") (pin "14") (pinfunction "S_14") (pintype "passive"))
    )
    (net (code "934") (name "Net-(U$31-O8)") (class "Default")
      (node (ref "U$31") (pin "11") (pinfunction "O8_11") (pintype "open_collector"))
      (node (ref "X8") (pin "16") (pinfunction "S_16") (pintype "passive"))
    )
    (net (code "935") (name "Net-(U$32-O1)") (class "Default")
      (node (ref "U$32") (pin "18") (pinfunction "O1_18") (pintype "open_collector"))
      (node (ref "X8") (pin "18") (pinfunction "S_18") (pintype "passive"))
    )
    (net (code "936") (name "Net-(U$32-O2)") (class "Default")
      (node (ref "U$32") (pin "17") (pinfunction "O2_17") (pintype "open_collector"))
      (node (ref "X8") (pin "20") (pinfunction "S_20") (pintype "passive"))
    )
    (net (code "937") (name "Net-(U$32-O3)") (class "Default")
      (node (ref "U$32") (pin "16") (pinfunction "O3_16") (pintype "open_collector"))
      (node (ref "X8") (pin "22") (pinfunction "S_22") (pintype "passive"))
    )
    (net (code "938") (name "Net-(U$32-O4)") (class "Default")
      (node (ref "U$32") (pin "15") (pinfunction "O4_15") (pintype "open_collector"))
      (node (ref "X8") (pin "24") (pinfunction "S_24") (pintype "passive"))
    )
    (net (code "939") (name "Net-(U$32-O5)") (class "Default")
      (node (ref "U$32") (pin "14") (pinfunction "O5_14") (pintype "open_collector"))
      (node (ref "X8") (pin "26") (pinfunction "S_26") (pintype "passive"))
    )
    (net (code "940") (name "Net-(U$32-O6)") (class "Default")
      (node (ref "U$32") (pin "13") (pinfunction "O6_13") (pintype "open_collector"))
      (node (ref "X8") (pin "28") (pinfunction "S_28") (pintype "passive"))
    )
    (net (code "941") (name "Net-(U$32-O7)") (class "Default")
      (node (ref "U$32") (pin "12") (pinfunction "O7_12") (pintype "open_collector"))
      (node (ref "X8") (pin "30") (pinfunction "S_30") (pintype "passive"))
    )
    (net (code "942") (name "Net-(U$32-O8)") (class "Default")
      (node (ref "U$32") (pin "11") (pinfunction "O8_11") (pintype "open_collector"))
      (node (ref "X8") (pin "32") (pinfunction "S_32") (pintype "passive"))
    )
    (net (code "943") (name "Net-(U$33-O1)") (class "Default")
      (node (ref "U$33") (pin "18") (pinfunction "O1_18") (pintype "open_collector"))
      (node (ref "X9") (pin "1") (pinfunction "S_1") (pintype "passive"))
    )
    (net (code "944") (name "Net-(U$33-O2)") (class "Default")
      (node (ref "U$33") (pin "17") (pinfunction "O2_17") (pintype "open_collector"))
      (node (ref "X9") (pin "3") (pinfunction "S_3") (pintype "passive"))
    )
    (net (code "945") (name "Net-(U$33-O3)") (class "Default")
      (node (ref "U$33") (pin "16") (pinfunction "O3_16") (pintype "open_collector"))
      (node (ref "X9") (pin "5") (pinfunction "S_5") (pintype "passive"))
    )
    (net (code "946") (name "Net-(U$33-O4)") (class "Default")
      (node (ref "U$33") (pin "15") (pinfunction "O4_15") (pintype "open_collector"))
      (node (ref "X9") (pin "7") (pinfunction "S_7") (pintype "passive"))
    )
    (net (code "947") (name "Net-(U$33-O5)") (class "Default")
      (node (ref "U$33") (pin "14") (pinfunction "O5_14") (pintype "open_collector"))
      (node (ref "X9") (pin "9") (pinfunction "S_9") (pintype "passive"))
    )
    (net (code "948") (name "Net-(U$33-O6)") (class "Default")
      (node (ref "U$33") (pin "13") (pinfunction "O6_13") (pintype "open_collector"))
      (node (ref "X9") (pin "11") (pinfunction "S_11") (pintype "passive"))
    )
    (net (code "949") (name "Net-(U$33-O7)") (class "Default")
      (node (ref "U$33") (pin "12") (pinfunction "O7_12") (pintype "open_collector"))
      (node (ref "X9") (pin "13") (pinfunction "S_13") (pintype "passive"))
    )
    (net (code "950") (name "Net-(U$33-O8)") (class "Default")
      (node (ref "U$33") (pin "11") (pinfunction "O8_11") (pintype "open_collector"))
      (node (ref "X9") (pin "15") (pinfunction "S_15") (pintype "passive"))
    )
    (net (code "951") (name "Net-(U$34-O1)") (class "Default")
      (node (ref "U$34") (pin "18") (pinfunction "O1_18") (pintype "open_collector"))
      (node (ref "X9") (pin "17") (pinfunction "S_17") (pintype "passive"))
    )
    (net (code "952") (name "Net-(U$34-O2)") (class "Default")
      (node (ref "U$34") (pin "17") (pinfunction "O2_17") (pintype "open_collector"))
      (node (ref "X9") (pin "19") (pinfunction "S_19") (pintype "passive"))
    )
    (net (code "953") (name "Net-(U$34-O3)") (class "Default")
      (node (ref "U$34") (pin "16") (pinfunction "O3_16") (pintype "open_collector"))
      (node (ref "X9") (pin "21") (pinfunction "S_21") (pintype "passive"))
    )
    (net (code "954") (name "Net-(U$34-O4)") (class "Default")
      (node (ref "U$34") (pin "15") (pinfunction "O4_15") (pintype "open_collector"))
      (node (ref "X9") (pin "23") (pinfunction "S_23") (pintype "passive"))
    )
    (net (code "955") (name "Net-(U$34-O5)") (class "Default")
      (node (ref "U$34") (pin "14") (pinfunction "O5_14") (pintype "open_collector"))
      (node (ref "X9") (pin "25") (pinfunction "S_25") (pintype "passive"))
    )
    (net (code "956") (name "Net-(U$34-O6)") (class "Default")
      (node (ref "U$34") (pin "13") (pinfunction "O6_13") (pintype "open_collector"))
      (node (ref "X9") (pin "27") (pinfunction "S_27") (pintype "passive"))
    )
    (net (code "957") (name "Net-(U$34-O7)") (class "Default")
      (node (ref "U$34") (pin "12") (pinfunction "O7_12") (pintype "open_collector"))
      (node (ref "X9") (pin "29") (pinfunction "S_29") (pintype "passive"))
    )
    (net (code "958") (name "Net-(U$34-O8)") (class "Default")
      (node (ref "U$34") (pin "11") (pinfunction "O8_11") (pintype "open_collector"))
      (node (ref "X9") (pin "31") (pinfunction "S_31") (pintype "passive"))
    )
    (net (code "959") (name "Net-(U$35-O1)") (class "Default")
      (node (ref "U$35") (pin "18") (pinfunction "O1_18") (pintype "open_collector"))
      (node (ref "X9") (pin "2") (pinfunction "S_2") (pintype "passive"))
    )
    (net (code "960") (name "Net-(U$35-O2)") (class "Default")
      (node (ref "U$35") (pin "17") (pinfunction "O2_17") (pintype "open_collector"))
      (node (ref "X9") (pin "4") (pinfunction "S_4") (pintype "passive"))
    )
    (net (code "961") (name "Net-(U$35-O3)") (class "Default")
      (node (ref "U$35") (pin "16") (pinfunction "O3_16") (pintype "open_collector"))
      (node (ref "X9") (pin "6") (pinfunction "S_6") (pintype "passive"))
    )
    (net (code "962") (name "Net-(U$35-O4)") (class "Default")
      (node (ref "U$35") (pin "15") (pinfunction "O4_15") (pintype "open_collector"))
      (node (ref "X9") (pin "8") (pinfunction "S_8") (pintype "passive"))
    )
    (net (code "963") (name "Net-(U$35-O5)") (class "Default")
      (node (ref "U$35") (pin "14") (pinfunction "O5_14") (pintype "open_collector"))
      (node (ref "X9") (pin "10") (pinfunction "S_10") (pintype "passive"))
    )
    (net (code "964") (name "Net-(U$35-O6)") (class "Default")
      (node (ref "U$35") (pin "13") (pinfunction "O6_13") (pintype "open_collector"))
      (node (ref "X9") (pin "12") (pinfunction "S_12") (pintype "passive"))
    )
    (net (code "965") (name "Net-(U$35-O7)") (class "Default")
      (node (ref "U$35") (pin "12") (pinfunction "O7_12") (pintype "open_collector"))
      (node (ref "X9") (pin "14") (pinfunction "S_14") (pintype "passive"))
    )
    (net (code "966") (name "Net-(U$35-O8)") (class "Default")
      (node (ref "U$35") (pin "11") (pinfunction "O8_11") (pintype "open_collector"))
      (node (ref "X9") (pin "16") (pinfunction "S_16") (pintype "passive"))
    )
    (net (code "967") (name "Net-(U$36-O1)") (class "Default")
      (node (ref "U$36") (pin "18") (pinfunction "O1_18") (pintype "open_collector"))
      (node (ref "X9") (pin "18") (pinfunction "S_18") (pintype "passive"))
    )
    (net (code "968") (name "Net-(U$36-O2)") (class "Default")
      (node (ref "U$36") (pin "17") (pinfunction "O2_17") (pintype "open_collector"))
      (node (ref "X9") (pin "20") (pinfunction "S_20") (pintype "passive"))
    )
    (net (code "969") (name "Net-(U$36-O3)") (class "Default")
      (node (ref "U$36") (pin "16") (pinfunction "O3_16") (pintype "open_collector"))
      (node (ref "X9") (pin "22") (pinfunction "S_22") (pintype "passive"))
    )
    (net (code "970") (name "Net-(U$36-O4)") (class "Default")
      (node (ref "U$36") (pin "15") (pinfunction "O4_15") (pintype "open_collector"))
      (node (ref "X9") (pin "24") (pinfunction "S_24") (pintype "passive"))
    )
    (net (code "971") (name "Net-(U$36-O5)") (class "Default")
      (node (ref "U$36") (pin "14") (pinfunction "O5_14") (pintype "open_collector"))
      (node (ref "X9") (pin "26") (pinfunction "S_26") (pintype "passive"))
    )
    (net (code "972") (name "Net-(U$36-O6)") (class "Default")
      (node (ref "U$36") (pin "13") (pinfunction "O6_13") (pintype "open_collector"))
      (node (ref "X9") (pin "28") (pinfunction "S_28") (pintype "passive"))
    )
    (net (code "973") (name "Net-(U$36-O7)") (class "Default")
      (node (ref "U$36") (pin "12") (pinfunction "O7_12") (pintype "open_collector"))
      (node (ref "X9") (pin "30") (pinfunction "S_30") (pintype "passive"))
    )
    (net (code "974") (name "Net-(U$36-O8)") (class "Default")
      (node (ref "U$36") (pin "11") (pinfunction "O8_11") (pintype "open_collector"))
      (node (ref "X9") (pin "32") (pinfunction "S_32") (pintype "passive"))
    )
    (net (code "975") (name "Net-(U$37-O1)") (class "Default")
      (node (ref "U$37") (pin "18") (pinfunction "O1_18") (pintype "open_collector"))
      (node (ref "X10") (pin "1") (pinfunction "S_1") (pintype "passive"))
    )
    (net (code "976") (name "Net-(U$37-O2)") (class "Default")
      (node (ref "U$37") (pin "17") (pinfunction "O2_17") (pintype "open_collector"))
      (node (ref "X10") (pin "3") (pinfunction "S_3") (pintype "passive"))
    )
    (net (code "977") (name "Net-(U$37-O3)") (class "Default")
      (node (ref "U$37") (pin "16") (pinfunction "O3_16") (pintype "open_collector"))
      (node (ref "X10") (pin "5") (pinfunction "S_5") (pintype "passive"))
    )
    (net (code "978") (name "Net-(U$37-O4)") (class "Default")
      (node (ref "U$37") (pin "15") (pinfunction "O4_15") (pintype "open_collector"))
      (node (ref "X10") (pin "7") (pinfunction "S_7") (pintype "passive"))
    )
    (net (code "979") (name "Net-(U$37-O5)") (class "Default")
      (node (ref "U$37") (pin "14") (pinfunction "O5_14") (pintype "open_collector"))
      (node (ref "X10") (pin "9") (pinfunction "S_9") (pintype "passive"))
    )
    (net (code "980") (name "Net-(U$37-O6)") (class "Default")
      (node (ref "U$37") (pin "13") (pinfunction "O6_13") (pintype "open_collector"))
      (node (ref "X10") (pin "11") (pinfunction "S_11") (pintype "passive"))
    )
    (net (code "981") (name "Net-(U$37-O7)") (class "Default")
      (node (ref "U$37") (pin "12") (pinfunction "O7_12") (pintype "open_collector"))
      (node (ref "X10") (pin "13") (pinfunction "S_13") (pintype "passive"))
    )
    (net (code "982") (name "Net-(U$37-O8)") (class "Default")
      (node (ref "U$37") (pin "11") (pinfunction "O8_11") (pintype "open_collector"))
      (node (ref "X10") (pin "15") (pinfunction "S_15") (pintype "passive"))
    )
    (net (code "983") (name "Net-(U$38-O1)") (class "Default")
      (node (ref "U$38") (pin "18") (pinfunction "O1_18") (pintype "open_collector"))
      (node (ref "X10") (pin "17") (pinfunction "S_17") (pintype "passive"))
    )
    (net (code "984") (name "Net-(U$38-O2)") (class "Default")
      (node (ref "U$38") (pin "17") (pinfunction "O2_17") (pintype "open_collector"))
      (node (ref "X10") (pin "19") (pinfunction "S_19") (pintype "passive"))
    )
    (net (code "985") (name "Net-(U$38-O3)") (class "Default")
      (node (ref "U$38") (pin "16") (pinfunction "O3_16") (pintype "open_collector"))
      (node (ref "X10") (pin "21") (pinfunction "S_21") (pintype "passive"))
    )
    (net (code "986") (name "Net-(U$38-O4)") (class "Default")
      (node (ref "U$38") (pin "15") (pinfunction "O4_15") (pintype "open_collector"))
      (node (ref "X10") (pin "23") (pinfunction "S_23") (pintype "passive"))
    )
    (net (code "987") (name "Net-(U$38-O5)") (class "Default")
      (node (ref "U$38") (pin "14") (pinfunction "O5_14") (pintype "open_collector"))
      (node (ref "X10") (pin "25") (pinfunction "S_25") (pintype "passive"))
    )
    (net (code "988") (name "Net-(U$38-O6)") (class "Default")
      (node (ref "U$38") (pin "13") (pinfunction "O6_13") (pintype "open_collector"))
      (node (ref "X10") (pin "27") (pinfunction "S_27") (pintype "passive"))
    )
    (net (code "989") (name "Net-(U$38-O7)") (class "Default")
      (node (ref "U$38") (pin "12") (pinfunction "O7_12") (pintype "open_collector"))
      (node (ref "X10") (pin "29") (pinfunction "S_29") (pintype "passive"))
    )
    (net (code "990") (name "Net-(U$38-O8)") (class "Default")
      (node (ref "U$38") (pin "11") (pinfunction "O8_11") (pintype "open_collector"))
      (node (ref "X10") (pin "31") (pinfunction "S_31") (pintype "passive"))
    )
    (net (code "991") (name "Net-(U$39-O1)") (class "Default")
      (node (ref "U$39") (pin "18") (pinfunction "O1_18") (pintype "open_collector"))
      (node (ref "X10") (pin "2") (pinfunction "S_2") (pintype "passive"))
    )
    (net (code "992") (name "Net-(U$39-O2)") (class "Default")
      (node (ref "U$39") (pin "17") (pinfunction "O2_17") (pintype "open_collector"))
      (node (ref "X10") (pin "4") (pinfunction "S_4") (pintype "passive"))
    )
    (net (code "993") (name "Net-(U$39-O3)") (class "Default")
      (node (ref "U$39") (pin "16") (pinfunction "O3_16") (pintype "open_collector"))
      (node (ref "X10") (pin "6") (pinfunction "S_6") (pintype "passive"))
    )
    (net (code "994") (name "Net-(U$39-O4)") (class "Default")
      (node (ref "U$39") (pin "15") (pinfunction "O4_15") (pintype "open_collector"))
      (node (ref "X10") (pin "8") (pinfunction "S_8") (pintype "passive"))
    )
    (net (code "995") (name "Net-(U$39-O5)") (class "Default")
      (node (ref "U$39") (pin "14") (pinfunction "O5_14") (pintype "open_collector"))
      (node (ref "X10") (pin "10") (pinfunction "S_10") (pintype "passive"))
    )
    (net (code "996") (name "Net-(U$39-O6)") (class "Default")
      (node (ref "U$39") (pin "13") (pinfunction "O6_13") (pintype "open_collector"))
      (node (ref "X10") (pin "12") (pinfunction "S_12") (pintype "passive"))
    )
    (net (code "997") (name "Net-(U$39-O7)") (class "Default")
      (node (ref "U$39") (pin "12") (pinfunction "O7_12") (pintype "open_collector"))
      (node (ref "X10") (pin "14") (pinfunction "S_14") (pintype "passive"))
    )
    (net (code "998") (name "Net-(U$39-O8)") (class "Default")
      (node (ref "U$39") (pin "11") (pinfunction "O8_11") (pintype "open_collector"))
      (node (ref "X10") (pin "16") (pinfunction "S_16") (pintype "passive"))
    )
    (net (code "999") (name "Net-(U$40-O1)") (class "Default")
      (node (ref "U$40") (pin "18") (pinfunction "O1_18") (pintype "open_collector"))
      (node (ref "X10") (pin "18") (pinfunction "S_18") (pintype "passive"))
    )
    (net (code "1000") (name "Net-(U$40-O2)") (class "Default")
      (node (ref "U$40") (pin "17") (pinfunction "O2_17") (pintype "open_collector"))
      (node (ref "X10") (pin "20") (pinfunction "S_20") (pintype "passive"))
    )
    (net (code "1001") (name "Net-(U$40-O3)") (class "Default")
      (node (ref "U$40") (pin "16") (pinfunction "O3_16") (pintype "open_collector"))
      (node (ref "X10") (pin "22") (pinfunction "S_22") (pintype "passive"))
    )
    (net (code "1002") (name "Net-(U$40-O4)") (class "Default")
      (node (ref "U$40") (pin "15") (pinfunction "O4_15") (pintype "open_collector"))
      (node (ref "X10") (pin "24") (pinfunction "S_24") (pintype "passive"))
    )
    (net (code "1003") (name "Net-(U$40-O5)") (class "Default")
      (node (ref "U$40") (pin "14") (pinfunction "O5_14") (pintype "open_collector"))
      (node (ref "X10") (pin "26") (pinfunction "S_26") (pintype "passive"))
    )
    (net (code "1004") (name "Net-(U$40-O6)") (class "Default")
      (node (ref "U$40") (pin "13") (pinfunction "O6_13") (pintype "open_collector"))
      (node (ref "X10") (pin "28") (pinfunction "S_28") (pintype "passive"))
    )
    (net (code "1005") (name "Net-(U$40-O7)") (class "Default")
      (node (ref "U$40") (pin "12") (pinfunction "O7_12") (pintype "open_collector"))
      (node (ref "X10") (pin "30") (pinfunction "S_30") (pintype "passive"))
    )
    (net (code "1006") (name "Net-(U$40-O8)") (class "Default")
      (node (ref "U$40") (pin "11") (pinfunction "O8_11") (pintype "open_collector"))
      (node (ref "X10") (pin "32") (pinfunction "S_32") (pintype "passive"))
    )
    (net (code "1007") (name "VCC") (class "Default")
      (node (ref "X11") (pin "8") (pinfunction "S_8") (pintype "passive"))
    )
    (net (code "1008") (name "unconnected-(IC103A-2D2-Pad35)") (class "Default")
      (node (ref "IC103") (pin "35") (pinfunction "2D2_35") (pintype "input"))
    )
    (net (code "1009") (name "unconnected-(IC103A-2D3-Pad33)") (class "Default")
      (node (ref "IC103") (pin "33") (pinfunction "2D3_33") (pintype "input"))
    )
    (net (code "1010") (name "unconnected-(IC103A-2D4-Pad32)") (class "Default")
      (node (ref "IC103") (pin "32") (pinfunction "2D4_32") (pintype "input"))
    )
    (net (code "1011") (name "unconnected-(IC103A-2D5-Pad30)") (class "Default")
      (node (ref "IC103") (pin "30") (pinfunction "2D5_30") (pintype "input"))
    )
    (net (code "1012") (name "unconnected-(IC103A-2D6-Pad29)") (class "Default")
      (node (ref "IC103") (pin "29") (pinfunction "2D6_29") (pintype "input"))
    )
    (net (code "1013") (name "unconnected-(IC103A-2D7-Pad27)") (class "Default")
      (node (ref "IC103") (pin "27") (pinfunction "2D7_27") (pintype "input"))
    )
    (net (code "1014") (name "unconnected-(IC103A-2D8-Pad26)") (class "Default")
      (node (ref "IC103") (pin "26") (pinfunction "2D8_26") (pintype "input"))
    )
    (net (code "1015") (name "unconnected-(IC103A-2Q1-Pad13)") (class "Default")
      (node (ref "IC103") (pin "13") (pinfunction "2Q1_13") (pintype "tri_state"))
    )
    (net (code "1016") (name "unconnected-(IC103A-2Q2-Pad14)") (class "Default")
      (node (ref "IC103") (pin "14") (pinfunction "2Q2_14") (pintype "tri_state"))
    )
    (net (code "1017") (name "unconnected-(IC103A-2Q3-Pad16)") (class "Default")
      (node (ref "IC103") (pin "16") (pinfunction "2Q3_16") (pintype "tri_state"))
    )
    (net (code "1018") (name "unconnected-(IC103A-2Q4-Pad17)") (class "Default")
      (node (ref "IC103") (pin "17") (pinfunction "2Q4_17") (pintype "tri_state"))
    )
    (net (code "1019") (name "unconnected-(IC103A-2Q5-Pad19)") (class "Default")
      (node (ref "IC103") (pin "19") (pinfunction "2Q5_19") (pintype "tri_state"))
    )
    (net (code "1020") (name "unconnected-(IC103A-2Q6-Pad20)") (class "Default")
      (node (ref "IC103") (pin "20") (pinfunction "2Q6_20") (pintype "tri_state"))
    )
    (net (code "1021") (name "unconnected-(IC103A-2Q7-Pad22)") (class "Default")
      (node (ref "IC103") (pin "22") (pinfunction "2Q7_22") (pintype "tri_state"))
    )
    (net (code "1022") (name "unconnected-(IC103A-2Q8-Pad23)") (class "Default")
      (node (ref "IC103") (pin "23") (pinfunction "2Q8_23") (pintype "tri_state"))
    )
    (net (code "1023") (name "unconnected-(X11B-S-Pad10)") (class "Default")
      (node (ref "X11") (pin "10") (pinfunction "S_10") (pintype "passive"))
    )
    (net (code "1024") (name "unconnected-(X11C-S-Pad11)") (class "Default")
      (node (ref "X11") (pin "11") (pinfunction "S_11") (pintype "passive"))
    )
    (net (code "1025") (name "unconnected-(X11D-S-Pad12)") (class "Default")
      (node (ref "X11") (pin "12") (pinfunction "S_12") (pintype "passive"))
    )
    (net (code "1026") (name "unconnected-(X11E-S-Pad13)") (class "Default")
      (node (ref "X11") (pin "13") (pinfunction "S_13") (pintype "passive"))
    )
    (net (code "1027") (name "unconnected-(X11F-S-Pad14)") (class "Default")
      (node (ref "X11") (pin "14") (pinfunction "S_14") (pintype "passive"))
    )
  )
)
